# Lafferty2.net
KiCad netlist of a schematic drawn in EAGLE
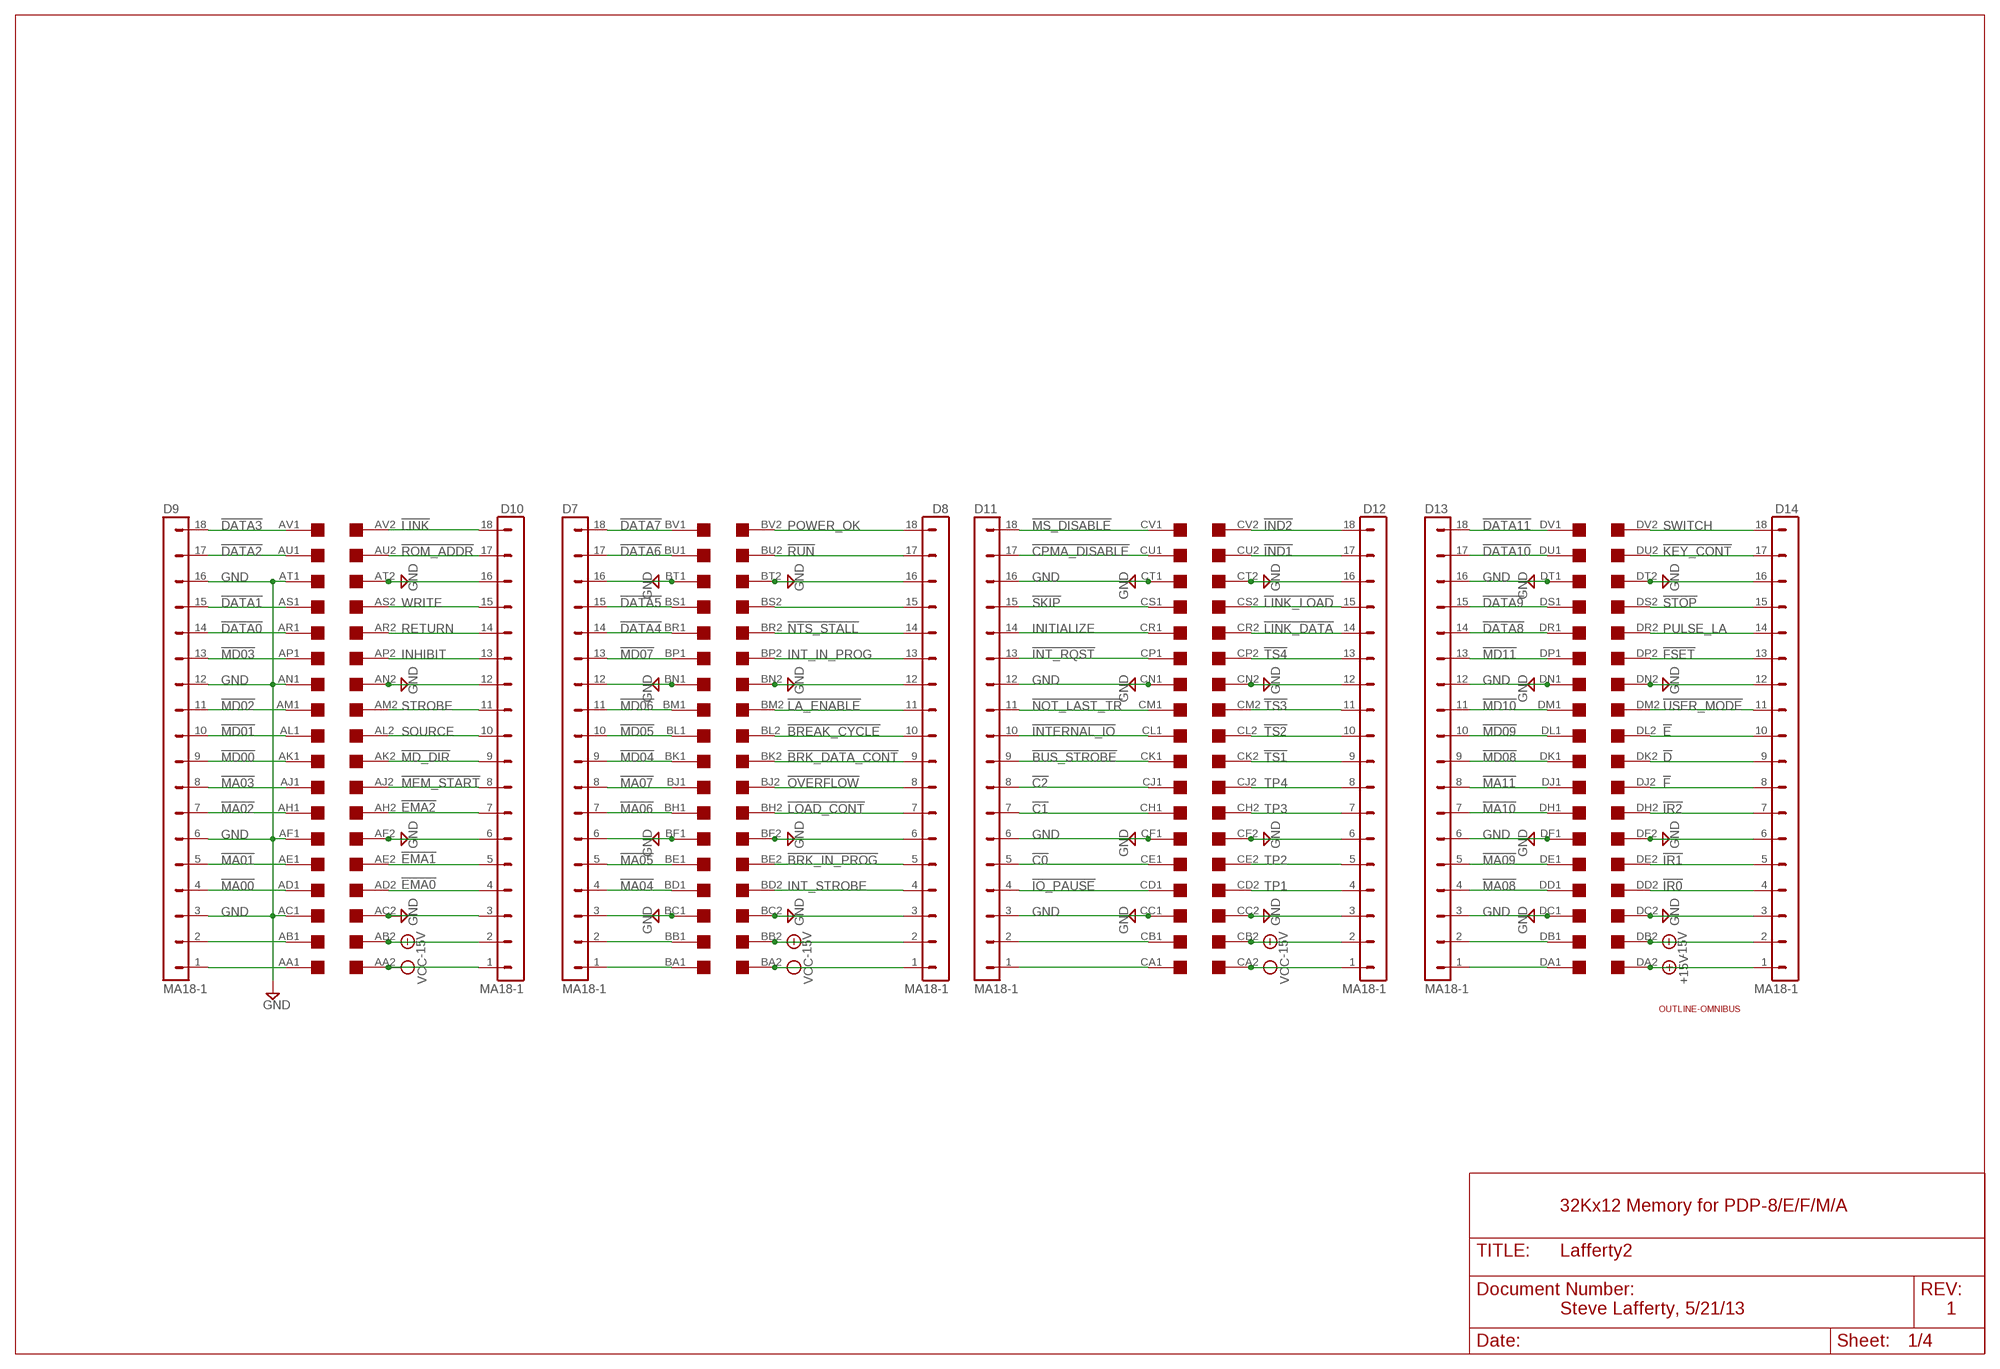
[diagram p0: schematic, sheet 1]
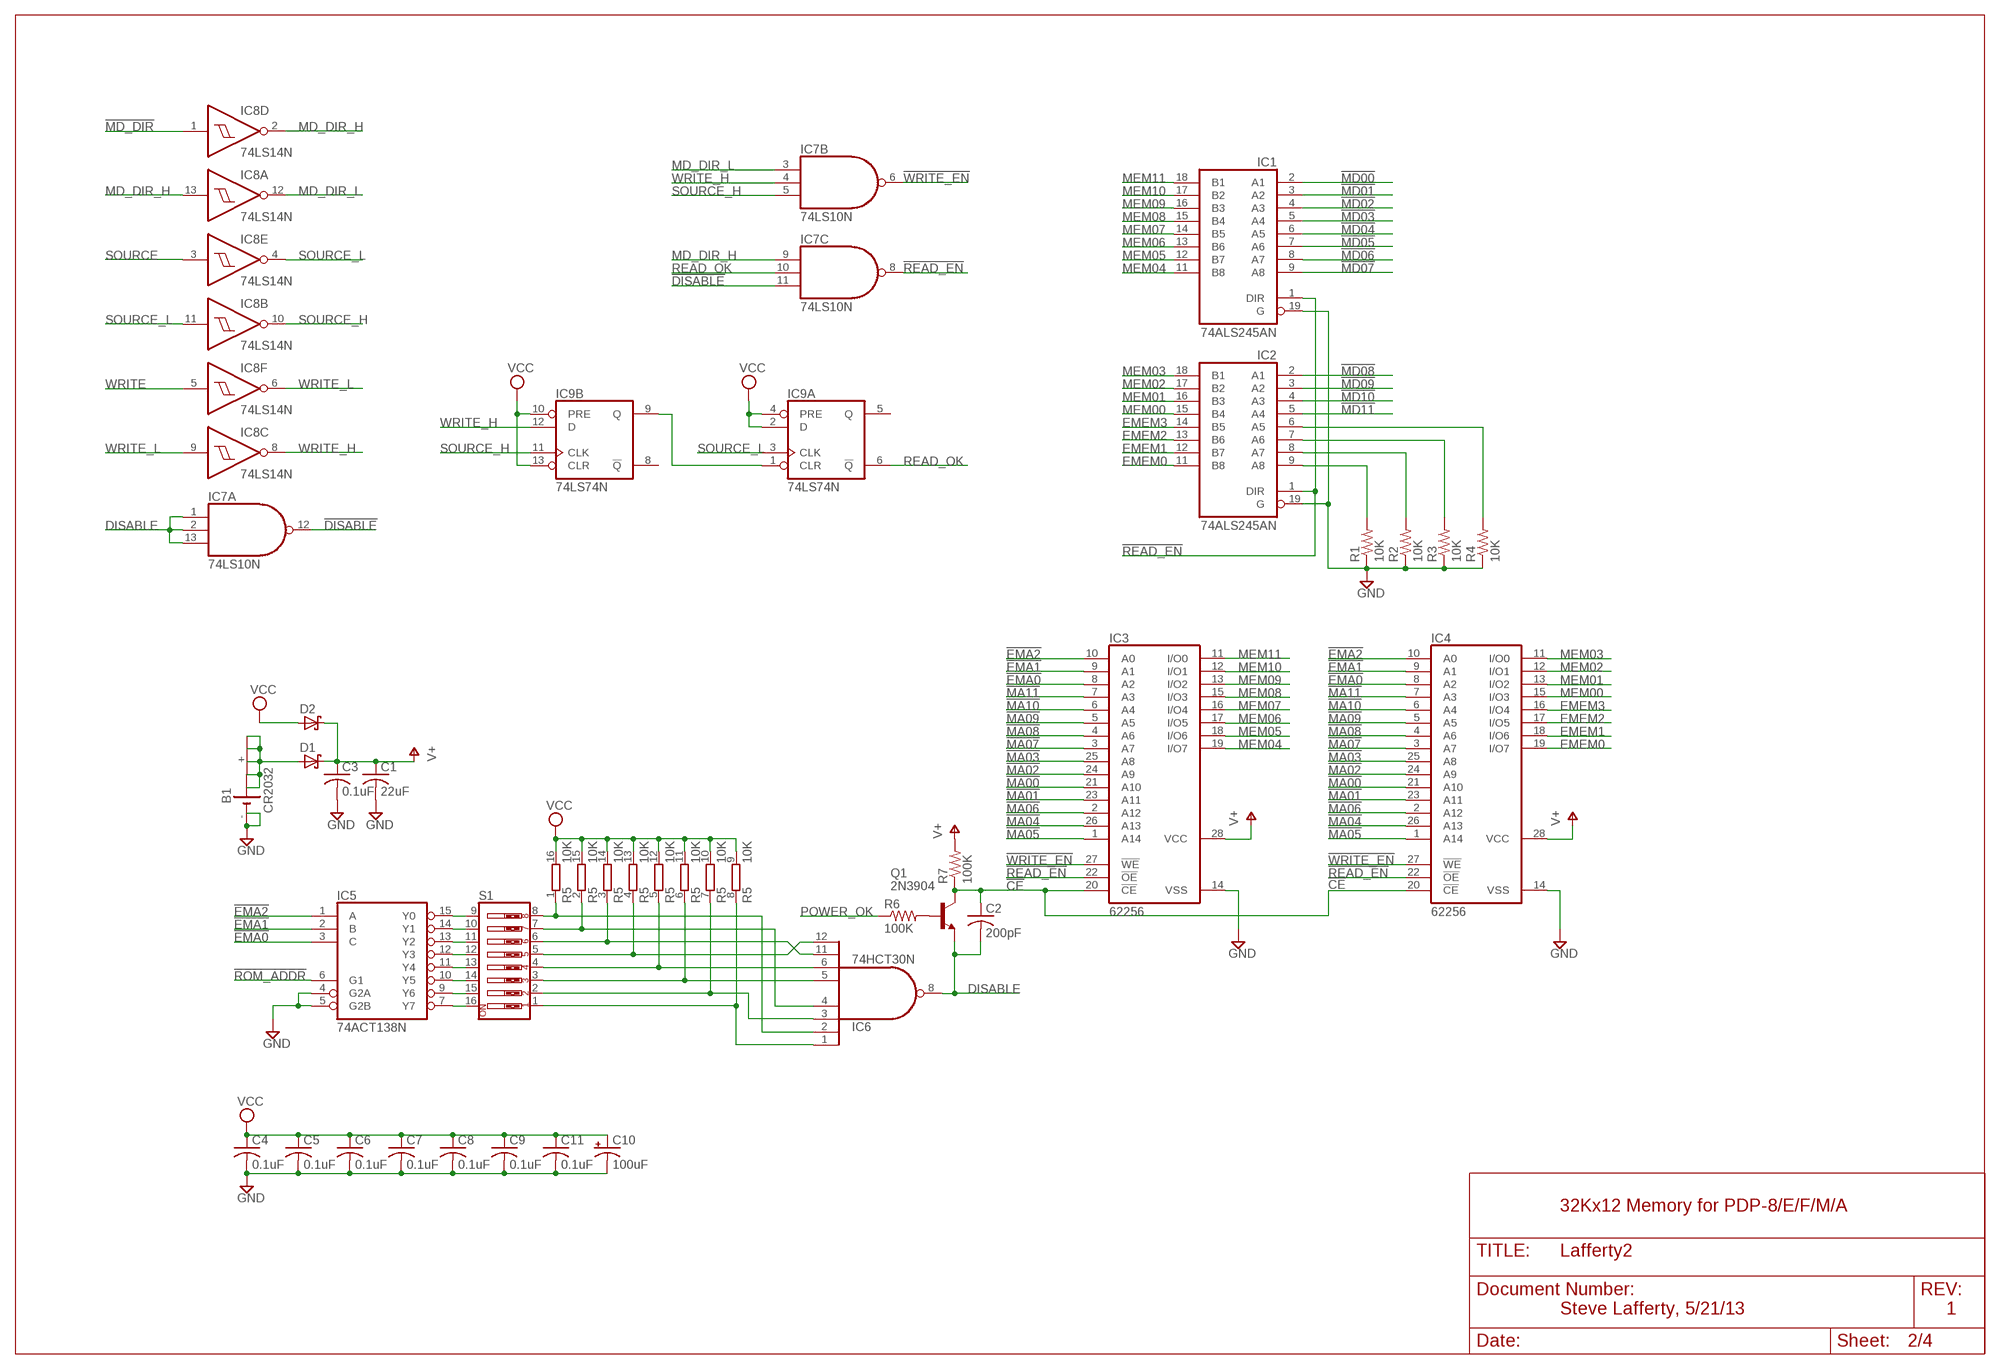
[diagram p1: schematic, sheet 2]
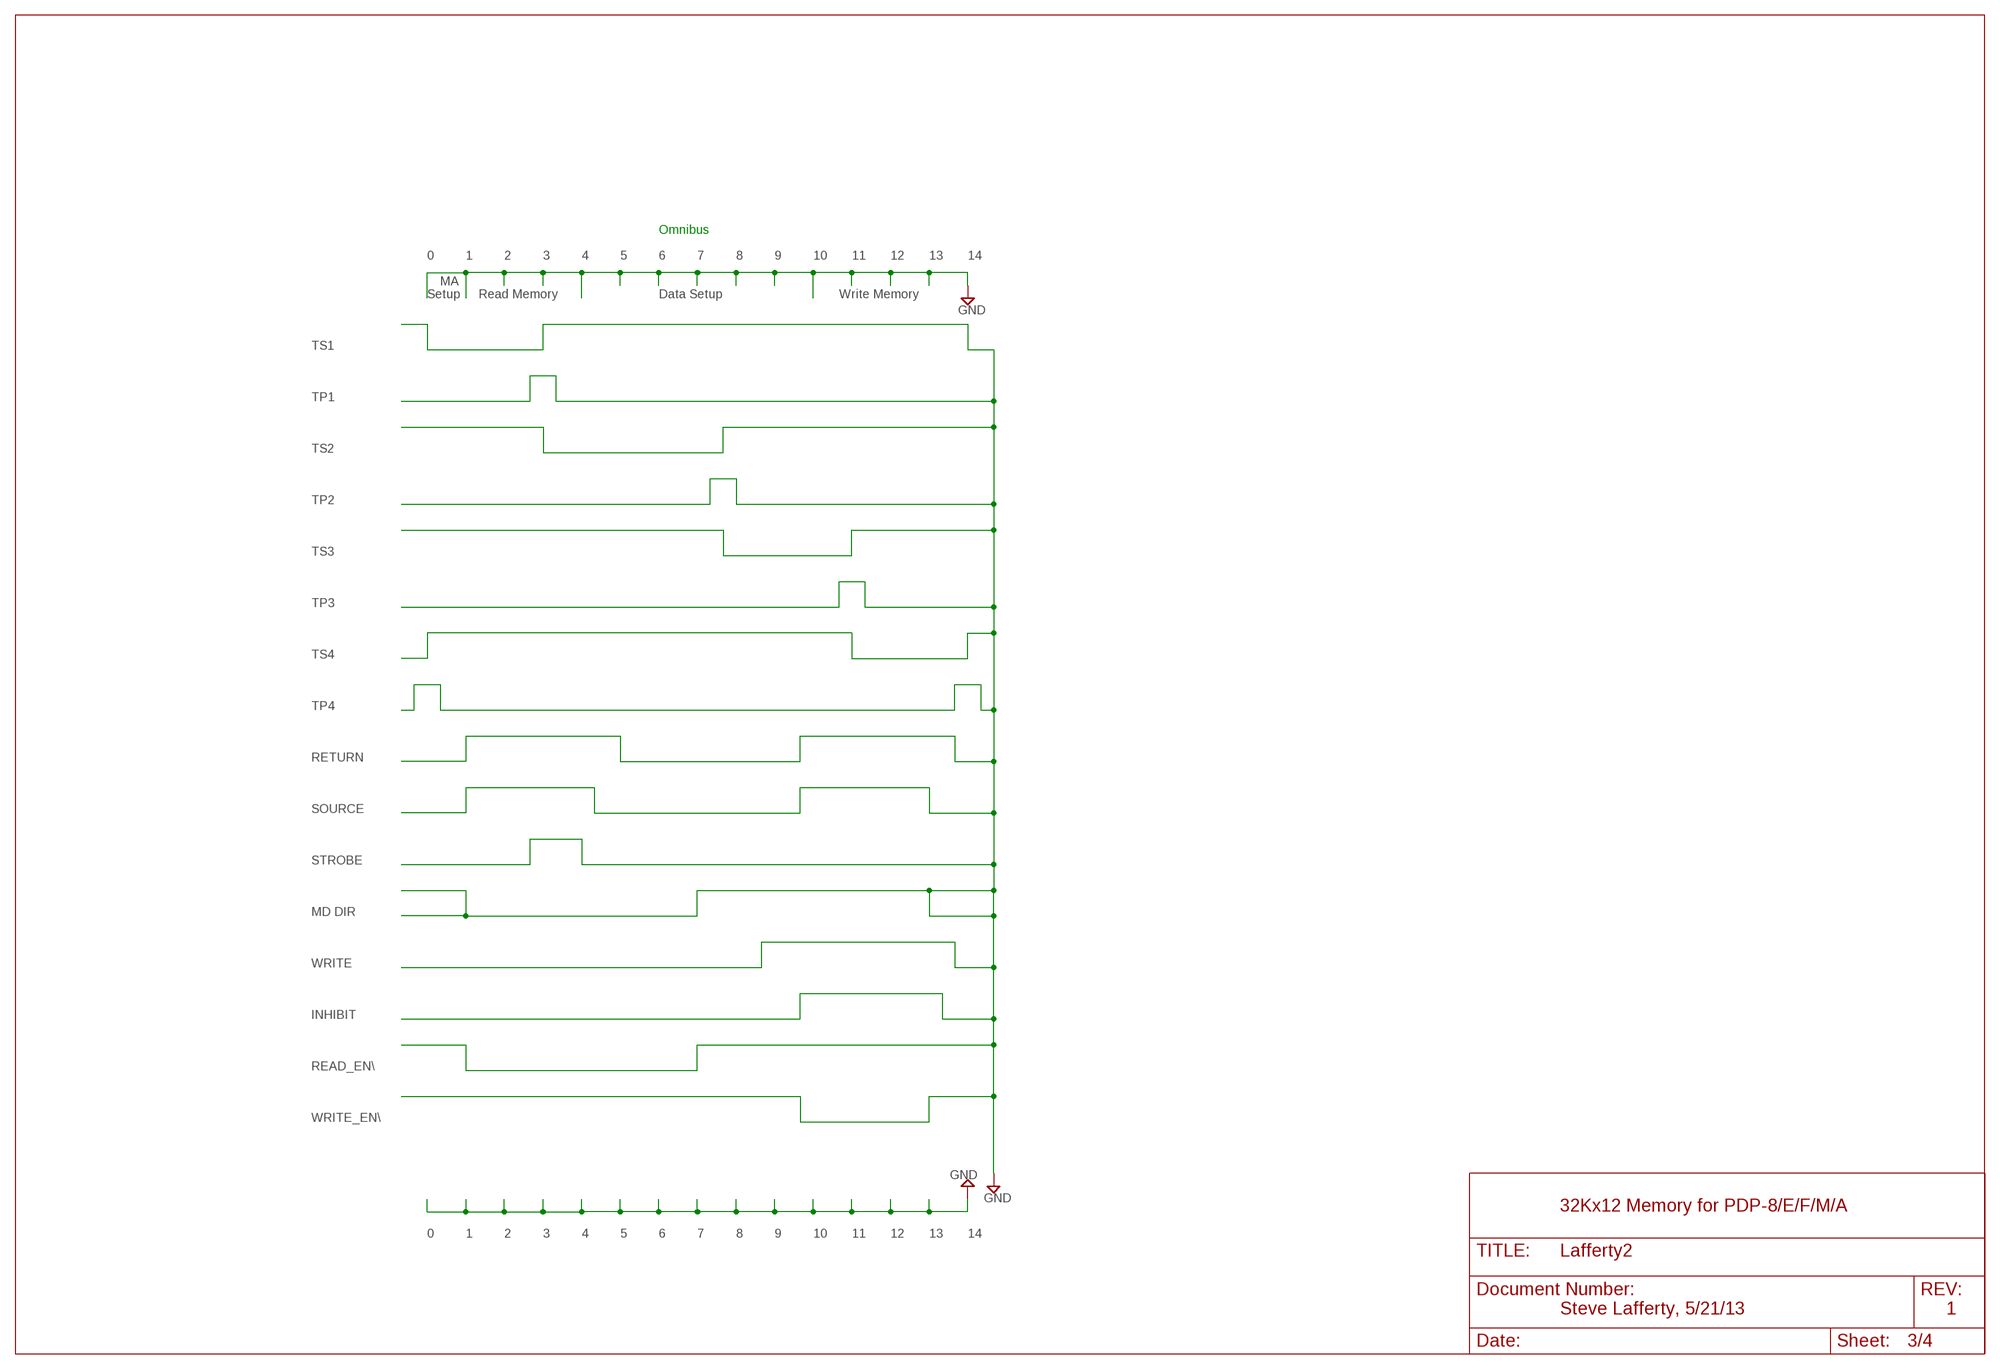
[diagram p2: schematic, sheet 3]
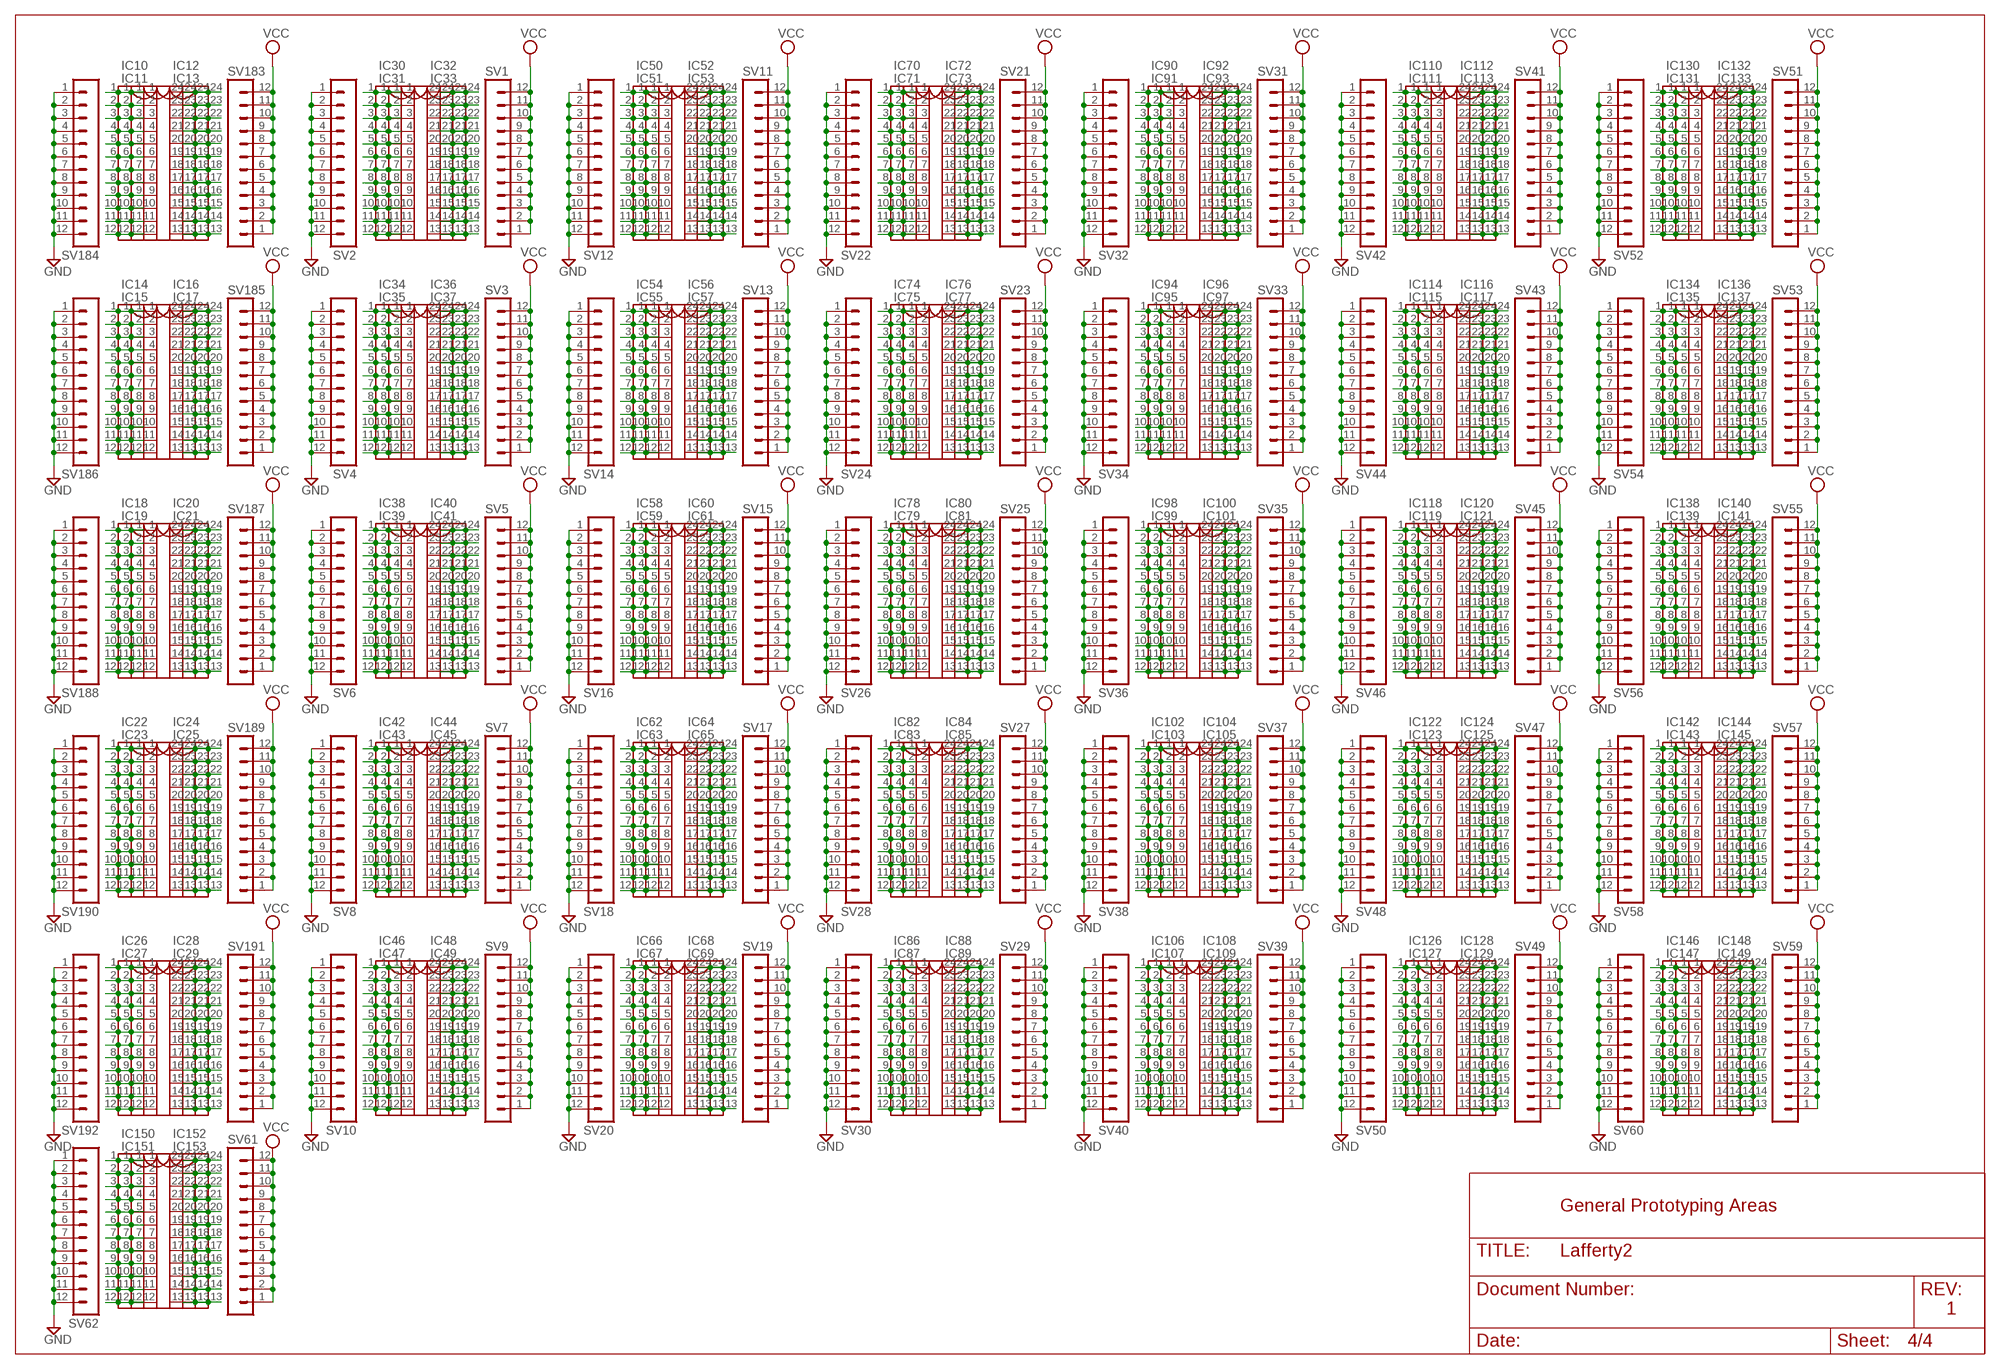
[diagram p3: schematic, sheet 4]

(export (version "E")
  (design (tool "Eeschema 10.0.6"))
  (components
    (comp (ref "D7")
      (value "MA18-1")
      (footprint "eagle-import:MA18-1")
      (libsource (lib "eagle-import") (part "MA18-1"))
    )
    (comp (ref "D8")
      (value "MA18-1")
      (footprint "eagle-import:MA18-1")
      (libsource (lib "eagle-import") (part "MA18-1"))
    )
    (comp (ref "D9")
      (value "MA18-1")
      (footprint "eagle-import:MA18-1")
      (libsource (lib "eagle-import") (part "MA18-1"))
    )
    (comp (ref "D10")
      (value "MA18-1")
      (footprint "eagle-import:MA18-1")
      (libsource (lib "eagle-import") (part "MA18-1"))
    )
    (comp (ref "D11")
      (value "MA18-1")
      (footprint "eagle-import:MA18-1")
      (libsource (lib "eagle-import") (part "MA18-1"))
    )
    (comp (ref "D12")
      (value "MA18-1")
      (footprint "eagle-import:MA18-1")
      (libsource (lib "eagle-import") (part "MA18-1"))
    )
    (comp (ref "D13")
      (value "MA18-1")
      (footprint "eagle-import:MA18-1")
      (libsource (lib "eagle-import") (part "MA18-1"))
    )
    (comp (ref "D14")
      (value "MA18-1")
      (footprint "eagle-import:MA18-1")
      (libsource (lib "eagle-import") (part "MA18-1"))
    )
    (comp (ref "U$1")
      (value "OUTLINE-OMNIBUS")
      (footprint "eagle-import:OMNIBUS")
      (libsource (lib "eagle-import") (part "OUTLINE-OMNIBUS"))
    )
    (comp (ref "U$2")
      (value "QUAD")
      (footprint "eagle-import:EDGE-CON8")
      (libsource (lib "eagle-import") (part "QUAD"))
    )
    (comp (ref "B1")
      (value "CR2032")
      (footprint "eagle-import:B2430UNI")
      (libsource (lib "eagle-import") (part "B2430UNI"))
    )
    (comp (ref "C1")
      (value "22uF")
      (footprint "eagle-import:C050-025X075")
      (libsource (lib "eagle-import") (part "C-US050-025X075"))
    )
    (comp (ref "C2")
      (value "200pF")
      (footprint "eagle-import:C050-025X075")
      (libsource (lib "eagle-import") (part "C-US050-025X075"))
    )
    (comp (ref "C3")
      (value "0.1uF")
      (footprint "eagle-import:C050-025X075")
      (libsource (lib "eagle-import") (part "C-US050-025X075"))
    )
    (comp (ref "C4")
      (value "0.1uF")
      (footprint "eagle-import:C050-025X075")
      (libsource (lib "eagle-import") (part "C-US050-025X075"))
    )
    (comp (ref "C5")
      (value "0.1uF")
      (footprint "eagle-import:C050-025X075")
      (libsource (lib "eagle-import") (part "C-US050-025X075"))
    )
    (comp (ref "C6")
      (value "0.1uF")
      (footprint "eagle-import:C050-025X075")
      (libsource (lib "eagle-import") (part "C-US050-025X075"))
    )
    (comp (ref "C7")
      (value "0.1uF")
      (footprint "eagle-import:C050-025X075")
      (libsource (lib "eagle-import") (part "C-US050-025X075"))
    )
    (comp (ref "C8")
      (value "0.1uF")
      (footprint "eagle-import:C050-025X075")
      (libsource (lib "eagle-import") (part "C-US050-025X075"))
    )
    (comp (ref "C9")
      (value "0.1uF")
      (footprint "eagle-import:C050-025X075")
      (libsource (lib "eagle-import") (part "C-US050-025X075"))
    )
    (comp (ref "C10")
      (value "100uF")
      (footprint "eagle-import:E12-8")
      (libsource (lib "eagle-import") (part "CPOL-USE20-8AXIAL"))
    )
    (comp (ref "C11")
      (value "0.1uF")
      (footprint "eagle-import:C050-025X075")
      (libsource (lib "eagle-import") (part "C-US050-025X075"))
    )
    (comp (ref "D1")
      (value "BAT19")
      (footprint "eagle-import:DO35-10")
      (libsource (lib "eagle-import") (part "BAT19"))
    )
    (comp (ref "D2")
      (value "BAT19")
      (footprint "eagle-import:DO35-10")
      (libsource (lib "eagle-import") (part "BAT19"))
    )
    (comp (ref "IC1")
      (value "74ALS245AN")
      (footprint "eagle-import:DIL20")
      (libsource (lib "eagle-import") (part "74245NLS"))
    )
    (comp (ref "IC2")
      (value "74ALS245AN")
      (footprint "eagle-import:DIL20")
      (libsource (lib "eagle-import") (part "74245NLS"))
    )
    (comp (ref "IC3")
      (value "62256")
      (footprint "eagle-import:DIL28-6")
      (fields (field (name "MPN") "HN58C256AP85E"))
      (libsource (lib "eagle-import") (part "58C256P"))
    )
    (comp (ref "IC4")
      (value "62256")
      (footprint "eagle-import:DIL28-6")
      (fields (field (name "MPN") "HN58C256AP85E"))
      (libsource (lib "eagle-import") (part "58C256P"))
    )
    (comp (ref "IC5")
      (value "74ACT138N")
      (footprint "eagle-import:DIL16")
      (libsource (lib "eagle-import") (part "74138NLS"))
    )
    (comp (ref "IC6")
      (value "74HCT30N")
      (footprint "eagle-import:DIL14")
      (libsource (lib "eagle-import") (part "7430NLS"))
    )
    (comp (ref "IC7")
      (value "74LS10N")
      (footprint "eagle-import:DIL14")
      (libsource (lib "eagle-import") (part "7410NLS"))
    )
    (comp (ref "IC8")
      (value "74LS14N")
      (footprint "eagle-import:DIL14")
      (libsource (lib "eagle-import") (part "7414NLS"))
    )
    (comp (ref "IC9")
      (value "74LS74N")
      (footprint "eagle-import:DIL14")
      (libsource (lib "eagle-import") (part "7474NLS"))
    )
    (comp (ref "Q1")
      (value "2N3904")
      (footprint "eagle-import:TO92")
      (libsource (lib "eagle-import") (part "2N3904"))
    )
    (comp (ref "R1")
      (value "10K")
      (footprint "eagle-import:0207_10")
      (libsource (lib "eagle-import") (part "R-US_0207/10"))
    )
    (comp (ref "R2")
      (value "10K")
      (footprint "eagle-import:0207_10")
      (libsource (lib "eagle-import") (part "R-US_0207/10"))
    )
    (comp (ref "R3")
      (value "10K")
      (footprint "eagle-import:0207_10")
      (libsource (lib "eagle-import") (part "R-US_0207/10"))
    )
    (comp (ref "R4")
      (value "10K")
      (footprint "eagle-import:0207_10")
      (libsource (lib "eagle-import") (part "R-US_0207/10"))
    )
    (comp (ref "R5")
      (value "10K")
      (footprint "eagle-import:DIL16")
      (libsource (lib "eagle-import") (part "8R-P"))
    )
    (comp (ref "R6")
      (value "100K")
      (footprint "eagle-import:0207_10")
      (libsource (lib "eagle-import") (part "R-US_0207/10"))
    )
    (comp (ref "R7")
      (value "100K")
      (footprint "eagle-import:0207_10")
      (libsource (lib "eagle-import") (part "R-US_0207/10"))
    )
    (comp (ref "S1")
      (value "SW_DIP-8")
      (footprint "eagle-import:EDG-08")
      (libsource (lib "eagle-import") (part "SW_DIP-8"))
    )
    (comp (ref "IC10")
      (value "DIL24-3")
      (footprint "eagle-import:DIL24-3")
      (libsource (lib "eagle-import") (part "DIL24-3"))
    )
    (comp (ref "IC11")
      (value "DIL24-6")
      (footprint "eagle-import:DIL24-6")
      (libsource (lib "eagle-import") (part "DIL24-6"))
    )
    (comp (ref "IC12")
      (value "DIL24-9")
      (footprint "eagle-import:DIL24-9")
      (libsource (lib "eagle-import") (part "DIL24-9"))
    )
    (comp (ref "IC13")
      (value "DIL24-6")
      (footprint "eagle-import:DIL24-6")
      (libsource (lib "eagle-import") (part "DIL24-6"))
    )
    (comp (ref "IC14")
      (value "DIL24-3")
      (footprint "eagle-import:DIL24-3")
      (libsource (lib "eagle-import") (part "DIL24-3"))
    )
    (comp (ref "IC15")
      (value "DIL24-6")
      (footprint "eagle-import:DIL24-6")
      (libsource (lib "eagle-import") (part "DIL24-6"))
    )
    (comp (ref "IC16")
      (value "DIL24-9")
      (footprint "eagle-import:DIL24-9")
      (libsource (lib "eagle-import") (part "DIL24-9"))
    )
    (comp (ref "IC17")
      (value "DIL24-6")
      (footprint "eagle-import:DIL24-6")
      (libsource (lib "eagle-import") (part "DIL24-6"))
    )
    (comp (ref "IC18")
      (value "DIL24-3")
      (footprint "eagle-import:DIL24-3")
      (libsource (lib "eagle-import") (part "DIL24-3"))
    )
    (comp (ref "IC19")
      (value "DIL24-6")
      (footprint "eagle-import:DIL24-6")
      (libsource (lib "eagle-import") (part "DIL24-6"))
    )
    (comp (ref "IC20")
      (value "DIL24-9")
      (footprint "eagle-import:DIL24-9")
      (libsource (lib "eagle-import") (part "DIL24-9"))
    )
    (comp (ref "IC21")
      (value "DIL24-6")
      (footprint "eagle-import:DIL24-6")
      (libsource (lib "eagle-import") (part "DIL24-6"))
    )
    (comp (ref "IC22")
      (value "DIL24-3")
      (footprint "eagle-import:DIL24-3")
      (libsource (lib "eagle-import") (part "DIL24-3"))
    )
    (comp (ref "IC23")
      (value "DIL24-6")
      (footprint "eagle-import:DIL24-6")
      (libsource (lib "eagle-import") (part "DIL24-6"))
    )
    (comp (ref "IC24")
      (value "DIL24-9")
      (footprint "eagle-import:DIL24-9")
      (libsource (lib "eagle-import") (part "DIL24-9"))
    )
    (comp (ref "IC25")
      (value "DIL24-6")
      (footprint "eagle-import:DIL24-6")
      (libsource (lib "eagle-import") (part "DIL24-6"))
    )
    (comp (ref "IC26")
      (value "DIL24-3")
      (footprint "eagle-import:DIL24-3")
      (libsource (lib "eagle-import") (part "DIL24-3"))
    )
    (comp (ref "IC27")
      (value "DIL24-6")
      (footprint "eagle-import:DIL24-6")
      (libsource (lib "eagle-import") (part "DIL24-6"))
    )
    (comp (ref "IC28")
      (value "DIL24-9")
      (footprint "eagle-import:DIL24-9")
      (libsource (lib "eagle-import") (part "DIL24-9"))
    )
    (comp (ref "IC29")
      (value "DIL24-6")
      (footprint "eagle-import:DIL24-6")
      (libsource (lib "eagle-import") (part "DIL24-6"))
    )
    (comp (ref "IC30")
      (value "DIL24-3")
      (footprint "eagle-import:DIL24-3")
      (libsource (lib "eagle-import") (part "DIL24-3"))
    )
    (comp (ref "IC31")
      (value "DIL24-6")
      (footprint "eagle-import:DIL24-6")
      (libsource (lib "eagle-import") (part "DIL24-6"))
    )
    (comp (ref "IC32")
      (value "DIL24-9")
      (footprint "eagle-import:DIL24-9")
      (libsource (lib "eagle-import") (part "DIL24-9"))
    )
    (comp (ref "IC33")
      (value "DIL24-6")
      (footprint "eagle-import:DIL24-6")
      (libsource (lib "eagle-import") (part "DIL24-6"))
    )
    (comp (ref "IC34")
      (value "DIL24-3")
      (footprint "eagle-import:DIL24-3")
      (libsource (lib "eagle-import") (part "DIL24-3"))
    )
    (comp (ref "IC35")
      (value "DIL24-6")
      (footprint "eagle-import:DIL24-6")
      (libsource (lib "eagle-import") (part "DIL24-6"))
    )
    (comp (ref "IC36")
      (value "DIL24-9")
      (footprint "eagle-import:DIL24-9")
      (libsource (lib "eagle-import") (part "DIL24-9"))
    )
    (comp (ref "IC37")
      (value "DIL24-6")
      (footprint "eagle-import:DIL24-6")
      (libsource (lib "eagle-import") (part "DIL24-6"))
    )
    (comp (ref "IC38")
      (value "DIL24-3")
      (footprint "eagle-import:DIL24-3")
      (libsource (lib "eagle-import") (part "DIL24-3"))
    )
    (comp (ref "IC39")
      (value "DIL24-6")
      (footprint "eagle-import:DIL24-6")
      (libsource (lib "eagle-import") (part "DIL24-6"))
    )
    (comp (ref "IC40")
      (value "DIL24-9")
      (footprint "eagle-import:DIL24-9")
      (libsource (lib "eagle-import") (part "DIL24-9"))
    )
    (comp (ref "IC41")
      (value "DIL24-6")
      (footprint "eagle-import:DIL24-6")
      (libsource (lib "eagle-import") (part "DIL24-6"))
    )
    (comp (ref "IC42")
      (value "DIL24-3")
      (footprint "eagle-import:DIL24-3")
      (libsource (lib "eagle-import") (part "DIL24-3"))
    )
    (comp (ref "IC43")
      (value "DIL24-6")
      (footprint "eagle-import:DIL24-6")
      (libsource (lib "eagle-import") (part "DIL24-6"))
    )
    (comp (ref "IC44")
      (value "DIL24-9")
      (footprint "eagle-import:DIL24-9")
      (libsource (lib "eagle-import") (part "DIL24-9"))
    )
    (comp (ref "IC45")
      (value "DIL24-6")
      (footprint "eagle-import:DIL24-6")
      (libsource (lib "eagle-import") (part "DIL24-6"))
    )
    (comp (ref "IC46")
      (value "DIL24-3")
      (footprint "eagle-import:DIL24-3")
      (libsource (lib "eagle-import") (part "DIL24-3"))
    )
    (comp (ref "IC47")
      (value "DIL24-6")
      (footprint "eagle-import:DIL24-6")
      (libsource (lib "eagle-import") (part "DIL24-6"))
    )
    (comp (ref "IC48")
      (value "DIL24-9")
      (footprint "eagle-import:DIL24-9")
      (libsource (lib "eagle-import") (part "DIL24-9"))
    )
    (comp (ref "IC49")
      (value "DIL24-6")
      (footprint "eagle-import:DIL24-6")
      (libsource (lib "eagle-import") (part "DIL24-6"))
    )
    (comp (ref "IC50")
      (value "DIL24-3")
      (footprint "eagle-import:DIL24-3")
      (libsource (lib "eagle-import") (part "DIL24-3"))
    )
    (comp (ref "IC51")
      (value "DIL24-6")
      (footprint "eagle-import:DIL24-6")
      (libsource (lib "eagle-import") (part "DIL24-6"))
    )
    (comp (ref "IC52")
      (value "DIL24-9")
      (footprint "eagle-import:DIL24-9")
      (libsource (lib "eagle-import") (part "DIL24-9"))
    )
    (comp (ref "IC53")
      (value "DIL24-6")
      (footprint "eagle-import:DIL24-6")
      (libsource (lib "eagle-import") (part "DIL24-6"))
    )
    (comp (ref "IC54")
      (value "DIL24-3")
      (footprint "eagle-import:DIL24-3")
      (libsource (lib "eagle-import") (part "DIL24-3"))
    )
    (comp (ref "IC55")
      (value "DIL24-6")
      (footprint "eagle-import:DIL24-6")
      (libsource (lib "eagle-import") (part "DIL24-6"))
    )
    (comp (ref "IC56")
      (value "DIL24-9")
      (footprint "eagle-import:DIL24-9")
      (libsource (lib "eagle-import") (part "DIL24-9"))
    )
    (comp (ref "IC57")
      (value "DIL24-6")
      (footprint "eagle-import:DIL24-6")
      (libsource (lib "eagle-import") (part "DIL24-6"))
    )
    (comp (ref "IC58")
      (value "DIL24-3")
      (footprint "eagle-import:DIL24-3")
      (libsource (lib "eagle-import") (part "DIL24-3"))
    )
    (comp (ref "IC59")
      (value "DIL24-6")
      (footprint "eagle-import:DIL24-6")
      (libsource (lib "eagle-import") (part "DIL24-6"))
    )
    (comp (ref "IC60")
      (value "DIL24-9")
      (footprint "eagle-import:DIL24-9")
      (libsource (lib "eagle-import") (part "DIL24-9"))
    )
    (comp (ref "IC61")
      (value "DIL24-6")
      (footprint "eagle-import:DIL24-6")
      (libsource (lib "eagle-import") (part "DIL24-6"))
    )
    (comp (ref "IC62")
      (value "DIL24-3")
      (footprint "eagle-import:DIL24-3")
      (libsource (lib "eagle-import") (part "DIL24-3"))
    )
    (comp (ref "IC63")
      (value "DIL24-6")
      (footprint "eagle-import:DIL24-6")
      (libsource (lib "eagle-import") (part "DIL24-6"))
    )
    (comp (ref "IC64")
      (value "DIL24-9")
      (footprint "eagle-import:DIL24-9")
      (libsource (lib "eagle-import") (part "DIL24-9"))
    )
    (comp (ref "IC65")
      (value "DIL24-6")
      (footprint "eagle-import:DIL24-6")
      (libsource (lib "eagle-import") (part "DIL24-6"))
    )
    (comp (ref "IC66")
      (value "DIL24-3")
      (footprint "eagle-import:DIL24-3")
      (libsource (lib "eagle-import") (part "DIL24-3"))
    )
    (comp (ref "IC67")
      (value "DIL24-6")
      (footprint "eagle-import:DIL24-6")
      (libsource (lib "eagle-import") (part "DIL24-6"))
    )
    (comp (ref "IC68")
      (value "DIL24-9")
      (footprint "eagle-import:DIL24-9")
      (libsource (lib "eagle-import") (part "DIL24-9"))
    )
    (comp (ref "IC69")
      (value "DIL24-6")
      (footprint "eagle-import:DIL24-6")
      (libsource (lib "eagle-import") (part "DIL24-6"))
    )
    (comp (ref "IC70")
      (value "DIL24-3")
      (footprint "eagle-import:DIL24-3")
      (libsource (lib "eagle-import") (part "DIL24-3"))
    )
    (comp (ref "IC71")
      (value "DIL24-6")
      (footprint "eagle-import:DIL24-6")
      (libsource (lib "eagle-import") (part "DIL24-6"))
    )
    (comp (ref "IC72")
      (value "DIL24-9")
      (footprint "eagle-import:DIL24-9")
      (libsource (lib "eagle-import") (part "DIL24-9"))
    )
    (comp (ref "IC73")
      (value "DIL24-6")
      (footprint "eagle-import:DIL24-6")
      (libsource (lib "eagle-import") (part "DIL24-6"))
    )
    (comp (ref "IC74")
      (value "DIL24-3")
      (footprint "eagle-import:DIL24-3")
      (libsource (lib "eagle-import") (part "DIL24-3"))
    )
    (comp (ref "IC75")
      (value "DIL24-6")
      (footprint "eagle-import:DIL24-6")
      (libsource (lib "eagle-import") (part "DIL24-6"))
    )
    (comp (ref "IC76")
      (value "DIL24-9")
      (footprint "eagle-import:DIL24-9")
      (libsource (lib "eagle-import") (part "DIL24-9"))
    )
    (comp (ref "IC77")
      (value "DIL24-6")
      (footprint "eagle-import:DIL24-6")
      (libsource (lib "eagle-import") (part "DIL24-6"))
    )
    (comp (ref "IC78")
      (value "DIL24-3")
      (footprint "eagle-import:DIL24-3")
      (libsource (lib "eagle-import") (part "DIL24-3"))
    )
    (comp (ref "IC79")
      (value "DIL24-6")
      (footprint "eagle-import:DIL24-6")
      (libsource (lib "eagle-import") (part "DIL24-6"))
    )
    (comp (ref "IC80")
      (value "DIL24-9")
      (footprint "eagle-import:DIL24-9")
      (libsource (lib "eagle-import") (part "DIL24-9"))
    )
    (comp (ref "IC81")
      (value "DIL24-6")
      (footprint "eagle-import:DIL24-6")
      (libsource (lib "eagle-import") (part "DIL24-6"))
    )
    (comp (ref "IC82")
      (value "DIL24-3")
      (footprint "eagle-import:DIL24-3")
      (libsource (lib "eagle-import") (part "DIL24-3"))
    )
    (comp (ref "IC83")
      (value "DIL24-6")
      (footprint "eagle-import:DIL24-6")
      (libsource (lib "eagle-import") (part "DIL24-6"))
    )
    (comp (ref "IC84")
      (value "DIL24-9")
      (footprint "eagle-import:DIL24-9")
      (libsource (lib "eagle-import") (part "DIL24-9"))
    )
    (comp (ref "IC85")
      (value "DIL24-6")
      (footprint "eagle-import:DIL24-6")
      (libsource (lib "eagle-import") (part "DIL24-6"))
    )
    (comp (ref "IC86")
      (value "DIL24-3")
      (footprint "eagle-import:DIL24-3")
      (libsource (lib "eagle-import") (part "DIL24-3"))
    )
    (comp (ref "IC87")
      (value "DIL24-6")
      (footprint "eagle-import:DIL24-6")
      (libsource (lib "eagle-import") (part "DIL24-6"))
    )
    (comp (ref "IC88")
      (value "DIL24-9")
      (footprint "eagle-import:DIL24-9")
      (libsource (lib "eagle-import") (part "DIL24-9"))
    )
    (comp (ref "IC89")
      (value "DIL24-6")
      (footprint "eagle-import:DIL24-6")
      (libsource (lib "eagle-import") (part "DIL24-6"))
    )
    (comp (ref "IC90")
      (value "DIL24-3")
      (footprint "eagle-import:DIL24-3")
      (libsource (lib "eagle-import") (part "DIL24-3"))
    )
    (comp (ref "IC91")
      (value "DIL24-6")
      (footprint "eagle-import:DIL24-6")
      (libsource (lib "eagle-import") (part "DIL24-6"))
    )
    (comp (ref "IC92")
      (value "DIL24-9")
      (footprint "eagle-import:DIL24-9")
      (libsource (lib "eagle-import") (part "DIL24-9"))
    )
    (comp (ref "IC93")
      (value "DIL24-6")
      (footprint "eagle-import:DIL24-6")
      (libsource (lib "eagle-import") (part "DIL24-6"))
    )
    (comp (ref "IC94")
      (value "DIL24-3")
      (footprint "eagle-import:DIL24-3")
      (libsource (lib "eagle-import") (part "DIL24-3"))
    )
    (comp (ref "IC95")
      (value "DIL24-6")
      (footprint "eagle-import:DIL24-6")
      (libsource (lib "eagle-import") (part "DIL24-6"))
    )
    (comp (ref "IC96")
      (value "DIL24-9")
      (footprint "eagle-import:DIL24-9")
      (libsource (lib "eagle-import") (part "DIL24-9"))
    )
    (comp (ref "IC97")
      (value "DIL24-6")
      (footprint "eagle-import:DIL24-6")
      (libsource (lib "eagle-import") (part "DIL24-6"))
    )
    (comp (ref "IC98")
      (value "DIL24-3")
      (footprint "eagle-import:DIL24-3")
      (libsource (lib "eagle-import") (part "DIL24-3"))
    )
    (comp (ref "IC99")
      (value "DIL24-6")
      (footprint "eagle-import:DIL24-6")
      (libsource (lib "eagle-import") (part "DIL24-6"))
    )
    (comp (ref "IC100")
      (value "DIL24-9")
      (footprint "eagle-import:DIL24-9")
      (libsource (lib "eagle-import") (part "DIL24-9"))
    )
    (comp (ref "IC101")
      (value "DIL24-6")
      (footprint "eagle-import:DIL24-6")
      (libsource (lib "eagle-import") (part "DIL24-6"))
    )
    (comp (ref "IC102")
      (value "DIL24-3")
      (footprint "eagle-import:DIL24-3")
      (libsource (lib "eagle-import") (part "DIL24-3"))
    )
    (comp (ref "IC103")
      (value "DIL24-6")
      (footprint "eagle-import:DIL24-6")
      (libsource (lib "eagle-import") (part "DIL24-6"))
    )
    (comp (ref "IC104")
      (value "DIL24-9")
      (footprint "eagle-import:DIL24-9")
      (libsource (lib "eagle-import") (part "DIL24-9"))
    )
    (comp (ref "IC105")
      (value "DIL24-6")
      (footprint "eagle-import:DIL24-6")
      (libsource (lib "eagle-import") (part "DIL24-6"))
    )
    (comp (ref "IC106")
      (value "DIL24-3")
      (footprint "eagle-import:DIL24-3")
      (libsource (lib "eagle-import") (part "DIL24-3"))
    )
    (comp (ref "IC107")
      (value "DIL24-6")
      (footprint "eagle-import:DIL24-6")
      (libsource (lib "eagle-import") (part "DIL24-6"))
    )
    (comp (ref "IC108")
      (value "DIL24-9")
      (footprint "eagle-import:DIL24-9")
      (libsource (lib "eagle-import") (part "DIL24-9"))
    )
    (comp (ref "IC109")
      (value "DIL24-6")
      (footprint "eagle-import:DIL24-6")
      (libsource (lib "eagle-import") (part "DIL24-6"))
    )
    (comp (ref "IC110")
      (value "DIL24-3")
      (footprint "eagle-import:DIL24-3")
      (libsource (lib "eagle-import") (part "DIL24-3"))
    )
    (comp (ref "IC111")
      (value "DIL24-6")
      (footprint "eagle-import:DIL24-6")
      (libsource (lib "eagle-import") (part "DIL24-6"))
    )
    (comp (ref "IC112")
      (value "DIL24-9")
      (footprint "eagle-import:DIL24-9")
      (libsource (lib "eagle-import") (part "DIL24-9"))
    )
    (comp (ref "IC113")
      (value "DIL24-6")
      (footprint "eagle-import:DIL24-6")
      (libsource (lib "eagle-import") (part "DIL24-6"))
    )
    (comp (ref "IC114")
      (value "DIL24-3")
      (footprint "eagle-import:DIL24-3")
      (libsource (lib "eagle-import") (part "DIL24-3"))
    )
    (comp (ref "IC115")
      (value "DIL24-6")
      (footprint "eagle-import:DIL24-6")
      (libsource (lib "eagle-import") (part "DIL24-6"))
    )
    (comp (ref "IC116")
      (value "DIL24-9")
      (footprint "eagle-import:DIL24-9")
      (libsource (lib "eagle-import") (part "DIL24-9"))
    )
    (comp (ref "IC117")
      (value "DIL24-6")
      (footprint "eagle-import:DIL24-6")
      (libsource (lib "eagle-import") (part "DIL24-6"))
    )
    (comp (ref "IC118")
      (value "DIL24-3")
      (footprint "eagle-import:DIL24-3")
      (libsource (lib "eagle-import") (part "DIL24-3"))
    )
    (comp (ref "IC119")
      (value "DIL24-6")
      (footprint "eagle-import:DIL24-6")
      (libsource (lib "eagle-import") (part "DIL24-6"))
    )
    (comp (ref "IC120")
      (value "DIL24-9")
      (footprint "eagle-import:DIL24-9")
      (libsource (lib "eagle-import") (part "DIL24-9"))
    )
    (comp (ref "IC121")
      (value "DIL24-6")
      (footprint "eagle-import:DIL24-6")
      (libsource (lib "eagle-import") (part "DIL24-6"))
    )
    (comp (ref "IC122")
      (value "DIL24-3")
      (footprint "eagle-import:DIL24-3")
      (libsource (lib "eagle-import") (part "DIL24-3"))
    )
    (comp (ref "IC123")
      (value "DIL24-6")
      (footprint "eagle-import:DIL24-6")
      (libsource (lib "eagle-import") (part "DIL24-6"))
    )
    (comp (ref "IC124")
      (value "DIL24-9")
      (footprint "eagle-import:DIL24-9")
      (libsource (lib "eagle-import") (part "DIL24-9"))
    )
    (comp (ref "IC125")
      (value "DIL24-6")
      (footprint "eagle-import:DIL24-6")
      (libsource (lib "eagle-import") (part "DIL24-6"))
    )
    (comp (ref "IC126")
      (value "DIL24-3")
      (footprint "eagle-import:DIL24-3")
      (libsource (lib "eagle-import") (part "DIL24-3"))
    )
    (comp (ref "IC127")
      (value "DIL24-6")
      (footprint "eagle-import:DIL24-6")
      (libsource (lib "eagle-import") (part "DIL24-6"))
    )
    (comp (ref "IC128")
      (value "DIL24-9")
      (footprint "eagle-import:DIL24-9")
      (libsource (lib "eagle-import") (part "DIL24-9"))
    )
    (comp (ref "IC129")
      (value "DIL24-6")
      (footprint "eagle-import:DIL24-6")
      (libsource (lib "eagle-import") (part "DIL24-6"))
    )
    (comp (ref "IC130")
      (value "DIL24-3")
      (footprint "eagle-import:DIL24-3")
      (libsource (lib "eagle-import") (part "DIL24-3"))
    )
    (comp (ref "IC131")
      (value "DIL24-6")
      (footprint "eagle-import:DIL24-6")
      (libsource (lib "eagle-import") (part "DIL24-6"))
    )
    (comp (ref "IC132")
      (value "DIL24-9")
      (footprint "eagle-import:DIL24-9")
      (libsource (lib "eagle-import") (part "DIL24-9"))
    )
    (comp (ref "IC133")
      (value "DIL24-6")
      (footprint "eagle-import:DIL24-6")
      (libsource (lib "eagle-import") (part "DIL24-6"))
    )
    (comp (ref "IC134")
      (value "DIL24-3")
      (footprint "eagle-import:DIL24-3")
      (libsource (lib "eagle-import") (part "DIL24-3"))
    )
    (comp (ref "IC135")
      (value "DIL24-6")
      (footprint "eagle-import:DIL24-6")
      (libsource (lib "eagle-import") (part "DIL24-6"))
    )
    (comp (ref "IC136")
      (value "DIL24-9")
      (footprint "eagle-import:DIL24-9")
      (libsource (lib "eagle-import") (part "DIL24-9"))
    )
    (comp (ref "IC137")
      (value "DIL24-6")
      (footprint "eagle-import:DIL24-6")
      (libsource (lib "eagle-import") (part "DIL24-6"))
    )
    (comp (ref "IC138")
      (value "DIL24-3")
      (footprint "eagle-import:DIL24-3")
      (libsource (lib "eagle-import") (part "DIL24-3"))
    )
    (comp (ref "IC139")
      (value "DIL24-6")
      (footprint "eagle-import:DIL24-6")
      (libsource (lib "eagle-import") (part "DIL24-6"))
    )
    (comp (ref "IC140")
      (value "DIL24-9")
      (footprint "eagle-import:DIL24-9")
      (libsource (lib "eagle-import") (part "DIL24-9"))
    )
    (comp (ref "IC141")
      (value "DIL24-6")
      (footprint "eagle-import:DIL24-6")
      (libsource (lib "eagle-import") (part "DIL24-6"))
    )
    (comp (ref "IC142")
      (value "DIL24-3")
      (footprint "eagle-import:DIL24-3")
      (libsource (lib "eagle-import") (part "DIL24-3"))
    )
    (comp (ref "IC143")
      (value "DIL24-6")
      (footprint "eagle-import:DIL24-6")
      (libsource (lib "eagle-import") (part "DIL24-6"))
    )
    (comp (ref "IC144")
      (value "DIL24-9")
      (footprint "eagle-import:DIL24-9")
      (libsource (lib "eagle-import") (part "DIL24-9"))
    )
    (comp (ref "IC145")
      (value "DIL24-6")
      (footprint "eagle-import:DIL24-6")
      (libsource (lib "eagle-import") (part "DIL24-6"))
    )
    (comp (ref "IC146")
      (value "DIL24-3")
      (footprint "eagle-import:DIL24-3")
      (libsource (lib "eagle-import") (part "DIL24-3"))
    )
    (comp (ref "IC147")
      (value "DIL24-6")
      (footprint "eagle-import:DIL24-6")
      (libsource (lib "eagle-import") (part "DIL24-6"))
    )
    (comp (ref "IC148")
      (value "DIL24-9")
      (footprint "eagle-import:DIL24-9")
      (libsource (lib "eagle-import") (part "DIL24-9"))
    )
    (comp (ref "IC149")
      (value "DIL24-6")
      (footprint "eagle-import:DIL24-6")
      (libsource (lib "eagle-import") (part "DIL24-6"))
    )
    (comp (ref "IC150")
      (value "DIL24-3")
      (footprint "eagle-import:DIL24-3")
      (libsource (lib "eagle-import") (part "DIL24-3"))
    )
    (comp (ref "IC151")
      (value "DIL24-6")
      (footprint "eagle-import:DIL24-6")
      (libsource (lib "eagle-import") (part "DIL24-6"))
    )
    (comp (ref "IC152")
      (value "DIL24-9")
      (footprint "eagle-import:DIL24-9")
      (libsource (lib "eagle-import") (part "DIL24-9"))
    )
    (comp (ref "IC153")
      (value "DIL24-6")
      (footprint "eagle-import:DIL24-6")
      (libsource (lib "eagle-import") (part "DIL24-6"))
    )
    (comp (ref "SV1")
      (value "MA12-1")
      (footprint "eagle-import:MA12-1")
      (libsource (lib "eagle-import") (part "MA12-1"))
    )
    (comp (ref "SV2")
      (value "MA12-1")
      (footprint "eagle-import:MA12-1")
      (libsource (lib "eagle-import") (part "MA12-1"))
    )
    (comp (ref "SV3")
      (value "MA12-1")
      (footprint "eagle-import:MA12-1")
      (libsource (lib "eagle-import") (part "MA12-1"))
    )
    (comp (ref "SV4")
      (value "MA12-1")
      (footprint "eagle-import:MA12-1")
      (libsource (lib "eagle-import") (part "MA12-1"))
    )
    (comp (ref "SV5")
      (value "MA12-1")
      (footprint "eagle-import:MA12-1")
      (libsource (lib "eagle-import") (part "MA12-1"))
    )
    (comp (ref "SV6")
      (value "MA12-1")
      (footprint "eagle-import:MA12-1")
      (libsource (lib "eagle-import") (part "MA12-1"))
    )
    (comp (ref "SV7")
      (value "MA12-1")
      (footprint "eagle-import:MA12-1")
      (libsource (lib "eagle-import") (part "MA12-1"))
    )
    (comp (ref "SV8")
      (value "MA12-1")
      (footprint "eagle-import:MA12-1")
      (libsource (lib "eagle-import") (part "MA12-1"))
    )
    (comp (ref "SV9")
      (value "MA12-1")
      (footprint "eagle-import:MA12-1")
      (libsource (lib "eagle-import") (part "MA12-1"))
    )
    (comp (ref "SV10")
      (value "MA12-1")
      (footprint "eagle-import:MA12-1")
      (libsource (lib "eagle-import") (part "MA12-1"))
    )
    (comp (ref "SV11")
      (value "MA12-1")
      (footprint "eagle-import:MA12-1")
      (libsource (lib "eagle-import") (part "MA12-1"))
    )
    (comp (ref "SV12")
      (value "MA12-1")
      (footprint "eagle-import:MA12-1")
      (libsource (lib "eagle-import") (part "MA12-1"))
    )
    (comp (ref "SV13")
      (value "MA12-1")
      (footprint "eagle-import:MA12-1")
      (libsource (lib "eagle-import") (part "MA12-1"))
    )
    (comp (ref "SV14")
      (value "MA12-1")
      (footprint "eagle-import:MA12-1")
      (libsource (lib "eagle-import") (part "MA12-1"))
    )
    (comp (ref "SV15")
      (value "MA12-1")
      (footprint "eagle-import:MA12-1")
      (libsource (lib "eagle-import") (part "MA12-1"))
    )
    (comp (ref "SV16")
      (value "MA12-1")
      (footprint "eagle-import:MA12-1")
      (libsource (lib "eagle-import") (part "MA12-1"))
    )
    (comp (ref "SV17")
      (value "MA12-1")
      (footprint "eagle-import:MA12-1")
      (libsource (lib "eagle-import") (part "MA12-1"))
    )
    (comp (ref "SV18")
      (value "MA12-1")
      (footprint "eagle-import:MA12-1")
      (libsource (lib "eagle-import") (part "MA12-1"))
    )
    (comp (ref "SV19")
      (value "MA12-1")
      (footprint "eagle-import:MA12-1")
      (libsource (lib "eagle-import") (part "MA12-1"))
    )
    (comp (ref "SV20")
      (value "MA12-1")
      (footprint "eagle-import:MA12-1")
      (libsource (lib "eagle-import") (part "MA12-1"))
    )
    (comp (ref "SV21")
      (value "MA12-1")
      (footprint "eagle-import:MA12-1")
      (libsource (lib "eagle-import") (part "MA12-1"))
    )
    (comp (ref "SV22")
      (value "MA12-1")
      (footprint "eagle-import:MA12-1")
      (libsource (lib "eagle-import") (part "MA12-1"))
    )
    (comp (ref "SV23")
      (value "MA12-1")
      (footprint "eagle-import:MA12-1")
      (libsource (lib "eagle-import") (part "MA12-1"))
    )
    (comp (ref "SV24")
      (value "MA12-1")
      (footprint "eagle-import:MA12-1")
      (libsource (lib "eagle-import") (part "MA12-1"))
    )
    (comp (ref "SV25")
      (value "MA12-1")
      (footprint "eagle-import:MA12-1")
      (libsource (lib "eagle-import") (part "MA12-1"))
    )
    (comp (ref "SV26")
      (value "MA12-1")
      (footprint "eagle-import:MA12-1")
      (libsource (lib "eagle-import") (part "MA12-1"))
    )
    (comp (ref "SV27")
      (value "MA12-1")
      (footprint "eagle-import:MA12-1")
      (libsource (lib "eagle-import") (part "MA12-1"))
    )
    (comp (ref "SV28")
      (value "MA12-1")
      (footprint "eagle-import:MA12-1")
      (libsource (lib "eagle-import") (part "MA12-1"))
    )
    (comp (ref "SV29")
      (value "MA12-1")
      (footprint "eagle-import:MA12-1")
      (libsource (lib "eagle-import") (part "MA12-1"))
    )
    (comp (ref "SV30")
      (value "MA12-1")
      (footprint "eagle-import:MA12-1")
      (libsource (lib "eagle-import") (part "MA12-1"))
    )
    (comp (ref "SV31")
      (value "MA12-1")
      (footprint "eagle-import:MA12-1")
      (libsource (lib "eagle-import") (part "MA12-1"))
    )
    (comp (ref "SV32")
      (value "MA12-1")
      (footprint "eagle-import:MA12-1")
      (libsource (lib "eagle-import") (part "MA12-1"))
    )
    (comp (ref "SV33")
      (value "MA12-1")
      (footprint "eagle-import:MA12-1")
      (libsource (lib "eagle-import") (part "MA12-1"))
    )
    (comp (ref "SV34")
      (value "MA12-1")
      (footprint "eagle-import:MA12-1")
      (libsource (lib "eagle-import") (part "MA12-1"))
    )
    (comp (ref "SV35")
      (value "MA12-1")
      (footprint "eagle-import:MA12-1")
      (libsource (lib "eagle-import") (part "MA12-1"))
    )
    (comp (ref "SV36")
      (value "MA12-1")
      (footprint "eagle-import:MA12-1")
      (libsource (lib "eagle-import") (part "MA12-1"))
    )
    (comp (ref "SV37")
      (value "MA12-1")
      (footprint "eagle-import:MA12-1")
      (libsource (lib "eagle-import") (part "MA12-1"))
    )
    (comp (ref "SV38")
      (value "MA12-1")
      (footprint "eagle-import:MA12-1")
      (libsource (lib "eagle-import") (part "MA12-1"))
    )
    (comp (ref "SV39")
      (value "MA12-1")
      (footprint "eagle-import:MA12-1")
      (libsource (lib "eagle-import") (part "MA12-1"))
    )
    (comp (ref "SV40")
      (value "MA12-1")
      (footprint "eagle-import:MA12-1")
      (libsource (lib "eagle-import") (part "MA12-1"))
    )
    (comp (ref "SV41")
      (value "MA12-1")
      (footprint "eagle-import:MA12-1")
      (libsource (lib "eagle-import") (part "MA12-1"))
    )
    (comp (ref "SV42")
      (value "MA12-1")
      (footprint "eagle-import:MA12-1")
      (libsource (lib "eagle-import") (part "MA12-1"))
    )
    (comp (ref "SV43")
      (value "MA12-1")
      (footprint "eagle-import:MA12-1")
      (libsource (lib "eagle-import") (part "MA12-1"))
    )
    (comp (ref "SV44")
      (value "MA12-1")
      (footprint "eagle-import:MA12-1")
      (libsource (lib "eagle-import") (part "MA12-1"))
    )
    (comp (ref "SV45")
      (value "MA12-1")
      (footprint "eagle-import:MA12-1")
      (libsource (lib "eagle-import") (part "MA12-1"))
    )
    (comp (ref "SV46")
      (value "MA12-1")
      (footprint "eagle-import:MA12-1")
      (libsource (lib "eagle-import") (part "MA12-1"))
    )
    (comp (ref "SV47")
      (value "MA12-1")
      (footprint "eagle-import:MA12-1")
      (libsource (lib "eagle-import") (part "MA12-1"))
    )
    (comp (ref "SV48")
      (value "MA12-1")
      (footprint "eagle-import:MA12-1")
      (libsource (lib "eagle-import") (part "MA12-1"))
    )
    (comp (ref "SV49")
      (value "MA12-1")
      (footprint "eagle-import:MA12-1")
      (libsource (lib "eagle-import") (part "MA12-1"))
    )
    (comp (ref "SV50")
      (value "MA12-1")
      (footprint "eagle-import:MA12-1")
      (libsource (lib "eagle-import") (part "MA12-1"))
    )
    (comp (ref "SV51")
      (value "MA12-1")
      (footprint "eagle-import:MA12-1")
      (libsource (lib "eagle-import") (part "MA12-1"))
    )
    (comp (ref "SV52")
      (value "MA12-1")
      (footprint "eagle-import:MA12-1")
      (libsource (lib "eagle-import") (part "MA12-1"))
    )
    (comp (ref "SV53")
      (value "MA12-1")
      (footprint "eagle-import:MA12-1")
      (libsource (lib "eagle-import") (part "MA12-1"))
    )
    (comp (ref "SV54")
      (value "MA12-1")
      (footprint "eagle-import:MA12-1")
      (libsource (lib "eagle-import") (part "MA12-1"))
    )
    (comp (ref "SV55")
      (value "MA12-1")
      (footprint "eagle-import:MA12-1")
      (libsource (lib "eagle-import") (part "MA12-1"))
    )
    (comp (ref "SV56")
      (value "MA12-1")
      (footprint "eagle-import:MA12-1")
      (libsource (lib "eagle-import") (part "MA12-1"))
    )
    (comp (ref "SV57")
      (value "MA12-1")
      (footprint "eagle-import:MA12-1")
      (libsource (lib "eagle-import") (part "MA12-1"))
    )
    (comp (ref "SV58")
      (value "MA12-1")
      (footprint "eagle-import:MA12-1")
      (libsource (lib "eagle-import") (part "MA12-1"))
    )
    (comp (ref "SV59")
      (value "MA12-1")
      (footprint "eagle-import:MA12-1")
      (libsource (lib "eagle-import") (part "MA12-1"))
    )
    (comp (ref "SV60")
      (value "MA12-1")
      (footprint "eagle-import:MA12-1")
      (libsource (lib "eagle-import") (part "MA12-1"))
    )
    (comp (ref "SV61")
      (value "MA12-1")
      (footprint "eagle-import:MA12-1")
      (libsource (lib "eagle-import") (part "MA12-1"))
    )
    (comp (ref "SV62")
      (value "MA12-1")
      (footprint "eagle-import:MA12-1")
      (libsource (lib "eagle-import") (part "MA12-1"))
    )
    (comp (ref "SV183")
      (value "MA12-1")
      (footprint "eagle-import:MA12-1")
      (libsource (lib "eagle-import") (part "MA12-1"))
    )
    (comp (ref "SV184")
      (value "MA12-1")
      (footprint "eagle-import:MA12-1")
      (libsource (lib "eagle-import") (part "MA12-1"))
    )
    (comp (ref "SV185")
      (value "MA12-1")
      (footprint "eagle-import:MA12-1")
      (libsource (lib "eagle-import") (part "MA12-1"))
    )
    (comp (ref "SV186")
      (value "MA12-1")
      (footprint "eagle-import:MA12-1")
      (libsource (lib "eagle-import") (part "MA12-1"))
    )
    (comp (ref "SV187")
      (value "MA12-1")
      (footprint "eagle-import:MA12-1")
      (libsource (lib "eagle-import") (part "MA12-1"))
    )
    (comp (ref "SV188")
      (value "MA12-1")
      (footprint "eagle-import:MA12-1")
      (libsource (lib "eagle-import") (part "MA12-1"))
    )
    (comp (ref "SV189")
      (value "MA12-1")
      (footprint "eagle-import:MA12-1")
      (libsource (lib "eagle-import") (part "MA12-1"))
    )
    (comp (ref "SV190")
      (value "MA12-1")
      (footprint "eagle-import:MA12-1")
      (libsource (lib "eagle-import") (part "MA12-1"))
    )
    (comp (ref "SV191")
      (value "MA12-1")
      (footprint "eagle-import:MA12-1")
      (libsource (lib "eagle-import") (part "MA12-1"))
    )
    (comp (ref "SV192")
      (value "MA12-1")
      (footprint "eagle-import:MA12-1")
      (libsource (lib "eagle-import") (part "MA12-1"))
    )
  )
  (nets
    (net (code "1") (name "+15V") (class "Default")
      (node (ref "D14") (pin "1") (pinfunction "1_1") (pintype "passive"))
      (node (ref "U$2") (pin "DA2") (pinfunction "1_DA2") (pintype "bidirectional"))
    )
    (net (code "2") (name "-15V") (class "Default")
      (node (ref "D10") (pin "2") (pinfunction "2_2") (pintype "passive"))
      (node (ref "D12") (pin "2") (pinfunction "2_2") (pintype "passive"))
      (node (ref "D14") (pin "2") (pinfunction "2_2") (pintype "passive"))
      (node (ref "D8") (pin "2") (pinfunction "2_2") (pintype "passive"))
      (node (ref "U$2") (pin "AB2") (pinfunction "1_AB2") (pintype "bidirectional"))
      (node (ref "U$2") (pin "BB2") (pinfunction "1_BB2") (pintype "bidirectional"))
      (node (ref "U$2") (pin "CB2") (pinfunction "1_CB2") (pintype "bidirectional"))
      (node (ref "U$2") (pin "DB2") (pinfunction "1_DB2") (pintype "bidirectional"))
    )
    (net (code "3") (name "DISABLE") (class "Default")
      (node (ref "C2") (pin "2") (pinfunction "2_2") (pintype "passive"))
      (node (ref "IC6") (pin "8") (pinfunction "O_8") (pintype "output"))
      (node (ref "IC7") (pin "1") (pinfunction "I0_1") (pintype "input"))
      (node (ref "IC7") (pin "13") (pinfunction "I2_13") (pintype "input"))
      (node (ref "IC7") (pin "2") (pinfunction "I1_2") (pintype "input"))
      (node (ref "Q1") (pin "3") (pinfunction "E_3") (pintype "passive"))
    )
    (net (code "4") (name "EMEM0") (class "Default")
      (node (ref "IC2") (pin "11") (pinfunction "B8_11") (pintype "bidirectional"))
      (node (ref "IC4") (pin "19") (pinfunction "I/O7_19") (pintype "tri_state"))
    )
    (net (code "5") (name "EMEM1") (class "Default")
      (node (ref "IC2") (pin "12") (pinfunction "B7_12") (pintype "bidirectional"))
      (node (ref "IC4") (pin "18") (pinfunction "I/O6_18") (pintype "tri_state"))
    )
    (net (code "6") (name "EMEM2") (class "Default")
      (node (ref "IC2") (pin "13") (pinfunction "B6_13") (pintype "bidirectional"))
      (node (ref "IC4") (pin "17") (pinfunction "I/O5_17") (pintype "tri_state"))
    )
    (net (code "7") (name "EMEM3") (class "Default")
      (node (ref "IC2") (pin "14") (pinfunction "B5_14") (pintype "bidirectional"))
      (node (ref "IC4") (pin "16") (pinfunction "I/O4_16") (pintype "tri_state"))
    )
    (net (code "8") (name "GND") (class "Default")
      (node (ref "B1") (pin "-") (pinfunction "-_-") (pintype "passive"))
      (node (ref "B1") (pin "-@1") (pinfunction "-_-@1") (pintype "passive"))
      (node (ref "C1") (pin "2") (pinfunction "2_2") (pintype "passive"))
      (node (ref "C10") (pin "-") (pinfunction "-_-") (pintype "passive"))
      (node (ref "C11") (pin "2") (pinfunction "2_2") (pintype "passive"))
      (node (ref "C3") (pin "2") (pinfunction "2_2") (pintype "passive"))
      (node (ref "C4") (pin "2") (pinfunction "2_2") (pintype "passive"))
      (node (ref "C5") (pin "2") (pinfunction "2_2") (pintype "passive"))
      (node (ref "C6") (pin "2") (pinfunction "2_2") (pintype "passive"))
      (node (ref "C7") (pin "2") (pinfunction "2_2") (pintype "passive"))
      (node (ref "C8") (pin "2") (pinfunction "2_2") (pintype "passive"))
      (node (ref "C9") (pin "2") (pinfunction "2_2") (pintype "passive"))
      (node (ref "D10") (pin "12") (pinfunction "12_12") (pintype "passive"))
      (node (ref "D10") (pin "16") (pinfunction "16_16") (pintype "passive"))
      (node (ref "D10") (pin "3") (pinfunction "3_3") (pintype "passive"))
      (node (ref "D10") (pin "6") (pinfunction "6_6") (pintype "passive"))
      (node (ref "D11") (pin "12") (pinfunction "12_12") (pintype "passive"))
      (node (ref "D11") (pin "16") (pinfunction "16_16") (pintype "passive"))
      (node (ref "D11") (pin "3") (pinfunction "3_3") (pintype "passive"))
      (node (ref "D11") (pin "6") (pinfunction "6_6") (pintype "passive"))
      (node (ref "D12") (pin "12") (pinfunction "12_12") (pintype "passive"))
      (node (ref "D12") (pin "16") (pinfunction "16_16") (pintype "passive"))
      (node (ref "D12") (pin "3") (pinfunction "3_3") (pintype "passive"))
      (node (ref "D12") (pin "6") (pinfunction "6_6") (pintype "passive"))
      (node (ref "D13") (pin "12") (pinfunction "12_12") (pintype "passive"))
      (node (ref "D13") (pin "16") (pinfunction "16_16") (pintype "passive"))
      (node (ref "D13") (pin "3") (pinfunction "3_3") (pintype "passive"))
      (node (ref "D13") (pin "6") (pinfunction "6_6") (pintype "passive"))
      (node (ref "D14") (pin "12") (pinfunction "12_12") (pintype "passive"))
      (node (ref "D14") (pin "16") (pinfunction "16_16") (pintype "passive"))
      (node (ref "D14") (pin "3") (pinfunction "3_3") (pintype "passive"))
      (node (ref "D14") (pin "6") (pinfunction "6_6") (pintype "passive"))
      (node (ref "D7") (pin "12") (pinfunction "12_12") (pintype "passive"))
      (node (ref "D7") (pin "16") (pinfunction "16_16") (pintype "passive"))
      (node (ref "D7") (pin "3") (pinfunction "3_3") (pintype "passive"))
      (node (ref "D7") (pin "6") (pinfunction "6_6") (pintype "passive"))
      (node (ref "D8") (pin "12") (pinfunction "12_12") (pintype "passive"))
      (node (ref "D8") (pin "16") (pinfunction "16_16") (pintype "passive"))
      (node (ref "D8") (pin "3") (pinfunction "3_3") (pintype "passive"))
      (node (ref "D8") (pin "6") (pinfunction "6_6") (pintype "passive"))
      (node (ref "D9") (pin "12") (pinfunction "12_12") (pintype "passive"))
      (node (ref "D9") (pin "16") (pinfunction "16_16") (pintype "passive"))
      (node (ref "D9") (pin "3") (pinfunction "3_3") (pintype "passive"))
      (node (ref "D9") (pin "6") (pinfunction "6_6") (pintype "passive"))
      (node (ref "IC1") (pin "19") (pinfunction "G_19") (pintype "input"))
      (node (ref "IC2") (pin "19") (pinfunction "G_19") (pintype "input"))
      (node (ref "IC3") (pin "14") (pinfunction "VSS_14") (pintype "power_in"))
      (node (ref "IC4") (pin "14") (pinfunction "VSS_14") (pintype "power_in"))
      (node (ref "IC5") (pin "4") (pinfunction "G2A_4") (pintype "input"))
      (node (ref "IC5") (pin "5") (pinfunction "G2B_5") (pintype "input"))
      (node (ref "R1") (pin "1") (pinfunction "1_1") (pintype "passive"))
      (node (ref "R2") (pin "1") (pinfunction "1_1") (pintype "passive"))
      (node (ref "R3") (pin "1") (pinfunction "1_1") (pintype "passive"))
      (node (ref "R4") (pin "1") (pinfunction "1_1") (pintype "passive"))
      (node (ref "SV10") (pin "1") (pinfunction "1_1") (pintype "passive"))
      (node (ref "SV10") (pin "10") (pinfunction "10_10") (pintype "passive"))
      (node (ref "SV10") (pin "11") (pinfunction "11_11") (pintype "passive"))
      (node (ref "SV10") (pin "12") (pinfunction "12_12") (pintype "passive"))
      (node (ref "SV10") (pin "2") (pinfunction "2_2") (pintype "passive"))
      (node (ref "SV10") (pin "3") (pinfunction "3_3") (pintype "passive"))
      (node (ref "SV10") (pin "4") (pinfunction "4_4") (pintype "passive"))
      (node (ref "SV10") (pin "5") (pinfunction "5_5") (pintype "passive"))
      (node (ref "SV10") (pin "6") (pinfunction "6_6") (pintype "passive"))
      (node (ref "SV10") (pin "7") (pinfunction "7_7") (pintype "passive"))
      (node (ref "SV10") (pin "8") (pinfunction "8_8") (pintype "passive"))
      (node (ref "SV10") (pin "9") (pinfunction "9_9") (pintype "passive"))
      (node (ref "SV12") (pin "1") (pinfunction "1_1") (pintype "passive"))
      (node (ref "SV12") (pin "10") (pinfunction "10_10") (pintype "passive"))
      (node (ref "SV12") (pin "11") (pinfunction "11_11") (pintype "passive"))
      (node (ref "SV12") (pin "12") (pinfunction "12_12") (pintype "passive"))
      (node (ref "SV12") (pin "2") (pinfunction "2_2") (pintype "passive"))
      (node (ref "SV12") (pin "3") (pinfunction "3_3") (pintype "passive"))
      (node (ref "SV12") (pin "4") (pinfunction "4_4") (pintype "passive"))
      (node (ref "SV12") (pin "5") (pinfunction "5_5") (pintype "passive"))
      (node (ref "SV12") (pin "6") (pinfunction "6_6") (pintype "passive"))
      (node (ref "SV12") (pin "7") (pinfunction "7_7") (pintype "passive"))
      (node (ref "SV12") (pin "8") (pinfunction "8_8") (pintype "passive"))
      (node (ref "SV12") (pin "9") (pinfunction "9_9") (pintype "passive"))
      (node (ref "SV14") (pin "1") (pinfunction "1_1") (pintype "passive"))
      (node (ref "SV14") (pin "10") (pinfunction "10_10") (pintype "passive"))
      (node (ref "SV14") (pin "11") (pinfunction "11_11") (pintype "passive"))
      (node (ref "SV14") (pin "12") (pinfunction "12_12") (pintype "passive"))
      (node (ref "SV14") (pin "2") (pinfunction "2_2") (pintype "passive"))
      (node (ref "SV14") (pin "3") (pinfunction "3_3") (pintype "passive"))
      (node (ref "SV14") (pin "4") (pinfunction "4_4") (pintype "passive"))
      (node (ref "SV14") (pin "5") (pinfunction "5_5") (pintype "passive"))
      (node (ref "SV14") (pin "6") (pinfunction "6_6") (pintype "passive"))
      (node (ref "SV14") (pin "7") (pinfunction "7_7") (pintype "passive"))
      (node (ref "SV14") (pin "8") (pinfunction "8_8") (pintype "passive"))
      (node (ref "SV14") (pin "9") (pinfunction "9_9") (pintype "passive"))
      (node (ref "SV16") (pin "1") (pinfunction "1_1") (pintype "passive"))
      (node (ref "SV16") (pin "10") (pinfunction "10_10") (pintype "passive"))
      (node (ref "SV16") (pin "11") (pinfunction "11_11") (pintype "passive"))
      (node (ref "SV16") (pin "12") (pinfunction "12_12") (pintype "passive"))
      (node (ref "SV16") (pin "2") (pinfunction "2_2") (pintype "passive"))
      (node (ref "SV16") (pin "3") (pinfunction "3_3") (pintype "passive"))
      (node (ref "SV16") (pin "4") (pinfunction "4_4") (pintype "passive"))
      (node (ref "SV16") (pin "5") (pinfunction "5_5") (pintype "passive"))
      (node (ref "SV16") (pin "6") (pinfunction "6_6") (pintype "passive"))
      (node (ref "SV16") (pin "7") (pinfunction "7_7") (pintype "passive"))
      (node (ref "SV16") (pin "8") (pinfunction "8_8") (pintype "passive"))
      (node (ref "SV16") (pin "9") (pinfunction "9_9") (pintype "passive"))
      (node (ref "SV18") (pin "1") (pinfunction "1_1") (pintype "passive"))
      (node (ref "SV18") (pin "10") (pinfunction "10_10") (pintype "passive"))
      (node (ref "SV18") (pin "11") (pinfunction "11_11") (pintype "passive"))
      (node (ref "SV18") (pin "12") (pinfunction "12_12") (pintype "passive"))
      (node (ref "SV18") (pin "2") (pinfunction "2_2") (pintype "passive"))
      (node (ref "SV18") (pin "3") (pinfunction "3_3") (pintype "passive"))
      (node (ref "SV18") (pin "4") (pinfunction "4_4") (pintype "passive"))
      (node (ref "SV18") (pin "5") (pinfunction "5_5") (pintype "passive"))
      (node (ref "SV18") (pin "6") (pinfunction "6_6") (pintype "passive"))
      (node (ref "SV18") (pin "7") (pinfunction "7_7") (pintype "passive"))
      (node (ref "SV18") (pin "8") (pinfunction "8_8") (pintype "passive"))
      (node (ref "SV18") (pin "9") (pinfunction "9_9") (pintype "passive"))
      (node (ref "SV184") (pin "1") (pinfunction "1_1") (pintype "passive"))
      (node (ref "SV184") (pin "10") (pinfunction "10_10") (pintype "passive"))
      (node (ref "SV184") (pin "11") (pinfunction "11_11") (pintype "passive"))
      (node (ref "SV184") (pin "12") (pinfunction "12_12") (pintype "passive"))
      (node (ref "SV184") (pin "2") (pinfunction "2_2") (pintype "passive"))
      (node (ref "SV184") (pin "3") (pinfunction "3_3") (pintype "passive"))
      (node (ref "SV184") (pin "4") (pinfunction "4_4") (pintype "passive"))
      (node (ref "SV184") (pin "5") (pinfunction "5_5") (pintype "passive"))
      (node (ref "SV184") (pin "6") (pinfunction "6_6") (pintype "passive"))
      (node (ref "SV184") (pin "7") (pinfunction "7_7") (pintype "passive"))
      (node (ref "SV184") (pin "8") (pinfunction "8_8") (pintype "passive"))
      (node (ref "SV184") (pin "9") (pinfunction "9_9") (pintype "passive"))
      (node (ref "SV186") (pin "1") (pinfunction "1_1") (pintype "passive"))
      (node (ref "SV186") (pin "10") (pinfunction "10_10") (pintype "passive"))
      (node (ref "SV186") (pin "11") (pinfunction "11_11") (pintype "passive"))
      (node (ref "SV186") (pin "12") (pinfunction "12_12") (pintype "passive"))
      (node (ref "SV186") (pin "2") (pinfunction "2_2") (pintype "passive"))
      (node (ref "SV186") (pin "3") (pinfunction "3_3") (pintype "passive"))
      (node (ref "SV186") (pin "4") (pinfunction "4_4") (pintype "passive"))
      (node (ref "SV186") (pin "5") (pinfunction "5_5") (pintype "passive"))
      (node (ref "SV186") (pin "6") (pinfunction "6_6") (pintype "passive"))
      (node (ref "SV186") (pin "7") (pinfunction "7_7") (pintype "passive"))
      (node (ref "SV186") (pin "8") (pinfunction "8_8") (pintype "passive"))
      (node (ref "SV186") (pin "9") (pinfunction "9_9") (pintype "passive"))
      (node (ref "SV188") (pin "1") (pinfunction "1_1") (pintype "passive"))
      (node (ref "SV188") (pin "10") (pinfunction "10_10") (pintype "passive"))
      (node (ref "SV188") (pin "11") (pinfunction "11_11") (pintype "passive"))
      (node (ref "SV188") (pin "12") (pinfunction "12_12") (pintype "passive"))
      (node (ref "SV188") (pin "2") (pinfunction "2_2") (pintype "passive"))
      (node (ref "SV188") (pin "3") (pinfunction "3_3") (pintype "passive"))
      (node (ref "SV188") (pin "4") (pinfunction "4_4") (pintype "passive"))
      (node (ref "SV188") (pin "5") (pinfunction "5_5") (pintype "passive"))
      (node (ref "SV188") (pin "6") (pinfunction "6_6") (pintype "passive"))
      (node (ref "SV188") (pin "7") (pinfunction "7_7") (pintype "passive"))
      (node (ref "SV188") (pin "8") (pinfunction "8_8") (pintype "passive"))
      (node (ref "SV188") (pin "9") (pinfunction "9_9") (pintype "passive"))
      (node (ref "SV190") (pin "1") (pinfunction "1_1") (pintype "passive"))
      (node (ref "SV190") (pin "10") (pinfunction "10_10") (pintype "passive"))
      (node (ref "SV190") (pin "11") (pinfunction "11_11") (pintype "passive"))
      (node (ref "SV190") (pin "12") (pinfunction "12_12") (pintype "passive"))
      (node (ref "SV190") (pin "2") (pinfunction "2_2") (pintype "passive"))
      (node (ref "SV190") (pin "3") (pinfunction "3_3") (pintype "passive"))
      (node (ref "SV190") (pin "4") (pinfunction "4_4") (pintype "passive"))
      (node (ref "SV190") (pin "5") (pinfunction "5_5") (pintype "passive"))
      (node (ref "SV190") (pin "6") (pinfunction "6_6") (pintype "passive"))
      (node (ref "SV190") (pin "7") (pinfunction "7_7") (pintype "passive"))
      (node (ref "SV190") (pin "8") (pinfunction "8_8") (pintype "passive"))
      (node (ref "SV190") (pin "9") (pinfunction "9_9") (pintype "passive"))
      (node (ref "SV192") (pin "1") (pinfunction "1_1") (pintype "passive"))
      (node (ref "SV192") (pin "10") (pinfunction "10_10") (pintype "passive"))
      (node (ref "SV192") (pin "11") (pinfunction "11_11") (pintype "passive"))
      (node (ref "SV192") (pin "12") (pinfunction "12_12") (pintype "passive"))
      (node (ref "SV192") (pin "2") (pinfunction "2_2") (pintype "passive"))
      (node (ref "SV192") (pin "3") (pinfunction "3_3") (pintype "passive"))
      (node (ref "SV192") (pin "4") (pinfunction "4_4") (pintype "passive"))
      (node (ref "SV192") (pin "5") (pinfunction "5_5") (pintype "passive"))
      (node (ref "SV192") (pin "6") (pinfunction "6_6") (pintype "passive"))
      (node (ref "SV192") (pin "7") (pinfunction "7_7") (pintype "passive"))
      (node (ref "SV192") (pin "8") (pinfunction "8_8") (pintype "passive"))
      (node (ref "SV192") (pin "9") (pinfunction "9_9") (pintype "passive"))
      (node (ref "SV2") (pin "1") (pinfunction "1_1") (pintype "passive"))
      (node (ref "SV2") (pin "10") (pinfunction "10_10") (pintype "passive"))
      (node (ref "SV2") (pin "11") (pinfunction "11_11") (pintype "passive"))
      (node (ref "SV2") (pin "12") (pinfunction "12_12") (pintype "passive"))
      (node (ref "SV2") (pin "2") (pinfunction "2_2") (pintype "passive"))
      (node (ref "SV2") (pin "3") (pinfunction "3_3") (pintype "passive"))
      (node (ref "SV2") (pin "4") (pinfunction "4_4") (pintype "passive"))
      (node (ref "SV2") (pin "5") (pinfunction "5_5") (pintype "passive"))
      (node (ref "SV2") (pin "6") (pinfunction "6_6") (pintype "passive"))
      (node (ref "SV2") (pin "7") (pinfunction "7_7") (pintype "passive"))
      (node (ref "SV2") (pin "8") (pinfunction "8_8") (pintype "passive"))
      (node (ref "SV2") (pin "9") (pinfunction "9_9") (pintype "passive"))
      (node (ref "SV20") (pin "1") (pinfunction "1_1") (pintype "passive"))
      (node (ref "SV20") (pin "10") (pinfunction "10_10") (pintype "passive"))
      (node (ref "SV20") (pin "11") (pinfunction "11_11") (pintype "passive"))
      (node (ref "SV20") (pin "12") (pinfunction "12_12") (pintype "passive"))
      (node (ref "SV20") (pin "2") (pinfunction "2_2") (pintype "passive"))
      (node (ref "SV20") (pin "3") (pinfunction "3_3") (pintype "passive"))
      (node (ref "SV20") (pin "4") (pinfunction "4_4") (pintype "passive"))
      (node (ref "SV20") (pin "5") (pinfunction "5_5") (pintype "passive"))
      (node (ref "SV20") (pin "6") (pinfunction "6_6") (pintype "passive"))
      (node (ref "SV20") (pin "7") (pinfunction "7_7") (pintype "passive"))
      (node (ref "SV20") (pin "8") (pinfunction "8_8") (pintype "passive"))
      (node (ref "SV20") (pin "9") (pinfunction "9_9") (pintype "passive"))
      (node (ref "SV22") (pin "1") (pinfunction "1_1") (pintype "passive"))
      (node (ref "SV22") (pin "10") (pinfunction "10_10") (pintype "passive"))
      (node (ref "SV22") (pin "11") (pinfunction "11_11") (pintype "passive"))
      (node (ref "SV22") (pin "12") (pinfunction "12_12") (pintype "passive"))
      (node (ref "SV22") (pin "2") (pinfunction "2_2") (pintype "passive"))
      (node (ref "SV22") (pin "3") (pinfunction "3_3") (pintype "passive"))
      (node (ref "SV22") (pin "4") (pinfunction "4_4") (pintype "passive"))
      (node (ref "SV22") (pin "5") (pinfunction "5_5") (pintype "passive"))
      (node (ref "SV22") (pin "6") (pinfunction "6_6") (pintype "passive"))
      (node (ref "SV22") (pin "7") (pinfunction "7_7") (pintype "passive"))
      (node (ref "SV22") (pin "8") (pinfunction "8_8") (pintype "passive"))
      (node (ref "SV22") (pin "9") (pinfunction "9_9") (pintype "passive"))
      (node (ref "SV24") (pin "1") (pinfunction "1_1") (pintype "passive"))
      (node (ref "SV24") (pin "10") (pinfunction "10_10") (pintype "passive"))
      (node (ref "SV24") (pin "11") (pinfunction "11_11") (pintype "passive"))
      (node (ref "SV24") (pin "12") (pinfunction "12_12") (pintype "passive"))
      (node (ref "SV24") (pin "2") (pinfunction "2_2") (pintype "passive"))
      (node (ref "SV24") (pin "3") (pinfunction "3_3") (pintype "passive"))
      (node (ref "SV24") (pin "4") (pinfunction "4_4") (pintype "passive"))
      (node (ref "SV24") (pin "5") (pinfunction "5_5") (pintype "passive"))
      (node (ref "SV24") (pin "6") (pinfunction "6_6") (pintype "passive"))
      (node (ref "SV24") (pin "7") (pinfunction "7_7") (pintype "passive"))
      (node (ref "SV24") (pin "8") (pinfunction "8_8") (pintype "passive"))
      (node (ref "SV24") (pin "9") (pinfunction "9_9") (pintype "passive"))
      (node (ref "SV26") (pin "1") (pinfunction "1_1") (pintype "passive"))
      (node (ref "SV26") (pin "10") (pinfunction "10_10") (pintype "passive"))
      (node (ref "SV26") (pin "11") (pinfunction "11_11") (pintype "passive"))
      (node (ref "SV26") (pin "12") (pinfunction "12_12") (pintype "passive"))
      (node (ref "SV26") (pin "2") (pinfunction "2_2") (pintype "passive"))
      (node (ref "SV26") (pin "3") (pinfunction "3_3") (pintype "passive"))
      (node (ref "SV26") (pin "4") (pinfunction "4_4") (pintype "passive"))
      (node (ref "SV26") (pin "5") (pinfunction "5_5") (pintype "passive"))
      (node (ref "SV26") (pin "6") (pinfunction "6_6") (pintype "passive"))
      (node (ref "SV26") (pin "7") (pinfunction "7_7") (pintype "passive"))
      (node (ref "SV26") (pin "8") (pinfunction "8_8") (pintype "passive"))
      (node (ref "SV26") (pin "9") (pinfunction "9_9") (pintype "passive"))
      (node (ref "SV28") (pin "1") (pinfunction "1_1") (pintype "passive"))
      (node (ref "SV28") (pin "10") (pinfunction "10_10") (pintype "passive"))
      (node (ref "SV28") (pin "11") (pinfunction "11_11") (pintype "passive"))
      (node (ref "SV28") (pin "12") (pinfunction "12_12") (pintype "passive"))
      (node (ref "SV28") (pin "2") (pinfunction "2_2") (pintype "passive"))
      (node (ref "SV28") (pin "3") (pinfunction "3_3") (pintype "passive"))
      (node (ref "SV28") (pin "4") (pinfunction "4_4") (pintype "passive"))
      (node (ref "SV28") (pin "5") (pinfunction "5_5") (pintype "passive"))
      (node (ref "SV28") (pin "6") (pinfunction "6_6") (pintype "passive"))
      (node (ref "SV28") (pin "7") (pinfunction "7_7") (pintype "passive"))
      (node (ref "SV28") (pin "8") (pinfunction "8_8") (pintype "passive"))
      (node (ref "SV28") (pin "9") (pinfunction "9_9") (pintype "passive"))
      (node (ref "SV30") (pin "1") (pinfunction "1_1") (pintype "passive"))
      (node (ref "SV30") (pin "10") (pinfunction "10_10") (pintype "passive"))
      (node (ref "SV30") (pin "11") (pinfunction "11_11") (pintype "passive"))
      (node (ref "SV30") (pin "12") (pinfunction "12_12") (pintype "passive"))
      (node (ref "SV30") (pin "2") (pinfunction "2_2") (pintype "passive"))
      (node (ref "SV30") (pin "3") (pinfunction "3_3") (pintype "passive"))
      (node (ref "SV30") (pin "4") (pinfunction "4_4") (pintype "passive"))
      (node (ref "SV30") (pin "5") (pinfunction "5_5") (pintype "passive"))
      (node (ref "SV30") (pin "6") (pinfunction "6_6") (pintype "passive"))
      (node (ref "SV30") (pin "7") (pinfunction "7_7") (pintype "passive"))
      (node (ref "SV30") (pin "8") (pinfunction "8_8") (pintype "passive"))
      (node (ref "SV30") (pin "9") (pinfunction "9_9") (pintype "passive"))
      (node (ref "SV32") (pin "1") (pinfunction "1_1") (pintype "passive"))
      (node (ref "SV32") (pin "10") (pinfunction "10_10") (pintype "passive"))
      (node (ref "SV32") (pin "11") (pinfunction "11_11") (pintype "passive"))
      (node (ref "SV32") (pin "12") (pinfunction "12_12") (pintype "passive"))
      (node (ref "SV32") (pin "2") (pinfunction "2_2") (pintype "passive"))
      (node (ref "SV32") (pin "3") (pinfunction "3_3") (pintype "passive"))
      (node (ref "SV32") (pin "4") (pinfunction "4_4") (pintype "passive"))
      (node (ref "SV32") (pin "5") (pinfunction "5_5") (pintype "passive"))
      (node (ref "SV32") (pin "6") (pinfunction "6_6") (pintype "passive"))
      (node (ref "SV32") (pin "7") (pinfunction "7_7") (pintype "passive"))
      (node (ref "SV32") (pin "8") (pinfunction "8_8") (pintype "passive"))
      (node (ref "SV32") (pin "9") (pinfunction "9_9") (pintype "passive"))
      (node (ref "SV34") (pin "1") (pinfunction "1_1") (pintype "passive"))
      (node (ref "SV34") (pin "10") (pinfunction "10_10") (pintype "passive"))
      (node (ref "SV34") (pin "11") (pinfunction "11_11") (pintype "passive"))
      (node (ref "SV34") (pin "12") (pinfunction "12_12") (pintype "passive"))
      (node (ref "SV34") (pin "2") (pinfunction "2_2") (pintype "passive"))
      (node (ref "SV34") (pin "3") (pinfunction "3_3") (pintype "passive"))
      (node (ref "SV34") (pin "4") (pinfunction "4_4") (pintype "passive"))
      (node (ref "SV34") (pin "5") (pinfunction "5_5") (pintype "passive"))
      (node (ref "SV34") (pin "6") (pinfunction "6_6") (pintype "passive"))
      (node (ref "SV34") (pin "7") (pinfunction "7_7") (pintype "passive"))
      (node (ref "SV34") (pin "8") (pinfunction "8_8") (pintype "passive"))
      (node (ref "SV34") (pin "9") (pinfunction "9_9") (pintype "passive"))
      (node (ref "SV36") (pin "1") (pinfunction "1_1") (pintype "passive"))
      (node (ref "SV36") (pin "10") (pinfunction "10_10") (pintype "passive"))
      (node (ref "SV36") (pin "11") (pinfunction "11_11") (pintype "passive"))
      (node (ref "SV36") (pin "12") (pinfunction "12_12") (pintype "passive"))
      (node (ref "SV36") (pin "2") (pinfunction "2_2") (pintype "passive"))
      (node (ref "SV36") (pin "3") (pinfunction "3_3") (pintype "passive"))
      (node (ref "SV36") (pin "4") (pinfunction "4_4") (pintype "passive"))
      (node (ref "SV36") (pin "5") (pinfunction "5_5") (pintype "passive"))
      (node (ref "SV36") (pin "6") (pinfunction "6_6") (pintype "passive"))
      (node (ref "SV36") (pin "7") (pinfunction "7_7") (pintype "passive"))
      (node (ref "SV36") (pin "8") (pinfunction "8_8") (pintype "passive"))
      (node (ref "SV36") (pin "9") (pinfunction "9_9") (pintype "passive"))
      (node (ref "SV38") (pin "1") (pinfunction "1_1") (pintype "passive"))
      (node (ref "SV38") (pin "10") (pinfunction "10_10") (pintype "passive"))
      (node (ref "SV38") (pin "11") (pinfunction "11_11") (pintype "passive"))
      (node (ref "SV38") (pin "12") (pinfunction "12_12") (pintype "passive"))
      (node (ref "SV38") (pin "2") (pinfunction "2_2") (pintype "passive"))
      (node (ref "SV38") (pin "3") (pinfunction "3_3") (pintype "passive"))
      (node (ref "SV38") (pin "4") (pinfunction "4_4") (pintype "passive"))
      (node (ref "SV38") (pin "5") (pinfunction "5_5") (pintype "passive"))
      (node (ref "SV38") (pin "6") (pinfunction "6_6") (pintype "passive"))
      (node (ref "SV38") (pin "7") (pinfunction "7_7") (pintype "passive"))
      (node (ref "SV38") (pin "8") (pinfunction "8_8") (pintype "passive"))
      (node (ref "SV38") (pin "9") (pinfunction "9_9") (pintype "passive"))
      (node (ref "SV4") (pin "1") (pinfunction "1_1") (pintype "passive"))
      (node (ref "SV4") (pin "10") (pinfunction "10_10") (pintype "passive"))
      (node (ref "SV4") (pin "11") (pinfunction "11_11") (pintype "passive"))
      (node (ref "SV4") (pin "12") (pinfunction "12_12") (pintype "passive"))
      (node (ref "SV4") (pin "2") (pinfunction "2_2") (pintype "passive"))
      (node (ref "SV4") (pin "3") (pinfunction "3_3") (pintype "passive"))
      (node (ref "SV4") (pin "4") (pinfunction "4_4") (pintype "passive"))
      (node (ref "SV4") (pin "5") (pinfunction "5_5") (pintype "passive"))
      (node (ref "SV4") (pin "6") (pinfunction "6_6") (pintype "passive"))
      (node (ref "SV4") (pin "7") (pinfunction "7_7") (pintype "passive"))
      (node (ref "SV4") (pin "8") (pinfunction "8_8") (pintype "passive"))
      (node (ref "SV4") (pin "9") (pinfunction "9_9") (pintype "passive"))
      (node (ref "SV40") (pin "1") (pinfunction "1_1") (pintype "passive"))
      (node (ref "SV40") (pin "10") (pinfunction "10_10") (pintype "passive"))
      (node (ref "SV40") (pin "11") (pinfunction "11_11") (pintype "passive"))
      (node (ref "SV40") (pin "12") (pinfunction "12_12") (pintype "passive"))
      (node (ref "SV40") (pin "2") (pinfunction "2_2") (pintype "passive"))
      (node (ref "SV40") (pin "3") (pinfunction "3_3") (pintype "passive"))
      (node (ref "SV40") (pin "4") (pinfunction "4_4") (pintype "passive"))
      (node (ref "SV40") (pin "5") (pinfunction "5_5") (pintype "passive"))
      (node (ref "SV40") (pin "6") (pinfunction "6_6") (pintype "passive"))
      (node (ref "SV40") (pin "7") (pinfunction "7_7") (pintype "passive"))
      (node (ref "SV40") (pin "8") (pinfunction "8_8") (pintype "passive"))
      (node (ref "SV40") (pin "9") (pinfunction "9_9") (pintype "passive"))
      (node (ref "SV42") (pin "1") (pinfunction "1_1") (pintype "passive"))
      (node (ref "SV42") (pin "10") (pinfunction "10_10") (pintype "passive"))
      (node (ref "SV42") (pin "11") (pinfunction "11_11") (pintype "passive"))
      (node (ref "SV42") (pin "12") (pinfunction "12_12") (pintype "passive"))
      (node (ref "SV42") (pin "2") (pinfunction "2_2") (pintype "passive"))
      (node (ref "SV42") (pin "3") (pinfunction "3_3") (pintype "passive"))
      (node (ref "SV42") (pin "4") (pinfunction "4_4") (pintype "passive"))
      (node (ref "SV42") (pin "5") (pinfunction "5_5") (pintype "passive"))
      (node (ref "SV42") (pin "6") (pinfunction "6_6") (pintype "passive"))
      (node (ref "SV42") (pin "7") (pinfunction "7_7") (pintype "passive"))
      (node (ref "SV42") (pin "8") (pinfunction "8_8") (pintype "passive"))
      (node (ref "SV42") (pin "9") (pinfunction "9_9") (pintype "passive"))
      (node (ref "SV44") (pin "1") (pinfunction "1_1") (pintype "passive"))
      (node (ref "SV44") (pin "10") (pinfunction "10_10") (pintype "passive"))
      (node (ref "SV44") (pin "11") (pinfunction "11_11") (pintype "passive"))
      (node (ref "SV44") (pin "12") (pinfunction "12_12") (pintype "passive"))
      (node (ref "SV44") (pin "2") (pinfunction "2_2") (pintype "passive"))
      (node (ref "SV44") (pin "3") (pinfunction "3_3") (pintype "passive"))
      (node (ref "SV44") (pin "4") (pinfunction "4_4") (pintype "passive"))
      (node (ref "SV44") (pin "5") (pinfunction "5_5") (pintype "passive"))
      (node (ref "SV44") (pin "6") (pinfunction "6_6") (pintype "passive"))
      (node (ref "SV44") (pin "7") (pinfunction "7_7") (pintype "passive"))
      (node (ref "SV44") (pin "8") (pinfunction "8_8") (pintype "passive"))
      (node (ref "SV44") (pin "9") (pinfunction "9_9") (pintype "passive"))
      (node (ref "SV46") (pin "1") (pinfunction "1_1") (pintype "passive"))
      (node (ref "SV46") (pin "10") (pinfunction "10_10") (pintype "passive"))
      (node (ref "SV46") (pin "11") (pinfunction "11_11") (pintype "passive"))
      (node (ref "SV46") (pin "12") (pinfunction "12_12") (pintype "passive"))
      (node (ref "SV46") (pin "2") (pinfunction "2_2") (pintype "passive"))
      (node (ref "SV46") (pin "3") (pinfunction "3_3") (pintype "passive"))
      (node (ref "SV46") (pin "4") (pinfunction "4_4") (pintype "passive"))
      (node (ref "SV46") (pin "5") (pinfunction "5_5") (pintype "passive"))
      (node (ref "SV46") (pin "6") (pinfunction "6_6") (pintype "passive"))
      (node (ref "SV46") (pin "7") (pinfunction "7_7") (pintype "passive"))
      (node (ref "SV46") (pin "8") (pinfunction "8_8") (pintype "passive"))
      (node (ref "SV46") (pin "9") (pinfunction "9_9") (pintype "passive"))
      (node (ref "SV48") (pin "1") (pinfunction "1_1") (pintype "passive"))
      (node (ref "SV48") (pin "10") (pinfunction "10_10") (pintype "passive"))
      (node (ref "SV48") (pin "11") (pinfunction "11_11") (pintype "passive"))
      (node (ref "SV48") (pin "12") (pinfunction "12_12") (pintype "passive"))
      (node (ref "SV48") (pin "2") (pinfunction "2_2") (pintype "passive"))
      (node (ref "SV48") (pin "3") (pinfunction "3_3") (pintype "passive"))
      (node (ref "SV48") (pin "4") (pinfunction "4_4") (pintype "passive"))
      (node (ref "SV48") (pin "5") (pinfunction "5_5") (pintype "passive"))
      (node (ref "SV48") (pin "6") (pinfunction "6_6") (pintype "passive"))
      (node (ref "SV48") (pin "7") (pinfunction "7_7") (pintype "passive"))
      (node (ref "SV48") (pin "8") (pinfunction "8_8") (pintype "passive"))
      (node (ref "SV48") (pin "9") (pinfunction "9_9") (pintype "passive"))
      (node (ref "SV50") (pin "1") (pinfunction "1_1") (pintype "passive"))
      (node (ref "SV50") (pin "10") (pinfunction "10_10") (pintype "passive"))
      (node (ref "SV50") (pin "11") (pinfunction "11_11") (pintype "passive"))
      (node (ref "SV50") (pin "12") (pinfunction "12_12") (pintype "passive"))
      (node (ref "SV50") (pin "2") (pinfunction "2_2") (pintype "passive"))
      (node (ref "SV50") (pin "3") (pinfunction "3_3") (pintype "passive"))
      (node (ref "SV50") (pin "4") (pinfunction "4_4") (pintype "passive"))
      (node (ref "SV50") (pin "5") (pinfunction "5_5") (pintype "passive"))
      (node (ref "SV50") (pin "6") (pinfunction "6_6") (pintype "passive"))
      (node (ref "SV50") (pin "7") (pinfunction "7_7") (pintype "passive"))
      (node (ref "SV50") (pin "8") (pinfunction "8_8") (pintype "passive"))
      (node (ref "SV50") (pin "9") (pinfunction "9_9") (pintype "passive"))
      (node (ref "SV52") (pin "1") (pinfunction "1_1") (pintype "passive"))
      (node (ref "SV52") (pin "10") (pinfunction "10_10") (pintype "passive"))
      (node (ref "SV52") (pin "11") (pinfunction "11_11") (pintype "passive"))
      (node (ref "SV52") (pin "12") (pinfunction "12_12") (pintype "passive"))
      (node (ref "SV52") (pin "2") (pinfunction "2_2") (pintype "passive"))
      (node (ref "SV52") (pin "3") (pinfunction "3_3") (pintype "passive"))
      (node (ref "SV52") (pin "4") (pinfunction "4_4") (pintype "passive"))
      (node (ref "SV52") (pin "5") (pinfunction "5_5") (pintype "passive"))
      (node (ref "SV52") (pin "6") (pinfunction "6_6") (pintype "passive"))
      (node (ref "SV52") (pin "7") (pinfunction "7_7") (pintype "passive"))
      (node (ref "SV52") (pin "8") (pinfunction "8_8") (pintype "passive"))
      (node (ref "SV52") (pin "9") (pinfunction "9_9") (pintype "passive"))
      (node (ref "SV54") (pin "1") (pinfunction "1_1") (pintype "passive"))
      (node (ref "SV54") (pin "10") (pinfunction "10_10") (pintype "passive"))
      (node (ref "SV54") (pin "11") (pinfunction "11_11") (pintype "passive"))
      (node (ref "SV54") (pin "12") (pinfunction "12_12") (pintype "passive"))
      (node (ref "SV54") (pin "2") (pinfunction "2_2") (pintype "passive"))
      (node (ref "SV54") (pin "3") (pinfunction "3_3") (pintype "passive"))
      (node (ref "SV54") (pin "4") (pinfunction "4_4") (pintype "passive"))
      (node (ref "SV54") (pin "5") (pinfunction "5_5") (pintype "passive"))
      (node (ref "SV54") (pin "6") (pinfunction "6_6") (pintype "passive"))
      (node (ref "SV54") (pin "7") (pinfunction "7_7") (pintype "passive"))
      (node (ref "SV54") (pin "8") (pinfunction "8_8") (pintype "passive"))
      (node (ref "SV54") (pin "9") (pinfunction "9_9") (pintype "passive"))
      (node (ref "SV56") (pin "1") (pinfunction "1_1") (pintype "passive"))
      (node (ref "SV56") (pin "10") (pinfunction "10_10") (pintype "passive"))
      (node (ref "SV56") (pin "11") (pinfunction "11_11") (pintype "passive"))
      (node (ref "SV56") (pin "12") (pinfunction "12_12") (pintype "passive"))
      (node (ref "SV56") (pin "2") (pinfunction "2_2") (pintype "passive"))
      (node (ref "SV56") (pin "3") (pinfunction "3_3") (pintype "passive"))
      (node (ref "SV56") (pin "4") (pinfunction "4_4") (pintype "passive"))
      (node (ref "SV56") (pin "5") (pinfunction "5_5") (pintype "passive"))
      (node (ref "SV56") (pin "6") (pinfunction "6_6") (pintype "passive"))
      (node (ref "SV56") (pin "7") (pinfunction "7_7") (pintype "passive"))
      (node (ref "SV56") (pin "8") (pinfunction "8_8") (pintype "passive"))
      (node (ref "SV56") (pin "9") (pinfunction "9_9") (pintype "passive"))
      (node (ref "SV58") (pin "1") (pinfunction "1_1") (pintype "passive"))
      (node (ref "SV58") (pin "10") (pinfunction "10_10") (pintype "passive"))
      (node (ref "SV58") (pin "11") (pinfunction "11_11") (pintype "passive"))
      (node (ref "SV58") (pin "12") (pinfunction "12_12") (pintype "passive"))
      (node (ref "SV58") (pin "2") (pinfunction "2_2") (pintype "passive"))
      (node (ref "SV58") (pin "3") (pinfunction "3_3") (pintype "passive"))
      (node (ref "SV58") (pin "4") (pinfunction "4_4") (pintype "passive"))
      (node (ref "SV58") (pin "5") (pinfunction "5_5") (pintype "passive"))
      (node (ref "SV58") (pin "6") (pinfunction "6_6") (pintype "passive"))
      (node (ref "SV58") (pin "7") (pinfunction "7_7") (pintype "passive"))
      (node (ref "SV58") (pin "8") (pinfunction "8_8") (pintype "passive"))
      (node (ref "SV58") (pin "9") (pinfunction "9_9") (pintype "passive"))
      (node (ref "SV6") (pin "1") (pinfunction "1_1") (pintype "passive"))
      (node (ref "SV6") (pin "10") (pinfunction "10_10") (pintype "passive"))
      (node (ref "SV6") (pin "11") (pinfunction "11_11") (pintype "passive"))
      (node (ref "SV6") (pin "12") (pinfunction "12_12") (pintype "passive"))
      (node (ref "SV6") (pin "2") (pinfunction "2_2") (pintype "passive"))
      (node (ref "SV6") (pin "3") (pinfunction "3_3") (pintype "passive"))
      (node (ref "SV6") (pin "4") (pinfunction "4_4") (pintype "passive"))
      (node (ref "SV6") (pin "5") (pinfunction "5_5") (pintype "passive"))
      (node (ref "SV6") (pin "6") (pinfunction "6_6") (pintype "passive"))
      (node (ref "SV6") (pin "7") (pinfunction "7_7") (pintype "passive"))
      (node (ref "SV6") (pin "8") (pinfunction "8_8") (pintype "passive"))
      (node (ref "SV6") (pin "9") (pinfunction "9_9") (pintype "passive"))
      (node (ref "SV60") (pin "1") (pinfunction "1_1") (pintype "passive"))
      (node (ref "SV60") (pin "10") (pinfunction "10_10") (pintype "passive"))
      (node (ref "SV60") (pin "11") (pinfunction "11_11") (pintype "passive"))
      (node (ref "SV60") (pin "12") (pinfunction "12_12") (pintype "passive"))
      (node (ref "SV60") (pin "2") (pinfunction "2_2") (pintype "passive"))
      (node (ref "SV60") (pin "3") (pinfunction "3_3") (pintype "passive"))
      (node (ref "SV60") (pin "4") (pinfunction "4_4") (pintype "passive"))
      (node (ref "SV60") (pin "5") (pinfunction "5_5") (pintype "passive"))
      (node (ref "SV60") (pin "6") (pinfunction "6_6") (pintype "passive"))
      (node (ref "SV60") (pin "7") (pinfunction "7_7") (pintype "passive"))
      (node (ref "SV60") (pin "8") (pinfunction "8_8") (pintype "passive"))
      (node (ref "SV60") (pin "9") (pinfunction "9_9") (pintype "passive"))
      (node (ref "SV62") (pin "1") (pinfunction "1_1") (pintype "passive"))
      (node (ref "SV62") (pin "10") (pinfunction "10_10") (pintype "passive"))
      (node (ref "SV62") (pin "11") (pinfunction "11_11") (pintype "passive"))
      (node (ref "SV62") (pin "12") (pinfunction "12_12") (pintype "passive"))
      (node (ref "SV62") (pin "2") (pinfunction "2_2") (pintype "passive"))
      (node (ref "SV62") (pin "3") (pinfunction "3_3") (pintype "passive"))
      (node (ref "SV62") (pin "4") (pinfunction "4_4") (pintype "passive"))
      (node (ref "SV62") (pin "5") (pinfunction "5_5") (pintype "passive"))
      (node (ref "SV62") (pin "6") (pinfunction "6_6") (pintype "passive"))
      (node (ref "SV62") (pin "7") (pinfunction "7_7") (pintype "passive"))
      (node (ref "SV62") (pin "8") (pinfunction "8_8") (pintype "passive"))
      (node (ref "SV62") (pin "9") (pinfunction "9_9") (pintype "passive"))
      (node (ref "SV8") (pin "1") (pinfunction "1_1") (pintype "passive"))
      (node (ref "SV8") (pin "10") (pinfunction "10_10") (pintype "passive"))
      (node (ref "SV8") (pin "11") (pinfunction "11_11") (pintype "passive"))
      (node (ref "SV8") (pin "12") (pinfunction "12_12") (pintype "passive"))
      (node (ref "SV8") (pin "2") (pinfunction "2_2") (pintype "passive"))
      (node (ref "SV8") (pin "3") (pinfunction "3_3") (pintype "passive"))
      (node (ref "SV8") (pin "4") (pinfunction "4_4") (pintype "passive"))
      (node (ref "SV8") (pin "5") (pinfunction "5_5") (pintype "passive"))
      (node (ref "SV8") (pin "6") (pinfunction "6_6") (pintype "passive"))
      (node (ref "SV8") (pin "7") (pinfunction "7_7") (pintype "passive"))
      (node (ref "SV8") (pin "8") (pinfunction "8_8") (pintype "passive"))
      (node (ref "SV8") (pin "9") (pinfunction "9_9") (pintype "passive"))
      (node (ref "U$2") (pin "AC1") (pinfunction "1_AC1") (pintype "bidirectional"))
      (node (ref "U$2") (pin "AC2") (pinfunction "1_AC2") (pintype "bidirectional"))
      (node (ref "U$2") (pin "AF1") (pinfunction "1_AF1") (pintype "bidirectional"))
      (node (ref "U$2") (pin "AF2") (pinfunction "1_AF2") (pintype "bidirectional"))
      (node (ref "U$2") (pin "AN1") (pinfunction "1_AN1") (pintype "bidirectional"))
      (node (ref "U$2") (pin "AN2") (pinfunction "1_AN2") (pintype "bidirectional"))
      (node (ref "U$2") (pin "AT1") (pinfunction "1_AT1") (pintype "bidirectional"))
      (node (ref "U$2") (pin "AT2") (pinfunction "1_AT2") (pintype "bidirectional"))
      (node (ref "U$2") (pin "BC1") (pinfunction "1_BC1") (pintype "bidirectional"))
      (node (ref "U$2") (pin "BC2") (pinfunction "1_BC2") (pintype "bidirectional"))
      (node (ref "U$2") (pin "BF1") (pinfunction "1_BF1") (pintype "bidirectional"))
      (node (ref "U$2") (pin "BF2") (pinfunction "1_BF2") (pintype "bidirectional"))
      (node (ref "U$2") (pin "BN1") (pinfunction "1_BN1") (pintype "bidirectional"))
      (node (ref "U$2") (pin "BN2") (pinfunction "1_BN2") (pintype "bidirectional"))
      (node (ref "U$2") (pin "BT1") (pinfunction "1_BT1") (pintype "bidirectional"))
      (node (ref "U$2") (pin "BT2") (pinfunction "1_BT2") (pintype "bidirectional"))
      (node (ref "U$2") (pin "CC1") (pinfunction "1_CC1") (pintype "bidirectional"))
      (node (ref "U$2") (pin "CC2") (pinfunction "1_CC2") (pintype "bidirectional"))
      (node (ref "U$2") (pin "CF1") (pinfunction "1_CF1") (pintype "bidirectional"))
      (node (ref "U$2") (pin "CF2") (pinfunction "1_CF2") (pintype "bidirectional"))
      (node (ref "U$2") (pin "CN1") (pinfunction "1_CN1") (pintype "bidirectional"))
      (node (ref "U$2") (pin "CN2") (pinfunction "1_CN2") (pintype "bidirectional"))
      (node (ref "U$2") (pin "CT1") (pinfunction "1_CT1") (pintype "bidirectional"))
      (node (ref "U$2") (pin "CT2") (pinfunction "1_CT2") (pintype "bidirectional"))
      (node (ref "U$2") (pin "DC1") (pinfunction "1_DC1") (pintype "bidirectional"))
      (node (ref "U$2") (pin "DC2") (pinfunction "1_DC2") (pintype "bidirectional"))
      (node (ref "U$2") (pin "DF1") (pinfunction "1_DF1") (pintype "bidirectional"))
      (node (ref "U$2") (pin "DF2") (pinfunction "1_DF2") (pintype "bidirectional"))
      (node (ref "U$2") (pin "DN1") (pinfunction "1_DN1") (pintype "bidirectional"))
      (node (ref "U$2") (pin "DN2") (pinfunction "1_DN2") (pintype "bidirectional"))
      (node (ref "U$2") (pin "DT1") (pinfunction "1_DT1") (pintype "bidirectional"))
      (node (ref "U$2") (pin "DT2") (pinfunction "1_DT2") (pintype "bidirectional"))
    )
    (net (code "9") (name "INHIBIT") (class "Default")
      (node (ref "D10") (pin "13") (pinfunction "13_13") (pintype "passive"))
      (node (ref "U$2") (pin "AP2") (pinfunction "1_AP2") (pintype "bidirectional"))
    )
    (net (code "10") (name "INITIALIZE") (class "Default")
      (node (ref "D11") (pin "14") (pinfunction "14_14") (pintype "passive"))
      (node (ref "U$2") (pin "CR1") (pinfunction "1_CR1") (pintype "bidirectional"))
    )
    (net (code "11") (name "INT_IN_PROG") (class "Default")
      (node (ref "D8") (pin "13") (pinfunction "13_13") (pintype "passive"))
      (node (ref "U$2") (pin "BP2") (pinfunction "1_BP2") (pintype "bidirectional"))
    )
    (net (code "12") (name "INT_STROBE") (class "Default")
      (node (ref "D8") (pin "4") (pinfunction "4_4") (pintype "passive"))
      (node (ref "U$2") (pin "BD2") (pinfunction "1_BD2") (pintype "bidirectional"))
    )
    (net (code "13") (name "MD_DIR_H") (class "Default")
      (node (ref "IC7") (pin "9") (pinfunction "I0_9") (pintype "input"))
      (node (ref "IC8") (pin "13") (pinfunction "I_13") (pintype "input"))
      (node (ref "IC8") (pin "2") (pinfunction "O_2") (pintype "output"))
    )
    (net (code "14") (name "MD_DIR_L") (class "Default")
      (node (ref "IC7") (pin "3") (pinfunction "I0_3") (pintype "input"))
      (node (ref "IC8") (pin "12") (pinfunction "O_12") (pintype "output"))
    )
    (net (code "15") (name "MEM00") (class "Default")
      (node (ref "IC2") (pin "15") (pinfunction "B4_15") (pintype "bidirectional"))
      (node (ref "IC4") (pin "15") (pinfunction "I/O3_15") (pintype "tri_state"))
    )
    (net (code "16") (name "MEM01") (class "Default")
      (node (ref "IC2") (pin "16") (pinfunction "B3_16") (pintype "bidirectional"))
      (node (ref "IC4") (pin "13") (pinfunction "I/O2_13") (pintype "tri_state"))
    )
    (net (code "17") (name "MEM02") (class "Default")
      (node (ref "IC2") (pin "17") (pinfunction "B2_17") (pintype "bidirectional"))
      (node (ref "IC4") (pin "12") (pinfunction "I/O1_12") (pintype "tri_state"))
    )
    (net (code "18") (name "MEM03") (class "Default")
      (node (ref "IC2") (pin "18") (pinfunction "B1_18") (pintype "bidirectional"))
      (node (ref "IC4") (pin "11") (pinfunction "I/O0_11") (pintype "tri_state"))
    )
    (net (code "19") (name "MEM04") (class "Default")
      (node (ref "IC1") (pin "11") (pinfunction "B8_11") (pintype "bidirectional"))
      (node (ref "IC3") (pin "19") (pinfunction "I/O7_19") (pintype "tri_state"))
    )
    (net (code "20") (name "MEM05") (class "Default")
      (node (ref "IC1") (pin "12") (pinfunction "B7_12") (pintype "bidirectional"))
      (node (ref "IC3") (pin "18") (pinfunction "I/O6_18") (pintype "tri_state"))
    )
    (net (code "21") (name "MEM06") (class "Default")
      (node (ref "IC1") (pin "13") (pinfunction "B6_13") (pintype "bidirectional"))
      (node (ref "IC3") (pin "17") (pinfunction "I/O5_17") (pintype "tri_state"))
    )
    (net (code "22") (name "MEM07") (class "Default")
      (node (ref "IC1") (pin "14") (pinfunction "B5_14") (pintype "bidirectional"))
      (node (ref "IC3") (pin "16") (pinfunction "I/O4_16") (pintype "tri_state"))
    )
    (net (code "23") (name "MEM08") (class "Default")
      (node (ref "IC1") (pin "15") (pinfunction "B4_15") (pintype "bidirectional"))
      (node (ref "IC3") (pin "15") (pinfunction "I/O3_15") (pintype "tri_state"))
    )
    (net (code "24") (name "MEM09") (class "Default")
      (node (ref "IC1") (pin "16") (pinfunction "B3_16") (pintype "bidirectional"))
      (node (ref "IC3") (pin "13") (pinfunction "I/O2_13") (pintype "tri_state"))
    )
    (net (code "25") (name "MEM10") (class "Default")
      (node (ref "IC1") (pin "17") (pinfunction "B2_17") (pintype "bidirectional"))
      (node (ref "IC3") (pin "12") (pinfunction "I/O1_12") (pintype "tri_state"))
    )
    (net (code "26") (name "MEM11") (class "Default")
      (node (ref "IC1") (pin "18") (pinfunction "B1_18") (pintype "bidirectional"))
      (node (ref "IC3") (pin "11") (pinfunction "I/O0_11") (pintype "tri_state"))
    )
    (net (code "27") (name "Net-(B1-+-Pad+@1)") (class "Default")
      (node (ref "B1") (pin "+") (pinfunction "+_+") (pintype "passive"))
      (node (ref "B1") (pin "+@1") (pinfunction "+_+@1") (pintype "passive"))
      (node (ref "B1") (pin "+@2") (pinfunction "+_+@2") (pintype "passive"))
      (node (ref "B1") (pin "+@3") (pinfunction "+_+@3") (pintype "passive"))
      (node (ref "B1") (pin "+@4") (pinfunction "+_+@4") (pintype "passive"))
      (node (ref "D1") (pin "A") (pinfunction "A_A") (pintype "passive"))
    )
    (net (code "28") (name "Net-(IC2A-A5)") (class "Default")
      (node (ref "IC2") (pin "6") (pinfunction "A5_6") (pintype "bidirectional"))
      (node (ref "R4") (pin "2") (pinfunction "2_2") (pintype "passive"))
    )
    (net (code "29") (name "Net-(IC2A-A6)") (class "Default")
      (node (ref "IC2") (pin "7") (pinfunction "A6_7") (pintype "bidirectional"))
      (node (ref "R3") (pin "2") (pinfunction "2_2") (pintype "passive"))
    )
    (net (code "30") (name "Net-(IC2A-A7)") (class "Default")
      (node (ref "IC2") (pin "8") (pinfunction "A7_8") (pintype "bidirectional"))
      (node (ref "R2") (pin "2") (pinfunction "2_2") (pintype "passive"))
    )
    (net (code "31") (name "Net-(IC2A-A8)") (class "Default")
      (node (ref "IC2") (pin "9") (pinfunction "A8_9") (pintype "bidirectional"))
      (node (ref "R1") (pin "2") (pinfunction "2_2") (pintype "passive"))
    )
    (net (code "32") (name "Net-(IC5A-Y0)") (class "Default")
      (node (ref "IC5") (pin "15") (pinfunction "Y0_15") (pintype "output"))
      (node (ref "S1") (pin "9") (pinfunction "9_9") (pintype "passive"))
    )
    (net (code "33") (name "Net-(IC5A-Y1)") (class "Default")
      (node (ref "IC5") (pin "14") (pinfunction "Y1_14") (pintype "output"))
      (node (ref "S1") (pin "10") (pinfunction "10_10") (pintype "passive"))
    )
    (net (code "34") (name "Net-(IC5A-Y2)") (class "Default")
      (node (ref "IC5") (pin "13") (pinfunction "Y2_13") (pintype "output"))
      (node (ref "S1") (pin "11") (pinfunction "11_11") (pintype "passive"))
    )
    (net (code "35") (name "Net-(IC5A-Y3)") (class "Default")
      (node (ref "IC5") (pin "12") (pinfunction "Y3_12") (pintype "output"))
      (node (ref "S1") (pin "12") (pinfunction "12_12") (pintype "passive"))
    )
    (net (code "36") (name "Net-(IC5A-Y4)") (class "Default")
      (node (ref "IC5") (pin "11") (pinfunction "Y4_11") (pintype "output"))
      (node (ref "S1") (pin "13") (pinfunction "13_13") (pintype "passive"))
    )
    (net (code "37") (name "Net-(IC5A-Y5)") (class "Default")
      (node (ref "IC5") (pin "10") (pinfunction "Y5_10") (pintype "output"))
      (node (ref "S1") (pin "14") (pinfunction "14_14") (pintype "passive"))
    )
    (net (code "38") (name "Net-(IC5A-Y6)") (class "Default")
      (node (ref "IC5") (pin "9") (pinfunction "Y6_9") (pintype "output"))
      (node (ref "S1") (pin "15") (pinfunction "15_15") (pintype "passive"))
    )
    (net (code "39") (name "Net-(IC5A-Y7)") (class "Default")
      (node (ref "IC5") (pin "7") (pinfunction "Y7_7") (pintype "output"))
      (node (ref "S1") (pin "16") (pinfunction "16_16") (pintype "passive"))
    )
    (net (code "40") (name "Net-(IC6A-I0)") (class "Default")
      (node (ref "IC6") (pin "1") (pinfunction "I0_1") (pintype "input"))
      (node (ref "R5") (pin "8") (pinfunction "1_8") (pintype "passive"))
      (node (ref "S1") (pin "1") (pinfunction "1_1") (pintype "passive"))
    )
    (net (code "41") (name "Net-(IC6A-I1)") (class "Default")
      (node (ref "IC6") (pin "2") (pinfunction "I1_2") (pintype "input"))
      (node (ref "R5") (pin "1") (pinfunction "1_1") (pintype "passive"))
      (node (ref "S1") (pin "8") (pinfunction "8_8") (pintype "passive"))
    )
    (net (code "42") (name "Net-(IC6A-I2)") (class "Default")
      (node (ref "IC6") (pin "3") (pinfunction "I2_3") (pintype "input"))
      (node (ref "R5") (pin "7") (pinfunction "1_7") (pintype "passive"))
      (node (ref "S1") (pin "2") (pinfunction "2_2") (pintype "passive"))
    )
    (net (code "43") (name "Net-(IC6A-I3)") (class "Default")
      (node (ref "IC6") (pin "4") (pinfunction "I3_4") (pintype "input"))
      (node (ref "R5") (pin "2") (pinfunction "1_2") (pintype "passive"))
      (node (ref "S1") (pin "7") (pinfunction "7_7") (pintype "passive"))
    )
    (net (code "44") (name "Net-(IC6A-I4)") (class "Default")
      (node (ref "IC6") (pin "5") (pinfunction "I4_5") (pintype "input"))
      (node (ref "R5") (pin "6") (pinfunction "1_6") (pintype "passive"))
      (node (ref "S1") (pin "3") (pinfunction "3_3") (pintype "passive"))
    )
    (net (code "45") (name "Net-(IC6A-I5)") (class "Default")
      (node (ref "IC6") (pin "6") (pinfunction "I5_6") (pintype "input"))
      (node (ref "R5") (pin "5") (pinfunction "1_5") (pintype "passive"))
      (node (ref "S1") (pin "4") (pinfunction "4_4") (pintype "passive"))
    )
    (net (code "46") (name "Net-(IC6A-I6)") (class "Default")
      (node (ref "IC6") (pin "11") (pinfunction "I6_11") (pintype "input"))
      (node (ref "R5") (pin "3") (pinfunction "1_3") (pintype "passive"))
      (node (ref "S1") (pin "6") (pinfunction "6_6") (pintype "passive"))
    )
    (net (code "47") (name "Net-(IC6A-I7)") (class "Default")
      (node (ref "IC6") (pin "12") (pinfunction "I7_12") (pintype "input"))
      (node (ref "R5") (pin "4") (pinfunction "1_4") (pintype "passive"))
      (node (ref "S1") (pin "5") (pinfunction "5_5") (pintype "passive"))
    )
    (net (code "48") (name "Net-(IC9A-CLR)") (class "Default")
      (node (ref "IC9") (pin "1") (pinfunction "CLR_1") (pintype "input"))
      (node (ref "IC9") (pin "9") (pinfunction "Q_9") (pintype "output"))
    )
    (net (code "49") (name "Net-(IC10-Pad1)") (class "Default")
      (node (ref "IC10") (pin "1") (pinfunction "1_1") (pintype "passive"))
      (node (ref "IC11") (pin "1") (pinfunction "1_1") (pintype "passive"))
      (node (ref "IC12") (pin "1") (pinfunction "1_1") (pintype "passive"))
      (node (ref "IC13") (pin "1") (pinfunction "1_1") (pintype "passive"))
    )
    (net (code "50") (name "Net-(IC10-Pad2)") (class "Default")
      (node (ref "IC10") (pin "2") (pinfunction "2_2") (pintype "passive"))
      (node (ref "IC11") (pin "2") (pinfunction "2_2") (pintype "passive"))
      (node (ref "IC12") (pin "2") (pinfunction "2_2") (pintype "passive"))
      (node (ref "IC13") (pin "2") (pinfunction "2_2") (pintype "passive"))
    )
    (net (code "51") (name "Net-(IC10-Pad3)") (class "Default")
      (node (ref "IC10") (pin "3") (pinfunction "3_3") (pintype "passive"))
      (node (ref "IC11") (pin "3") (pinfunction "3_3") (pintype "passive"))
      (node (ref "IC12") (pin "3") (pinfunction "3_3") (pintype "passive"))
      (node (ref "IC13") (pin "3") (pinfunction "3_3") (pintype "passive"))
    )
    (net (code "52") (name "Net-(IC10-Pad4)") (class "Default")
      (node (ref "IC10") (pin "4") (pinfunction "4_4") (pintype "passive"))
      (node (ref "IC11") (pin "4") (pinfunction "4_4") (pintype "passive"))
      (node (ref "IC12") (pin "4") (pinfunction "4_4") (pintype "passive"))
      (node (ref "IC13") (pin "4") (pinfunction "4_4") (pintype "passive"))
    )
    (net (code "53") (name "Net-(IC10-Pad5)") (class "Default")
      (node (ref "IC10") (pin "5") (pinfunction "5_5") (pintype "passive"))
      (node (ref "IC11") (pin "5") (pinfunction "5_5") (pintype "passive"))
      (node (ref "IC12") (pin "5") (pinfunction "5_5") (pintype "passive"))
      (node (ref "IC13") (pin "5") (pinfunction "5_5") (pintype "passive"))
    )
    (net (code "54") (name "Net-(IC10-Pad6)") (class "Default")
      (node (ref "IC10") (pin "6") (pinfunction "6_6") (pintype "passive"))
      (node (ref "IC11") (pin "6") (pinfunction "6_6") (pintype "passive"))
      (node (ref "IC12") (pin "6") (pinfunction "6_6") (pintype "passive"))
      (node (ref "IC13") (pin "6") (pinfunction "6_6") (pintype "passive"))
    )
    (net (code "55") (name "Net-(IC10-Pad7)") (class "Default")
      (node (ref "IC10") (pin "7") (pinfunction "7_7") (pintype "passive"))
      (node (ref "IC11") (pin "7") (pinfunction "7_7") (pintype "passive"))
      (node (ref "IC12") (pin "7") (pinfunction "7_7") (pintype "passive"))
      (node (ref "IC13") (pin "7") (pinfunction "7_7") (pintype "passive"))
    )
    (net (code "56") (name "Net-(IC10-Pad8)") (class "Default")
      (node (ref "IC10") (pin "8") (pinfunction "8_8") (pintype "passive"))
      (node (ref "IC11") (pin "8") (pinfunction "8_8") (pintype "passive"))
      (node (ref "IC12") (pin "8") (pinfunction "8_8") (pintype "passive"))
      (node (ref "IC13") (pin "8") (pinfunction "8_8") (pintype "passive"))
    )
    (net (code "57") (name "Net-(IC10-Pad9)") (class "Default")
      (node (ref "IC10") (pin "9") (pinfunction "9_9") (pintype "passive"))
      (node (ref "IC11") (pin "9") (pinfunction "9_9") (pintype "passive"))
      (node (ref "IC12") (pin "9") (pinfunction "9_9") (pintype "passive"))
      (node (ref "IC13") (pin "9") (pinfunction "9_9") (pintype "passive"))
    )
    (net (code "58") (name "Net-(IC10-Pad10)") (class "Default")
      (node (ref "IC10") (pin "10") (pinfunction "10_10") (pintype "passive"))
      (node (ref "IC11") (pin "10") (pinfunction "10_10") (pintype "passive"))
      (node (ref "IC12") (pin "10") (pinfunction "10_10") (pintype "passive"))
      (node (ref "IC13") (pin "10") (pinfunction "10_10") (pintype "passive"))
    )
    (net (code "59") (name "Net-(IC10-Pad11)") (class "Default")
      (node (ref "IC10") (pin "11") (pinfunction "11_11") (pintype "passive"))
      (node (ref "IC11") (pin "11") (pinfunction "11_11") (pintype "passive"))
      (node (ref "IC12") (pin "11") (pinfunction "11_11") (pintype "passive"))
      (node (ref "IC13") (pin "11") (pinfunction "11_11") (pintype "passive"))
    )
    (net (code "60") (name "Net-(IC10-Pad12)") (class "Default")
      (node (ref "IC10") (pin "12") (pinfunction "12_12") (pintype "passive"))
      (node (ref "IC11") (pin "12") (pinfunction "12_12") (pintype "passive"))
      (node (ref "IC12") (pin "12") (pinfunction "12_12") (pintype "passive"))
      (node (ref "IC13") (pin "12") (pinfunction "12_12") (pintype "passive"))
    )
    (net (code "61") (name "Net-(IC10-Pad13)") (class "Default")
      (node (ref "IC10") (pin "13") (pinfunction "13_13") (pintype "passive"))
      (node (ref "IC11") (pin "13") (pinfunction "13_13") (pintype "passive"))
      (node (ref "IC12") (pin "13") (pinfunction "13_13") (pintype "passive"))
      (node (ref "IC13") (pin "13") (pinfunction "13_13") (pintype "passive"))
    )
    (net (code "62") (name "Net-(IC10-Pad14)") (class "Default")
      (node (ref "IC10") (pin "14") (pinfunction "14_14") (pintype "passive"))
      (node (ref "IC11") (pin "14") (pinfunction "14_14") (pintype "passive"))
      (node (ref "IC12") (pin "14") (pinfunction "14_14") (pintype "passive"))
      (node (ref "IC13") (pin "14") (pinfunction "14_14") (pintype "passive"))
    )
    (net (code "63") (name "Net-(IC10-Pad15)") (class "Default")
      (node (ref "IC10") (pin "15") (pinfunction "15_15") (pintype "passive"))
      (node (ref "IC11") (pin "15") (pinfunction "15_15") (pintype "passive"))
      (node (ref "IC12") (pin "15") (pinfunction "15_15") (pintype "passive"))
      (node (ref "IC13") (pin "15") (pinfunction "15_15") (pintype "passive"))
    )
    (net (code "64") (name "Net-(IC10-Pad16)") (class "Default")
      (node (ref "IC10") (pin "16") (pinfunction "16_16") (pintype "passive"))
      (node (ref "IC11") (pin "16") (pinfunction "16_16") (pintype "passive"))
      (node (ref "IC12") (pin "16") (pinfunction "16_16") (pintype "passive"))
      (node (ref "IC13") (pin "16") (pinfunction "16_16") (pintype "passive"))
    )
    (net (code "65") (name "Net-(IC10-Pad17)") (class "Default")
      (node (ref "IC10") (pin "17") (pinfunction "17_17") (pintype "passive"))
      (node (ref "IC11") (pin "17") (pinfunction "17_17") (pintype "passive"))
      (node (ref "IC12") (pin "17") (pinfunction "17_17") (pintype "passive"))
      (node (ref "IC13") (pin "17") (pinfunction "17_17") (pintype "passive"))
    )
    (net (code "66") (name "Net-(IC10-Pad18)") (class "Default")
      (node (ref "IC10") (pin "18") (pinfunction "18_18") (pintype "passive"))
      (node (ref "IC11") (pin "18") (pinfunction "18_18") (pintype "passive"))
      (node (ref "IC12") (pin "18") (pinfunction "18_18") (pintype "passive"))
      (node (ref "IC13") (pin "18") (pinfunction "18_18") (pintype "passive"))
    )
    (net (code "67") (name "Net-(IC10-Pad19)") (class "Default")
      (node (ref "IC10") (pin "19") (pinfunction "19_19") (pintype "passive"))
      (node (ref "IC11") (pin "19") (pinfunction "19_19") (pintype "passive"))
      (node (ref "IC12") (pin "19") (pinfunction "19_19") (pintype "passive"))
      (node (ref "IC13") (pin "19") (pinfunction "19_19") (pintype "passive"))
    )
    (net (code "68") (name "Net-(IC10-Pad20)") (class "Default")
      (node (ref "IC10") (pin "20") (pinfunction "20_20") (pintype "passive"))
      (node (ref "IC11") (pin "20") (pinfunction "20_20") (pintype "passive"))
      (node (ref "IC12") (pin "20") (pinfunction "20_20") (pintype "passive"))
      (node (ref "IC13") (pin "20") (pinfunction "20_20") (pintype "passive"))
    )
    (net (code "69") (name "Net-(IC10-Pad21)") (class "Default")
      (node (ref "IC10") (pin "21") (pinfunction "21_21") (pintype "passive"))
      (node (ref "IC11") (pin "21") (pinfunction "21_21") (pintype "passive"))
      (node (ref "IC12") (pin "21") (pinfunction "21_21") (pintype "passive"))
      (node (ref "IC13") (pin "21") (pinfunction "21_21") (pintype "passive"))
    )
    (net (code "70") (name "Net-(IC10-Pad22)") (class "Default")
      (node (ref "IC10") (pin "22") (pinfunction "22_22") (pintype "passive"))
      (node (ref "IC11") (pin "22") (pinfunction "22_22") (pintype "passive"))
      (node (ref "IC12") (pin "22") (pinfunction "22_22") (pintype "passive"))
      (node (ref "IC13") (pin "22") (pinfunction "22_22") (pintype "passive"))
    )
    (net (code "71") (name "Net-(IC10-Pad23)") (class "Default")
      (node (ref "IC10") (pin "23") (pinfunction "23_23") (pintype "passive"))
      (node (ref "IC11") (pin "23") (pinfunction "23_23") (pintype "passive"))
      (node (ref "IC12") (pin "23") (pinfunction "23_23") (pintype "passive"))
      (node (ref "IC13") (pin "23") (pinfunction "23_23") (pintype "passive"))
    )
    (net (code "72") (name "Net-(IC10-Pad24)") (class "Default")
      (node (ref "IC10") (pin "24") (pinfunction "24_24") (pintype "passive"))
      (node (ref "IC11") (pin "24") (pinfunction "24_24") (pintype "passive"))
      (node (ref "IC12") (pin "24") (pinfunction "24_24") (pintype "passive"))
      (node (ref "IC13") (pin "24") (pinfunction "24_24") (pintype "passive"))
    )
    (net (code "73") (name "Net-(IC14-Pad1)") (class "Default")
      (node (ref "IC14") (pin "1") (pinfunction "1_1") (pintype "passive"))
      (node (ref "IC15") (pin "1") (pinfunction "1_1") (pintype "passive"))
      (node (ref "IC16") (pin "1") (pinfunction "1_1") (pintype "passive"))
      (node (ref "IC17") (pin "1") (pinfunction "1_1") (pintype "passive"))
    )
    (net (code "74") (name "Net-(IC14-Pad2)") (class "Default")
      (node (ref "IC14") (pin "2") (pinfunction "2_2") (pintype "passive"))
      (node (ref "IC15") (pin "2") (pinfunction "2_2") (pintype "passive"))
      (node (ref "IC16") (pin "2") (pinfunction "2_2") (pintype "passive"))
      (node (ref "IC17") (pin "2") (pinfunction "2_2") (pintype "passive"))
    )
    (net (code "75") (name "Net-(IC14-Pad3)") (class "Default")
      (node (ref "IC14") (pin "3") (pinfunction "3_3") (pintype "passive"))
      (node (ref "IC15") (pin "3") (pinfunction "3_3") (pintype "passive"))
      (node (ref "IC16") (pin "3") (pinfunction "3_3") (pintype "passive"))
      (node (ref "IC17") (pin "3") (pinfunction "3_3") (pintype "passive"))
    )
    (net (code "76") (name "Net-(IC14-Pad4)") (class "Default")
      (node (ref "IC14") (pin "4") (pinfunction "4_4") (pintype "passive"))
      (node (ref "IC15") (pin "4") (pinfunction "4_4") (pintype "passive"))
      (node (ref "IC16") (pin "4") (pinfunction "4_4") (pintype "passive"))
      (node (ref "IC17") (pin "4") (pinfunction "4_4") (pintype "passive"))
    )
    (net (code "77") (name "Net-(IC14-Pad5)") (class "Default")
      (node (ref "IC14") (pin "5") (pinfunction "5_5") (pintype "passive"))
      (node (ref "IC15") (pin "5") (pinfunction "5_5") (pintype "passive"))
      (node (ref "IC16") (pin "5") (pinfunction "5_5") (pintype "passive"))
      (node (ref "IC17") (pin "5") (pinfunction "5_5") (pintype "passive"))
    )
    (net (code "78") (name "Net-(IC14-Pad6)") (class "Default")
      (node (ref "IC14") (pin "6") (pinfunction "6_6") (pintype "passive"))
      (node (ref "IC15") (pin "6") (pinfunction "6_6") (pintype "passive"))
      (node (ref "IC16") (pin "6") (pinfunction "6_6") (pintype "passive"))
      (node (ref "IC17") (pin "6") (pinfunction "6_6") (pintype "passive"))
    )
    (net (code "79") (name "Net-(IC14-Pad7)") (class "Default")
      (node (ref "IC14") (pin "7") (pinfunction "7_7") (pintype "passive"))
      (node (ref "IC15") (pin "7") (pinfunction "7_7") (pintype "passive"))
      (node (ref "IC16") (pin "7") (pinfunction "7_7") (pintype "passive"))
      (node (ref "IC17") (pin "7") (pinfunction "7_7") (pintype "passive"))
    )
    (net (code "80") (name "Net-(IC14-Pad8)") (class "Default")
      (node (ref "IC14") (pin "8") (pinfunction "8_8") (pintype "passive"))
      (node (ref "IC15") (pin "8") (pinfunction "8_8") (pintype "passive"))
      (node (ref "IC16") (pin "8") (pinfunction "8_8") (pintype "passive"))
      (node (ref "IC17") (pin "8") (pinfunction "8_8") (pintype "passive"))
    )
    (net (code "81") (name "Net-(IC14-Pad9)") (class "Default")
      (node (ref "IC14") (pin "9") (pinfunction "9_9") (pintype "passive"))
      (node (ref "IC15") (pin "9") (pinfunction "9_9") (pintype "passive"))
      (node (ref "IC16") (pin "9") (pinfunction "9_9") (pintype "passive"))
      (node (ref "IC17") (pin "9") (pinfunction "9_9") (pintype "passive"))
    )
    (net (code "82") (name "Net-(IC14-Pad10)") (class "Default")
      (node (ref "IC14") (pin "10") (pinfunction "10_10") (pintype "passive"))
      (node (ref "IC15") (pin "10") (pinfunction "10_10") (pintype "passive"))
      (node (ref "IC16") (pin "10") (pinfunction "10_10") (pintype "passive"))
      (node (ref "IC17") (pin "10") (pinfunction "10_10") (pintype "passive"))
    )
    (net (code "83") (name "Net-(IC14-Pad11)") (class "Default")
      (node (ref "IC14") (pin "11") (pinfunction "11_11") (pintype "passive"))
      (node (ref "IC15") (pin "11") (pinfunction "11_11") (pintype "passive"))
      (node (ref "IC16") (pin "11") (pinfunction "11_11") (pintype "passive"))
      (node (ref "IC17") (pin "11") (pinfunction "11_11") (pintype "passive"))
    )
    (net (code "84") (name "Net-(IC14-Pad12)") (class "Default")
      (node (ref "IC14") (pin "12") (pinfunction "12_12") (pintype "passive"))
      (node (ref "IC15") (pin "12") (pinfunction "12_12") (pintype "passive"))
      (node (ref "IC16") (pin "12") (pinfunction "12_12") (pintype "passive"))
      (node (ref "IC17") (pin "12") (pinfunction "12_12") (pintype "passive"))
    )
    (net (code "85") (name "Net-(IC14-Pad13)") (class "Default")
      (node (ref "IC14") (pin "13") (pinfunction "13_13") (pintype "passive"))
      (node (ref "IC15") (pin "13") (pinfunction "13_13") (pintype "passive"))
      (node (ref "IC16") (pin "13") (pinfunction "13_13") (pintype "passive"))
      (node (ref "IC17") (pin "13") (pinfunction "13_13") (pintype "passive"))
    )
    (net (code "86") (name "Net-(IC14-Pad14)") (class "Default")
      (node (ref "IC14") (pin "14") (pinfunction "14_14") (pintype "passive"))
      (node (ref "IC15") (pin "14") (pinfunction "14_14") (pintype "passive"))
      (node (ref "IC16") (pin "14") (pinfunction "14_14") (pintype "passive"))
      (node (ref "IC17") (pin "14") (pinfunction "14_14") (pintype "passive"))
    )
    (net (code "87") (name "Net-(IC14-Pad15)") (class "Default")
      (node (ref "IC14") (pin "15") (pinfunction "15_15") (pintype "passive"))
      (node (ref "IC15") (pin "15") (pinfunction "15_15") (pintype "passive"))
      (node (ref "IC16") (pin "15") (pinfunction "15_15") (pintype "passive"))
      (node (ref "IC17") (pin "15") (pinfunction "15_15") (pintype "passive"))
    )
    (net (code "88") (name "Net-(IC14-Pad16)") (class "Default")
      (node (ref "IC14") (pin "16") (pinfunction "16_16") (pintype "passive"))
      (node (ref "IC15") (pin "16") (pinfunction "16_16") (pintype "passive"))
      (node (ref "IC16") (pin "16") (pinfunction "16_16") (pintype "passive"))
      (node (ref "IC17") (pin "16") (pinfunction "16_16") (pintype "passive"))
    )
    (net (code "89") (name "Net-(IC14-Pad17)") (class "Default")
      (node (ref "IC14") (pin "17") (pinfunction "17_17") (pintype "passive"))
      (node (ref "IC15") (pin "17") (pinfunction "17_17") (pintype "passive"))
      (node (ref "IC16") (pin "17") (pinfunction "17_17") (pintype "passive"))
      (node (ref "IC17") (pin "17") (pinfunction "17_17") (pintype "passive"))
    )
    (net (code "90") (name "Net-(IC14-Pad18)") (class "Default")
      (node (ref "IC14") (pin "18") (pinfunction "18_18") (pintype "passive"))
      (node (ref "IC15") (pin "18") (pinfunction "18_18") (pintype "passive"))
      (node (ref "IC16") (pin "18") (pinfunction "18_18") (pintype "passive"))
      (node (ref "IC17") (pin "18") (pinfunction "18_18") (pintype "passive"))
    )
    (net (code "91") (name "Net-(IC14-Pad19)") (class "Default")
      (node (ref "IC14") (pin "19") (pinfunction "19_19") (pintype "passive"))
      (node (ref "IC15") (pin "19") (pinfunction "19_19") (pintype "passive"))
      (node (ref "IC16") (pin "19") (pinfunction "19_19") (pintype "passive"))
      (node (ref "IC17") (pin "19") (pinfunction "19_19") (pintype "passive"))
    )
    (net (code "92") (name "Net-(IC14-Pad20)") (class "Default")
      (node (ref "IC14") (pin "20") (pinfunction "20_20") (pintype "passive"))
      (node (ref "IC15") (pin "20") (pinfunction "20_20") (pintype "passive"))
      (node (ref "IC16") (pin "20") (pinfunction "20_20") (pintype "passive"))
      (node (ref "IC17") (pin "20") (pinfunction "20_20") (pintype "passive"))
    )
    (net (code "93") (name "Net-(IC14-Pad21)") (class "Default")
      (node (ref "IC14") (pin "21") (pinfunction "21_21") (pintype "passive"))
      (node (ref "IC15") (pin "21") (pinfunction "21_21") (pintype "passive"))
      (node (ref "IC16") (pin "21") (pinfunction "21_21") (pintype "passive"))
      (node (ref "IC17") (pin "21") (pinfunction "21_21") (pintype "passive"))
    )
    (net (code "94") (name "Net-(IC14-Pad22)") (class "Default")
      (node (ref "IC14") (pin "22") (pinfunction "22_22") (pintype "passive"))
      (node (ref "IC15") (pin "22") (pinfunction "22_22") (pintype "passive"))
      (node (ref "IC16") (pin "22") (pinfunction "22_22") (pintype "passive"))
      (node (ref "IC17") (pin "22") (pinfunction "22_22") (pintype "passive"))
    )
    (net (code "95") (name "Net-(IC14-Pad23)") (class "Default")
      (node (ref "IC14") (pin "23") (pinfunction "23_23") (pintype "passive"))
      (node (ref "IC15") (pin "23") (pinfunction "23_23") (pintype "passive"))
      (node (ref "IC16") (pin "23") (pinfunction "23_23") (pintype "passive"))
      (node (ref "IC17") (pin "23") (pinfunction "23_23") (pintype "passive"))
    )
    (net (code "96") (name "Net-(IC14-Pad24)") (class "Default")
      (node (ref "IC14") (pin "24") (pinfunction "24_24") (pintype "passive"))
      (node (ref "IC15") (pin "24") (pinfunction "24_24") (pintype "passive"))
      (node (ref "IC16") (pin "24") (pinfunction "24_24") (pintype "passive"))
      (node (ref "IC17") (pin "24") (pinfunction "24_24") (pintype "passive"))
    )
    (net (code "97") (name "Net-(IC18-Pad1)") (class "Default")
      (node (ref "IC18") (pin "1") (pinfunction "1_1") (pintype "passive"))
      (node (ref "IC19") (pin "1") (pinfunction "1_1") (pintype "passive"))
      (node (ref "IC20") (pin "1") (pinfunction "1_1") (pintype "passive"))
      (node (ref "IC21") (pin "1") (pinfunction "1_1") (pintype "passive"))
    )
    (net (code "98") (name "Net-(IC18-Pad2)") (class "Default")
      (node (ref "IC18") (pin "2") (pinfunction "2_2") (pintype "passive"))
      (node (ref "IC19") (pin "2") (pinfunction "2_2") (pintype "passive"))
      (node (ref "IC20") (pin "2") (pinfunction "2_2") (pintype "passive"))
      (node (ref "IC21") (pin "2") (pinfunction "2_2") (pintype "passive"))
    )
    (net (code "99") (name "Net-(IC18-Pad3)") (class "Default")
      (node (ref "IC18") (pin "3") (pinfunction "3_3") (pintype "passive"))
      (node (ref "IC19") (pin "3") (pinfunction "3_3") (pintype "passive"))
      (node (ref "IC20") (pin "3") (pinfunction "3_3") (pintype "passive"))
      (node (ref "IC21") (pin "3") (pinfunction "3_3") (pintype "passive"))
    )
    (net (code "100") (name "Net-(IC18-Pad4)") (class "Default")
      (node (ref "IC18") (pin "4") (pinfunction "4_4") (pintype "passive"))
      (node (ref "IC19") (pin "4") (pinfunction "4_4") (pintype "passive"))
      (node (ref "IC20") (pin "4") (pinfunction "4_4") (pintype "passive"))
      (node (ref "IC21") (pin "4") (pinfunction "4_4") (pintype "passive"))
    )
    (net (code "101") (name "Net-(IC18-Pad5)") (class "Default")
      (node (ref "IC18") (pin "5") (pinfunction "5_5") (pintype "passive"))
      (node (ref "IC19") (pin "5") (pinfunction "5_5") (pintype "passive"))
      (node (ref "IC20") (pin "5") (pinfunction "5_5") (pintype "passive"))
      (node (ref "IC21") (pin "5") (pinfunction "5_5") (pintype "passive"))
    )
    (net (code "102") (name "Net-(IC18-Pad6)") (class "Default")
      (node (ref "IC18") (pin "6") (pinfunction "6_6") (pintype "passive"))
      (node (ref "IC19") (pin "6") (pinfunction "6_6") (pintype "passive"))
      (node (ref "IC20") (pin "6") (pinfunction "6_6") (pintype "passive"))
      (node (ref "IC21") (pin "6") (pinfunction "6_6") (pintype "passive"))
    )
    (net (code "103") (name "Net-(IC18-Pad7)") (class "Default")
      (node (ref "IC18") (pin "7") (pinfunction "7_7") (pintype "passive"))
      (node (ref "IC19") (pin "7") (pinfunction "7_7") (pintype "passive"))
      (node (ref "IC20") (pin "7") (pinfunction "7_7") (pintype "passive"))
      (node (ref "IC21") (pin "7") (pinfunction "7_7") (pintype "passive"))
    )
    (net (code "104") (name "Net-(IC18-Pad8)") (class "Default")
      (node (ref "IC18") (pin "8") (pinfunction "8_8") (pintype "passive"))
      (node (ref "IC19") (pin "8") (pinfunction "8_8") (pintype "passive"))
      (node (ref "IC20") (pin "8") (pinfunction "8_8") (pintype "passive"))
      (node (ref "IC21") (pin "8") (pinfunction "8_8") (pintype "passive"))
    )
    (net (code "105") (name "Net-(IC18-Pad9)") (class "Default")
      (node (ref "IC18") (pin "9") (pinfunction "9_9") (pintype "passive"))
      (node (ref "IC19") (pin "9") (pinfunction "9_9") (pintype "passive"))
      (node (ref "IC20") (pin "9") (pinfunction "9_9") (pintype "passive"))
      (node (ref "IC21") (pin "9") (pinfunction "9_9") (pintype "passive"))
    )
    (net (code "106") (name "Net-(IC18-Pad10)") (class "Default")
      (node (ref "IC18") (pin "10") (pinfunction "10_10") (pintype "passive"))
      (node (ref "IC19") (pin "10") (pinfunction "10_10") (pintype "passive"))
      (node (ref "IC20") (pin "10") (pinfunction "10_10") (pintype "passive"))
      (node (ref "IC21") (pin "10") (pinfunction "10_10") (pintype "passive"))
    )
    (net (code "107") (name "Net-(IC18-Pad11)") (class "Default")
      (node (ref "IC18") (pin "11") (pinfunction "11_11") (pintype "passive"))
      (node (ref "IC19") (pin "11") (pinfunction "11_11") (pintype "passive"))
      (node (ref "IC20") (pin "11") (pinfunction "11_11") (pintype "passive"))
      (node (ref "IC21") (pin "11") (pinfunction "11_11") (pintype "passive"))
    )
    (net (code "108") (name "Net-(IC18-Pad12)") (class "Default")
      (node (ref "IC18") (pin "12") (pinfunction "12_12") (pintype "passive"))
      (node (ref "IC19") (pin "12") (pinfunction "12_12") (pintype "passive"))
      (node (ref "IC20") (pin "12") (pinfunction "12_12") (pintype "passive"))
      (node (ref "IC21") (pin "12") (pinfunction "12_12") (pintype "passive"))
    )
    (net (code "109") (name "Net-(IC18-Pad13)") (class "Default")
      (node (ref "IC18") (pin "13") (pinfunction "13_13") (pintype "passive"))
      (node (ref "IC19") (pin "13") (pinfunction "13_13") (pintype "passive"))
      (node (ref "IC20") (pin "13") (pinfunction "13_13") (pintype "passive"))
      (node (ref "IC21") (pin "13") (pinfunction "13_13") (pintype "passive"))
    )
    (net (code "110") (name "Net-(IC18-Pad14)") (class "Default")
      (node (ref "IC18") (pin "14") (pinfunction "14_14") (pintype "passive"))
      (node (ref "IC19") (pin "14") (pinfunction "14_14") (pintype "passive"))
      (node (ref "IC20") (pin "14") (pinfunction "14_14") (pintype "passive"))
      (node (ref "IC21") (pin "14") (pinfunction "14_14") (pintype "passive"))
    )
    (net (code "111") (name "Net-(IC18-Pad15)") (class "Default")
      (node (ref "IC18") (pin "15") (pinfunction "15_15") (pintype "passive"))
      (node (ref "IC19") (pin "15") (pinfunction "15_15") (pintype "passive"))
      (node (ref "IC20") (pin "15") (pinfunction "15_15") (pintype "passive"))
      (node (ref "IC21") (pin "15") (pinfunction "15_15") (pintype "passive"))
    )
    (net (code "112") (name "Net-(IC18-Pad16)") (class "Default")
      (node (ref "IC18") (pin "16") (pinfunction "16_16") (pintype "passive"))
      (node (ref "IC19") (pin "16") (pinfunction "16_16") (pintype "passive"))
      (node (ref "IC20") (pin "16") (pinfunction "16_16") (pintype "passive"))
      (node (ref "IC21") (pin "16") (pinfunction "16_16") (pintype "passive"))
    )
    (net (code "113") (name "Net-(IC18-Pad17)") (class "Default")
      (node (ref "IC18") (pin "17") (pinfunction "17_17") (pintype "passive"))
      (node (ref "IC19") (pin "17") (pinfunction "17_17") (pintype "passive"))
      (node (ref "IC20") (pin "17") (pinfunction "17_17") (pintype "passive"))
      (node (ref "IC21") (pin "17") (pinfunction "17_17") (pintype "passive"))
    )
    (net (code "114") (name "Net-(IC18-Pad18)") (class "Default")
      (node (ref "IC18") (pin "18") (pinfunction "18_18") (pintype "passive"))
      (node (ref "IC19") (pin "18") (pinfunction "18_18") (pintype "passive"))
      (node (ref "IC20") (pin "18") (pinfunction "18_18") (pintype "passive"))
      (node (ref "IC21") (pin "18") (pinfunction "18_18") (pintype "passive"))
    )
    (net (code "115") (name "Net-(IC18-Pad19)") (class "Default")
      (node (ref "IC18") (pin "19") (pinfunction "19_19") (pintype "passive"))
      (node (ref "IC19") (pin "19") (pinfunction "19_19") (pintype "passive"))
      (node (ref "IC20") (pin "19") (pinfunction "19_19") (pintype "passive"))
      (node (ref "IC21") (pin "19") (pinfunction "19_19") (pintype "passive"))
    )
    (net (code "116") (name "Net-(IC18-Pad20)") (class "Default")
      (node (ref "IC18") (pin "20") (pinfunction "20_20") (pintype "passive"))
      (node (ref "IC19") (pin "20") (pinfunction "20_20") (pintype "passive"))
      (node (ref "IC20") (pin "20") (pinfunction "20_20") (pintype "passive"))
      (node (ref "IC21") (pin "20") (pinfunction "20_20") (pintype "passive"))
    )
    (net (code "117") (name "Net-(IC18-Pad21)") (class "Default")
      (node (ref "IC18") (pin "21") (pinfunction "21_21") (pintype "passive"))
      (node (ref "IC19") (pin "21") (pinfunction "21_21") (pintype "passive"))
      (node (ref "IC20") (pin "21") (pinfunction "21_21") (pintype "passive"))
      (node (ref "IC21") (pin "21") (pinfunction "21_21") (pintype "passive"))
    )
    (net (code "118") (name "Net-(IC18-Pad22)") (class "Default")
      (node (ref "IC18") (pin "22") (pinfunction "22_22") (pintype "passive"))
      (node (ref "IC19") (pin "22") (pinfunction "22_22") (pintype "passive"))
      (node (ref "IC20") (pin "22") (pinfunction "22_22") (pintype "passive"))
      (node (ref "IC21") (pin "22") (pinfunction "22_22") (pintype "passive"))
    )
    (net (code "119") (name "Net-(IC18-Pad23)") (class "Default")
      (node (ref "IC18") (pin "23") (pinfunction "23_23") (pintype "passive"))
      (node (ref "IC19") (pin "23") (pinfunction "23_23") (pintype "passive"))
      (node (ref "IC20") (pin "23") (pinfunction "23_23") (pintype "passive"))
      (node (ref "IC21") (pin "23") (pinfunction "23_23") (pintype "passive"))
    )
    (net (code "120") (name "Net-(IC18-Pad24)") (class "Default")
      (node (ref "IC18") (pin "24") (pinfunction "24_24") (pintype "passive"))
      (node (ref "IC19") (pin "24") (pinfunction "24_24") (pintype "passive"))
      (node (ref "IC20") (pin "24") (pinfunction "24_24") (pintype "passive"))
      (node (ref "IC21") (pin "24") (pinfunction "24_24") (pintype "passive"))
    )
    (net (code "121") (name "Net-(IC22-Pad1)") (class "Default")
      (node (ref "IC22") (pin "1") (pinfunction "1_1") (pintype "passive"))
      (node (ref "IC23") (pin "1") (pinfunction "1_1") (pintype "passive"))
      (node (ref "IC24") (pin "1") (pinfunction "1_1") (pintype "passive"))
      (node (ref "IC25") (pin "1") (pinfunction "1_1") (pintype "passive"))
    )
    (net (code "122") (name "Net-(IC22-Pad2)") (class "Default")
      (node (ref "IC22") (pin "2") (pinfunction "2_2") (pintype "passive"))
      (node (ref "IC23") (pin "2") (pinfunction "2_2") (pintype "passive"))
      (node (ref "IC24") (pin "2") (pinfunction "2_2") (pintype "passive"))
      (node (ref "IC25") (pin "2") (pinfunction "2_2") (pintype "passive"))
    )
    (net (code "123") (name "Net-(IC22-Pad3)") (class "Default")
      (node (ref "IC22") (pin "3") (pinfunction "3_3") (pintype "passive"))
      (node (ref "IC23") (pin "3") (pinfunction "3_3") (pintype "passive"))
      (node (ref "IC24") (pin "3") (pinfunction "3_3") (pintype "passive"))
      (node (ref "IC25") (pin "3") (pinfunction "3_3") (pintype "passive"))
    )
    (net (code "124") (name "Net-(IC22-Pad4)") (class "Default")
      (node (ref "IC22") (pin "4") (pinfunction "4_4") (pintype "passive"))
      (node (ref "IC23") (pin "4") (pinfunction "4_4") (pintype "passive"))
      (node (ref "IC24") (pin "4") (pinfunction "4_4") (pintype "passive"))
      (node (ref "IC25") (pin "4") (pinfunction "4_4") (pintype "passive"))
    )
    (net (code "125") (name "Net-(IC22-Pad5)") (class "Default")
      (node (ref "IC22") (pin "5") (pinfunction "5_5") (pintype "passive"))
      (node (ref "IC23") (pin "5") (pinfunction "5_5") (pintype "passive"))
      (node (ref "IC24") (pin "5") (pinfunction "5_5") (pintype "passive"))
      (node (ref "IC25") (pin "5") (pinfunction "5_5") (pintype "passive"))
    )
    (net (code "126") (name "Net-(IC22-Pad6)") (class "Default")
      (node (ref "IC22") (pin "6") (pinfunction "6_6") (pintype "passive"))
      (node (ref "IC23") (pin "6") (pinfunction "6_6") (pintype "passive"))
      (node (ref "IC24") (pin "6") (pinfunction "6_6") (pintype "passive"))
      (node (ref "IC25") (pin "6") (pinfunction "6_6") (pintype "passive"))
    )
    (net (code "127") (name "Net-(IC22-Pad7)") (class "Default")
      (node (ref "IC22") (pin "7") (pinfunction "7_7") (pintype "passive"))
      (node (ref "IC23") (pin "7") (pinfunction "7_7") (pintype "passive"))
      (node (ref "IC24") (pin "7") (pinfunction "7_7") (pintype "passive"))
      (node (ref "IC25") (pin "7") (pinfunction "7_7") (pintype "passive"))
    )
    (net (code "128") (name "Net-(IC22-Pad8)") (class "Default")
      (node (ref "IC22") (pin "8") (pinfunction "8_8") (pintype "passive"))
      (node (ref "IC23") (pin "8") (pinfunction "8_8") (pintype "passive"))
      (node (ref "IC24") (pin "8") (pinfunction "8_8") (pintype "passive"))
      (node (ref "IC25") (pin "8") (pinfunction "8_8") (pintype "passive"))
    )
    (net (code "129") (name "Net-(IC22-Pad9)") (class "Default")
      (node (ref "IC22") (pin "9") (pinfunction "9_9") (pintype "passive"))
      (node (ref "IC23") (pin "9") (pinfunction "9_9") (pintype "passive"))
      (node (ref "IC24") (pin "9") (pinfunction "9_9") (pintype "passive"))
      (node (ref "IC25") (pin "9") (pinfunction "9_9") (pintype "passive"))
    )
    (net (code "130") (name "Net-(IC22-Pad10)") (class "Default")
      (node (ref "IC22") (pin "10") (pinfunction "10_10") (pintype "passive"))
      (node (ref "IC23") (pin "10") (pinfunction "10_10") (pintype "passive"))
      (node (ref "IC24") (pin "10") (pinfunction "10_10") (pintype "passive"))
      (node (ref "IC25") (pin "10") (pinfunction "10_10") (pintype "passive"))
    )
    (net (code "131") (name "Net-(IC22-Pad11)") (class "Default")
      (node (ref "IC22") (pin "11") (pinfunction "11_11") (pintype "passive"))
      (node (ref "IC23") (pin "11") (pinfunction "11_11") (pintype "passive"))
      (node (ref "IC24") (pin "11") (pinfunction "11_11") (pintype "passive"))
      (node (ref "IC25") (pin "11") (pinfunction "11_11") (pintype "passive"))
    )
    (net (code "132") (name "Net-(IC22-Pad12)") (class "Default")
      (node (ref "IC22") (pin "12") (pinfunction "12_12") (pintype "passive"))
      (node (ref "IC23") (pin "12") (pinfunction "12_12") (pintype "passive"))
      (node (ref "IC24") (pin "12") (pinfunction "12_12") (pintype "passive"))
      (node (ref "IC25") (pin "12") (pinfunction "12_12") (pintype "passive"))
    )
    (net (code "133") (name "Net-(IC22-Pad13)") (class "Default")
      (node (ref "IC22") (pin "13") (pinfunction "13_13") (pintype "passive"))
      (node (ref "IC23") (pin "13") (pinfunction "13_13") (pintype "passive"))
      (node (ref "IC24") (pin "13") (pinfunction "13_13") (pintype "passive"))
      (node (ref "IC25") (pin "13") (pinfunction "13_13") (pintype "passive"))
    )
    (net (code "134") (name "Net-(IC22-Pad14)") (class "Default")
      (node (ref "IC22") (pin "14") (pinfunction "14_14") (pintype "passive"))
      (node (ref "IC23") (pin "14") (pinfunction "14_14") (pintype "passive"))
      (node (ref "IC24") (pin "14") (pinfunction "14_14") (pintype "passive"))
      (node (ref "IC25") (pin "14") (pinfunction "14_14") (pintype "passive"))
    )
    (net (code "135") (name "Net-(IC22-Pad15)") (class "Default")
      (node (ref "IC22") (pin "15") (pinfunction "15_15") (pintype "passive"))
      (node (ref "IC23") (pin "15") (pinfunction "15_15") (pintype "passive"))
      (node (ref "IC24") (pin "15") (pinfunction "15_15") (pintype "passive"))
      (node (ref "IC25") (pin "15") (pinfunction "15_15") (pintype "passive"))
    )
    (net (code "136") (name "Net-(IC22-Pad16)") (class "Default")
      (node (ref "IC22") (pin "16") (pinfunction "16_16") (pintype "passive"))
      (node (ref "IC23") (pin "16") (pinfunction "16_16") (pintype "passive"))
      (node (ref "IC24") (pin "16") (pinfunction "16_16") (pintype "passive"))
      (node (ref "IC25") (pin "16") (pinfunction "16_16") (pintype "passive"))
    )
    (net (code "137") (name "Net-(IC22-Pad17)") (class "Default")
      (node (ref "IC22") (pin "17") (pinfunction "17_17") (pintype "passive"))
      (node (ref "IC23") (pin "17") (pinfunction "17_17") (pintype "passive"))
      (node (ref "IC24") (pin "17") (pinfunction "17_17") (pintype "passive"))
      (node (ref "IC25") (pin "17") (pinfunction "17_17") (pintype "passive"))
    )
    (net (code "138") (name "Net-(IC22-Pad18)") (class "Default")
      (node (ref "IC22") (pin "18") (pinfunction "18_18") (pintype "passive"))
      (node (ref "IC23") (pin "18") (pinfunction "18_18") (pintype "passive"))
      (node (ref "IC24") (pin "18") (pinfunction "18_18") (pintype "passive"))
      (node (ref "IC25") (pin "18") (pinfunction "18_18") (pintype "passive"))
    )
    (net (code "139") (name "Net-(IC22-Pad19)") (class "Default")
      (node (ref "IC22") (pin "19") (pinfunction "19_19") (pintype "passive"))
      (node (ref "IC23") (pin "19") (pinfunction "19_19") (pintype "passive"))
      (node (ref "IC24") (pin "19") (pinfunction "19_19") (pintype "passive"))
      (node (ref "IC25") (pin "19") (pinfunction "19_19") (pintype "passive"))
    )
    (net (code "140") (name "Net-(IC22-Pad20)") (class "Default")
      (node (ref "IC22") (pin "20") (pinfunction "20_20") (pintype "passive"))
      (node (ref "IC23") (pin "20") (pinfunction "20_20") (pintype "passive"))
      (node (ref "IC24") (pin "20") (pinfunction "20_20") (pintype "passive"))
      (node (ref "IC25") (pin "20") (pinfunction "20_20") (pintype "passive"))
    )
    (net (code "141") (name "Net-(IC22-Pad21)") (class "Default")
      (node (ref "IC22") (pin "21") (pinfunction "21_21") (pintype "passive"))
      (node (ref "IC23") (pin "21") (pinfunction "21_21") (pintype "passive"))
      (node (ref "IC24") (pin "21") (pinfunction "21_21") (pintype "passive"))
      (node (ref "IC25") (pin "21") (pinfunction "21_21") (pintype "passive"))
    )
    (net (code "142") (name "Net-(IC22-Pad22)") (class "Default")
      (node (ref "IC22") (pin "22") (pinfunction "22_22") (pintype "passive"))
      (node (ref "IC23") (pin "22") (pinfunction "22_22") (pintype "passive"))
      (node (ref "IC24") (pin "22") (pinfunction "22_22") (pintype "passive"))
      (node (ref "IC25") (pin "22") (pinfunction "22_22") (pintype "passive"))
    )
    (net (code "143") (name "Net-(IC22-Pad23)") (class "Default")
      (node (ref "IC22") (pin "23") (pinfunction "23_23") (pintype "passive"))
      (node (ref "IC23") (pin "23") (pinfunction "23_23") (pintype "passive"))
      (node (ref "IC24") (pin "23") (pinfunction "23_23") (pintype "passive"))
      (node (ref "IC25") (pin "23") (pinfunction "23_23") (pintype "passive"))
    )
    (net (code "144") (name "Net-(IC22-Pad24)") (class "Default")
      (node (ref "IC22") (pin "24") (pinfunction "24_24") (pintype "passive"))
      (node (ref "IC23") (pin "24") (pinfunction "24_24") (pintype "passive"))
      (node (ref "IC24") (pin "24") (pinfunction "24_24") (pintype "passive"))
      (node (ref "IC25") (pin "24") (pinfunction "24_24") (pintype "passive"))
    )
    (net (code "145") (name "Net-(IC26-Pad1)") (class "Default")
      (node (ref "IC26") (pin "1") (pinfunction "1_1") (pintype "passive"))
      (node (ref "IC27") (pin "1") (pinfunction "1_1") (pintype "passive"))
      (node (ref "IC28") (pin "1") (pinfunction "1_1") (pintype "passive"))
      (node (ref "IC29") (pin "1") (pinfunction "1_1") (pintype "passive"))
    )
    (net (code "146") (name "Net-(IC26-Pad2)") (class "Default")
      (node (ref "IC26") (pin "2") (pinfunction "2_2") (pintype "passive"))
      (node (ref "IC27") (pin "2") (pinfunction "2_2") (pintype "passive"))
      (node (ref "IC28") (pin "2") (pinfunction "2_2") (pintype "passive"))
      (node (ref "IC29") (pin "2") (pinfunction "2_2") (pintype "passive"))
    )
    (net (code "147") (name "Net-(IC26-Pad3)") (class "Default")
      (node (ref "IC26") (pin "3") (pinfunction "3_3") (pintype "passive"))
      (node (ref "IC27") (pin "3") (pinfunction "3_3") (pintype "passive"))
      (node (ref "IC28") (pin "3") (pinfunction "3_3") (pintype "passive"))
      (node (ref "IC29") (pin "3") (pinfunction "3_3") (pintype "passive"))
    )
    (net (code "148") (name "Net-(IC26-Pad4)") (class "Default")
      (node (ref "IC26") (pin "4") (pinfunction "4_4") (pintype "passive"))
      (node (ref "IC27") (pin "4") (pinfunction "4_4") (pintype "passive"))
      (node (ref "IC28") (pin "4") (pinfunction "4_4") (pintype "passive"))
      (node (ref "IC29") (pin "4") (pinfunction "4_4") (pintype "passive"))
    )
    (net (code "149") (name "Net-(IC26-Pad5)") (class "Default")
      (node (ref "IC26") (pin "5") (pinfunction "5_5") (pintype "passive"))
      (node (ref "IC27") (pin "5") (pinfunction "5_5") (pintype "passive"))
      (node (ref "IC28") (pin "5") (pinfunction "5_5") (pintype "passive"))
      (node (ref "IC29") (pin "5") (pinfunction "5_5") (pintype "passive"))
    )
    (net (code "150") (name "Net-(IC26-Pad6)") (class "Default")
      (node (ref "IC26") (pin "6") (pinfunction "6_6") (pintype "passive"))
      (node (ref "IC27") (pin "6") (pinfunction "6_6") (pintype "passive"))
      (node (ref "IC28") (pin "6") (pinfunction "6_6") (pintype "passive"))
      (node (ref "IC29") (pin "6") (pinfunction "6_6") (pintype "passive"))
    )
    (net (code "151") (name "Net-(IC26-Pad7)") (class "Default")
      (node (ref "IC26") (pin "7") (pinfunction "7_7") (pintype "passive"))
      (node (ref "IC27") (pin "7") (pinfunction "7_7") (pintype "passive"))
      (node (ref "IC28") (pin "7") (pinfunction "7_7") (pintype "passive"))
      (node (ref "IC29") (pin "7") (pinfunction "7_7") (pintype "passive"))
    )
    (net (code "152") (name "Net-(IC26-Pad8)") (class "Default")
      (node (ref "IC26") (pin "8") (pinfunction "8_8") (pintype "passive"))
      (node (ref "IC27") (pin "8") (pinfunction "8_8") (pintype "passive"))
      (node (ref "IC28") (pin "8") (pinfunction "8_8") (pintype "passive"))
      (node (ref "IC29") (pin "8") (pinfunction "8_8") (pintype "passive"))
    )
    (net (code "153") (name "Net-(IC26-Pad9)") (class "Default")
      (node (ref "IC26") (pin "9") (pinfunction "9_9") (pintype "passive"))
      (node (ref "IC27") (pin "9") (pinfunction "9_9") (pintype "passive"))
      (node (ref "IC28") (pin "9") (pinfunction "9_9") (pintype "passive"))
      (node (ref "IC29") (pin "9") (pinfunction "9_9") (pintype "passive"))
    )
    (net (code "154") (name "Net-(IC26-Pad10)") (class "Default")
      (node (ref "IC26") (pin "10") (pinfunction "10_10") (pintype "passive"))
      (node (ref "IC27") (pin "10") (pinfunction "10_10") (pintype "passive"))
      (node (ref "IC28") (pin "10") (pinfunction "10_10") (pintype "passive"))
      (node (ref "IC29") (pin "10") (pinfunction "10_10") (pintype "passive"))
    )
    (net (code "155") (name "Net-(IC26-Pad11)") (class "Default")
      (node (ref "IC26") (pin "11") (pinfunction "11_11") (pintype "passive"))
      (node (ref "IC27") (pin "11") (pinfunction "11_11") (pintype "passive"))
      (node (ref "IC28") (pin "11") (pinfunction "11_11") (pintype "passive"))
      (node (ref "IC29") (pin "11") (pinfunction "11_11") (pintype "passive"))
    )
    (net (code "156") (name "Net-(IC26-Pad12)") (class "Default")
      (node (ref "IC26") (pin "12") (pinfunction "12_12") (pintype "passive"))
      (node (ref "IC27") (pin "12") (pinfunction "12_12") (pintype "passive"))
      (node (ref "IC28") (pin "12") (pinfunction "12_12") (pintype "passive"))
      (node (ref "IC29") (pin "12") (pinfunction "12_12") (pintype "passive"))
    )
    (net (code "157") (name "Net-(IC26-Pad13)") (class "Default")
      (node (ref "IC26") (pin "13") (pinfunction "13_13") (pintype "passive"))
      (node (ref "IC27") (pin "13") (pinfunction "13_13") (pintype "passive"))
      (node (ref "IC28") (pin "13") (pinfunction "13_13") (pintype "passive"))
      (node (ref "IC29") (pin "13") (pinfunction "13_13") (pintype "passive"))
    )
    (net (code "158") (name "Net-(IC26-Pad14)") (class "Default")
      (node (ref "IC26") (pin "14") (pinfunction "14_14") (pintype "passive"))
      (node (ref "IC27") (pin "14") (pinfunction "14_14") (pintype "passive"))
      (node (ref "IC28") (pin "14") (pinfunction "14_14") (pintype "passive"))
      (node (ref "IC29") (pin "14") (pinfunction "14_14") (pintype "passive"))
    )
    (net (code "159") (name "Net-(IC26-Pad15)") (class "Default")
      (node (ref "IC26") (pin "15") (pinfunction "15_15") (pintype "passive"))
      (node (ref "IC27") (pin "15") (pinfunction "15_15") (pintype "passive"))
      (node (ref "IC28") (pin "15") (pinfunction "15_15") (pintype "passive"))
      (node (ref "IC29") (pin "15") (pinfunction "15_15") (pintype "passive"))
    )
    (net (code "160") (name "Net-(IC26-Pad16)") (class "Default")
      (node (ref "IC26") (pin "16") (pinfunction "16_16") (pintype "passive"))
      (node (ref "IC27") (pin "16") (pinfunction "16_16") (pintype "passive"))
      (node (ref "IC28") (pin "16") (pinfunction "16_16") (pintype "passive"))
      (node (ref "IC29") (pin "16") (pinfunction "16_16") (pintype "passive"))
    )
    (net (code "161") (name "Net-(IC26-Pad17)") (class "Default")
      (node (ref "IC26") (pin "17") (pinfunction "17_17") (pintype "passive"))
      (node (ref "IC27") (pin "17") (pinfunction "17_17") (pintype "passive"))
      (node (ref "IC28") (pin "17") (pinfunction "17_17") (pintype "passive"))
      (node (ref "IC29") (pin "17") (pinfunction "17_17") (pintype "passive"))
    )
    (net (code "162") (name "Net-(IC26-Pad18)") (class "Default")
      (node (ref "IC26") (pin "18") (pinfunction "18_18") (pintype "passive"))
      (node (ref "IC27") (pin "18") (pinfunction "18_18") (pintype "passive"))
      (node (ref "IC28") (pin "18") (pinfunction "18_18") (pintype "passive"))
      (node (ref "IC29") (pin "18") (pinfunction "18_18") (pintype "passive"))
    )
    (net (code "163") (name "Net-(IC26-Pad19)") (class "Default")
      (node (ref "IC26") (pin "19") (pinfunction "19_19") (pintype "passive"))
      (node (ref "IC27") (pin "19") (pinfunction "19_19") (pintype "passive"))
      (node (ref "IC28") (pin "19") (pinfunction "19_19") (pintype "passive"))
      (node (ref "IC29") (pin "19") (pinfunction "19_19") (pintype "passive"))
    )
    (net (code "164") (name "Net-(IC26-Pad20)") (class "Default")
      (node (ref "IC26") (pin "20") (pinfunction "20_20") (pintype "passive"))
      (node (ref "IC27") (pin "20") (pinfunction "20_20") (pintype "passive"))
      (node (ref "IC28") (pin "20") (pinfunction "20_20") (pintype "passive"))
      (node (ref "IC29") (pin "20") (pinfunction "20_20") (pintype "passive"))
    )
    (net (code "165") (name "Net-(IC26-Pad21)") (class "Default")
      (node (ref "IC26") (pin "21") (pinfunction "21_21") (pintype "passive"))
      (node (ref "IC27") (pin "21") (pinfunction "21_21") (pintype "passive"))
      (node (ref "IC28") (pin "21") (pinfunction "21_21") (pintype "passive"))
      (node (ref "IC29") (pin "21") (pinfunction "21_21") (pintype "passive"))
    )
    (net (code "166") (name "Net-(IC26-Pad22)") (class "Default")
      (node (ref "IC26") (pin "22") (pinfunction "22_22") (pintype "passive"))
      (node (ref "IC27") (pin "22") (pinfunction "22_22") (pintype "passive"))
      (node (ref "IC28") (pin "22") (pinfunction "22_22") (pintype "passive"))
      (node (ref "IC29") (pin "22") (pinfunction "22_22") (pintype "passive"))
    )
    (net (code "167") (name "Net-(IC26-Pad23)") (class "Default")
      (node (ref "IC26") (pin "23") (pinfunction "23_23") (pintype "passive"))
      (node (ref "IC27") (pin "23") (pinfunction "23_23") (pintype "passive"))
      (node (ref "IC28") (pin "23") (pinfunction "23_23") (pintype "passive"))
      (node (ref "IC29") (pin "23") (pinfunction "23_23") (pintype "passive"))
    )
    (net (code "168") (name "Net-(IC26-Pad24)") (class "Default")
      (node (ref "IC26") (pin "24") (pinfunction "24_24") (pintype "passive"))
      (node (ref "IC27") (pin "24") (pinfunction "24_24") (pintype "passive"))
      (node (ref "IC28") (pin "24") (pinfunction "24_24") (pintype "passive"))
      (node (ref "IC29") (pin "24") (pinfunction "24_24") (pintype "passive"))
    )
    (net (code "169") (name "Net-(IC30-Pad1)") (class "Default")
      (node (ref "IC30") (pin "1") (pinfunction "1_1") (pintype "passive"))
      (node (ref "IC31") (pin "1") (pinfunction "1_1") (pintype "passive"))
      (node (ref "IC32") (pin "1") (pinfunction "1_1") (pintype "passive"))
      (node (ref "IC33") (pin "1") (pinfunction "1_1") (pintype "passive"))
    )
    (net (code "170") (name "Net-(IC30-Pad2)") (class "Default")
      (node (ref "IC30") (pin "2") (pinfunction "2_2") (pintype "passive"))
      (node (ref "IC31") (pin "2") (pinfunction "2_2") (pintype "passive"))
      (node (ref "IC32") (pin "2") (pinfunction "2_2") (pintype "passive"))
      (node (ref "IC33") (pin "2") (pinfunction "2_2") (pintype "passive"))
    )
    (net (code "171") (name "Net-(IC30-Pad3)") (class "Default")
      (node (ref "IC30") (pin "3") (pinfunction "3_3") (pintype "passive"))
      (node (ref "IC31") (pin "3") (pinfunction "3_3") (pintype "passive"))
      (node (ref "IC32") (pin "3") (pinfunction "3_3") (pintype "passive"))
      (node (ref "IC33") (pin "3") (pinfunction "3_3") (pintype "passive"))
    )
    (net (code "172") (name "Net-(IC30-Pad4)") (class "Default")
      (node (ref "IC30") (pin "4") (pinfunction "4_4") (pintype "passive"))
      (node (ref "IC31") (pin "4") (pinfunction "4_4") (pintype "passive"))
      (node (ref "IC32") (pin "4") (pinfunction "4_4") (pintype "passive"))
      (node (ref "IC33") (pin "4") (pinfunction "4_4") (pintype "passive"))
    )
    (net (code "173") (name "Net-(IC30-Pad5)") (class "Default")
      (node (ref "IC30") (pin "5") (pinfunction "5_5") (pintype "passive"))
      (node (ref "IC31") (pin "5") (pinfunction "5_5") (pintype "passive"))
      (node (ref "IC32") (pin "5") (pinfunction "5_5") (pintype "passive"))
      (node (ref "IC33") (pin "5") (pinfunction "5_5") (pintype "passive"))
    )
    (net (code "174") (name "Net-(IC30-Pad6)") (class "Default")
      (node (ref "IC30") (pin "6") (pinfunction "6_6") (pintype "passive"))
      (node (ref "IC31") (pin "6") (pinfunction "6_6") (pintype "passive"))
      (node (ref "IC32") (pin "6") (pinfunction "6_6") (pintype "passive"))
      (node (ref "IC33") (pin "6") (pinfunction "6_6") (pintype "passive"))
    )
    (net (code "175") (name "Net-(IC30-Pad7)") (class "Default")
      (node (ref "IC30") (pin "7") (pinfunction "7_7") (pintype "passive"))
      (node (ref "IC31") (pin "7") (pinfunction "7_7") (pintype "passive"))
      (node (ref "IC32") (pin "7") (pinfunction "7_7") (pintype "passive"))
      (node (ref "IC33") (pin "7") (pinfunction "7_7") (pintype "passive"))
    )
    (net (code "176") (name "Net-(IC30-Pad8)") (class "Default")
      (node (ref "IC30") (pin "8") (pinfunction "8_8") (pintype "passive"))
      (node (ref "IC31") (pin "8") (pinfunction "8_8") (pintype "passive"))
      (node (ref "IC32") (pin "8") (pinfunction "8_8") (pintype "passive"))
      (node (ref "IC33") (pin "8") (pinfunction "8_8") (pintype "passive"))
    )
    (net (code "177") (name "Net-(IC30-Pad9)") (class "Default")
      (node (ref "IC30") (pin "9") (pinfunction "9_9") (pintype "passive"))
      (node (ref "IC31") (pin "9") (pinfunction "9_9") (pintype "passive"))
      (node (ref "IC32") (pin "9") (pinfunction "9_9") (pintype "passive"))
      (node (ref "IC33") (pin "9") (pinfunction "9_9") (pintype "passive"))
    )
    (net (code "178") (name "Net-(IC30-Pad10)") (class "Default")
      (node (ref "IC30") (pin "10") (pinfunction "10_10") (pintype "passive"))
      (node (ref "IC31") (pin "10") (pinfunction "10_10") (pintype "passive"))
      (node (ref "IC32") (pin "10") (pinfunction "10_10") (pintype "passive"))
      (node (ref "IC33") (pin "10") (pinfunction "10_10") (pintype "passive"))
    )
    (net (code "179") (name "Net-(IC30-Pad11)") (class "Default")
      (node (ref "IC30") (pin "11") (pinfunction "11_11") (pintype "passive"))
      (node (ref "IC31") (pin "11") (pinfunction "11_11") (pintype "passive"))
      (node (ref "IC32") (pin "11") (pinfunction "11_11") (pintype "passive"))
      (node (ref "IC33") (pin "11") (pinfunction "11_11") (pintype "passive"))
    )
    (net (code "180") (name "Net-(IC30-Pad12)") (class "Default")
      (node (ref "IC30") (pin "12") (pinfunction "12_12") (pintype "passive"))
      (node (ref "IC31") (pin "12") (pinfunction "12_12") (pintype "passive"))
      (node (ref "IC32") (pin "12") (pinfunction "12_12") (pintype "passive"))
      (node (ref "IC33") (pin "12") (pinfunction "12_12") (pintype "passive"))
    )
    (net (code "181") (name "Net-(IC30-Pad13)") (class "Default")
      (node (ref "IC30") (pin "13") (pinfunction "13_13") (pintype "passive"))
      (node (ref "IC31") (pin "13") (pinfunction "13_13") (pintype "passive"))
      (node (ref "IC32") (pin "13") (pinfunction "13_13") (pintype "passive"))
      (node (ref "IC33") (pin "13") (pinfunction "13_13") (pintype "passive"))
    )
    (net (code "182") (name "Net-(IC30-Pad14)") (class "Default")
      (node (ref "IC30") (pin "14") (pinfunction "14_14") (pintype "passive"))
      (node (ref "IC31") (pin "14") (pinfunction "14_14") (pintype "passive"))
      (node (ref "IC32") (pin "14") (pinfunction "14_14") (pintype "passive"))
      (node (ref "IC33") (pin "14") (pinfunction "14_14") (pintype "passive"))
    )
    (net (code "183") (name "Net-(IC30-Pad15)") (class "Default")
      (node (ref "IC30") (pin "15") (pinfunction "15_15") (pintype "passive"))
      (node (ref "IC31") (pin "15") (pinfunction "15_15") (pintype "passive"))
      (node (ref "IC32") (pin "15") (pinfunction "15_15") (pintype "passive"))
      (node (ref "IC33") (pin "15") (pinfunction "15_15") (pintype "passive"))
    )
    (net (code "184") (name "Net-(IC30-Pad16)") (class "Default")
      (node (ref "IC30") (pin "16") (pinfunction "16_16") (pintype "passive"))
      (node (ref "IC31") (pin "16") (pinfunction "16_16") (pintype "passive"))
      (node (ref "IC32") (pin "16") (pinfunction "16_16") (pintype "passive"))
      (node (ref "IC33") (pin "16") (pinfunction "16_16") (pintype "passive"))
    )
    (net (code "185") (name "Net-(IC30-Pad17)") (class "Default")
      (node (ref "IC30") (pin "17") (pinfunction "17_17") (pintype "passive"))
      (node (ref "IC31") (pin "17") (pinfunction "17_17") (pintype "passive"))
      (node (ref "IC32") (pin "17") (pinfunction "17_17") (pintype "passive"))
      (node (ref "IC33") (pin "17") (pinfunction "17_17") (pintype "passive"))
    )
    (net (code "186") (name "Net-(IC30-Pad18)") (class "Default")
      (node (ref "IC30") (pin "18") (pinfunction "18_18") (pintype "passive"))
      (node (ref "IC31") (pin "18") (pinfunction "18_18") (pintype "passive"))
      (node (ref "IC32") (pin "18") (pinfunction "18_18") (pintype "passive"))
      (node (ref "IC33") (pin "18") (pinfunction "18_18") (pintype "passive"))
    )
    (net (code "187") (name "Net-(IC30-Pad19)") (class "Default")
      (node (ref "IC30") (pin "19") (pinfunction "19_19") (pintype "passive"))
      (node (ref "IC31") (pin "19") (pinfunction "19_19") (pintype "passive"))
      (node (ref "IC32") (pin "19") (pinfunction "19_19") (pintype "passive"))
      (node (ref "IC33") (pin "19") (pinfunction "19_19") (pintype "passive"))
    )
    (net (code "188") (name "Net-(IC30-Pad20)") (class "Default")
      (node (ref "IC30") (pin "20") (pinfunction "20_20") (pintype "passive"))
      (node (ref "IC31") (pin "20") (pinfunction "20_20") (pintype "passive"))
      (node (ref "IC32") (pin "20") (pinfunction "20_20") (pintype "passive"))
      (node (ref "IC33") (pin "20") (pinfunction "20_20") (pintype "passive"))
    )
    (net (code "189") (name "Net-(IC30-Pad21)") (class "Default")
      (node (ref "IC30") (pin "21") (pinfunction "21_21") (pintype "passive"))
      (node (ref "IC31") (pin "21") (pinfunction "21_21") (pintype "passive"))
      (node (ref "IC32") (pin "21") (pinfunction "21_21") (pintype "passive"))
      (node (ref "IC33") (pin "21") (pinfunction "21_21") (pintype "passive"))
    )
    (net (code "190") (name "Net-(IC30-Pad22)") (class "Default")
      (node (ref "IC30") (pin "22") (pinfunction "22_22") (pintype "passive"))
      (node (ref "IC31") (pin "22") (pinfunction "22_22") (pintype "passive"))
      (node (ref "IC32") (pin "22") (pinfunction "22_22") (pintype "passive"))
      (node (ref "IC33") (pin "22") (pinfunction "22_22") (pintype "passive"))
    )
    (net (code "191") (name "Net-(IC30-Pad23)") (class "Default")
      (node (ref "IC30") (pin "23") (pinfunction "23_23") (pintype "passive"))
      (node (ref "IC31") (pin "23") (pinfunction "23_23") (pintype "passive"))
      (node (ref "IC32") (pin "23") (pinfunction "23_23") (pintype "passive"))
      (node (ref "IC33") (pin "23") (pinfunction "23_23") (pintype "passive"))
    )
    (net (code "192") (name "Net-(IC30-Pad24)") (class "Default")
      (node (ref "IC30") (pin "24") (pinfunction "24_24") (pintype "passive"))
      (node (ref "IC31") (pin "24") (pinfunction "24_24") (pintype "passive"))
      (node (ref "IC32") (pin "24") (pinfunction "24_24") (pintype "passive"))
      (node (ref "IC33") (pin "24") (pinfunction "24_24") (pintype "passive"))
    )
    (net (code "193") (name "Net-(IC34-Pad1)") (class "Default")
      (node (ref "IC34") (pin "1") (pinfunction "1_1") (pintype "passive"))
      (node (ref "IC35") (pin "1") (pinfunction "1_1") (pintype "passive"))
      (node (ref "IC36") (pin "1") (pinfunction "1_1") (pintype "passive"))
      (node (ref "IC37") (pin "1") (pinfunction "1_1") (pintype "passive"))
    )
    (net (code "194") (name "Net-(IC34-Pad2)") (class "Default")
      (node (ref "IC34") (pin "2") (pinfunction "2_2") (pintype "passive"))
      (node (ref "IC35") (pin "2") (pinfunction "2_2") (pintype "passive"))
      (node (ref "IC36") (pin "2") (pinfunction "2_2") (pintype "passive"))
      (node (ref "IC37") (pin "2") (pinfunction "2_2") (pintype "passive"))
    )
    (net (code "195") (name "Net-(IC34-Pad3)") (class "Default")
      (node (ref "IC34") (pin "3") (pinfunction "3_3") (pintype "passive"))
      (node (ref "IC35") (pin "3") (pinfunction "3_3") (pintype "passive"))
      (node (ref "IC36") (pin "3") (pinfunction "3_3") (pintype "passive"))
      (node (ref "IC37") (pin "3") (pinfunction "3_3") (pintype "passive"))
    )
    (net (code "196") (name "Net-(IC34-Pad4)") (class "Default")
      (node (ref "IC34") (pin "4") (pinfunction "4_4") (pintype "passive"))
      (node (ref "IC35") (pin "4") (pinfunction "4_4") (pintype "passive"))
      (node (ref "IC36") (pin "4") (pinfunction "4_4") (pintype "passive"))
      (node (ref "IC37") (pin "4") (pinfunction "4_4") (pintype "passive"))
    )
    (net (code "197") (name "Net-(IC34-Pad5)") (class "Default")
      (node (ref "IC34") (pin "5") (pinfunction "5_5") (pintype "passive"))
      (node (ref "IC35") (pin "5") (pinfunction "5_5") (pintype "passive"))
      (node (ref "IC36") (pin "5") (pinfunction "5_5") (pintype "passive"))
      (node (ref "IC37") (pin "5") (pinfunction "5_5") (pintype "passive"))
    )
    (net (code "198") (name "Net-(IC34-Pad6)") (class "Default")
      (node (ref "IC34") (pin "6") (pinfunction "6_6") (pintype "passive"))
      (node (ref "IC35") (pin "6") (pinfunction "6_6") (pintype "passive"))
      (node (ref "IC36") (pin "6") (pinfunction "6_6") (pintype "passive"))
      (node (ref "IC37") (pin "6") (pinfunction "6_6") (pintype "passive"))
    )
    (net (code "199") (name "Net-(IC34-Pad7)") (class "Default")
      (node (ref "IC34") (pin "7") (pinfunction "7_7") (pintype "passive"))
      (node (ref "IC35") (pin "7") (pinfunction "7_7") (pintype "passive"))
      (node (ref "IC36") (pin "7") (pinfunction "7_7") (pintype "passive"))
      (node (ref "IC37") (pin "7") (pinfunction "7_7") (pintype "passive"))
    )
    (net (code "200") (name "Net-(IC34-Pad8)") (class "Default")
      (node (ref "IC34") (pin "8") (pinfunction "8_8") (pintype "passive"))
      (node (ref "IC35") (pin "8") (pinfunction "8_8") (pintype "passive"))
      (node (ref "IC36") (pin "8") (pinfunction "8_8") (pintype "passive"))
      (node (ref "IC37") (pin "8") (pinfunction "8_8") (pintype "passive"))
    )
    (net (code "201") (name "Net-(IC34-Pad9)") (class "Default")
      (node (ref "IC34") (pin "9") (pinfunction "9_9") (pintype "passive"))
      (node (ref "IC35") (pin "9") (pinfunction "9_9") (pintype "passive"))
      (node (ref "IC36") (pin "9") (pinfunction "9_9") (pintype "passive"))
      (node (ref "IC37") (pin "9") (pinfunction "9_9") (pintype "passive"))
    )
    (net (code "202") (name "Net-(IC34-Pad10)") (class "Default")
      (node (ref "IC34") (pin "10") (pinfunction "10_10") (pintype "passive"))
      (node (ref "IC35") (pin "10") (pinfunction "10_10") (pintype "passive"))
      (node (ref "IC36") (pin "10") (pinfunction "10_10") (pintype "passive"))
      (node (ref "IC37") (pin "10") (pinfunction "10_10") (pintype "passive"))
    )
    (net (code "203") (name "Net-(IC34-Pad11)") (class "Default")
      (node (ref "IC34") (pin "11") (pinfunction "11_11") (pintype "passive"))
      (node (ref "IC35") (pin "11") (pinfunction "11_11") (pintype "passive"))
      (node (ref "IC36") (pin "11") (pinfunction "11_11") (pintype "passive"))
      (node (ref "IC37") (pin "11") (pinfunction "11_11") (pintype "passive"))
    )
    (net (code "204") (name "Net-(IC34-Pad12)") (class "Default")
      (node (ref "IC34") (pin "12") (pinfunction "12_12") (pintype "passive"))
      (node (ref "IC35") (pin "12") (pinfunction "12_12") (pintype "passive"))
      (node (ref "IC36") (pin "12") (pinfunction "12_12") (pintype "passive"))
      (node (ref "IC37") (pin "12") (pinfunction "12_12") (pintype "passive"))
    )
    (net (code "205") (name "Net-(IC34-Pad13)") (class "Default")
      (node (ref "IC34") (pin "13") (pinfunction "13_13") (pintype "passive"))
      (node (ref "IC35") (pin "13") (pinfunction "13_13") (pintype "passive"))
      (node (ref "IC36") (pin "13") (pinfunction "13_13") (pintype "passive"))
      (node (ref "IC37") (pin "13") (pinfunction "13_13") (pintype "passive"))
    )
    (net (code "206") (name "Net-(IC34-Pad14)") (class "Default")
      (node (ref "IC34") (pin "14") (pinfunction "14_14") (pintype "passive"))
      (node (ref "IC35") (pin "14") (pinfunction "14_14") (pintype "passive"))
      (node (ref "IC36") (pin "14") (pinfunction "14_14") (pintype "passive"))
      (node (ref "IC37") (pin "14") (pinfunction "14_14") (pintype "passive"))
    )
    (net (code "207") (name "Net-(IC34-Pad15)") (class "Default")
      (node (ref "IC34") (pin "15") (pinfunction "15_15") (pintype "passive"))
      (node (ref "IC35") (pin "15") (pinfunction "15_15") (pintype "passive"))
      (node (ref "IC36") (pin "15") (pinfunction "15_15") (pintype "passive"))
      (node (ref "IC37") (pin "15") (pinfunction "15_15") (pintype "passive"))
    )
    (net (code "208") (name "Net-(IC34-Pad16)") (class "Default")
      (node (ref "IC34") (pin "16") (pinfunction "16_16") (pintype "passive"))
      (node (ref "IC35") (pin "16") (pinfunction "16_16") (pintype "passive"))
      (node (ref "IC36") (pin "16") (pinfunction "16_16") (pintype "passive"))
      (node (ref "IC37") (pin "16") (pinfunction "16_16") (pintype "passive"))
    )
    (net (code "209") (name "Net-(IC34-Pad17)") (class "Default")
      (node (ref "IC34") (pin "17") (pinfunction "17_17") (pintype "passive"))
      (node (ref "IC35") (pin "17") (pinfunction "17_17") (pintype "passive"))
      (node (ref "IC36") (pin "17") (pinfunction "17_17") (pintype "passive"))
      (node (ref "IC37") (pin "17") (pinfunction "17_17") (pintype "passive"))
    )
    (net (code "210") (name "Net-(IC34-Pad18)") (class "Default")
      (node (ref "IC34") (pin "18") (pinfunction "18_18") (pintype "passive"))
      (node (ref "IC35") (pin "18") (pinfunction "18_18") (pintype "passive"))
      (node (ref "IC36") (pin "18") (pinfunction "18_18") (pintype "passive"))
      (node (ref "IC37") (pin "18") (pinfunction "18_18") (pintype "passive"))
    )
    (net (code "211") (name "Net-(IC34-Pad19)") (class "Default")
      (node (ref "IC34") (pin "19") (pinfunction "19_19") (pintype "passive"))
      (node (ref "IC35") (pin "19") (pinfunction "19_19") (pintype "passive"))
      (node (ref "IC36") (pin "19") (pinfunction "19_19") (pintype "passive"))
      (node (ref "IC37") (pin "19") (pinfunction "19_19") (pintype "passive"))
    )
    (net (code "212") (name "Net-(IC34-Pad20)") (class "Default")
      (node (ref "IC34") (pin "20") (pinfunction "20_20") (pintype "passive"))
      (node (ref "IC35") (pin "20") (pinfunction "20_20") (pintype "passive"))
      (node (ref "IC36") (pin "20") (pinfunction "20_20") (pintype "passive"))
      (node (ref "IC37") (pin "20") (pinfunction "20_20") (pintype "passive"))
    )
    (net (code "213") (name "Net-(IC34-Pad21)") (class "Default")
      (node (ref "IC34") (pin "21") (pinfunction "21_21") (pintype "passive"))
      (node (ref "IC35") (pin "21") (pinfunction "21_21") (pintype "passive"))
      (node (ref "IC36") (pin "21") (pinfunction "21_21") (pintype "passive"))
      (node (ref "IC37") (pin "21") (pinfunction "21_21") (pintype "passive"))
    )
    (net (code "214") (name "Net-(IC34-Pad22)") (class "Default")
      (node (ref "IC34") (pin "22") (pinfunction "22_22") (pintype "passive"))
      (node (ref "IC35") (pin "22") (pinfunction "22_22") (pintype "passive"))
      (node (ref "IC36") (pin "22") (pinfunction "22_22") (pintype "passive"))
      (node (ref "IC37") (pin "22") (pinfunction "22_22") (pintype "passive"))
    )
    (net (code "215") (name "Net-(IC34-Pad23)") (class "Default")
      (node (ref "IC34") (pin "23") (pinfunction "23_23") (pintype "passive"))
      (node (ref "IC35") (pin "23") (pinfunction "23_23") (pintype "passive"))
      (node (ref "IC36") (pin "23") (pinfunction "23_23") (pintype "passive"))
      (node (ref "IC37") (pin "23") (pinfunction "23_23") (pintype "passive"))
    )
    (net (code "216") (name "Net-(IC34-Pad24)") (class "Default")
      (node (ref "IC34") (pin "24") (pinfunction "24_24") (pintype "passive"))
      (node (ref "IC35") (pin "24") (pinfunction "24_24") (pintype "passive"))
      (node (ref "IC36") (pin "24") (pinfunction "24_24") (pintype "passive"))
      (node (ref "IC37") (pin "24") (pinfunction "24_24") (pintype "passive"))
    )
    (net (code "217") (name "Net-(IC38-Pad1)") (class "Default")
      (node (ref "IC38") (pin "1") (pinfunction "1_1") (pintype "passive"))
      (node (ref "IC39") (pin "1") (pinfunction "1_1") (pintype "passive"))
      (node (ref "IC40") (pin "1") (pinfunction "1_1") (pintype "passive"))
      (node (ref "IC41") (pin "1") (pinfunction "1_1") (pintype "passive"))
    )
    (net (code "218") (name "Net-(IC38-Pad2)") (class "Default")
      (node (ref "IC38") (pin "2") (pinfunction "2_2") (pintype "passive"))
      (node (ref "IC39") (pin "2") (pinfunction "2_2") (pintype "passive"))
      (node (ref "IC40") (pin "2") (pinfunction "2_2") (pintype "passive"))
      (node (ref "IC41") (pin "2") (pinfunction "2_2") (pintype "passive"))
    )
    (net (code "219") (name "Net-(IC38-Pad3)") (class "Default")
      (node (ref "IC38") (pin "3") (pinfunction "3_3") (pintype "passive"))
      (node (ref "IC39") (pin "3") (pinfunction "3_3") (pintype "passive"))
      (node (ref "IC40") (pin "3") (pinfunction "3_3") (pintype "passive"))
      (node (ref "IC41") (pin "3") (pinfunction "3_3") (pintype "passive"))
    )
    (net (code "220") (name "Net-(IC38-Pad4)") (class "Default")
      (node (ref "IC38") (pin "4") (pinfunction "4_4") (pintype "passive"))
      (node (ref "IC39") (pin "4") (pinfunction "4_4") (pintype "passive"))
      (node (ref "IC40") (pin "4") (pinfunction "4_4") (pintype "passive"))
      (node (ref "IC41") (pin "4") (pinfunction "4_4") (pintype "passive"))
    )
    (net (code "221") (name "Net-(IC38-Pad5)") (class "Default")
      (node (ref "IC38") (pin "5") (pinfunction "5_5") (pintype "passive"))
      (node (ref "IC39") (pin "5") (pinfunction "5_5") (pintype "passive"))
      (node (ref "IC40") (pin "5") (pinfunction "5_5") (pintype "passive"))
      (node (ref "IC41") (pin "5") (pinfunction "5_5") (pintype "passive"))
    )
    (net (code "222") (name "Net-(IC38-Pad6)") (class "Default")
      (node (ref "IC38") (pin "6") (pinfunction "6_6") (pintype "passive"))
      (node (ref "IC39") (pin "6") (pinfunction "6_6") (pintype "passive"))
      (node (ref "IC40") (pin "6") (pinfunction "6_6") (pintype "passive"))
      (node (ref "IC41") (pin "6") (pinfunction "6_6") (pintype "passive"))
    )
    (net (code "223") (name "Net-(IC38-Pad7)") (class "Default")
      (node (ref "IC38") (pin "7") (pinfunction "7_7") (pintype "passive"))
      (node (ref "IC39") (pin "7") (pinfunction "7_7") (pintype "passive"))
      (node (ref "IC40") (pin "7") (pinfunction "7_7") (pintype "passive"))
      (node (ref "IC41") (pin "7") (pinfunction "7_7") (pintype "passive"))
    )
    (net (code "224") (name "Net-(IC38-Pad8)") (class "Default")
      (node (ref "IC38") (pin "8") (pinfunction "8_8") (pintype "passive"))
      (node (ref "IC39") (pin "8") (pinfunction "8_8") (pintype "passive"))
      (node (ref "IC40") (pin "8") (pinfunction "8_8") (pintype "passive"))
      (node (ref "IC41") (pin "8") (pinfunction "8_8") (pintype "passive"))
    )
    (net (code "225") (name "Net-(IC38-Pad9)") (class "Default")
      (node (ref "IC38") (pin "9") (pinfunction "9_9") (pintype "passive"))
      (node (ref "IC39") (pin "9") (pinfunction "9_9") (pintype "passive"))
      (node (ref "IC40") (pin "9") (pinfunction "9_9") (pintype "passive"))
      (node (ref "IC41") (pin "9") (pinfunction "9_9") (pintype "passive"))
    )
    (net (code "226") (name "Net-(IC38-Pad10)") (class "Default")
      (node (ref "IC38") (pin "10") (pinfunction "10_10") (pintype "passive"))
      (node (ref "IC39") (pin "10") (pinfunction "10_10") (pintype "passive"))
      (node (ref "IC40") (pin "10") (pinfunction "10_10") (pintype "passive"))
      (node (ref "IC41") (pin "10") (pinfunction "10_10") (pintype "passive"))
    )
    (net (code "227") (name "Net-(IC38-Pad11)") (class "Default")
      (node (ref "IC38") (pin "11") (pinfunction "11_11") (pintype "passive"))
      (node (ref "IC39") (pin "11") (pinfunction "11_11") (pintype "passive"))
      (node (ref "IC40") (pin "11") (pinfunction "11_11") (pintype "passive"))
      (node (ref "IC41") (pin "11") (pinfunction "11_11") (pintype "passive"))
    )
    (net (code "228") (name "Net-(IC38-Pad12)") (class "Default")
      (node (ref "IC38") (pin "12") (pinfunction "12_12") (pintype "passive"))
      (node (ref "IC39") (pin "12") (pinfunction "12_12") (pintype "passive"))
      (node (ref "IC40") (pin "12") (pinfunction "12_12") (pintype "passive"))
      (node (ref "IC41") (pin "12") (pinfunction "12_12") (pintype "passive"))
    )
    (net (code "229") (name "Net-(IC38-Pad13)") (class "Default")
      (node (ref "IC38") (pin "13") (pinfunction "13_13") (pintype "passive"))
      (node (ref "IC39") (pin "13") (pinfunction "13_13") (pintype "passive"))
      (node (ref "IC40") (pin "13") (pinfunction "13_13") (pintype "passive"))
      (node (ref "IC41") (pin "13") (pinfunction "13_13") (pintype "passive"))
    )
    (net (code "230") (name "Net-(IC38-Pad14)") (class "Default")
      (node (ref "IC38") (pin "14") (pinfunction "14_14") (pintype "passive"))
      (node (ref "IC39") (pin "14") (pinfunction "14_14") (pintype "passive"))
      (node (ref "IC40") (pin "14") (pinfunction "14_14") (pintype "passive"))
      (node (ref "IC41") (pin "14") (pinfunction "14_14") (pintype "passive"))
    )
    (net (code "231") (name "Net-(IC38-Pad15)") (class "Default")
      (node (ref "IC38") (pin "15") (pinfunction "15_15") (pintype "passive"))
      (node (ref "IC39") (pin "15") (pinfunction "15_15") (pintype "passive"))
      (node (ref "IC40") (pin "15") (pinfunction "15_15") (pintype "passive"))
      (node (ref "IC41") (pin "15") (pinfunction "15_15") (pintype "passive"))
    )
    (net (code "232") (name "Net-(IC38-Pad16)") (class "Default")
      (node (ref "IC38") (pin "16") (pinfunction "16_16") (pintype "passive"))
      (node (ref "IC39") (pin "16") (pinfunction "16_16") (pintype "passive"))
      (node (ref "IC40") (pin "16") (pinfunction "16_16") (pintype "passive"))
      (node (ref "IC41") (pin "16") (pinfunction "16_16") (pintype "passive"))
    )
    (net (code "233") (name "Net-(IC38-Pad17)") (class "Default")
      (node (ref "IC38") (pin "17") (pinfunction "17_17") (pintype "passive"))
      (node (ref "IC39") (pin "17") (pinfunction "17_17") (pintype "passive"))
      (node (ref "IC40") (pin "17") (pinfunction "17_17") (pintype "passive"))
      (node (ref "IC41") (pin "17") (pinfunction "17_17") (pintype "passive"))
    )
    (net (code "234") (name "Net-(IC38-Pad18)") (class "Default")
      (node (ref "IC38") (pin "18") (pinfunction "18_18") (pintype "passive"))
      (node (ref "IC39") (pin "18") (pinfunction "18_18") (pintype "passive"))
      (node (ref "IC40") (pin "18") (pinfunction "18_18") (pintype "passive"))
      (node (ref "IC41") (pin "18") (pinfunction "18_18") (pintype "passive"))
    )
    (net (code "235") (name "Net-(IC38-Pad19)") (class "Default")
      (node (ref "IC38") (pin "19") (pinfunction "19_19") (pintype "passive"))
      (node (ref "IC39") (pin "19") (pinfunction "19_19") (pintype "passive"))
      (node (ref "IC40") (pin "19") (pinfunction "19_19") (pintype "passive"))
      (node (ref "IC41") (pin "19") (pinfunction "19_19") (pintype "passive"))
    )
    (net (code "236") (name "Net-(IC38-Pad20)") (class "Default")
      (node (ref "IC38") (pin "20") (pinfunction "20_20") (pintype "passive"))
      (node (ref "IC39") (pin "20") (pinfunction "20_20") (pintype "passive"))
      (node (ref "IC40") (pin "20") (pinfunction "20_20") (pintype "passive"))
      (node (ref "IC41") (pin "20") (pinfunction "20_20") (pintype "passive"))
    )
    (net (code "237") (name "Net-(IC38-Pad21)") (class "Default")
      (node (ref "IC38") (pin "21") (pinfunction "21_21") (pintype "passive"))
      (node (ref "IC39") (pin "21") (pinfunction "21_21") (pintype "passive"))
      (node (ref "IC40") (pin "21") (pinfunction "21_21") (pintype "passive"))
      (node (ref "IC41") (pin "21") (pinfunction "21_21") (pintype "passive"))
    )
    (net (code "238") (name "Net-(IC38-Pad22)") (class "Default")
      (node (ref "IC38") (pin "22") (pinfunction "22_22") (pintype "passive"))
      (node (ref "IC39") (pin "22") (pinfunction "22_22") (pintype "passive"))
      (node (ref "IC40") (pin "22") (pinfunction "22_22") (pintype "passive"))
      (node (ref "IC41") (pin "22") (pinfunction "22_22") (pintype "passive"))
    )
    (net (code "239") (name "Net-(IC38-Pad23)") (class "Default")
      (node (ref "IC38") (pin "23") (pinfunction "23_23") (pintype "passive"))
      (node (ref "IC39") (pin "23") (pinfunction "23_23") (pintype "passive"))
      (node (ref "IC40") (pin "23") (pinfunction "23_23") (pintype "passive"))
      (node (ref "IC41") (pin "23") (pinfunction "23_23") (pintype "passive"))
    )
    (net (code "240") (name "Net-(IC38-Pad24)") (class "Default")
      (node (ref "IC38") (pin "24") (pinfunction "24_24") (pintype "passive"))
      (node (ref "IC39") (pin "24") (pinfunction "24_24") (pintype "passive"))
      (node (ref "IC40") (pin "24") (pinfunction "24_24") (pintype "passive"))
      (node (ref "IC41") (pin "24") (pinfunction "24_24") (pintype "passive"))
    )
    (net (code "241") (name "Net-(IC42-Pad1)") (class "Default")
      (node (ref "IC42") (pin "1") (pinfunction "1_1") (pintype "passive"))
      (node (ref "IC43") (pin "1") (pinfunction "1_1") (pintype "passive"))
      (node (ref "IC44") (pin "1") (pinfunction "1_1") (pintype "passive"))
      (node (ref "IC45") (pin "1") (pinfunction "1_1") (pintype "passive"))
    )
    (net (code "242") (name "Net-(IC42-Pad2)") (class "Default")
      (node (ref "IC42") (pin "2") (pinfunction "2_2") (pintype "passive"))
      (node (ref "IC43") (pin "2") (pinfunction "2_2") (pintype "passive"))
      (node (ref "IC44") (pin "2") (pinfunction "2_2") (pintype "passive"))
      (node (ref "IC45") (pin "2") (pinfunction "2_2") (pintype "passive"))
    )
    (net (code "243") (name "Net-(IC42-Pad3)") (class "Default")
      (node (ref "IC42") (pin "3") (pinfunction "3_3") (pintype "passive"))
      (node (ref "IC43") (pin "3") (pinfunction "3_3") (pintype "passive"))
      (node (ref "IC44") (pin "3") (pinfunction "3_3") (pintype "passive"))
      (node (ref "IC45") (pin "3") (pinfunction "3_3") (pintype "passive"))
    )
    (net (code "244") (name "Net-(IC42-Pad4)") (class "Default")
      (node (ref "IC42") (pin "4") (pinfunction "4_4") (pintype "passive"))
      (node (ref "IC43") (pin "4") (pinfunction "4_4") (pintype "passive"))
      (node (ref "IC44") (pin "4") (pinfunction "4_4") (pintype "passive"))
      (node (ref "IC45") (pin "4") (pinfunction "4_4") (pintype "passive"))
    )
    (net (code "245") (name "Net-(IC42-Pad5)") (class "Default")
      (node (ref "IC42") (pin "5") (pinfunction "5_5") (pintype "passive"))
      (node (ref "IC43") (pin "5") (pinfunction "5_5") (pintype "passive"))
      (node (ref "IC44") (pin "5") (pinfunction "5_5") (pintype "passive"))
      (node (ref "IC45") (pin "5") (pinfunction "5_5") (pintype "passive"))
    )
    (net (code "246") (name "Net-(IC42-Pad6)") (class "Default")
      (node (ref "IC42") (pin "6") (pinfunction "6_6") (pintype "passive"))
      (node (ref "IC43") (pin "6") (pinfunction "6_6") (pintype "passive"))
      (node (ref "IC44") (pin "6") (pinfunction "6_6") (pintype "passive"))
      (node (ref "IC45") (pin "6") (pinfunction "6_6") (pintype "passive"))
    )
    (net (code "247") (name "Net-(IC42-Pad7)") (class "Default")
      (node (ref "IC42") (pin "7") (pinfunction "7_7") (pintype "passive"))
      (node (ref "IC43") (pin "7") (pinfunction "7_7") (pintype "passive"))
      (node (ref "IC44") (pin "7") (pinfunction "7_7") (pintype "passive"))
      (node (ref "IC45") (pin "7") (pinfunction "7_7") (pintype "passive"))
    )
    (net (code "248") (name "Net-(IC42-Pad8)") (class "Default")
      (node (ref "IC42") (pin "8") (pinfunction "8_8") (pintype "passive"))
      (node (ref "IC43") (pin "8") (pinfunction "8_8") (pintype "passive"))
      (node (ref "IC44") (pin "8") (pinfunction "8_8") (pintype "passive"))
      (node (ref "IC45") (pin "8") (pinfunction "8_8") (pintype "passive"))
    )
    (net (code "249") (name "Net-(IC42-Pad9)") (class "Default")
      (node (ref "IC42") (pin "9") (pinfunction "9_9") (pintype "passive"))
      (node (ref "IC43") (pin "9") (pinfunction "9_9") (pintype "passive"))
      (node (ref "IC44") (pin "9") (pinfunction "9_9") (pintype "passive"))
      (node (ref "IC45") (pin "9") (pinfunction "9_9") (pintype "passive"))
    )
    (net (code "250") (name "Net-(IC42-Pad10)") (class "Default")
      (node (ref "IC42") (pin "10") (pinfunction "10_10") (pintype "passive"))
      (node (ref "IC43") (pin "10") (pinfunction "10_10") (pintype "passive"))
      (node (ref "IC44") (pin "10") (pinfunction "10_10") (pintype "passive"))
      (node (ref "IC45") (pin "10") (pinfunction "10_10") (pintype "passive"))
    )
    (net (code "251") (name "Net-(IC42-Pad11)") (class "Default")
      (node (ref "IC42") (pin "11") (pinfunction "11_11") (pintype "passive"))
      (node (ref "IC43") (pin "11") (pinfunction "11_11") (pintype "passive"))
      (node (ref "IC44") (pin "11") (pinfunction "11_11") (pintype "passive"))
      (node (ref "IC45") (pin "11") (pinfunction "11_11") (pintype "passive"))
    )
    (net (code "252") (name "Net-(IC42-Pad12)") (class "Default")
      (node (ref "IC42") (pin "12") (pinfunction "12_12") (pintype "passive"))
      (node (ref "IC43") (pin "12") (pinfunction "12_12") (pintype "passive"))
      (node (ref "IC44") (pin "12") (pinfunction "12_12") (pintype "passive"))
      (node (ref "IC45") (pin "12") (pinfunction "12_12") (pintype "passive"))
    )
    (net (code "253") (name "Net-(IC42-Pad13)") (class "Default")
      (node (ref "IC42") (pin "13") (pinfunction "13_13") (pintype "passive"))
      (node (ref "IC43") (pin "13") (pinfunction "13_13") (pintype "passive"))
      (node (ref "IC44") (pin "13") (pinfunction "13_13") (pintype "passive"))
      (node (ref "IC45") (pin "13") (pinfunction "13_13") (pintype "passive"))
    )
    (net (code "254") (name "Net-(IC42-Pad14)") (class "Default")
      (node (ref "IC42") (pin "14") (pinfunction "14_14") (pintype "passive"))
      (node (ref "IC43") (pin "14") (pinfunction "14_14") (pintype "passive"))
      (node (ref "IC44") (pin "14") (pinfunction "14_14") (pintype "passive"))
      (node (ref "IC45") (pin "14") (pinfunction "14_14") (pintype "passive"))
    )
    (net (code "255") (name "Net-(IC42-Pad15)") (class "Default")
      (node (ref "IC42") (pin "15") (pinfunction "15_15") (pintype "passive"))
      (node (ref "IC43") (pin "15") (pinfunction "15_15") (pintype "passive"))
      (node (ref "IC44") (pin "15") (pinfunction "15_15") (pintype "passive"))
      (node (ref "IC45") (pin "15") (pinfunction "15_15") (pintype "passive"))
    )
    (net (code "256") (name "Net-(IC42-Pad16)") (class "Default")
      (node (ref "IC42") (pin "16") (pinfunction "16_16") (pintype "passive"))
      (node (ref "IC43") (pin "16") (pinfunction "16_16") (pintype "passive"))
      (node (ref "IC44") (pin "16") (pinfunction "16_16") (pintype "passive"))
      (node (ref "IC45") (pin "16") (pinfunction "16_16") (pintype "passive"))
    )
    (net (code "257") (name "Net-(IC42-Pad17)") (class "Default")
      (node (ref "IC42") (pin "17") (pinfunction "17_17") (pintype "passive"))
      (node (ref "IC43") (pin "17") (pinfunction "17_17") (pintype "passive"))
      (node (ref "IC44") (pin "17") (pinfunction "17_17") (pintype "passive"))
      (node (ref "IC45") (pin "17") (pinfunction "17_17") (pintype "passive"))
    )
    (net (code "258") (name "Net-(IC42-Pad18)") (class "Default")
      (node (ref "IC42") (pin "18") (pinfunction "18_18") (pintype "passive"))
      (node (ref "IC43") (pin "18") (pinfunction "18_18") (pintype "passive"))
      (node (ref "IC44") (pin "18") (pinfunction "18_18") (pintype "passive"))
      (node (ref "IC45") (pin "18") (pinfunction "18_18") (pintype "passive"))
    )
    (net (code "259") (name "Net-(IC42-Pad19)") (class "Default")
      (node (ref "IC42") (pin "19") (pinfunction "19_19") (pintype "passive"))
      (node (ref "IC43") (pin "19") (pinfunction "19_19") (pintype "passive"))
      (node (ref "IC44") (pin "19") (pinfunction "19_19") (pintype "passive"))
      (node (ref "IC45") (pin "19") (pinfunction "19_19") (pintype "passive"))
    )
    (net (code "260") (name "Net-(IC42-Pad20)") (class "Default")
      (node (ref "IC42") (pin "20") (pinfunction "20_20") (pintype "passive"))
      (node (ref "IC43") (pin "20") (pinfunction "20_20") (pintype "passive"))
      (node (ref "IC44") (pin "20") (pinfunction "20_20") (pintype "passive"))
      (node (ref "IC45") (pin "20") (pinfunction "20_20") (pintype "passive"))
    )
    (net (code "261") (name "Net-(IC42-Pad21)") (class "Default")
      (node (ref "IC42") (pin "21") (pinfunction "21_21") (pintype "passive"))
      (node (ref "IC43") (pin "21") (pinfunction "21_21") (pintype "passive"))
      (node (ref "IC44") (pin "21") (pinfunction "21_21") (pintype "passive"))
      (node (ref "IC45") (pin "21") (pinfunction "21_21") (pintype "passive"))
    )
    (net (code "262") (name "Net-(IC42-Pad22)") (class "Default")
      (node (ref "IC42") (pin "22") (pinfunction "22_22") (pintype "passive"))
      (node (ref "IC43") (pin "22") (pinfunction "22_22") (pintype "passive"))
      (node (ref "IC44") (pin "22") (pinfunction "22_22") (pintype "passive"))
      (node (ref "IC45") (pin "22") (pinfunction "22_22") (pintype "passive"))
    )
    (net (code "263") (name "Net-(IC42-Pad23)") (class "Default")
      (node (ref "IC42") (pin "23") (pinfunction "23_23") (pintype "passive"))
      (node (ref "IC43") (pin "23") (pinfunction "23_23") (pintype "passive"))
      (node (ref "IC44") (pin "23") (pinfunction "23_23") (pintype "passive"))
      (node (ref "IC45") (pin "23") (pinfunction "23_23") (pintype "passive"))
    )
    (net (code "264") (name "Net-(IC42-Pad24)") (class "Default")
      (node (ref "IC42") (pin "24") (pinfunction "24_24") (pintype "passive"))
      (node (ref "IC43") (pin "24") (pinfunction "24_24") (pintype "passive"))
      (node (ref "IC44") (pin "24") (pinfunction "24_24") (pintype "passive"))
      (node (ref "IC45") (pin "24") (pinfunction "24_24") (pintype "passive"))
    )
    (net (code "265") (name "Net-(IC46-Pad1)") (class "Default")
      (node (ref "IC46") (pin "1") (pinfunction "1_1") (pintype "passive"))
      (node (ref "IC47") (pin "1") (pinfunction "1_1") (pintype "passive"))
      (node (ref "IC48") (pin "1") (pinfunction "1_1") (pintype "passive"))
      (node (ref "IC49") (pin "1") (pinfunction "1_1") (pintype "passive"))
    )
    (net (code "266") (name "Net-(IC46-Pad2)") (class "Default")
      (node (ref "IC46") (pin "2") (pinfunction "2_2") (pintype "passive"))
      (node (ref "IC47") (pin "2") (pinfunction "2_2") (pintype "passive"))
      (node (ref "IC48") (pin "2") (pinfunction "2_2") (pintype "passive"))
      (node (ref "IC49") (pin "2") (pinfunction "2_2") (pintype "passive"))
    )
    (net (code "267") (name "Net-(IC46-Pad3)") (class "Default")
      (node (ref "IC46") (pin "3") (pinfunction "3_3") (pintype "passive"))
      (node (ref "IC47") (pin "3") (pinfunction "3_3") (pintype "passive"))
      (node (ref "IC48") (pin "3") (pinfunction "3_3") (pintype "passive"))
      (node (ref "IC49") (pin "3") (pinfunction "3_3") (pintype "passive"))
    )
    (net (code "268") (name "Net-(IC46-Pad4)") (class "Default")
      (node (ref "IC46") (pin "4") (pinfunction "4_4") (pintype "passive"))
      (node (ref "IC47") (pin "4") (pinfunction "4_4") (pintype "passive"))
      (node (ref "IC48") (pin "4") (pinfunction "4_4") (pintype "passive"))
      (node (ref "IC49") (pin "4") (pinfunction "4_4") (pintype "passive"))
    )
    (net (code "269") (name "Net-(IC46-Pad5)") (class "Default")
      (node (ref "IC46") (pin "5") (pinfunction "5_5") (pintype "passive"))
      (node (ref "IC47") (pin "5") (pinfunction "5_5") (pintype "passive"))
      (node (ref "IC48") (pin "5") (pinfunction "5_5") (pintype "passive"))
      (node (ref "IC49") (pin "5") (pinfunction "5_5") (pintype "passive"))
    )
    (net (code "270") (name "Net-(IC46-Pad6)") (class "Default")
      (node (ref "IC46") (pin "6") (pinfunction "6_6") (pintype "passive"))
      (node (ref "IC47") (pin "6") (pinfunction "6_6") (pintype "passive"))
      (node (ref "IC48") (pin "6") (pinfunction "6_6") (pintype "passive"))
      (node (ref "IC49") (pin "6") (pinfunction "6_6") (pintype "passive"))
    )
    (net (code "271") (name "Net-(IC46-Pad7)") (class "Default")
      (node (ref "IC46") (pin "7") (pinfunction "7_7") (pintype "passive"))
      (node (ref "IC47") (pin "7") (pinfunction "7_7") (pintype "passive"))
      (node (ref "IC48") (pin "7") (pinfunction "7_7") (pintype "passive"))
      (node (ref "IC49") (pin "7") (pinfunction "7_7") (pintype "passive"))
    )
    (net (code "272") (name "Net-(IC46-Pad8)") (class "Default")
      (node (ref "IC46") (pin "8") (pinfunction "8_8") (pintype "passive"))
      (node (ref "IC47") (pin "8") (pinfunction "8_8") (pintype "passive"))
      (node (ref "IC48") (pin "8") (pinfunction "8_8") (pintype "passive"))
      (node (ref "IC49") (pin "8") (pinfunction "8_8") (pintype "passive"))
    )
    (net (code "273") (name "Net-(IC46-Pad9)") (class "Default")
      (node (ref "IC46") (pin "9") (pinfunction "9_9") (pintype "passive"))
      (node (ref "IC47") (pin "9") (pinfunction "9_9") (pintype "passive"))
      (node (ref "IC48") (pin "9") (pinfunction "9_9") (pintype "passive"))
      (node (ref "IC49") (pin "9") (pinfunction "9_9") (pintype "passive"))
    )
    (net (code "274") (name "Net-(IC46-Pad10)") (class "Default")
      (node (ref "IC46") (pin "10") (pinfunction "10_10") (pintype "passive"))
      (node (ref "IC47") (pin "10") (pinfunction "10_10") (pintype "passive"))
      (node (ref "IC48") (pin "10") (pinfunction "10_10") (pintype "passive"))
      (node (ref "IC49") (pin "10") (pinfunction "10_10") (pintype "passive"))
    )
    (net (code "275") (name "Net-(IC46-Pad11)") (class "Default")
      (node (ref "IC46") (pin "11") (pinfunction "11_11") (pintype "passive"))
      (node (ref "IC47") (pin "11") (pinfunction "11_11") (pintype "passive"))
      (node (ref "IC48") (pin "11") (pinfunction "11_11") (pintype "passive"))
      (node (ref "IC49") (pin "11") (pinfunction "11_11") (pintype "passive"))
    )
    (net (code "276") (name "Net-(IC46-Pad12)") (class "Default")
      (node (ref "IC46") (pin "12") (pinfunction "12_12") (pintype "passive"))
      (node (ref "IC47") (pin "12") (pinfunction "12_12") (pintype "passive"))
      (node (ref "IC48") (pin "12") (pinfunction "12_12") (pintype "passive"))
      (node (ref "IC49") (pin "12") (pinfunction "12_12") (pintype "passive"))
    )
    (net (code "277") (name "Net-(IC46-Pad13)") (class "Default")
      (node (ref "IC46") (pin "13") (pinfunction "13_13") (pintype "passive"))
      (node (ref "IC47") (pin "13") (pinfunction "13_13") (pintype "passive"))
      (node (ref "IC48") (pin "13") (pinfunction "13_13") (pintype "passive"))
      (node (ref "IC49") (pin "13") (pinfunction "13_13") (pintype "passive"))
    )
    (net (code "278") (name "Net-(IC46-Pad14)") (class "Default")
      (node (ref "IC46") (pin "14") (pinfunction "14_14") (pintype "passive"))
      (node (ref "IC47") (pin "14") (pinfunction "14_14") (pintype "passive"))
      (node (ref "IC48") (pin "14") (pinfunction "14_14") (pintype "passive"))
      (node (ref "IC49") (pin "14") (pinfunction "14_14") (pintype "passive"))
    )
    (net (code "279") (name "Net-(IC46-Pad15)") (class "Default")
      (node (ref "IC46") (pin "15") (pinfunction "15_15") (pintype "passive"))
      (node (ref "IC47") (pin "15") (pinfunction "15_15") (pintype "passive"))
      (node (ref "IC48") (pin "15") (pinfunction "15_15") (pintype "passive"))
      (node (ref "IC49") (pin "15") (pinfunction "15_15") (pintype "passive"))
    )
    (net (code "280") (name "Net-(IC46-Pad16)") (class "Default")
      (node (ref "IC46") (pin "16") (pinfunction "16_16") (pintype "passive"))
      (node (ref "IC47") (pin "16") (pinfunction "16_16") (pintype "passive"))
      (node (ref "IC48") (pin "16") (pinfunction "16_16") (pintype "passive"))
      (node (ref "IC49") (pin "16") (pinfunction "16_16") (pintype "passive"))
    )
    (net (code "281") (name "Net-(IC46-Pad17)") (class "Default")
      (node (ref "IC46") (pin "17") (pinfunction "17_17") (pintype "passive"))
      (node (ref "IC47") (pin "17") (pinfunction "17_17") (pintype "passive"))
      (node (ref "IC48") (pin "17") (pinfunction "17_17") (pintype "passive"))
      (node (ref "IC49") (pin "17") (pinfunction "17_17") (pintype "passive"))
    )
    (net (code "282") (name "Net-(IC46-Pad18)") (class "Default")
      (node (ref "IC46") (pin "18") (pinfunction "18_18") (pintype "passive"))
      (node (ref "IC47") (pin "18") (pinfunction "18_18") (pintype "passive"))
      (node (ref "IC48") (pin "18") (pinfunction "18_18") (pintype "passive"))
      (node (ref "IC49") (pin "18") (pinfunction "18_18") (pintype "passive"))
    )
    (net (code "283") (name "Net-(IC46-Pad19)") (class "Default")
      (node (ref "IC46") (pin "19") (pinfunction "19_19") (pintype "passive"))
      (node (ref "IC47") (pin "19") (pinfunction "19_19") (pintype "passive"))
      (node (ref "IC48") (pin "19") (pinfunction "19_19") (pintype "passive"))
      (node (ref "IC49") (pin "19") (pinfunction "19_19") (pintype "passive"))
    )
    (net (code "284") (name "Net-(IC46-Pad20)") (class "Default")
      (node (ref "IC46") (pin "20") (pinfunction "20_20") (pintype "passive"))
      (node (ref "IC47") (pin "20") (pinfunction "20_20") (pintype "passive"))
      (node (ref "IC48") (pin "20") (pinfunction "20_20") (pintype "passive"))
      (node (ref "IC49") (pin "20") (pinfunction "20_20") (pintype "passive"))
    )
    (net (code "285") (name "Net-(IC46-Pad21)") (class "Default")
      (node (ref "IC46") (pin "21") (pinfunction "21_21") (pintype "passive"))
      (node (ref "IC47") (pin "21") (pinfunction "21_21") (pintype "passive"))
      (node (ref "IC48") (pin "21") (pinfunction "21_21") (pintype "passive"))
      (node (ref "IC49") (pin "21") (pinfunction "21_21") (pintype "passive"))
    )
    (net (code "286") (name "Net-(IC46-Pad22)") (class "Default")
      (node (ref "IC46") (pin "22") (pinfunction "22_22") (pintype "passive"))
      (node (ref "IC47") (pin "22") (pinfunction "22_22") (pintype "passive"))
      (node (ref "IC48") (pin "22") (pinfunction "22_22") (pintype "passive"))
      (node (ref "IC49") (pin "22") (pinfunction "22_22") (pintype "passive"))
    )
    (net (code "287") (name "Net-(IC46-Pad23)") (class "Default")
      (node (ref "IC46") (pin "23") (pinfunction "23_23") (pintype "passive"))
      (node (ref "IC47") (pin "23") (pinfunction "23_23") (pintype "passive"))
      (node (ref "IC48") (pin "23") (pinfunction "23_23") (pintype "passive"))
      (node (ref "IC49") (pin "23") (pinfunction "23_23") (pintype "passive"))
    )
    (net (code "288") (name "Net-(IC46-Pad24)") (class "Default")
      (node (ref "IC46") (pin "24") (pinfunction "24_24") (pintype "passive"))
      (node (ref "IC47") (pin "24") (pinfunction "24_24") (pintype "passive"))
      (node (ref "IC48") (pin "24") (pinfunction "24_24") (pintype "passive"))
      (node (ref "IC49") (pin "24") (pinfunction "24_24") (pintype "passive"))
    )
    (net (code "289") (name "Net-(IC50-Pad1)") (class "Default")
      (node (ref "IC50") (pin "1") (pinfunction "1_1") (pintype "passive"))
      (node (ref "IC51") (pin "1") (pinfunction "1_1") (pintype "passive"))
      (node (ref "IC52") (pin "1") (pinfunction "1_1") (pintype "passive"))
      (node (ref "IC53") (pin "1") (pinfunction "1_1") (pintype "passive"))
    )
    (net (code "290") (name "Net-(IC50-Pad2)") (class "Default")
      (node (ref "IC50") (pin "2") (pinfunction "2_2") (pintype "passive"))
      (node (ref "IC51") (pin "2") (pinfunction "2_2") (pintype "passive"))
      (node (ref "IC52") (pin "2") (pinfunction "2_2") (pintype "passive"))
      (node (ref "IC53") (pin "2") (pinfunction "2_2") (pintype "passive"))
    )
    (net (code "291") (name "Net-(IC50-Pad3)") (class "Default")
      (node (ref "IC50") (pin "3") (pinfunction "3_3") (pintype "passive"))
      (node (ref "IC51") (pin "3") (pinfunction "3_3") (pintype "passive"))
      (node (ref "IC52") (pin "3") (pinfunction "3_3") (pintype "passive"))
      (node (ref "IC53") (pin "3") (pinfunction "3_3") (pintype "passive"))
    )
    (net (code "292") (name "Net-(IC50-Pad4)") (class "Default")
      (node (ref "IC50") (pin "4") (pinfunction "4_4") (pintype "passive"))
      (node (ref "IC51") (pin "4") (pinfunction "4_4") (pintype "passive"))
      (node (ref "IC52") (pin "4") (pinfunction "4_4") (pintype "passive"))
      (node (ref "IC53") (pin "4") (pinfunction "4_4") (pintype "passive"))
    )
    (net (code "293") (name "Net-(IC50-Pad5)") (class "Default")
      (node (ref "IC50") (pin "5") (pinfunction "5_5") (pintype "passive"))
      (node (ref "IC51") (pin "5") (pinfunction "5_5") (pintype "passive"))
      (node (ref "IC52") (pin "5") (pinfunction "5_5") (pintype "passive"))
      (node (ref "IC53") (pin "5") (pinfunction "5_5") (pintype "passive"))
    )
    (net (code "294") (name "Net-(IC50-Pad6)") (class "Default")
      (node (ref "IC50") (pin "6") (pinfunction "6_6") (pintype "passive"))
      (node (ref "IC51") (pin "6") (pinfunction "6_6") (pintype "passive"))
      (node (ref "IC52") (pin "6") (pinfunction "6_6") (pintype "passive"))
      (node (ref "IC53") (pin "6") (pinfunction "6_6") (pintype "passive"))
    )
    (net (code "295") (name "Net-(IC50-Pad7)") (class "Default")
      (node (ref "IC50") (pin "7") (pinfunction "7_7") (pintype "passive"))
      (node (ref "IC51") (pin "7") (pinfunction "7_7") (pintype "passive"))
      (node (ref "IC52") (pin "7") (pinfunction "7_7") (pintype "passive"))
      (node (ref "IC53") (pin "7") (pinfunction "7_7") (pintype "passive"))
    )
    (net (code "296") (name "Net-(IC50-Pad8)") (class "Default")
      (node (ref "IC50") (pin "8") (pinfunction "8_8") (pintype "passive"))
      (node (ref "IC51") (pin "8") (pinfunction "8_8") (pintype "passive"))
      (node (ref "IC52") (pin "8") (pinfunction "8_8") (pintype "passive"))
      (node (ref "IC53") (pin "8") (pinfunction "8_8") (pintype "passive"))
    )
    (net (code "297") (name "Net-(IC50-Pad9)") (class "Default")
      (node (ref "IC50") (pin "9") (pinfunction "9_9") (pintype "passive"))
      (node (ref "IC51") (pin "9") (pinfunction "9_9") (pintype "passive"))
      (node (ref "IC52") (pin "9") (pinfunction "9_9") (pintype "passive"))
      (node (ref "IC53") (pin "9") (pinfunction "9_9") (pintype "passive"))
    )
    (net (code "298") (name "Net-(IC50-Pad10)") (class "Default")
      (node (ref "IC50") (pin "10") (pinfunction "10_10") (pintype "passive"))
      (node (ref "IC51") (pin "10") (pinfunction "10_10") (pintype "passive"))
      (node (ref "IC52") (pin "10") (pinfunction "10_10") (pintype "passive"))
      (node (ref "IC53") (pin "10") (pinfunction "10_10") (pintype "passive"))
    )
    (net (code "299") (name "Net-(IC50-Pad11)") (class "Default")
      (node (ref "IC50") (pin "11") (pinfunction "11_11") (pintype "passive"))
      (node (ref "IC51") (pin "11") (pinfunction "11_11") (pintype "passive"))
      (node (ref "IC52") (pin "11") (pinfunction "11_11") (pintype "passive"))
      (node (ref "IC53") (pin "11") (pinfunction "11_11") (pintype "passive"))
    )
    (net (code "300") (name "Net-(IC50-Pad12)") (class "Default")
      (node (ref "IC50") (pin "12") (pinfunction "12_12") (pintype "passive"))
      (node (ref "IC51") (pin "12") (pinfunction "12_12") (pintype "passive"))
      (node (ref "IC52") (pin "12") (pinfunction "12_12") (pintype "passive"))
      (node (ref "IC53") (pin "12") (pinfunction "12_12") (pintype "passive"))
    )
    (net (code "301") (name "Net-(IC50-Pad13)") (class "Default")
      (node (ref "IC50") (pin "13") (pinfunction "13_13") (pintype "passive"))
      (node (ref "IC51") (pin "13") (pinfunction "13_13") (pintype "passive"))
      (node (ref "IC52") (pin "13") (pinfunction "13_13") (pintype "passive"))
      (node (ref "IC53") (pin "13") (pinfunction "13_13") (pintype "passive"))
    )
    (net (code "302") (name "Net-(IC50-Pad14)") (class "Default")
      (node (ref "IC50") (pin "14") (pinfunction "14_14") (pintype "passive"))
      (node (ref "IC51") (pin "14") (pinfunction "14_14") (pintype "passive"))
      (node (ref "IC52") (pin "14") (pinfunction "14_14") (pintype "passive"))
      (node (ref "IC53") (pin "14") (pinfunction "14_14") (pintype "passive"))
    )
    (net (code "303") (name "Net-(IC50-Pad15)") (class "Default")
      (node (ref "IC50") (pin "15") (pinfunction "15_15") (pintype "passive"))
      (node (ref "IC51") (pin "15") (pinfunction "15_15") (pintype "passive"))
      (node (ref "IC52") (pin "15") (pinfunction "15_15") (pintype "passive"))
      (node (ref "IC53") (pin "15") (pinfunction "15_15") (pintype "passive"))
    )
    (net (code "304") (name "Net-(IC50-Pad16)") (class "Default")
      (node (ref "IC50") (pin "16") (pinfunction "16_16") (pintype "passive"))
      (node (ref "IC51") (pin "16") (pinfunction "16_16") (pintype "passive"))
      (node (ref "IC52") (pin "16") (pinfunction "16_16") (pintype "passive"))
      (node (ref "IC53") (pin "16") (pinfunction "16_16") (pintype "passive"))
    )
    (net (code "305") (name "Net-(IC50-Pad17)") (class "Default")
      (node (ref "IC50") (pin "17") (pinfunction "17_17") (pintype "passive"))
      (node (ref "IC51") (pin "17") (pinfunction "17_17") (pintype "passive"))
      (node (ref "IC52") (pin "17") (pinfunction "17_17") (pintype "passive"))
      (node (ref "IC53") (pin "17") (pinfunction "17_17") (pintype "passive"))
    )
    (net (code "306") (name "Net-(IC50-Pad18)") (class "Default")
      (node (ref "IC50") (pin "18") (pinfunction "18_18") (pintype "passive"))
      (node (ref "IC51") (pin "18") (pinfunction "18_18") (pintype "passive"))
      (node (ref "IC52") (pin "18") (pinfunction "18_18") (pintype "passive"))
      (node (ref "IC53") (pin "18") (pinfunction "18_18") (pintype "passive"))
    )
    (net (code "307") (name "Net-(IC50-Pad19)") (class "Default")
      (node (ref "IC50") (pin "19") (pinfunction "19_19") (pintype "passive"))
      (node (ref "IC51") (pin "19") (pinfunction "19_19") (pintype "passive"))
      (node (ref "IC52") (pin "19") (pinfunction "19_19") (pintype "passive"))
      (node (ref "IC53") (pin "19") (pinfunction "19_19") (pintype "passive"))
    )
    (net (code "308") (name "Net-(IC50-Pad20)") (class "Default")
      (node (ref "IC50") (pin "20") (pinfunction "20_20") (pintype "passive"))
      (node (ref "IC51") (pin "20") (pinfunction "20_20") (pintype "passive"))
      (node (ref "IC52") (pin "20") (pinfunction "20_20") (pintype "passive"))
      (node (ref "IC53") (pin "20") (pinfunction "20_20") (pintype "passive"))
    )
    (net (code "309") (name "Net-(IC50-Pad21)") (class "Default")
      (node (ref "IC50") (pin "21") (pinfunction "21_21") (pintype "passive"))
      (node (ref "IC51") (pin "21") (pinfunction "21_21") (pintype "passive"))
      (node (ref "IC52") (pin "21") (pinfunction "21_21") (pintype "passive"))
      (node (ref "IC53") (pin "21") (pinfunction "21_21") (pintype "passive"))
    )
    (net (code "310") (name "Net-(IC50-Pad22)") (class "Default")
      (node (ref "IC50") (pin "22") (pinfunction "22_22") (pintype "passive"))
      (node (ref "IC51") (pin "22") (pinfunction "22_22") (pintype "passive"))
      (node (ref "IC52") (pin "22") (pinfunction "22_22") (pintype "passive"))
      (node (ref "IC53") (pin "22") (pinfunction "22_22") (pintype "passive"))
    )
    (net (code "311") (name "Net-(IC50-Pad23)") (class "Default")
      (node (ref "IC50") (pin "23") (pinfunction "23_23") (pintype "passive"))
      (node (ref "IC51") (pin "23") (pinfunction "23_23") (pintype "passive"))
      (node (ref "IC52") (pin "23") (pinfunction "23_23") (pintype "passive"))
      (node (ref "IC53") (pin "23") (pinfunction "23_23") (pintype "passive"))
    )
    (net (code "312") (name "Net-(IC50-Pad24)") (class "Default")
      (node (ref "IC50") (pin "24") (pinfunction "24_24") (pintype "passive"))
      (node (ref "IC51") (pin "24") (pinfunction "24_24") (pintype "passive"))
      (node (ref "IC52") (pin "24") (pinfunction "24_24") (pintype "passive"))
      (node (ref "IC53") (pin "24") (pinfunction "24_24") (pintype "passive"))
    )
    (net (code "313") (name "Net-(IC54-Pad1)") (class "Default")
      (node (ref "IC54") (pin "1") (pinfunction "1_1") (pintype "passive"))
      (node (ref "IC55") (pin "1") (pinfunction "1_1") (pintype "passive"))
      (node (ref "IC56") (pin "1") (pinfunction "1_1") (pintype "passive"))
      (node (ref "IC57") (pin "1") (pinfunction "1_1") (pintype "passive"))
    )
    (net (code "314") (name "Net-(IC54-Pad2)") (class "Default")
      (node (ref "IC54") (pin "2") (pinfunction "2_2") (pintype "passive"))
      (node (ref "IC55") (pin "2") (pinfunction "2_2") (pintype "passive"))
      (node (ref "IC56") (pin "2") (pinfunction "2_2") (pintype "passive"))
      (node (ref "IC57") (pin "2") (pinfunction "2_2") (pintype "passive"))
    )
    (net (code "315") (name "Net-(IC54-Pad3)") (class "Default")
      (node (ref "IC54") (pin "3") (pinfunction "3_3") (pintype "passive"))
      (node (ref "IC55") (pin "3") (pinfunction "3_3") (pintype "passive"))
      (node (ref "IC56") (pin "3") (pinfunction "3_3") (pintype "passive"))
      (node (ref "IC57") (pin "3") (pinfunction "3_3") (pintype "passive"))
    )
    (net (code "316") (name "Net-(IC54-Pad4)") (class "Default")
      (node (ref "IC54") (pin "4") (pinfunction "4_4") (pintype "passive"))
      (node (ref "IC55") (pin "4") (pinfunction "4_4") (pintype "passive"))
      (node (ref "IC56") (pin "4") (pinfunction "4_4") (pintype "passive"))
      (node (ref "IC57") (pin "4") (pinfunction "4_4") (pintype "passive"))
    )
    (net (code "317") (name "Net-(IC54-Pad5)") (class "Default")
      (node (ref "IC54") (pin "5") (pinfunction "5_5") (pintype "passive"))
      (node (ref "IC55") (pin "5") (pinfunction "5_5") (pintype "passive"))
      (node (ref "IC56") (pin "5") (pinfunction "5_5") (pintype "passive"))
      (node (ref "IC57") (pin "5") (pinfunction "5_5") (pintype "passive"))
    )
    (net (code "318") (name "Net-(IC54-Pad6)") (class "Default")
      (node (ref "IC54") (pin "6") (pinfunction "6_6") (pintype "passive"))
      (node (ref "IC55") (pin "6") (pinfunction "6_6") (pintype "passive"))
      (node (ref "IC56") (pin "6") (pinfunction "6_6") (pintype "passive"))
      (node (ref "IC57") (pin "6") (pinfunction "6_6") (pintype "passive"))
    )
    (net (code "319") (name "Net-(IC54-Pad7)") (class "Default")
      (node (ref "IC54") (pin "7") (pinfunction "7_7") (pintype "passive"))
      (node (ref "IC55") (pin "7") (pinfunction "7_7") (pintype "passive"))
      (node (ref "IC56") (pin "7") (pinfunction "7_7") (pintype "passive"))
      (node (ref "IC57") (pin "7") (pinfunction "7_7") (pintype "passive"))
    )
    (net (code "320") (name "Net-(IC54-Pad8)") (class "Default")
      (node (ref "IC54") (pin "8") (pinfunction "8_8") (pintype "passive"))
      (node (ref "IC55") (pin "8") (pinfunction "8_8") (pintype "passive"))
      (node (ref "IC56") (pin "8") (pinfunction "8_8") (pintype "passive"))
      (node (ref "IC57") (pin "8") (pinfunction "8_8") (pintype "passive"))
    )
    (net (code "321") (name "Net-(IC54-Pad9)") (class "Default")
      (node (ref "IC54") (pin "9") (pinfunction "9_9") (pintype "passive"))
      (node (ref "IC55") (pin "9") (pinfunction "9_9") (pintype "passive"))
      (node (ref "IC56") (pin "9") (pinfunction "9_9") (pintype "passive"))
      (node (ref "IC57") (pin "9") (pinfunction "9_9") (pintype "passive"))
    )
    (net (code "322") (name "Net-(IC54-Pad10)") (class "Default")
      (node (ref "IC54") (pin "10") (pinfunction "10_10") (pintype "passive"))
      (node (ref "IC55") (pin "10") (pinfunction "10_10") (pintype "passive"))
      (node (ref "IC56") (pin "10") (pinfunction "10_10") (pintype "passive"))
      (node (ref "IC57") (pin "10") (pinfunction "10_10") (pintype "passive"))
    )
    (net (code "323") (name "Net-(IC54-Pad11)") (class "Default")
      (node (ref "IC54") (pin "11") (pinfunction "11_11") (pintype "passive"))
      (node (ref "IC55") (pin "11") (pinfunction "11_11") (pintype "passive"))
      (node (ref "IC56") (pin "11") (pinfunction "11_11") (pintype "passive"))
      (node (ref "IC57") (pin "11") (pinfunction "11_11") (pintype "passive"))
    )
    (net (code "324") (name "Net-(IC54-Pad12)") (class "Default")
      (node (ref "IC54") (pin "12") (pinfunction "12_12") (pintype "passive"))
      (node (ref "IC55") (pin "12") (pinfunction "12_12") (pintype "passive"))
      (node (ref "IC56") (pin "12") (pinfunction "12_12") (pintype "passive"))
      (node (ref "IC57") (pin "12") (pinfunction "12_12") (pintype "passive"))
    )
    (net (code "325") (name "Net-(IC54-Pad13)") (class "Default")
      (node (ref "IC54") (pin "13") (pinfunction "13_13") (pintype "passive"))
      (node (ref "IC55") (pin "13") (pinfunction "13_13") (pintype "passive"))
      (node (ref "IC56") (pin "13") (pinfunction "13_13") (pintype "passive"))
      (node (ref "IC57") (pin "13") (pinfunction "13_13") (pintype "passive"))
    )
    (net (code "326") (name "Net-(IC54-Pad14)") (class "Default")
      (node (ref "IC54") (pin "14") (pinfunction "14_14") (pintype "passive"))
      (node (ref "IC55") (pin "14") (pinfunction "14_14") (pintype "passive"))
      (node (ref "IC56") (pin "14") (pinfunction "14_14") (pintype "passive"))
      (node (ref "IC57") (pin "14") (pinfunction "14_14") (pintype "passive"))
    )
    (net (code "327") (name "Net-(IC54-Pad15)") (class "Default")
      (node (ref "IC54") (pin "15") (pinfunction "15_15") (pintype "passive"))
      (node (ref "IC55") (pin "15") (pinfunction "15_15") (pintype "passive"))
      (node (ref "IC56") (pin "15") (pinfunction "15_15") (pintype "passive"))
      (node (ref "IC57") (pin "15") (pinfunction "15_15") (pintype "passive"))
    )
    (net (code "328") (name "Net-(IC54-Pad16)") (class "Default")
      (node (ref "IC54") (pin "16") (pinfunction "16_16") (pintype "passive"))
      (node (ref "IC55") (pin "16") (pinfunction "16_16") (pintype "passive"))
      (node (ref "IC56") (pin "16") (pinfunction "16_16") (pintype "passive"))
      (node (ref "IC57") (pin "16") (pinfunction "16_16") (pintype "passive"))
    )
    (net (code "329") (name "Net-(IC54-Pad17)") (class "Default")
      (node (ref "IC54") (pin "17") (pinfunction "17_17") (pintype "passive"))
      (node (ref "IC55") (pin "17") (pinfunction "17_17") (pintype "passive"))
      (node (ref "IC56") (pin "17") (pinfunction "17_17") (pintype "passive"))
      (node (ref "IC57") (pin "17") (pinfunction "17_17") (pintype "passive"))
    )
    (net (code "330") (name "Net-(IC54-Pad18)") (class "Default")
      (node (ref "IC54") (pin "18") (pinfunction "18_18") (pintype "passive"))
      (node (ref "IC55") (pin "18") (pinfunction "18_18") (pintype "passive"))
      (node (ref "IC56") (pin "18") (pinfunction "18_18") (pintype "passive"))
      (node (ref "IC57") (pin "18") (pinfunction "18_18") (pintype "passive"))
    )
    (net (code "331") (name "Net-(IC54-Pad19)") (class "Default")
      (node (ref "IC54") (pin "19") (pinfunction "19_19") (pintype "passive"))
      (node (ref "IC55") (pin "19") (pinfunction "19_19") (pintype "passive"))
      (node (ref "IC56") (pin "19") (pinfunction "19_19") (pintype "passive"))
      (node (ref "IC57") (pin "19") (pinfunction "19_19") (pintype "passive"))
    )
    (net (code "332") (name "Net-(IC54-Pad20)") (class "Default")
      (node (ref "IC54") (pin "20") (pinfunction "20_20") (pintype "passive"))
      (node (ref "IC55") (pin "20") (pinfunction "20_20") (pintype "passive"))
      (node (ref "IC56") (pin "20") (pinfunction "20_20") (pintype "passive"))
      (node (ref "IC57") (pin "20") (pinfunction "20_20") (pintype "passive"))
    )
    (net (code "333") (name "Net-(IC54-Pad21)") (class "Default")
      (node (ref "IC54") (pin "21") (pinfunction "21_21") (pintype "passive"))
      (node (ref "IC55") (pin "21") (pinfunction "21_21") (pintype "passive"))
      (node (ref "IC56") (pin "21") (pinfunction "21_21") (pintype "passive"))
      (node (ref "IC57") (pin "21") (pinfunction "21_21") (pintype "passive"))
    )
    (net (code "334") (name "Net-(IC54-Pad22)") (class "Default")
      (node (ref "IC54") (pin "22") (pinfunction "22_22") (pintype "passive"))
      (node (ref "IC55") (pin "22") (pinfunction "22_22") (pintype "passive"))
      (node (ref "IC56") (pin "22") (pinfunction "22_22") (pintype "passive"))
      (node (ref "IC57") (pin "22") (pinfunction "22_22") (pintype "passive"))
    )
    (net (code "335") (name "Net-(IC54-Pad23)") (class "Default")
      (node (ref "IC54") (pin "23") (pinfunction "23_23") (pintype "passive"))
      (node (ref "IC55") (pin "23") (pinfunction "23_23") (pintype "passive"))
      (node (ref "IC56") (pin "23") (pinfunction "23_23") (pintype "passive"))
      (node (ref "IC57") (pin "23") (pinfunction "23_23") (pintype "passive"))
    )
    (net (code "336") (name "Net-(IC54-Pad24)") (class "Default")
      (node (ref "IC54") (pin "24") (pinfunction "24_24") (pintype "passive"))
      (node (ref "IC55") (pin "24") (pinfunction "24_24") (pintype "passive"))
      (node (ref "IC56") (pin "24") (pinfunction "24_24") (pintype "passive"))
      (node (ref "IC57") (pin "24") (pinfunction "24_24") (pintype "passive"))
    )
    (net (code "337") (name "Net-(IC58-Pad1)") (class "Default")
      (node (ref "IC58") (pin "1") (pinfunction "1_1") (pintype "passive"))
      (node (ref "IC59") (pin "1") (pinfunction "1_1") (pintype "passive"))
      (node (ref "IC60") (pin "1") (pinfunction "1_1") (pintype "passive"))
      (node (ref "IC61") (pin "1") (pinfunction "1_1") (pintype "passive"))
    )
    (net (code "338") (name "Net-(IC58-Pad2)") (class "Default")
      (node (ref "IC58") (pin "2") (pinfunction "2_2") (pintype "passive"))
      (node (ref "IC59") (pin "2") (pinfunction "2_2") (pintype "passive"))
      (node (ref "IC60") (pin "2") (pinfunction "2_2") (pintype "passive"))
      (node (ref "IC61") (pin "2") (pinfunction "2_2") (pintype "passive"))
    )
    (net (code "339") (name "Net-(IC58-Pad3)") (class "Default")
      (node (ref "IC58") (pin "3") (pinfunction "3_3") (pintype "passive"))
      (node (ref "IC59") (pin "3") (pinfunction "3_3") (pintype "passive"))
      (node (ref "IC60") (pin "3") (pinfunction "3_3") (pintype "passive"))
      (node (ref "IC61") (pin "3") (pinfunction "3_3") (pintype "passive"))
    )
    (net (code "340") (name "Net-(IC58-Pad4)") (class "Default")
      (node (ref "IC58") (pin "4") (pinfunction "4_4") (pintype "passive"))
      (node (ref "IC59") (pin "4") (pinfunction "4_4") (pintype "passive"))
      (node (ref "IC60") (pin "4") (pinfunction "4_4") (pintype "passive"))
      (node (ref "IC61") (pin "4") (pinfunction "4_4") (pintype "passive"))
    )
    (net (code "341") (name "Net-(IC58-Pad5)") (class "Default")
      (node (ref "IC58") (pin "5") (pinfunction "5_5") (pintype "passive"))
      (node (ref "IC59") (pin "5") (pinfunction "5_5") (pintype "passive"))
      (node (ref "IC60") (pin "5") (pinfunction "5_5") (pintype "passive"))
      (node (ref "IC61") (pin "5") (pinfunction "5_5") (pintype "passive"))
    )
    (net (code "342") (name "Net-(IC58-Pad6)") (class "Default")
      (node (ref "IC58") (pin "6") (pinfunction "6_6") (pintype "passive"))
      (node (ref "IC59") (pin "6") (pinfunction "6_6") (pintype "passive"))
      (node (ref "IC60") (pin "6") (pinfunction "6_6") (pintype "passive"))
      (node (ref "IC61") (pin "6") (pinfunction "6_6") (pintype "passive"))
    )
    (net (code "343") (name "Net-(IC58-Pad7)") (class "Default")
      (node (ref "IC58") (pin "7") (pinfunction "7_7") (pintype "passive"))
      (node (ref "IC59") (pin "7") (pinfunction "7_7") (pintype "passive"))
      (node (ref "IC60") (pin "7") (pinfunction "7_7") (pintype "passive"))
      (node (ref "IC61") (pin "7") (pinfunction "7_7") (pintype "passive"))
    )
    (net (code "344") (name "Net-(IC58-Pad8)") (class "Default")
      (node (ref "IC58") (pin "8") (pinfunction "8_8") (pintype "passive"))
      (node (ref "IC59") (pin "8") (pinfunction "8_8") (pintype "passive"))
      (node (ref "IC60") (pin "8") (pinfunction "8_8") (pintype "passive"))
      (node (ref "IC61") (pin "8") (pinfunction "8_8") (pintype "passive"))
    )
    (net (code "345") (name "Net-(IC58-Pad9)") (class "Default")
      (node (ref "IC58") (pin "9") (pinfunction "9_9") (pintype "passive"))
      (node (ref "IC59") (pin "9") (pinfunction "9_9") (pintype "passive"))
      (node (ref "IC60") (pin "9") (pinfunction "9_9") (pintype "passive"))
      (node (ref "IC61") (pin "9") (pinfunction "9_9") (pintype "passive"))
    )
    (net (code "346") (name "Net-(IC58-Pad10)") (class "Default")
      (node (ref "IC58") (pin "10") (pinfunction "10_10") (pintype "passive"))
      (node (ref "IC59") (pin "10") (pinfunction "10_10") (pintype "passive"))
      (node (ref "IC60") (pin "10") (pinfunction "10_10") (pintype "passive"))
      (node (ref "IC61") (pin "10") (pinfunction "10_10") (pintype "passive"))
    )
    (net (code "347") (name "Net-(IC58-Pad11)") (class "Default")
      (node (ref "IC58") (pin "11") (pinfunction "11_11") (pintype "passive"))
      (node (ref "IC59") (pin "11") (pinfunction "11_11") (pintype "passive"))
      (node (ref "IC60") (pin "11") (pinfunction "11_11") (pintype "passive"))
      (node (ref "IC61") (pin "11") (pinfunction "11_11") (pintype "passive"))
    )
    (net (code "348") (name "Net-(IC58-Pad12)") (class "Default")
      (node (ref "IC58") (pin "12") (pinfunction "12_12") (pintype "passive"))
      (node (ref "IC59") (pin "12") (pinfunction "12_12") (pintype "passive"))
      (node (ref "IC60") (pin "12") (pinfunction "12_12") (pintype "passive"))
      (node (ref "IC61") (pin "12") (pinfunction "12_12") (pintype "passive"))
    )
    (net (code "349") (name "Net-(IC58-Pad13)") (class "Default")
      (node (ref "IC58") (pin "13") (pinfunction "13_13") (pintype "passive"))
      (node (ref "IC59") (pin "13") (pinfunction "13_13") (pintype "passive"))
      (node (ref "IC60") (pin "13") (pinfunction "13_13") (pintype "passive"))
      (node (ref "IC61") (pin "13") (pinfunction "13_13") (pintype "passive"))
    )
    (net (code "350") (name "Net-(IC58-Pad14)") (class "Default")
      (node (ref "IC58") (pin "14") (pinfunction "14_14") (pintype "passive"))
      (node (ref "IC59") (pin "14") (pinfunction "14_14") (pintype "passive"))
      (node (ref "IC60") (pin "14") (pinfunction "14_14") (pintype "passive"))
      (node (ref "IC61") (pin "14") (pinfunction "14_14") (pintype "passive"))
    )
    (net (code "351") (name "Net-(IC58-Pad15)") (class "Default")
      (node (ref "IC58") (pin "15") (pinfunction "15_15") (pintype "passive"))
      (node (ref "IC59") (pin "15") (pinfunction "15_15") (pintype "passive"))
      (node (ref "IC60") (pin "15") (pinfunction "15_15") (pintype "passive"))
      (node (ref "IC61") (pin "15") (pinfunction "15_15") (pintype "passive"))
    )
    (net (code "352") (name "Net-(IC58-Pad16)") (class "Default")
      (node (ref "IC58") (pin "16") (pinfunction "16_16") (pintype "passive"))
      (node (ref "IC59") (pin "16") (pinfunction "16_16") (pintype "passive"))
      (node (ref "IC60") (pin "16") (pinfunction "16_16") (pintype "passive"))
      (node (ref "IC61") (pin "16") (pinfunction "16_16") (pintype "passive"))
    )
    (net (code "353") (name "Net-(IC58-Pad17)") (class "Default")
      (node (ref "IC58") (pin "17") (pinfunction "17_17") (pintype "passive"))
      (node (ref "IC59") (pin "17") (pinfunction "17_17") (pintype "passive"))
      (node (ref "IC60") (pin "17") (pinfunction "17_17") (pintype "passive"))
      (node (ref "IC61") (pin "17") (pinfunction "17_17") (pintype "passive"))
    )
    (net (code "354") (name "Net-(IC58-Pad18)") (class "Default")
      (node (ref "IC58") (pin "18") (pinfunction "18_18") (pintype "passive"))
      (node (ref "IC59") (pin "18") (pinfunction "18_18") (pintype "passive"))
      (node (ref "IC60") (pin "18") (pinfunction "18_18") (pintype "passive"))
      (node (ref "IC61") (pin "18") (pinfunction "18_18") (pintype "passive"))
    )
    (net (code "355") (name "Net-(IC58-Pad19)") (class "Default")
      (node (ref "IC58") (pin "19") (pinfunction "19_19") (pintype "passive"))
      (node (ref "IC59") (pin "19") (pinfunction "19_19") (pintype "passive"))
      (node (ref "IC60") (pin "19") (pinfunction "19_19") (pintype "passive"))
      (node (ref "IC61") (pin "19") (pinfunction "19_19") (pintype "passive"))
    )
    (net (code "356") (name "Net-(IC58-Pad20)") (class "Default")
      (node (ref "IC58") (pin "20") (pinfunction "20_20") (pintype "passive"))
      (node (ref "IC59") (pin "20") (pinfunction "20_20") (pintype "passive"))
      (node (ref "IC60") (pin "20") (pinfunction "20_20") (pintype "passive"))
      (node (ref "IC61") (pin "20") (pinfunction "20_20") (pintype "passive"))
    )
    (net (code "357") (name "Net-(IC58-Pad21)") (class "Default")
      (node (ref "IC58") (pin "21") (pinfunction "21_21") (pintype "passive"))
      (node (ref "IC59") (pin "21") (pinfunction "21_21") (pintype "passive"))
      (node (ref "IC60") (pin "21") (pinfunction "21_21") (pintype "passive"))
      (node (ref "IC61") (pin "21") (pinfunction "21_21") (pintype "passive"))
    )
    (net (code "358") (name "Net-(IC58-Pad22)") (class "Default")
      (node (ref "IC58") (pin "22") (pinfunction "22_22") (pintype "passive"))
      (node (ref "IC59") (pin "22") (pinfunction "22_22") (pintype "passive"))
      (node (ref "IC60") (pin "22") (pinfunction "22_22") (pintype "passive"))
      (node (ref "IC61") (pin "22") (pinfunction "22_22") (pintype "passive"))
    )
    (net (code "359") (name "Net-(IC58-Pad23)") (class "Default")
      (node (ref "IC58") (pin "23") (pinfunction "23_23") (pintype "passive"))
      (node (ref "IC59") (pin "23") (pinfunction "23_23") (pintype "passive"))
      (node (ref "IC60") (pin "23") (pinfunction "23_23") (pintype "passive"))
      (node (ref "IC61") (pin "23") (pinfunction "23_23") (pintype "passive"))
    )
    (net (code "360") (name "Net-(IC58-Pad24)") (class "Default")
      (node (ref "IC58") (pin "24") (pinfunction "24_24") (pintype "passive"))
      (node (ref "IC59") (pin "24") (pinfunction "24_24") (pintype "passive"))
      (node (ref "IC60") (pin "24") (pinfunction "24_24") (pintype "passive"))
      (node (ref "IC61") (pin "24") (pinfunction "24_24") (pintype "passive"))
    )
    (net (code "361") (name "Net-(IC62-Pad1)") (class "Default")
      (node (ref "IC62") (pin "1") (pinfunction "1_1") (pintype "passive"))
      (node (ref "IC63") (pin "1") (pinfunction "1_1") (pintype "passive"))
      (node (ref "IC64") (pin "1") (pinfunction "1_1") (pintype "passive"))
      (node (ref "IC65") (pin "1") (pinfunction "1_1") (pintype "passive"))
    )
    (net (code "362") (name "Net-(IC62-Pad2)") (class "Default")
      (node (ref "IC62") (pin "2") (pinfunction "2_2") (pintype "passive"))
      (node (ref "IC63") (pin "2") (pinfunction "2_2") (pintype "passive"))
      (node (ref "IC64") (pin "2") (pinfunction "2_2") (pintype "passive"))
      (node (ref "IC65") (pin "2") (pinfunction "2_2") (pintype "passive"))
    )
    (net (code "363") (name "Net-(IC62-Pad3)") (class "Default")
      (node (ref "IC62") (pin "3") (pinfunction "3_3") (pintype "passive"))
      (node (ref "IC63") (pin "3") (pinfunction "3_3") (pintype "passive"))
      (node (ref "IC64") (pin "3") (pinfunction "3_3") (pintype "passive"))
      (node (ref "IC65") (pin "3") (pinfunction "3_3") (pintype "passive"))
    )
    (net (code "364") (name "Net-(IC62-Pad4)") (class "Default")
      (node (ref "IC62") (pin "4") (pinfunction "4_4") (pintype "passive"))
      (node (ref "IC63") (pin "4") (pinfunction "4_4") (pintype "passive"))
      (node (ref "IC64") (pin "4") (pinfunction "4_4") (pintype "passive"))
      (node (ref "IC65") (pin "4") (pinfunction "4_4") (pintype "passive"))
    )
    (net (code "365") (name "Net-(IC62-Pad5)") (class "Default")
      (node (ref "IC62") (pin "5") (pinfunction "5_5") (pintype "passive"))
      (node (ref "IC63") (pin "5") (pinfunction "5_5") (pintype "passive"))
      (node (ref "IC64") (pin "5") (pinfunction "5_5") (pintype "passive"))
      (node (ref "IC65") (pin "5") (pinfunction "5_5") (pintype "passive"))
    )
    (net (code "366") (name "Net-(IC62-Pad6)") (class "Default")
      (node (ref "IC62") (pin "6") (pinfunction "6_6") (pintype "passive"))
      (node (ref "IC63") (pin "6") (pinfunction "6_6") (pintype "passive"))
      (node (ref "IC64") (pin "6") (pinfunction "6_6") (pintype "passive"))
      (node (ref "IC65") (pin "6") (pinfunction "6_6") (pintype "passive"))
    )
    (net (code "367") (name "Net-(IC62-Pad7)") (class "Default")
      (node (ref "IC62") (pin "7") (pinfunction "7_7") (pintype "passive"))
      (node (ref "IC63") (pin "7") (pinfunction "7_7") (pintype "passive"))
      (node (ref "IC64") (pin "7") (pinfunction "7_7") (pintype "passive"))
      (node (ref "IC65") (pin "7") (pinfunction "7_7") (pintype "passive"))
    )
    (net (code "368") (name "Net-(IC62-Pad8)") (class "Default")
      (node (ref "IC62") (pin "8") (pinfunction "8_8") (pintype "passive"))
      (node (ref "IC63") (pin "8") (pinfunction "8_8") (pintype "passive"))
      (node (ref "IC64") (pin "8") (pinfunction "8_8") (pintype "passive"))
      (node (ref "IC65") (pin "8") (pinfunction "8_8") (pintype "passive"))
    )
    (net (code "369") (name "Net-(IC62-Pad9)") (class "Default")
      (node (ref "IC62") (pin "9") (pinfunction "9_9") (pintype "passive"))
      (node (ref "IC63") (pin "9") (pinfunction "9_9") (pintype "passive"))
      (node (ref "IC64") (pin "9") (pinfunction "9_9") (pintype "passive"))
      (node (ref "IC65") (pin "9") (pinfunction "9_9") (pintype "passive"))
    )
    (net (code "370") (name "Net-(IC62-Pad10)") (class "Default")
      (node (ref "IC62") (pin "10") (pinfunction "10_10") (pintype "passive"))
      (node (ref "IC63") (pin "10") (pinfunction "10_10") (pintype "passive"))
      (node (ref "IC64") (pin "10") (pinfunction "10_10") (pintype "passive"))
      (node (ref "IC65") (pin "10") (pinfunction "10_10") (pintype "passive"))
    )
    (net (code "371") (name "Net-(IC62-Pad11)") (class "Default")
      (node (ref "IC62") (pin "11") (pinfunction "11_11") (pintype "passive"))
      (node (ref "IC63") (pin "11") (pinfunction "11_11") (pintype "passive"))
      (node (ref "IC64") (pin "11") (pinfunction "11_11") (pintype "passive"))
      (node (ref "IC65") (pin "11") (pinfunction "11_11") (pintype "passive"))
    )
    (net (code "372") (name "Net-(IC62-Pad12)") (class "Default")
      (node (ref "IC62") (pin "12") (pinfunction "12_12") (pintype "passive"))
      (node (ref "IC63") (pin "12") (pinfunction "12_12") (pintype "passive"))
      (node (ref "IC64") (pin "12") (pinfunction "12_12") (pintype "passive"))
      (node (ref "IC65") (pin "12") (pinfunction "12_12") (pintype "passive"))
    )
    (net (code "373") (name "Net-(IC62-Pad13)") (class "Default")
      (node (ref "IC62") (pin "13") (pinfunction "13_13") (pintype "passive"))
      (node (ref "IC63") (pin "13") (pinfunction "13_13") (pintype "passive"))
      (node (ref "IC64") (pin "13") (pinfunction "13_13") (pintype "passive"))
      (node (ref "IC65") (pin "13") (pinfunction "13_13") (pintype "passive"))
    )
    (net (code "374") (name "Net-(IC62-Pad14)") (class "Default")
      (node (ref "IC62") (pin "14") (pinfunction "14_14") (pintype "passive"))
      (node (ref "IC63") (pin "14") (pinfunction "14_14") (pintype "passive"))
      (node (ref "IC64") (pin "14") (pinfunction "14_14") (pintype "passive"))
      (node (ref "IC65") (pin "14") (pinfunction "14_14") (pintype "passive"))
    )
    (net (code "375") (name "Net-(IC62-Pad15)") (class "Default")
      (node (ref "IC62") (pin "15") (pinfunction "15_15") (pintype "passive"))
      (node (ref "IC63") (pin "15") (pinfunction "15_15") (pintype "passive"))
      (node (ref "IC64") (pin "15") (pinfunction "15_15") (pintype "passive"))
      (node (ref "IC65") (pin "15") (pinfunction "15_15") (pintype "passive"))
    )
    (net (code "376") (name "Net-(IC62-Pad16)") (class "Default")
      (node (ref "IC62") (pin "16") (pinfunction "16_16") (pintype "passive"))
      (node (ref "IC63") (pin "16") (pinfunction "16_16") (pintype "passive"))
      (node (ref "IC64") (pin "16") (pinfunction "16_16") (pintype "passive"))
      (node (ref "IC65") (pin "16") (pinfunction "16_16") (pintype "passive"))
    )
    (net (code "377") (name "Net-(IC62-Pad17)") (class "Default")
      (node (ref "IC62") (pin "17") (pinfunction "17_17") (pintype "passive"))
      (node (ref "IC63") (pin "17") (pinfunction "17_17") (pintype "passive"))
      (node (ref "IC64") (pin "17") (pinfunction "17_17") (pintype "passive"))
      (node (ref "IC65") (pin "17") (pinfunction "17_17") (pintype "passive"))
    )
    (net (code "378") (name "Net-(IC62-Pad18)") (class "Default")
      (node (ref "IC62") (pin "18") (pinfunction "18_18") (pintype "passive"))
      (node (ref "IC63") (pin "18") (pinfunction "18_18") (pintype "passive"))
      (node (ref "IC64") (pin "18") (pinfunction "18_18") (pintype "passive"))
      (node (ref "IC65") (pin "18") (pinfunction "18_18") (pintype "passive"))
    )
    (net (code "379") (name "Net-(IC62-Pad19)") (class "Default")
      (node (ref "IC62") (pin "19") (pinfunction "19_19") (pintype "passive"))
      (node (ref "IC63") (pin "19") (pinfunction "19_19") (pintype "passive"))
      (node (ref "IC64") (pin "19") (pinfunction "19_19") (pintype "passive"))
      (node (ref "IC65") (pin "19") (pinfunction "19_19") (pintype "passive"))
    )
    (net (code "380") (name "Net-(IC62-Pad20)") (class "Default")
      (node (ref "IC62") (pin "20") (pinfunction "20_20") (pintype "passive"))
      (node (ref "IC63") (pin "20") (pinfunction "20_20") (pintype "passive"))
      (node (ref "IC64") (pin "20") (pinfunction "20_20") (pintype "passive"))
      (node (ref "IC65") (pin "20") (pinfunction "20_20") (pintype "passive"))
    )
    (net (code "381") (name "Net-(IC62-Pad21)") (class "Default")
      (node (ref "IC62") (pin "21") (pinfunction "21_21") (pintype "passive"))
      (node (ref "IC63") (pin "21") (pinfunction "21_21") (pintype "passive"))
      (node (ref "IC64") (pin "21") (pinfunction "21_21") (pintype "passive"))
      (node (ref "IC65") (pin "21") (pinfunction "21_21") (pintype "passive"))
    )
    (net (code "382") (name "Net-(IC62-Pad22)") (class "Default")
      (node (ref "IC62") (pin "22") (pinfunction "22_22") (pintype "passive"))
      (node (ref "IC63") (pin "22") (pinfunction "22_22") (pintype "passive"))
      (node (ref "IC64") (pin "22") (pinfunction "22_22") (pintype "passive"))
      (node (ref "IC65") (pin "22") (pinfunction "22_22") (pintype "passive"))
    )
    (net (code "383") (name "Net-(IC62-Pad23)") (class "Default")
      (node (ref "IC62") (pin "23") (pinfunction "23_23") (pintype "passive"))
      (node (ref "IC63") (pin "23") (pinfunction "23_23") (pintype "passive"))
      (node (ref "IC64") (pin "23") (pinfunction "23_23") (pintype "passive"))
      (node (ref "IC65") (pin "23") (pinfunction "23_23") (pintype "passive"))
    )
    (net (code "384") (name "Net-(IC62-Pad24)") (class "Default")
      (node (ref "IC62") (pin "24") (pinfunction "24_24") (pintype "passive"))
      (node (ref "IC63") (pin "24") (pinfunction "24_24") (pintype "passive"))
      (node (ref "IC64") (pin "24") (pinfunction "24_24") (pintype "passive"))
      (node (ref "IC65") (pin "24") (pinfunction "24_24") (pintype "passive"))
    )
    (net (code "385") (name "Net-(IC66-Pad1)") (class "Default")
      (node (ref "IC66") (pin "1") (pinfunction "1_1") (pintype "passive"))
      (node (ref "IC67") (pin "1") (pinfunction "1_1") (pintype "passive"))
      (node (ref "IC68") (pin "1") (pinfunction "1_1") (pintype "passive"))
      (node (ref "IC69") (pin "1") (pinfunction "1_1") (pintype "passive"))
    )
    (net (code "386") (name "Net-(IC66-Pad2)") (class "Default")
      (node (ref "IC66") (pin "2") (pinfunction "2_2") (pintype "passive"))
      (node (ref "IC67") (pin "2") (pinfunction "2_2") (pintype "passive"))
      (node (ref "IC68") (pin "2") (pinfunction "2_2") (pintype "passive"))
      (node (ref "IC69") (pin "2") (pinfunction "2_2") (pintype "passive"))
    )
    (net (code "387") (name "Net-(IC66-Pad3)") (class "Default")
      (node (ref "IC66") (pin "3") (pinfunction "3_3") (pintype "passive"))
      (node (ref "IC67") (pin "3") (pinfunction "3_3") (pintype "passive"))
      (node (ref "IC68") (pin "3") (pinfunction "3_3") (pintype "passive"))
      (node (ref "IC69") (pin "3") (pinfunction "3_3") (pintype "passive"))
    )
    (net (code "388") (name "Net-(IC66-Pad4)") (class "Default")
      (node (ref "IC66") (pin "4") (pinfunction "4_4") (pintype "passive"))
      (node (ref "IC67") (pin "4") (pinfunction "4_4") (pintype "passive"))
      (node (ref "IC68") (pin "4") (pinfunction "4_4") (pintype "passive"))
      (node (ref "IC69") (pin "4") (pinfunction "4_4") (pintype "passive"))
    )
    (net (code "389") (name "Net-(IC66-Pad5)") (class "Default")
      (node (ref "IC66") (pin "5") (pinfunction "5_5") (pintype "passive"))
      (node (ref "IC67") (pin "5") (pinfunction "5_5") (pintype "passive"))
      (node (ref "IC68") (pin "5") (pinfunction "5_5") (pintype "passive"))
      (node (ref "IC69") (pin "5") (pinfunction "5_5") (pintype "passive"))
    )
    (net (code "390") (name "Net-(IC66-Pad6)") (class "Default")
      (node (ref "IC66") (pin "6") (pinfunction "6_6") (pintype "passive"))
      (node (ref "IC67") (pin "6") (pinfunction "6_6") (pintype "passive"))
      (node (ref "IC68") (pin "6") (pinfunction "6_6") (pintype "passive"))
      (node (ref "IC69") (pin "6") (pinfunction "6_6") (pintype "passive"))
    )
    (net (code "391") (name "Net-(IC66-Pad7)") (class "Default")
      (node (ref "IC66") (pin "7") (pinfunction "7_7") (pintype "passive"))
      (node (ref "IC67") (pin "7") (pinfunction "7_7") (pintype "passive"))
      (node (ref "IC68") (pin "7") (pinfunction "7_7") (pintype "passive"))
      (node (ref "IC69") (pin "7") (pinfunction "7_7") (pintype "passive"))
    )
    (net (code "392") (name "Net-(IC66-Pad8)") (class "Default")
      (node (ref "IC66") (pin "8") (pinfunction "8_8") (pintype "passive"))
      (node (ref "IC67") (pin "8") (pinfunction "8_8") (pintype "passive"))
      (node (ref "IC68") (pin "8") (pinfunction "8_8") (pintype "passive"))
      (node (ref "IC69") (pin "8") (pinfunction "8_8") (pintype "passive"))
    )
    (net (code "393") (name "Net-(IC66-Pad9)") (class "Default")
      (node (ref "IC66") (pin "9") (pinfunction "9_9") (pintype "passive"))
      (node (ref "IC67") (pin "9") (pinfunction "9_9") (pintype "passive"))
      (node (ref "IC68") (pin "9") (pinfunction "9_9") (pintype "passive"))
      (node (ref "IC69") (pin "9") (pinfunction "9_9") (pintype "passive"))
    )
    (net (code "394") (name "Net-(IC66-Pad10)") (class "Default")
      (node (ref "IC66") (pin "10") (pinfunction "10_10") (pintype "passive"))
      (node (ref "IC67") (pin "10") (pinfunction "10_10") (pintype "passive"))
      (node (ref "IC68") (pin "10") (pinfunction "10_10") (pintype "passive"))
      (node (ref "IC69") (pin "10") (pinfunction "10_10") (pintype "passive"))
    )
    (net (code "395") (name "Net-(IC66-Pad11)") (class "Default")
      (node (ref "IC66") (pin "11") (pinfunction "11_11") (pintype "passive"))
      (node (ref "IC67") (pin "11") (pinfunction "11_11") (pintype "passive"))
      (node (ref "IC68") (pin "11") (pinfunction "11_11") (pintype "passive"))
      (node (ref "IC69") (pin "11") (pinfunction "11_11") (pintype "passive"))
    )
    (net (code "396") (name "Net-(IC66-Pad12)") (class "Default")
      (node (ref "IC66") (pin "12") (pinfunction "12_12") (pintype "passive"))
      (node (ref "IC67") (pin "12") (pinfunction "12_12") (pintype "passive"))
      (node (ref "IC68") (pin "12") (pinfunction "12_12") (pintype "passive"))
      (node (ref "IC69") (pin "12") (pinfunction "12_12") (pintype "passive"))
    )
    (net (code "397") (name "Net-(IC66-Pad13)") (class "Default")
      (node (ref "IC66") (pin "13") (pinfunction "13_13") (pintype "passive"))
      (node (ref "IC67") (pin "13") (pinfunction "13_13") (pintype "passive"))
      (node (ref "IC68") (pin "13") (pinfunction "13_13") (pintype "passive"))
      (node (ref "IC69") (pin "13") (pinfunction "13_13") (pintype "passive"))
    )
    (net (code "398") (name "Net-(IC66-Pad14)") (class "Default")
      (node (ref "IC66") (pin "14") (pinfunction "14_14") (pintype "passive"))
      (node (ref "IC67") (pin "14") (pinfunction "14_14") (pintype "passive"))
      (node (ref "IC68") (pin "14") (pinfunction "14_14") (pintype "passive"))
      (node (ref "IC69") (pin "14") (pinfunction "14_14") (pintype "passive"))
    )
    (net (code "399") (name "Net-(IC66-Pad15)") (class "Default")
      (node (ref "IC66") (pin "15") (pinfunction "15_15") (pintype "passive"))
      (node (ref "IC67") (pin "15") (pinfunction "15_15") (pintype "passive"))
      (node (ref "IC68") (pin "15") (pinfunction "15_15") (pintype "passive"))
      (node (ref "IC69") (pin "15") (pinfunction "15_15") (pintype "passive"))
    )
    (net (code "400") (name "Net-(IC66-Pad16)") (class "Default")
      (node (ref "IC66") (pin "16") (pinfunction "16_16") (pintype "passive"))
      (node (ref "IC67") (pin "16") (pinfunction "16_16") (pintype "passive"))
      (node (ref "IC68") (pin "16") (pinfunction "16_16") (pintype "passive"))
      (node (ref "IC69") (pin "16") (pinfunction "16_16") (pintype "passive"))
    )
    (net (code "401") (name "Net-(IC66-Pad17)") (class "Default")
      (node (ref "IC66") (pin "17") (pinfunction "17_17") (pintype "passive"))
      (node (ref "IC67") (pin "17") (pinfunction "17_17") (pintype "passive"))
      (node (ref "IC68") (pin "17") (pinfunction "17_17") (pintype "passive"))
      (node (ref "IC69") (pin "17") (pinfunction "17_17") (pintype "passive"))
    )
    (net (code "402") (name "Net-(IC66-Pad18)") (class "Default")
      (node (ref "IC66") (pin "18") (pinfunction "18_18") (pintype "passive"))
      (node (ref "IC67") (pin "18") (pinfunction "18_18") (pintype "passive"))
      (node (ref "IC68") (pin "18") (pinfunction "18_18") (pintype "passive"))
      (node (ref "IC69") (pin "18") (pinfunction "18_18") (pintype "passive"))
    )
    (net (code "403") (name "Net-(IC66-Pad19)") (class "Default")
      (node (ref "IC66") (pin "19") (pinfunction "19_19") (pintype "passive"))
      (node (ref "IC67") (pin "19") (pinfunction "19_19") (pintype "passive"))
      (node (ref "IC68") (pin "19") (pinfunction "19_19") (pintype "passive"))
      (node (ref "IC69") (pin "19") (pinfunction "19_19") (pintype "passive"))
    )
    (net (code "404") (name "Net-(IC66-Pad20)") (class "Default")
      (node (ref "IC66") (pin "20") (pinfunction "20_20") (pintype "passive"))
      (node (ref "IC67") (pin "20") (pinfunction "20_20") (pintype "passive"))
      (node (ref "IC68") (pin "20") (pinfunction "20_20") (pintype "passive"))
      (node (ref "IC69") (pin "20") (pinfunction "20_20") (pintype "passive"))
    )
    (net (code "405") (name "Net-(IC66-Pad21)") (class "Default")
      (node (ref "IC66") (pin "21") (pinfunction "21_21") (pintype "passive"))
      (node (ref "IC67") (pin "21") (pinfunction "21_21") (pintype "passive"))
      (node (ref "IC68") (pin "21") (pinfunction "21_21") (pintype "passive"))
      (node (ref "IC69") (pin "21") (pinfunction "21_21") (pintype "passive"))
    )
    (net (code "406") (name "Net-(IC66-Pad22)") (class "Default")
      (node (ref "IC66") (pin "22") (pinfunction "22_22") (pintype "passive"))
      (node (ref "IC67") (pin "22") (pinfunction "22_22") (pintype "passive"))
      (node (ref "IC68") (pin "22") (pinfunction "22_22") (pintype "passive"))
      (node (ref "IC69") (pin "22") (pinfunction "22_22") (pintype "passive"))
    )
    (net (code "407") (name "Net-(IC66-Pad23)") (class "Default")
      (node (ref "IC66") (pin "23") (pinfunction "23_23") (pintype "passive"))
      (node (ref "IC67") (pin "23") (pinfunction "23_23") (pintype "passive"))
      (node (ref "IC68") (pin "23") (pinfunction "23_23") (pintype "passive"))
      (node (ref "IC69") (pin "23") (pinfunction "23_23") (pintype "passive"))
    )
    (net (code "408") (name "Net-(IC66-Pad24)") (class "Default")
      (node (ref "IC66") (pin "24") (pinfunction "24_24") (pintype "passive"))
      (node (ref "IC67") (pin "24") (pinfunction "24_24") (pintype "passive"))
      (node (ref "IC68") (pin "24") (pinfunction "24_24") (pintype "passive"))
      (node (ref "IC69") (pin "24") (pinfunction "24_24") (pintype "passive"))
    )
    (net (code "409") (name "Net-(IC70-Pad1)") (class "Default")
      (node (ref "IC70") (pin "1") (pinfunction "1_1") (pintype "passive"))
      (node (ref "IC71") (pin "1") (pinfunction "1_1") (pintype "passive"))
      (node (ref "IC72") (pin "1") (pinfunction "1_1") (pintype "passive"))
      (node (ref "IC73") (pin "1") (pinfunction "1_1") (pintype "passive"))
    )
    (net (code "410") (name "Net-(IC70-Pad2)") (class "Default")
      (node (ref "IC70") (pin "2") (pinfunction "2_2") (pintype "passive"))
      (node (ref "IC71") (pin "2") (pinfunction "2_2") (pintype "passive"))
      (node (ref "IC72") (pin "2") (pinfunction "2_2") (pintype "passive"))
      (node (ref "IC73") (pin "2") (pinfunction "2_2") (pintype "passive"))
    )
    (net (code "411") (name "Net-(IC70-Pad3)") (class "Default")
      (node (ref "IC70") (pin "3") (pinfunction "3_3") (pintype "passive"))
      (node (ref "IC71") (pin "3") (pinfunction "3_3") (pintype "passive"))
      (node (ref "IC72") (pin "3") (pinfunction "3_3") (pintype "passive"))
      (node (ref "IC73") (pin "3") (pinfunction "3_3") (pintype "passive"))
    )
    (net (code "412") (name "Net-(IC70-Pad4)") (class "Default")
      (node (ref "IC70") (pin "4") (pinfunction "4_4") (pintype "passive"))
      (node (ref "IC71") (pin "4") (pinfunction "4_4") (pintype "passive"))
      (node (ref "IC72") (pin "4") (pinfunction "4_4") (pintype "passive"))
      (node (ref "IC73") (pin "4") (pinfunction "4_4") (pintype "passive"))
    )
    (net (code "413") (name "Net-(IC70-Pad5)") (class "Default")
      (node (ref "IC70") (pin "5") (pinfunction "5_5") (pintype "passive"))
      (node (ref "IC71") (pin "5") (pinfunction "5_5") (pintype "passive"))
      (node (ref "IC72") (pin "5") (pinfunction "5_5") (pintype "passive"))
      (node (ref "IC73") (pin "5") (pinfunction "5_5") (pintype "passive"))
    )
    (net (code "414") (name "Net-(IC70-Pad6)") (class "Default")
      (node (ref "IC70") (pin "6") (pinfunction "6_6") (pintype "passive"))
      (node (ref "IC71") (pin "6") (pinfunction "6_6") (pintype "passive"))
      (node (ref "IC72") (pin "6") (pinfunction "6_6") (pintype "passive"))
      (node (ref "IC73") (pin "6") (pinfunction "6_6") (pintype "passive"))
    )
    (net (code "415") (name "Net-(IC70-Pad7)") (class "Default")
      (node (ref "IC70") (pin "7") (pinfunction "7_7") (pintype "passive"))
      (node (ref "IC71") (pin "7") (pinfunction "7_7") (pintype "passive"))
      (node (ref "IC72") (pin "7") (pinfunction "7_7") (pintype "passive"))
      (node (ref "IC73") (pin "7") (pinfunction "7_7") (pintype "passive"))
    )
    (net (code "416") (name "Net-(IC70-Pad8)") (class "Default")
      (node (ref "IC70") (pin "8") (pinfunction "8_8") (pintype "passive"))
      (node (ref "IC71") (pin "8") (pinfunction "8_8") (pintype "passive"))
      (node (ref "IC72") (pin "8") (pinfunction "8_8") (pintype "passive"))
      (node (ref "IC73") (pin "8") (pinfunction "8_8") (pintype "passive"))
    )
    (net (code "417") (name "Net-(IC70-Pad9)") (class "Default")
      (node (ref "IC70") (pin "9") (pinfunction "9_9") (pintype "passive"))
      (node (ref "IC71") (pin "9") (pinfunction "9_9") (pintype "passive"))
      (node (ref "IC72") (pin "9") (pinfunction "9_9") (pintype "passive"))
      (node (ref "IC73") (pin "9") (pinfunction "9_9") (pintype "passive"))
    )
    (net (code "418") (name "Net-(IC70-Pad10)") (class "Default")
      (node (ref "IC70") (pin "10") (pinfunction "10_10") (pintype "passive"))
      (node (ref "IC71") (pin "10") (pinfunction "10_10") (pintype "passive"))
      (node (ref "IC72") (pin "10") (pinfunction "10_10") (pintype "passive"))
      (node (ref "IC73") (pin "10") (pinfunction "10_10") (pintype "passive"))
    )
    (net (code "419") (name "Net-(IC70-Pad11)") (class "Default")
      (node (ref "IC70") (pin "11") (pinfunction "11_11") (pintype "passive"))
      (node (ref "IC71") (pin "11") (pinfunction "11_11") (pintype "passive"))
      (node (ref "IC72") (pin "11") (pinfunction "11_11") (pintype "passive"))
      (node (ref "IC73") (pin "11") (pinfunction "11_11") (pintype "passive"))
    )
    (net (code "420") (name "Net-(IC70-Pad12)") (class "Default")
      (node (ref "IC70") (pin "12") (pinfunction "12_12") (pintype "passive"))
      (node (ref "IC71") (pin "12") (pinfunction "12_12") (pintype "passive"))
      (node (ref "IC72") (pin "12") (pinfunction "12_12") (pintype "passive"))
      (node (ref "IC73") (pin "12") (pinfunction "12_12") (pintype "passive"))
    )
    (net (code "421") (name "Net-(IC70-Pad13)") (class "Default")
      (node (ref "IC70") (pin "13") (pinfunction "13_13") (pintype "passive"))
      (node (ref "IC71") (pin "13") (pinfunction "13_13") (pintype "passive"))
      (node (ref "IC72") (pin "13") (pinfunction "13_13") (pintype "passive"))
      (node (ref "IC73") (pin "13") (pinfunction "13_13") (pintype "passive"))
    )
    (net (code "422") (name "Net-(IC70-Pad14)") (class "Default")
      (node (ref "IC70") (pin "14") (pinfunction "14_14") (pintype "passive"))
      (node (ref "IC71") (pin "14") (pinfunction "14_14") (pintype "passive"))
      (node (ref "IC72") (pin "14") (pinfunction "14_14") (pintype "passive"))
      (node (ref "IC73") (pin "14") (pinfunction "14_14") (pintype "passive"))
    )
    (net (code "423") (name "Net-(IC70-Pad15)") (class "Default")
      (node (ref "IC70") (pin "15") (pinfunction "15_15") (pintype "passive"))
      (node (ref "IC71") (pin "15") (pinfunction "15_15") (pintype "passive"))
      (node (ref "IC72") (pin "15") (pinfunction "15_15") (pintype "passive"))
      (node (ref "IC73") (pin "15") (pinfunction "15_15") (pintype "passive"))
    )
    (net (code "424") (name "Net-(IC70-Pad16)") (class "Default")
      (node (ref "IC70") (pin "16") (pinfunction "16_16") (pintype "passive"))
      (node (ref "IC71") (pin "16") (pinfunction "16_16") (pintype "passive"))
      (node (ref "IC72") (pin "16") (pinfunction "16_16") (pintype "passive"))
      (node (ref "IC73") (pin "16") (pinfunction "16_16") (pintype "passive"))
    )
    (net (code "425") (name "Net-(IC70-Pad17)") (class "Default")
      (node (ref "IC70") (pin "17") (pinfunction "17_17") (pintype "passive"))
      (node (ref "IC71") (pin "17") (pinfunction "17_17") (pintype "passive"))
      (node (ref "IC72") (pin "17") (pinfunction "17_17") (pintype "passive"))
      (node (ref "IC73") (pin "17") (pinfunction "17_17") (pintype "passive"))
    )
    (net (code "426") (name "Net-(IC70-Pad18)") (class "Default")
      (node (ref "IC70") (pin "18") (pinfunction "18_18") (pintype "passive"))
      (node (ref "IC71") (pin "18") (pinfunction "18_18") (pintype "passive"))
      (node (ref "IC72") (pin "18") (pinfunction "18_18") (pintype "passive"))
      (node (ref "IC73") (pin "18") (pinfunction "18_18") (pintype "passive"))
    )
    (net (code "427") (name "Net-(IC70-Pad19)") (class "Default")
      (node (ref "IC70") (pin "19") (pinfunction "19_19") (pintype "passive"))
      (node (ref "IC71") (pin "19") (pinfunction "19_19") (pintype "passive"))
      (node (ref "IC72") (pin "19") (pinfunction "19_19") (pintype "passive"))
      (node (ref "IC73") (pin "19") (pinfunction "19_19") (pintype "passive"))
    )
    (net (code "428") (name "Net-(IC70-Pad20)") (class "Default")
      (node (ref "IC70") (pin "20") (pinfunction "20_20") (pintype "passive"))
      (node (ref "IC71") (pin "20") (pinfunction "20_20") (pintype "passive"))
      (node (ref "IC72") (pin "20") (pinfunction "20_20") (pintype "passive"))
      (node (ref "IC73") (pin "20") (pinfunction "20_20") (pintype "passive"))
    )
    (net (code "429") (name "Net-(IC70-Pad21)") (class "Default")
      (node (ref "IC70") (pin "21") (pinfunction "21_21") (pintype "passive"))
      (node (ref "IC71") (pin "21") (pinfunction "21_21") (pintype "passive"))
      (node (ref "IC72") (pin "21") (pinfunction "21_21") (pintype "passive"))
      (node (ref "IC73") (pin "21") (pinfunction "21_21") (pintype "passive"))
    )
    (net (code "430") (name "Net-(IC70-Pad22)") (class "Default")
      (node (ref "IC70") (pin "22") (pinfunction "22_22") (pintype "passive"))
      (node (ref "IC71") (pin "22") (pinfunction "22_22") (pintype "passive"))
      (node (ref "IC72") (pin "22") (pinfunction "22_22") (pintype "passive"))
      (node (ref "IC73") (pin "22") (pinfunction "22_22") (pintype "passive"))
    )
    (net (code "431") (name "Net-(IC70-Pad23)") (class "Default")
      (node (ref "IC70") (pin "23") (pinfunction "23_23") (pintype "passive"))
      (node (ref "IC71") (pin "23") (pinfunction "23_23") (pintype "passive"))
      (node (ref "IC72") (pin "23") (pinfunction "23_23") (pintype "passive"))
      (node (ref "IC73") (pin "23") (pinfunction "23_23") (pintype "passive"))
    )
    (net (code "432") (name "Net-(IC70-Pad24)") (class "Default")
      (node (ref "IC70") (pin "24") (pinfunction "24_24") (pintype "passive"))
      (node (ref "IC71") (pin "24") (pinfunction "24_24") (pintype "passive"))
      (node (ref "IC72") (pin "24") (pinfunction "24_24") (pintype "passive"))
      (node (ref "IC73") (pin "24") (pinfunction "24_24") (pintype "passive"))
    )
    (net (code "433") (name "Net-(IC74-Pad1)") (class "Default")
      (node (ref "IC74") (pin "1") (pinfunction "1_1") (pintype "passive"))
      (node (ref "IC75") (pin "1") (pinfunction "1_1") (pintype "passive"))
      (node (ref "IC76") (pin "1") (pinfunction "1_1") (pintype "passive"))
      (node (ref "IC77") (pin "1") (pinfunction "1_1") (pintype "passive"))
    )
    (net (code "434") (name "Net-(IC74-Pad2)") (class "Default")
      (node (ref "IC74") (pin "2") (pinfunction "2_2") (pintype "passive"))
      (node (ref "IC75") (pin "2") (pinfunction "2_2") (pintype "passive"))
      (node (ref "IC76") (pin "2") (pinfunction "2_2") (pintype "passive"))
      (node (ref "IC77") (pin "2") (pinfunction "2_2") (pintype "passive"))
    )
    (net (code "435") (name "Net-(IC74-Pad3)") (class "Default")
      (node (ref "IC74") (pin "3") (pinfunction "3_3") (pintype "passive"))
      (node (ref "IC75") (pin "3") (pinfunction "3_3") (pintype "passive"))
      (node (ref "IC76") (pin "3") (pinfunction "3_3") (pintype "passive"))
      (node (ref "IC77") (pin "3") (pinfunction "3_3") (pintype "passive"))
    )
    (net (code "436") (name "Net-(IC74-Pad4)") (class "Default")
      (node (ref "IC74") (pin "4") (pinfunction "4_4") (pintype "passive"))
      (node (ref "IC75") (pin "4") (pinfunction "4_4") (pintype "passive"))
      (node (ref "IC76") (pin "4") (pinfunction "4_4") (pintype "passive"))
      (node (ref "IC77") (pin "4") (pinfunction "4_4") (pintype "passive"))
    )
    (net (code "437") (name "Net-(IC74-Pad5)") (class "Default")
      (node (ref "IC74") (pin "5") (pinfunction "5_5") (pintype "passive"))
      (node (ref "IC75") (pin "5") (pinfunction "5_5") (pintype "passive"))
      (node (ref "IC76") (pin "5") (pinfunction "5_5") (pintype "passive"))
      (node (ref "IC77") (pin "5") (pinfunction "5_5") (pintype "passive"))
    )
    (net (code "438") (name "Net-(IC74-Pad6)") (class "Default")
      (node (ref "IC74") (pin "6") (pinfunction "6_6") (pintype "passive"))
      (node (ref "IC75") (pin "6") (pinfunction "6_6") (pintype "passive"))
      (node (ref "IC76") (pin "6") (pinfunction "6_6") (pintype "passive"))
      (node (ref "IC77") (pin "6") (pinfunction "6_6") (pintype "passive"))
    )
    (net (code "439") (name "Net-(IC74-Pad7)") (class "Default")
      (node (ref "IC74") (pin "7") (pinfunction "7_7") (pintype "passive"))
      (node (ref "IC75") (pin "7") (pinfunction "7_7") (pintype "passive"))
      (node (ref "IC76") (pin "7") (pinfunction "7_7") (pintype "passive"))
      (node (ref "IC77") (pin "7") (pinfunction "7_7") (pintype "passive"))
    )
    (net (code "440") (name "Net-(IC74-Pad8)") (class "Default")
      (node (ref "IC74") (pin "8") (pinfunction "8_8") (pintype "passive"))
      (node (ref "IC75") (pin "8") (pinfunction "8_8") (pintype "passive"))
      (node (ref "IC76") (pin "8") (pinfunction "8_8") (pintype "passive"))
      (node (ref "IC77") (pin "8") (pinfunction "8_8") (pintype "passive"))
    )
    (net (code "441") (name "Net-(IC74-Pad9)") (class "Default")
      (node (ref "IC74") (pin "9") (pinfunction "9_9") (pintype "passive"))
      (node (ref "IC75") (pin "9") (pinfunction "9_9") (pintype "passive"))
      (node (ref "IC76") (pin "9") (pinfunction "9_9") (pintype "passive"))
      (node (ref "IC77") (pin "9") (pinfunction "9_9") (pintype "passive"))
    )
    (net (code "442") (name "Net-(IC74-Pad10)") (class "Default")
      (node (ref "IC74") (pin "10") (pinfunction "10_10") (pintype "passive"))
      (node (ref "IC75") (pin "10") (pinfunction "10_10") (pintype "passive"))
      (node (ref "IC76") (pin "10") (pinfunction "10_10") (pintype "passive"))
      (node (ref "IC77") (pin "10") (pinfunction "10_10") (pintype "passive"))
    )
    (net (code "443") (name "Net-(IC74-Pad11)") (class "Default")
      (node (ref "IC74") (pin "11") (pinfunction "11_11") (pintype "passive"))
      (node (ref "IC75") (pin "11") (pinfunction "11_11") (pintype "passive"))
      (node (ref "IC76") (pin "11") (pinfunction "11_11") (pintype "passive"))
      (node (ref "IC77") (pin "11") (pinfunction "11_11") (pintype "passive"))
    )
    (net (code "444") (name "Net-(IC74-Pad12)") (class "Default")
      (node (ref "IC74") (pin "12") (pinfunction "12_12") (pintype "passive"))
      (node (ref "IC75") (pin "12") (pinfunction "12_12") (pintype "passive"))
      (node (ref "IC76") (pin "12") (pinfunction "12_12") (pintype "passive"))
      (node (ref "IC77") (pin "12") (pinfunction "12_12") (pintype "passive"))
    )
    (net (code "445") (name "Net-(IC74-Pad13)") (class "Default")
      (node (ref "IC74") (pin "13") (pinfunction "13_13") (pintype "passive"))
      (node (ref "IC75") (pin "13") (pinfunction "13_13") (pintype "passive"))
      (node (ref "IC76") (pin "13") (pinfunction "13_13") (pintype "passive"))
      (node (ref "IC77") (pin "13") (pinfunction "13_13") (pintype "passive"))
    )
    (net (code "446") (name "Net-(IC74-Pad14)") (class "Default")
      (node (ref "IC74") (pin "14") (pinfunction "14_14") (pintype "passive"))
      (node (ref "IC75") (pin "14") (pinfunction "14_14") (pintype "passive"))
      (node (ref "IC76") (pin "14") (pinfunction "14_14") (pintype "passive"))
      (node (ref "IC77") (pin "14") (pinfunction "14_14") (pintype "passive"))
    )
    (net (code "447") (name "Net-(IC74-Pad15)") (class "Default")
      (node (ref "IC74") (pin "15") (pinfunction "15_15") (pintype "passive"))
      (node (ref "IC75") (pin "15") (pinfunction "15_15") (pintype "passive"))
      (node (ref "IC76") (pin "15") (pinfunction "15_15") (pintype "passive"))
      (node (ref "IC77") (pin "15") (pinfunction "15_15") (pintype "passive"))
    )
    (net (code "448") (name "Net-(IC74-Pad16)") (class "Default")
      (node (ref "IC74") (pin "16") (pinfunction "16_16") (pintype "passive"))
      (node (ref "IC75") (pin "16") (pinfunction "16_16") (pintype "passive"))
      (node (ref "IC76") (pin "16") (pinfunction "16_16") (pintype "passive"))
      (node (ref "IC77") (pin "16") (pinfunction "16_16") (pintype "passive"))
    )
    (net (code "449") (name "Net-(IC74-Pad17)") (class "Default")
      (node (ref "IC74") (pin "17") (pinfunction "17_17") (pintype "passive"))
      (node (ref "IC75") (pin "17") (pinfunction "17_17") (pintype "passive"))
      (node (ref "IC76") (pin "17") (pinfunction "17_17") (pintype "passive"))
      (node (ref "IC77") (pin "17") (pinfunction "17_17") (pintype "passive"))
    )
    (net (code "450") (name "Net-(IC74-Pad18)") (class "Default")
      (node (ref "IC74") (pin "18") (pinfunction "18_18") (pintype "passive"))
      (node (ref "IC75") (pin "18") (pinfunction "18_18") (pintype "passive"))
      (node (ref "IC76") (pin "18") (pinfunction "18_18") (pintype "passive"))
      (node (ref "IC77") (pin "18") (pinfunction "18_18") (pintype "passive"))
    )
    (net (code "451") (name "Net-(IC74-Pad19)") (class "Default")
      (node (ref "IC74") (pin "19") (pinfunction "19_19") (pintype "passive"))
      (node (ref "IC75") (pin "19") (pinfunction "19_19") (pintype "passive"))
      (node (ref "IC76") (pin "19") (pinfunction "19_19") (pintype "passive"))
      (node (ref "IC77") (pin "19") (pinfunction "19_19") (pintype "passive"))
    )
    (net (code "452") (name "Net-(IC74-Pad20)") (class "Default")
      (node (ref "IC74") (pin "20") (pinfunction "20_20") (pintype "passive"))
      (node (ref "IC75") (pin "20") (pinfunction "20_20") (pintype "passive"))
      (node (ref "IC76") (pin "20") (pinfunction "20_20") (pintype "passive"))
      (node (ref "IC77") (pin "20") (pinfunction "20_20") (pintype "passive"))
    )
    (net (code "453") (name "Net-(IC74-Pad21)") (class "Default")
      (node (ref "IC74") (pin "21") (pinfunction "21_21") (pintype "passive"))
      (node (ref "IC75") (pin "21") (pinfunction "21_21") (pintype "passive"))
      (node (ref "IC76") (pin "21") (pinfunction "21_21") (pintype "passive"))
      (node (ref "IC77") (pin "21") (pinfunction "21_21") (pintype "passive"))
    )
    (net (code "454") (name "Net-(IC74-Pad22)") (class "Default")
      (node (ref "IC74") (pin "22") (pinfunction "22_22") (pintype "passive"))
      (node (ref "IC75") (pin "22") (pinfunction "22_22") (pintype "passive"))
      (node (ref "IC76") (pin "22") (pinfunction "22_22") (pintype "passive"))
      (node (ref "IC77") (pin "22") (pinfunction "22_22") (pintype "passive"))
    )
    (net (code "455") (name "Net-(IC74-Pad23)") (class "Default")
      (node (ref "IC74") (pin "23") (pinfunction "23_23") (pintype "passive"))
      (node (ref "IC75") (pin "23") (pinfunction "23_23") (pintype "passive"))
      (node (ref "IC76") (pin "23") (pinfunction "23_23") (pintype "passive"))
      (node (ref "IC77") (pin "23") (pinfunction "23_23") (pintype "passive"))
    )
    (net (code "456") (name "Net-(IC74-Pad24)") (class "Default")
      (node (ref "IC74") (pin "24") (pinfunction "24_24") (pintype "passive"))
      (node (ref "IC75") (pin "24") (pinfunction "24_24") (pintype "passive"))
      (node (ref "IC76") (pin "24") (pinfunction "24_24") (pintype "passive"))
      (node (ref "IC77") (pin "24") (pinfunction "24_24") (pintype "passive"))
    )
    (net (code "457") (name "Net-(IC78-Pad1)") (class "Default")
      (node (ref "IC78") (pin "1") (pinfunction "1_1") (pintype "passive"))
      (node (ref "IC79") (pin "1") (pinfunction "1_1") (pintype "passive"))
      (node (ref "IC80") (pin "1") (pinfunction "1_1") (pintype "passive"))
      (node (ref "IC81") (pin "1") (pinfunction "1_1") (pintype "passive"))
    )
    (net (code "458") (name "Net-(IC78-Pad2)") (class "Default")
      (node (ref "IC78") (pin "2") (pinfunction "2_2") (pintype "passive"))
      (node (ref "IC79") (pin "2") (pinfunction "2_2") (pintype "passive"))
      (node (ref "IC80") (pin "2") (pinfunction "2_2") (pintype "passive"))
      (node (ref "IC81") (pin "2") (pinfunction "2_2") (pintype "passive"))
    )
    (net (code "459") (name "Net-(IC78-Pad3)") (class "Default")
      (node (ref "IC78") (pin "3") (pinfunction "3_3") (pintype "passive"))
      (node (ref "IC79") (pin "3") (pinfunction "3_3") (pintype "passive"))
      (node (ref "IC80") (pin "3") (pinfunction "3_3") (pintype "passive"))
      (node (ref "IC81") (pin "3") (pinfunction "3_3") (pintype "passive"))
    )
    (net (code "460") (name "Net-(IC78-Pad4)") (class "Default")
      (node (ref "IC78") (pin "4") (pinfunction "4_4") (pintype "passive"))
      (node (ref "IC79") (pin "4") (pinfunction "4_4") (pintype "passive"))
      (node (ref "IC80") (pin "4") (pinfunction "4_4") (pintype "passive"))
      (node (ref "IC81") (pin "4") (pinfunction "4_4") (pintype "passive"))
    )
    (net (code "461") (name "Net-(IC78-Pad5)") (class "Default")
      (node (ref "IC78") (pin "5") (pinfunction "5_5") (pintype "passive"))
      (node (ref "IC79") (pin "5") (pinfunction "5_5") (pintype "passive"))
      (node (ref "IC80") (pin "5") (pinfunction "5_5") (pintype "passive"))
      (node (ref "IC81") (pin "5") (pinfunction "5_5") (pintype "passive"))
    )
    (net (code "462") (name "Net-(IC78-Pad6)") (class "Default")
      (node (ref "IC78") (pin "6") (pinfunction "6_6") (pintype "passive"))
      (node (ref "IC79") (pin "6") (pinfunction "6_6") (pintype "passive"))
      (node (ref "IC80") (pin "6") (pinfunction "6_6") (pintype "passive"))
      (node (ref "IC81") (pin "6") (pinfunction "6_6") (pintype "passive"))
    )
    (net (code "463") (name "Net-(IC78-Pad7)") (class "Default")
      (node (ref "IC78") (pin "7") (pinfunction "7_7") (pintype "passive"))
      (node (ref "IC79") (pin "7") (pinfunction "7_7") (pintype "passive"))
      (node (ref "IC80") (pin "7") (pinfunction "7_7") (pintype "passive"))
      (node (ref "IC81") (pin "7") (pinfunction "7_7") (pintype "passive"))
    )
    (net (code "464") (name "Net-(IC78-Pad8)") (class "Default")
      (node (ref "IC78") (pin "8") (pinfunction "8_8") (pintype "passive"))
      (node (ref "IC79") (pin "8") (pinfunction "8_8") (pintype "passive"))
      (node (ref "IC80") (pin "8") (pinfunction "8_8") (pintype "passive"))
      (node (ref "IC81") (pin "8") (pinfunction "8_8") (pintype "passive"))
    )
    (net (code "465") (name "Net-(IC78-Pad9)") (class "Default")
      (node (ref "IC78") (pin "9") (pinfunction "9_9") (pintype "passive"))
      (node (ref "IC79") (pin "9") (pinfunction "9_9") (pintype "passive"))
      (node (ref "IC80") (pin "9") (pinfunction "9_9") (pintype "passive"))
      (node (ref "IC81") (pin "9") (pinfunction "9_9") (pintype "passive"))
    )
    (net (code "466") (name "Net-(IC78-Pad10)") (class "Default")
      (node (ref "IC78") (pin "10") (pinfunction "10_10") (pintype "passive"))
      (node (ref "IC79") (pin "10") (pinfunction "10_10") (pintype "passive"))
      (node (ref "IC80") (pin "10") (pinfunction "10_10") (pintype "passive"))
      (node (ref "IC81") (pin "10") (pinfunction "10_10") (pintype "passive"))
    )
    (net (code "467") (name "Net-(IC78-Pad11)") (class "Default")
      (node (ref "IC78") (pin "11") (pinfunction "11_11") (pintype "passive"))
      (node (ref "IC79") (pin "11") (pinfunction "11_11") (pintype "passive"))
      (node (ref "IC80") (pin "11") (pinfunction "11_11") (pintype "passive"))
      (node (ref "IC81") (pin "11") (pinfunction "11_11") (pintype "passive"))
    )
    (net (code "468") (name "Net-(IC78-Pad12)") (class "Default")
      (node (ref "IC78") (pin "12") (pinfunction "12_12") (pintype "passive"))
      (node (ref "IC79") (pin "12") (pinfunction "12_12") (pintype "passive"))
      (node (ref "IC80") (pin "12") (pinfunction "12_12") (pintype "passive"))
      (node (ref "IC81") (pin "12") (pinfunction "12_12") (pintype "passive"))
    )
    (net (code "469") (name "Net-(IC78-Pad13)") (class "Default")
      (node (ref "IC78") (pin "13") (pinfunction "13_13") (pintype "passive"))
      (node (ref "IC79") (pin "13") (pinfunction "13_13") (pintype "passive"))
      (node (ref "IC80") (pin "13") (pinfunction "13_13") (pintype "passive"))
      (node (ref "IC81") (pin "13") (pinfunction "13_13") (pintype "passive"))
    )
    (net (code "470") (name "Net-(IC78-Pad14)") (class "Default")
      (node (ref "IC78") (pin "14") (pinfunction "14_14") (pintype "passive"))
      (node (ref "IC79") (pin "14") (pinfunction "14_14") (pintype "passive"))
      (node (ref "IC80") (pin "14") (pinfunction "14_14") (pintype "passive"))
      (node (ref "IC81") (pin "14") (pinfunction "14_14") (pintype "passive"))
    )
    (net (code "471") (name "Net-(IC78-Pad15)") (class "Default")
      (node (ref "IC78") (pin "15") (pinfunction "15_15") (pintype "passive"))
      (node (ref "IC79") (pin "15") (pinfunction "15_15") (pintype "passive"))
      (node (ref "IC80") (pin "15") (pinfunction "15_15") (pintype "passive"))
      (node (ref "IC81") (pin "15") (pinfunction "15_15") (pintype "passive"))
    )
    (net (code "472") (name "Net-(IC78-Pad16)") (class "Default")
      (node (ref "IC78") (pin "16") (pinfunction "16_16") (pintype "passive"))
      (node (ref "IC79") (pin "16") (pinfunction "16_16") (pintype "passive"))
      (node (ref "IC80") (pin "16") (pinfunction "16_16") (pintype "passive"))
      (node (ref "IC81") (pin "16") (pinfunction "16_16") (pintype "passive"))
    )
    (net (code "473") (name "Net-(IC78-Pad17)") (class "Default")
      (node (ref "IC78") (pin "17") (pinfunction "17_17") (pintype "passive"))
      (node (ref "IC79") (pin "17") (pinfunction "17_17") (pintype "passive"))
      (node (ref "IC80") (pin "17") (pinfunction "17_17") (pintype "passive"))
      (node (ref "IC81") (pin "17") (pinfunction "17_17") (pintype "passive"))
    )
    (net (code "474") (name "Net-(IC78-Pad18)") (class "Default")
      (node (ref "IC78") (pin "18") (pinfunction "18_18") (pintype "passive"))
      (node (ref "IC79") (pin "18") (pinfunction "18_18") (pintype "passive"))
      (node (ref "IC80") (pin "18") (pinfunction "18_18") (pintype "passive"))
      (node (ref "IC81") (pin "18") (pinfunction "18_18") (pintype "passive"))
    )
    (net (code "475") (name "Net-(IC78-Pad19)") (class "Default")
      (node (ref "IC78") (pin "19") (pinfunction "19_19") (pintype "passive"))
      (node (ref "IC79") (pin "19") (pinfunction "19_19") (pintype "passive"))
      (node (ref "IC80") (pin "19") (pinfunction "19_19") (pintype "passive"))
      (node (ref "IC81") (pin "19") (pinfunction "19_19") (pintype "passive"))
    )
    (net (code "476") (name "Net-(IC78-Pad20)") (class "Default")
      (node (ref "IC78") (pin "20") (pinfunction "20_20") (pintype "passive"))
      (node (ref "IC79") (pin "20") (pinfunction "20_20") (pintype "passive"))
      (node (ref "IC80") (pin "20") (pinfunction "20_20") (pintype "passive"))
      (node (ref "IC81") (pin "20") (pinfunction "20_20") (pintype "passive"))
    )
    (net (code "477") (name "Net-(IC78-Pad21)") (class "Default")
      (node (ref "IC78") (pin "21") (pinfunction "21_21") (pintype "passive"))
      (node (ref "IC79") (pin "21") (pinfunction "21_21") (pintype "passive"))
      (node (ref "IC80") (pin "21") (pinfunction "21_21") (pintype "passive"))
      (node (ref "IC81") (pin "21") (pinfunction "21_21") (pintype "passive"))
    )
    (net (code "478") (name "Net-(IC78-Pad22)") (class "Default")
      (node (ref "IC78") (pin "22") (pinfunction "22_22") (pintype "passive"))
      (node (ref "IC79") (pin "22") (pinfunction "22_22") (pintype "passive"))
      (node (ref "IC80") (pin "22") (pinfunction "22_22") (pintype "passive"))
      (node (ref "IC81") (pin "22") (pinfunction "22_22") (pintype "passive"))
    )
    (net (code "479") (name "Net-(IC78-Pad23)") (class "Default")
      (node (ref "IC78") (pin "23") (pinfunction "23_23") (pintype "passive"))
      (node (ref "IC79") (pin "23") (pinfunction "23_23") (pintype "passive"))
      (node (ref "IC80") (pin "23") (pinfunction "23_23") (pintype "passive"))
      (node (ref "IC81") (pin "23") (pinfunction "23_23") (pintype "passive"))
    )
    (net (code "480") (name "Net-(IC78-Pad24)") (class "Default")
      (node (ref "IC78") (pin "24") (pinfunction "24_24") (pintype "passive"))
      (node (ref "IC79") (pin "24") (pinfunction "24_24") (pintype "passive"))
      (node (ref "IC80") (pin "24") (pinfunction "24_24") (pintype "passive"))
      (node (ref "IC81") (pin "24") (pinfunction "24_24") (pintype "passive"))
    )
    (net (code "481") (name "Net-(IC82-Pad1)") (class "Default")
      (node (ref "IC82") (pin "1") (pinfunction "1_1") (pintype "passive"))
      (node (ref "IC83") (pin "1") (pinfunction "1_1") (pintype "passive"))
      (node (ref "IC84") (pin "1") (pinfunction "1_1") (pintype "passive"))
      (node (ref "IC85") (pin "1") (pinfunction "1_1") (pintype "passive"))
    )
    (net (code "482") (name "Net-(IC82-Pad2)") (class "Default")
      (node (ref "IC82") (pin "2") (pinfunction "2_2") (pintype "passive"))
      (node (ref "IC83") (pin "2") (pinfunction "2_2") (pintype "passive"))
      (node (ref "IC84") (pin "2") (pinfunction "2_2") (pintype "passive"))
      (node (ref "IC85") (pin "2") (pinfunction "2_2") (pintype "passive"))
    )
    (net (code "483") (name "Net-(IC82-Pad3)") (class "Default")
      (node (ref "IC82") (pin "3") (pinfunction "3_3") (pintype "passive"))
      (node (ref "IC83") (pin "3") (pinfunction "3_3") (pintype "passive"))
      (node (ref "IC84") (pin "3") (pinfunction "3_3") (pintype "passive"))
      (node (ref "IC85") (pin "3") (pinfunction "3_3") (pintype "passive"))
    )
    (net (code "484") (name "Net-(IC82-Pad4)") (class "Default")
      (node (ref "IC82") (pin "4") (pinfunction "4_4") (pintype "passive"))
      (node (ref "IC83") (pin "4") (pinfunction "4_4") (pintype "passive"))
      (node (ref "IC84") (pin "4") (pinfunction "4_4") (pintype "passive"))
      (node (ref "IC85") (pin "4") (pinfunction "4_4") (pintype "passive"))
    )
    (net (code "485") (name "Net-(IC82-Pad5)") (class "Default")
      (node (ref "IC82") (pin "5") (pinfunction "5_5") (pintype "passive"))
      (node (ref "IC83") (pin "5") (pinfunction "5_5") (pintype "passive"))
      (node (ref "IC84") (pin "5") (pinfunction "5_5") (pintype "passive"))
      (node (ref "IC85") (pin "5") (pinfunction "5_5") (pintype "passive"))
    )
    (net (code "486") (name "Net-(IC82-Pad6)") (class "Default")
      (node (ref "IC82") (pin "6") (pinfunction "6_6") (pintype "passive"))
      (node (ref "IC83") (pin "6") (pinfunction "6_6") (pintype "passive"))
      (node (ref "IC84") (pin "6") (pinfunction "6_6") (pintype "passive"))
      (node (ref "IC85") (pin "6") (pinfunction "6_6") (pintype "passive"))
    )
    (net (code "487") (name "Net-(IC82-Pad7)") (class "Default")
      (node (ref "IC82") (pin "7") (pinfunction "7_7") (pintype "passive"))
      (node (ref "IC83") (pin "7") (pinfunction "7_7") (pintype "passive"))
      (node (ref "IC84") (pin "7") (pinfunction "7_7") (pintype "passive"))
      (node (ref "IC85") (pin "7") (pinfunction "7_7") (pintype "passive"))
    )
    (net (code "488") (name "Net-(IC82-Pad8)") (class "Default")
      (node (ref "IC82") (pin "8") (pinfunction "8_8") (pintype "passive"))
      (node (ref "IC83") (pin "8") (pinfunction "8_8") (pintype "passive"))
      (node (ref "IC84") (pin "8") (pinfunction "8_8") (pintype "passive"))
      (node (ref "IC85") (pin "8") (pinfunction "8_8") (pintype "passive"))
    )
    (net (code "489") (name "Net-(IC82-Pad9)") (class "Default")
      (node (ref "IC82") (pin "9") (pinfunction "9_9") (pintype "passive"))
      (node (ref "IC83") (pin "9") (pinfunction "9_9") (pintype "passive"))
      (node (ref "IC84") (pin "9") (pinfunction "9_9") (pintype "passive"))
      (node (ref "IC85") (pin "9") (pinfunction "9_9") (pintype "passive"))
    )
    (net (code "490") (name "Net-(IC82-Pad10)") (class "Default")
      (node (ref "IC82") (pin "10") (pinfunction "10_10") (pintype "passive"))
      (node (ref "IC83") (pin "10") (pinfunction "10_10") (pintype "passive"))
      (node (ref "IC84") (pin "10") (pinfunction "10_10") (pintype "passive"))
      (node (ref "IC85") (pin "10") (pinfunction "10_10") (pintype "passive"))
    )
    (net (code "491") (name "Net-(IC82-Pad11)") (class "Default")
      (node (ref "IC82") (pin "11") (pinfunction "11_11") (pintype "passive"))
      (node (ref "IC83") (pin "11") (pinfunction "11_11") (pintype "passive"))
      (node (ref "IC84") (pin "11") (pinfunction "11_11") (pintype "passive"))
      (node (ref "IC85") (pin "11") (pinfunction "11_11") (pintype "passive"))
    )
    (net (code "492") (name "Net-(IC82-Pad12)") (class "Default")
      (node (ref "IC82") (pin "12") (pinfunction "12_12") (pintype "passive"))
      (node (ref "IC83") (pin "12") (pinfunction "12_12") (pintype "passive"))
      (node (ref "IC84") (pin "12") (pinfunction "12_12") (pintype "passive"))
      (node (ref "IC85") (pin "12") (pinfunction "12_12") (pintype "passive"))
    )
    (net (code "493") (name "Net-(IC82-Pad13)") (class "Default")
      (node (ref "IC82") (pin "13") (pinfunction "13_13") (pintype "passive"))
      (node (ref "IC83") (pin "13") (pinfunction "13_13") (pintype "passive"))
      (node (ref "IC84") (pin "13") (pinfunction "13_13") (pintype "passive"))
      (node (ref "IC85") (pin "13") (pinfunction "13_13") (pintype "passive"))
    )
    (net (code "494") (name "Net-(IC82-Pad14)") (class "Default")
      (node (ref "IC82") (pin "14") (pinfunction "14_14") (pintype "passive"))
      (node (ref "IC83") (pin "14") (pinfunction "14_14") (pintype "passive"))
      (node (ref "IC84") (pin "14") (pinfunction "14_14") (pintype "passive"))
      (node (ref "IC85") (pin "14") (pinfunction "14_14") (pintype "passive"))
    )
    (net (code "495") (name "Net-(IC82-Pad15)") (class "Default")
      (node (ref "IC82") (pin "15") (pinfunction "15_15") (pintype "passive"))
      (node (ref "IC83") (pin "15") (pinfunction "15_15") (pintype "passive"))
      (node (ref "IC84") (pin "15") (pinfunction "15_15") (pintype "passive"))
      (node (ref "IC85") (pin "15") (pinfunction "15_15") (pintype "passive"))
    )
    (net (code "496") (name "Net-(IC82-Pad16)") (class "Default")
      (node (ref "IC82") (pin "16") (pinfunction "16_16") (pintype "passive"))
      (node (ref "IC83") (pin "16") (pinfunction "16_16") (pintype "passive"))
      (node (ref "IC84") (pin "16") (pinfunction "16_16") (pintype "passive"))
      (node (ref "IC85") (pin "16") (pinfunction "16_16") (pintype "passive"))
    )
    (net (code "497") (name "Net-(IC82-Pad17)") (class "Default")
      (node (ref "IC82") (pin "17") (pinfunction "17_17") (pintype "passive"))
      (node (ref "IC83") (pin "17") (pinfunction "17_17") (pintype "passive"))
      (node (ref "IC84") (pin "17") (pinfunction "17_17") (pintype "passive"))
      (node (ref "IC85") (pin "17") (pinfunction "17_17") (pintype "passive"))
    )
    (net (code "498") (name "Net-(IC82-Pad18)") (class "Default")
      (node (ref "IC82") (pin "18") (pinfunction "18_18") (pintype "passive"))
      (node (ref "IC83") (pin "18") (pinfunction "18_18") (pintype "passive"))
      (node (ref "IC84") (pin "18") (pinfunction "18_18") (pintype "passive"))
      (node (ref "IC85") (pin "18") (pinfunction "18_18") (pintype "passive"))
    )
    (net (code "499") (name "Net-(IC82-Pad19)") (class "Default")
      (node (ref "IC82") (pin "19") (pinfunction "19_19") (pintype "passive"))
      (node (ref "IC83") (pin "19") (pinfunction "19_19") (pintype "passive"))
      (node (ref "IC84") (pin "19") (pinfunction "19_19") (pintype "passive"))
      (node (ref "IC85") (pin "19") (pinfunction "19_19") (pintype "passive"))
    )
    (net (code "500") (name "Net-(IC82-Pad20)") (class "Default")
      (node (ref "IC82") (pin "20") (pinfunction "20_20") (pintype "passive"))
      (node (ref "IC83") (pin "20") (pinfunction "20_20") (pintype "passive"))
      (node (ref "IC84") (pin "20") (pinfunction "20_20") (pintype "passive"))
      (node (ref "IC85") (pin "20") (pinfunction "20_20") (pintype "passive"))
    )
    (net (code "501") (name "Net-(IC82-Pad21)") (class "Default")
      (node (ref "IC82") (pin "21") (pinfunction "21_21") (pintype "passive"))
      (node (ref "IC83") (pin "21") (pinfunction "21_21") (pintype "passive"))
      (node (ref "IC84") (pin "21") (pinfunction "21_21") (pintype "passive"))
      (node (ref "IC85") (pin "21") (pinfunction "21_21") (pintype "passive"))
    )
    (net (code "502") (name "Net-(IC82-Pad22)") (class "Default")
      (node (ref "IC82") (pin "22") (pinfunction "22_22") (pintype "passive"))
      (node (ref "IC83") (pin "22") (pinfunction "22_22") (pintype "passive"))
      (node (ref "IC84") (pin "22") (pinfunction "22_22") (pintype "passive"))
      (node (ref "IC85") (pin "22") (pinfunction "22_22") (pintype "passive"))
    )
    (net (code "503") (name "Net-(IC82-Pad23)") (class "Default")
      (node (ref "IC82") (pin "23") (pinfunction "23_23") (pintype "passive"))
      (node (ref "IC83") (pin "23") (pinfunction "23_23") (pintype "passive"))
      (node (ref "IC84") (pin "23") (pinfunction "23_23") (pintype "passive"))
      (node (ref "IC85") (pin "23") (pinfunction "23_23") (pintype "passive"))
    )
    (net (code "504") (name "Net-(IC82-Pad24)") (class "Default")
      (node (ref "IC82") (pin "24") (pinfunction "24_24") (pintype "passive"))
      (node (ref "IC83") (pin "24") (pinfunction "24_24") (pintype "passive"))
      (node (ref "IC84") (pin "24") (pinfunction "24_24") (pintype "passive"))
      (node (ref "IC85") (pin "24") (pinfunction "24_24") (pintype "passive"))
    )
    (net (code "505") (name "Net-(IC86-Pad1)") (class "Default")
      (node (ref "IC86") (pin "1") (pinfunction "1_1") (pintype "passive"))
      (node (ref "IC87") (pin "1") (pinfunction "1_1") (pintype "passive"))
      (node (ref "IC88") (pin "1") (pinfunction "1_1") (pintype "passive"))
      (node (ref "IC89") (pin "1") (pinfunction "1_1") (pintype "passive"))
    )
    (net (code "506") (name "Net-(IC86-Pad2)") (class "Default")
      (node (ref "IC86") (pin "2") (pinfunction "2_2") (pintype "passive"))
      (node (ref "IC87") (pin "2") (pinfunction "2_2") (pintype "passive"))
      (node (ref "IC88") (pin "2") (pinfunction "2_2") (pintype "passive"))
      (node (ref "IC89") (pin "2") (pinfunction "2_2") (pintype "passive"))
    )
    (net (code "507") (name "Net-(IC86-Pad3)") (class "Default")
      (node (ref "IC86") (pin "3") (pinfunction "3_3") (pintype "passive"))
      (node (ref "IC87") (pin "3") (pinfunction "3_3") (pintype "passive"))
      (node (ref "IC88") (pin "3") (pinfunction "3_3") (pintype "passive"))
      (node (ref "IC89") (pin "3") (pinfunction "3_3") (pintype "passive"))
    )
    (net (code "508") (name "Net-(IC86-Pad4)") (class "Default")
      (node (ref "IC86") (pin "4") (pinfunction "4_4") (pintype "passive"))
      (node (ref "IC87") (pin "4") (pinfunction "4_4") (pintype "passive"))
      (node (ref "IC88") (pin "4") (pinfunction "4_4") (pintype "passive"))
      (node (ref "IC89") (pin "4") (pinfunction "4_4") (pintype "passive"))
    )
    (net (code "509") (name "Net-(IC86-Pad5)") (class "Default")
      (node (ref "IC86") (pin "5") (pinfunction "5_5") (pintype "passive"))
      (node (ref "IC87") (pin "5") (pinfunction "5_5") (pintype "passive"))
      (node (ref "IC88") (pin "5") (pinfunction "5_5") (pintype "passive"))
      (node (ref "IC89") (pin "5") (pinfunction "5_5") (pintype "passive"))
    )
    (net (code "510") (name "Net-(IC86-Pad6)") (class "Default")
      (node (ref "IC86") (pin "6") (pinfunction "6_6") (pintype "passive"))
      (node (ref "IC87") (pin "6") (pinfunction "6_6") (pintype "passive"))
      (node (ref "IC88") (pin "6") (pinfunction "6_6") (pintype "passive"))
      (node (ref "IC89") (pin "6") (pinfunction "6_6") (pintype "passive"))
    )
    (net (code "511") (name "Net-(IC86-Pad7)") (class "Default")
      (node (ref "IC86") (pin "7") (pinfunction "7_7") (pintype "passive"))
      (node (ref "IC87") (pin "7") (pinfunction "7_7") (pintype "passive"))
      (node (ref "IC88") (pin "7") (pinfunction "7_7") (pintype "passive"))
      (node (ref "IC89") (pin "7") (pinfunction "7_7") (pintype "passive"))
    )
    (net (code "512") (name "Net-(IC86-Pad8)") (class "Default")
      (node (ref "IC86") (pin "8") (pinfunction "8_8") (pintype "passive"))
      (node (ref "IC87") (pin "8") (pinfunction "8_8") (pintype "passive"))
      (node (ref "IC88") (pin "8") (pinfunction "8_8") (pintype "passive"))
      (node (ref "IC89") (pin "8") (pinfunction "8_8") (pintype "passive"))
    )
    (net (code "513") (name "Net-(IC86-Pad9)") (class "Default")
      (node (ref "IC86") (pin "9") (pinfunction "9_9") (pintype "passive"))
      (node (ref "IC87") (pin "9") (pinfunction "9_9") (pintype "passive"))
      (node (ref "IC88") (pin "9") (pinfunction "9_9") (pintype "passive"))
      (node (ref "IC89") (pin "9") (pinfunction "9_9") (pintype "passive"))
    )
    (net (code "514") (name "Net-(IC86-Pad10)") (class "Default")
      (node (ref "IC86") (pin "10") (pinfunction "10_10") (pintype "passive"))
      (node (ref "IC87") (pin "10") (pinfunction "10_10") (pintype "passive"))
      (node (ref "IC88") (pin "10") (pinfunction "10_10") (pintype "passive"))
      (node (ref "IC89") (pin "10") (pinfunction "10_10") (pintype "passive"))
    )
    (net (code "515") (name "Net-(IC86-Pad11)") (class "Default")
      (node (ref "IC86") (pin "11") (pinfunction "11_11") (pintype "passive"))
      (node (ref "IC87") (pin "11") (pinfunction "11_11") (pintype "passive"))
      (node (ref "IC88") (pin "11") (pinfunction "11_11") (pintype "passive"))
      (node (ref "IC89") (pin "11") (pinfunction "11_11") (pintype "passive"))
    )
    (net (code "516") (name "Net-(IC86-Pad12)") (class "Default")
      (node (ref "IC86") (pin "12") (pinfunction "12_12") (pintype "passive"))
      (node (ref "IC87") (pin "12") (pinfunction "12_12") (pintype "passive"))
      (node (ref "IC88") (pin "12") (pinfunction "12_12") (pintype "passive"))
      (node (ref "IC89") (pin "12") (pinfunction "12_12") (pintype "passive"))
    )
    (net (code "517") (name "Net-(IC86-Pad13)") (class "Default")
      (node (ref "IC86") (pin "13") (pinfunction "13_13") (pintype "passive"))
      (node (ref "IC87") (pin "13") (pinfunction "13_13") (pintype "passive"))
      (node (ref "IC88") (pin "13") (pinfunction "13_13") (pintype "passive"))
      (node (ref "IC89") (pin "13") (pinfunction "13_13") (pintype "passive"))
    )
    (net (code "518") (name "Net-(IC86-Pad14)") (class "Default")
      (node (ref "IC86") (pin "14") (pinfunction "14_14") (pintype "passive"))
      (node (ref "IC87") (pin "14") (pinfunction "14_14") (pintype "passive"))
      (node (ref "IC88") (pin "14") (pinfunction "14_14") (pintype "passive"))
      (node (ref "IC89") (pin "14") (pinfunction "14_14") (pintype "passive"))
    )
    (net (code "519") (name "Net-(IC86-Pad15)") (class "Default")
      (node (ref "IC86") (pin "15") (pinfunction "15_15") (pintype "passive"))
      (node (ref "IC87") (pin "15") (pinfunction "15_15") (pintype "passive"))
      (node (ref "IC88") (pin "15") (pinfunction "15_15") (pintype "passive"))
      (node (ref "IC89") (pin "15") (pinfunction "15_15") (pintype "passive"))
    )
    (net (code "520") (name "Net-(IC86-Pad16)") (class "Default")
      (node (ref "IC86") (pin "16") (pinfunction "16_16") (pintype "passive"))
      (node (ref "IC87") (pin "16") (pinfunction "16_16") (pintype "passive"))
      (node (ref "IC88") (pin "16") (pinfunction "16_16") (pintype "passive"))
      (node (ref "IC89") (pin "16") (pinfunction "16_16") (pintype "passive"))
    )
    (net (code "521") (name "Net-(IC86-Pad17)") (class "Default")
      (node (ref "IC86") (pin "17") (pinfunction "17_17") (pintype "passive"))
      (node (ref "IC87") (pin "17") (pinfunction "17_17") (pintype "passive"))
      (node (ref "IC88") (pin "17") (pinfunction "17_17") (pintype "passive"))
      (node (ref "IC89") (pin "17") (pinfunction "17_17") (pintype "passive"))
    )
    (net (code "522") (name "Net-(IC86-Pad18)") (class "Default")
      (node (ref "IC86") (pin "18") (pinfunction "18_18") (pintype "passive"))
      (node (ref "IC87") (pin "18") (pinfunction "18_18") (pintype "passive"))
      (node (ref "IC88") (pin "18") (pinfunction "18_18") (pintype "passive"))
      (node (ref "IC89") (pin "18") (pinfunction "18_18") (pintype "passive"))
    )
    (net (code "523") (name "Net-(IC86-Pad19)") (class "Default")
      (node (ref "IC86") (pin "19") (pinfunction "19_19") (pintype "passive"))
      (node (ref "IC87") (pin "19") (pinfunction "19_19") (pintype "passive"))
      (node (ref "IC88") (pin "19") (pinfunction "19_19") (pintype "passive"))
      (node (ref "IC89") (pin "19") (pinfunction "19_19") (pintype "passive"))
    )
    (net (code "524") (name "Net-(IC86-Pad20)") (class "Default")
      (node (ref "IC86") (pin "20") (pinfunction "20_20") (pintype "passive"))
      (node (ref "IC87") (pin "20") (pinfunction "20_20") (pintype "passive"))
      (node (ref "IC88") (pin "20") (pinfunction "20_20") (pintype "passive"))
      (node (ref "IC89") (pin "20") (pinfunction "20_20") (pintype "passive"))
    )
    (net (code "525") (name "Net-(IC86-Pad21)") (class "Default")
      (node (ref "IC86") (pin "21") (pinfunction "21_21") (pintype "passive"))
      (node (ref "IC87") (pin "21") (pinfunction "21_21") (pintype "passive"))
      (node (ref "IC88") (pin "21") (pinfunction "21_21") (pintype "passive"))
      (node (ref "IC89") (pin "21") (pinfunction "21_21") (pintype "passive"))
    )
    (net (code "526") (name "Net-(IC86-Pad22)") (class "Default")
      (node (ref "IC86") (pin "22") (pinfunction "22_22") (pintype "passive"))
      (node (ref "IC87") (pin "22") (pinfunction "22_22") (pintype "passive"))
      (node (ref "IC88") (pin "22") (pinfunction "22_22") (pintype "passive"))
      (node (ref "IC89") (pin "22") (pinfunction "22_22") (pintype "passive"))
    )
    (net (code "527") (name "Net-(IC86-Pad23)") (class "Default")
      (node (ref "IC86") (pin "23") (pinfunction "23_23") (pintype "passive"))
      (node (ref "IC87") (pin "23") (pinfunction "23_23") (pintype "passive"))
      (node (ref "IC88") (pin "23") (pinfunction "23_23") (pintype "passive"))
      (node (ref "IC89") (pin "23") (pinfunction "23_23") (pintype "passive"))
    )
    (net (code "528") (name "Net-(IC86-Pad24)") (class "Default")
      (node (ref "IC86") (pin "24") (pinfunction "24_24") (pintype "passive"))
      (node (ref "IC87") (pin "24") (pinfunction "24_24") (pintype "passive"))
      (node (ref "IC88") (pin "24") (pinfunction "24_24") (pintype "passive"))
      (node (ref "IC89") (pin "24") (pinfunction "24_24") (pintype "passive"))
    )
    (net (code "529") (name "Net-(IC90-Pad1)") (class "Default")
      (node (ref "IC90") (pin "1") (pinfunction "1_1") (pintype "passive"))
      (node (ref "IC91") (pin "1") (pinfunction "1_1") (pintype "passive"))
      (node (ref "IC92") (pin "1") (pinfunction "1_1") (pintype "passive"))
      (node (ref "IC93") (pin "1") (pinfunction "1_1") (pintype "passive"))
    )
    (net (code "530") (name "Net-(IC90-Pad2)") (class "Default")
      (node (ref "IC90") (pin "2") (pinfunction "2_2") (pintype "passive"))
      (node (ref "IC91") (pin "2") (pinfunction "2_2") (pintype "passive"))
      (node (ref "IC92") (pin "2") (pinfunction "2_2") (pintype "passive"))
      (node (ref "IC93") (pin "2") (pinfunction "2_2") (pintype "passive"))
    )
    (net (code "531") (name "Net-(IC90-Pad3)") (class "Default")
      (node (ref "IC90") (pin "3") (pinfunction "3_3") (pintype "passive"))
      (node (ref "IC91") (pin "3") (pinfunction "3_3") (pintype "passive"))
      (node (ref "IC92") (pin "3") (pinfunction "3_3") (pintype "passive"))
      (node (ref "IC93") (pin "3") (pinfunction "3_3") (pintype "passive"))
    )
    (net (code "532") (name "Net-(IC90-Pad4)") (class "Default")
      (node (ref "IC90") (pin "4") (pinfunction "4_4") (pintype "passive"))
      (node (ref "IC91") (pin "4") (pinfunction "4_4") (pintype "passive"))
      (node (ref "IC92") (pin "4") (pinfunction "4_4") (pintype "passive"))
      (node (ref "IC93") (pin "4") (pinfunction "4_4") (pintype "passive"))
    )
    (net (code "533") (name "Net-(IC90-Pad5)") (class "Default")
      (node (ref "IC90") (pin "5") (pinfunction "5_5") (pintype "passive"))
      (node (ref "IC91") (pin "5") (pinfunction "5_5") (pintype "passive"))
      (node (ref "IC92") (pin "5") (pinfunction "5_5") (pintype "passive"))
      (node (ref "IC93") (pin "5") (pinfunction "5_5") (pintype "passive"))
    )
    (net (code "534") (name "Net-(IC90-Pad6)") (class "Default")
      (node (ref "IC90") (pin "6") (pinfunction "6_6") (pintype "passive"))
      (node (ref "IC91") (pin "6") (pinfunction "6_6") (pintype "passive"))
      (node (ref "IC92") (pin "6") (pinfunction "6_6") (pintype "passive"))
      (node (ref "IC93") (pin "6") (pinfunction "6_6") (pintype "passive"))
    )
    (net (code "535") (name "Net-(IC90-Pad7)") (class "Default")
      (node (ref "IC90") (pin "7") (pinfunction "7_7") (pintype "passive"))
      (node (ref "IC91") (pin "7") (pinfunction "7_7") (pintype "passive"))
      (node (ref "IC92") (pin "7") (pinfunction "7_7") (pintype "passive"))
      (node (ref "IC93") (pin "7") (pinfunction "7_7") (pintype "passive"))
    )
    (net (code "536") (name "Net-(IC90-Pad8)") (class "Default")
      (node (ref "IC90") (pin "8") (pinfunction "8_8") (pintype "passive"))
      (node (ref "IC91") (pin "8") (pinfunction "8_8") (pintype "passive"))
      (node (ref "IC92") (pin "8") (pinfunction "8_8") (pintype "passive"))
      (node (ref "IC93") (pin "8") (pinfunction "8_8") (pintype "passive"))
    )
    (net (code "537") (name "Net-(IC90-Pad9)") (class "Default")
      (node (ref "IC90") (pin "9") (pinfunction "9_9") (pintype "passive"))
      (node (ref "IC91") (pin "9") (pinfunction "9_9") (pintype "passive"))
      (node (ref "IC92") (pin "9") (pinfunction "9_9") (pintype "passive"))
      (node (ref "IC93") (pin "9") (pinfunction "9_9") (pintype "passive"))
    )
    (net (code "538") (name "Net-(IC90-Pad10)") (class "Default")
      (node (ref "IC90") (pin "10") (pinfunction "10_10") (pintype "passive"))
      (node (ref "IC91") (pin "10") (pinfunction "10_10") (pintype "passive"))
      (node (ref "IC92") (pin "10") (pinfunction "10_10") (pintype "passive"))
      (node (ref "IC93") (pin "10") (pinfunction "10_10") (pintype "passive"))
    )
    (net (code "539") (name "Net-(IC90-Pad11)") (class "Default")
      (node (ref "IC90") (pin "11") (pinfunction "11_11") (pintype "passive"))
      (node (ref "IC91") (pin "11") (pinfunction "11_11") (pintype "passive"))
      (node (ref "IC92") (pin "11") (pinfunction "11_11") (pintype "passive"))
      (node (ref "IC93") (pin "11") (pinfunction "11_11") (pintype "passive"))
    )
    (net (code "540") (name "Net-(IC90-Pad12)") (class "Default")
      (node (ref "IC90") (pin "12") (pinfunction "12_12") (pintype "passive"))
      (node (ref "IC91") (pin "12") (pinfunction "12_12") (pintype "passive"))
      (node (ref "IC92") (pin "12") (pinfunction "12_12") (pintype "passive"))
      (node (ref "IC93") (pin "12") (pinfunction "12_12") (pintype "passive"))
    )
    (net (code "541") (name "Net-(IC90-Pad13)") (class "Default")
      (node (ref "IC90") (pin "13") (pinfunction "13_13") (pintype "passive"))
      (node (ref "IC91") (pin "13") (pinfunction "13_13") (pintype "passive"))
      (node (ref "IC92") (pin "13") (pinfunction "13_13") (pintype "passive"))
      (node (ref "IC93") (pin "13") (pinfunction "13_13") (pintype "passive"))
    )
    (net (code "542") (name "Net-(IC90-Pad14)") (class "Default")
      (node (ref "IC90") (pin "14") (pinfunction "14_14") (pintype "passive"))
      (node (ref "IC91") (pin "14") (pinfunction "14_14") (pintype "passive"))
      (node (ref "IC92") (pin "14") (pinfunction "14_14") (pintype "passive"))
      (node (ref "IC93") (pin "14") (pinfunction "14_14") (pintype "passive"))
    )
    (net (code "543") (name "Net-(IC90-Pad15)") (class "Default")
      (node (ref "IC90") (pin "15") (pinfunction "15_15") (pintype "passive"))
      (node (ref "IC91") (pin "15") (pinfunction "15_15") (pintype "passive"))
      (node (ref "IC92") (pin "15") (pinfunction "15_15") (pintype "passive"))
      (node (ref "IC93") (pin "15") (pinfunction "15_15") (pintype "passive"))
    )
    (net (code "544") (name "Net-(IC90-Pad16)") (class "Default")
      (node (ref "IC90") (pin "16") (pinfunction "16_16") (pintype "passive"))
      (node (ref "IC91") (pin "16") (pinfunction "16_16") (pintype "passive"))
      (node (ref "IC92") (pin "16") (pinfunction "16_16") (pintype "passive"))
      (node (ref "IC93") (pin "16") (pinfunction "16_16") (pintype "passive"))
    )
    (net (code "545") (name "Net-(IC90-Pad17)") (class "Default")
      (node (ref "IC90") (pin "17") (pinfunction "17_17") (pintype "passive"))
      (node (ref "IC91") (pin "17") (pinfunction "17_17") (pintype "passive"))
      (node (ref "IC92") (pin "17") (pinfunction "17_17") (pintype "passive"))
      (node (ref "IC93") (pin "17") (pinfunction "17_17") (pintype "passive"))
    )
    (net (code "546") (name "Net-(IC90-Pad18)") (class "Default")
      (node (ref "IC90") (pin "18") (pinfunction "18_18") (pintype "passive"))
      (node (ref "IC91") (pin "18") (pinfunction "18_18") (pintype "passive"))
      (node (ref "IC92") (pin "18") (pinfunction "18_18") (pintype "passive"))
      (node (ref "IC93") (pin "18") (pinfunction "18_18") (pintype "passive"))
    )
    (net (code "547") (name "Net-(IC90-Pad19)") (class "Default")
      (node (ref "IC90") (pin "19") (pinfunction "19_19") (pintype "passive"))
      (node (ref "IC91") (pin "19") (pinfunction "19_19") (pintype "passive"))
      (node (ref "IC92") (pin "19") (pinfunction "19_19") (pintype "passive"))
      (node (ref "IC93") (pin "19") (pinfunction "19_19") (pintype "passive"))
    )
    (net (code "548") (name "Net-(IC90-Pad20)") (class "Default")
      (node (ref "IC90") (pin "20") (pinfunction "20_20") (pintype "passive"))
      (node (ref "IC91") (pin "20") (pinfunction "20_20") (pintype "passive"))
      (node (ref "IC92") (pin "20") (pinfunction "20_20") (pintype "passive"))
      (node (ref "IC93") (pin "20") (pinfunction "20_20") (pintype "passive"))
    )
    (net (code "549") (name "Net-(IC90-Pad21)") (class "Default")
      (node (ref "IC90") (pin "21") (pinfunction "21_21") (pintype "passive"))
      (node (ref "IC91") (pin "21") (pinfunction "21_21") (pintype "passive"))
      (node (ref "IC92") (pin "21") (pinfunction "21_21") (pintype "passive"))
      (node (ref "IC93") (pin "21") (pinfunction "21_21") (pintype "passive"))
    )
    (net (code "550") (name "Net-(IC90-Pad22)") (class "Default")
      (node (ref "IC90") (pin "22") (pinfunction "22_22") (pintype "passive"))
      (node (ref "IC91") (pin "22") (pinfunction "22_22") (pintype "passive"))
      (node (ref "IC92") (pin "22") (pinfunction "22_22") (pintype "passive"))
      (node (ref "IC93") (pin "22") (pinfunction "22_22") (pintype "passive"))
    )
    (net (code "551") (name "Net-(IC90-Pad23)") (class "Default")
      (node (ref "IC90") (pin "23") (pinfunction "23_23") (pintype "passive"))
      (node (ref "IC91") (pin "23") (pinfunction "23_23") (pintype "passive"))
      (node (ref "IC92") (pin "23") (pinfunction "23_23") (pintype "passive"))
      (node (ref "IC93") (pin "23") (pinfunction "23_23") (pintype "passive"))
    )
    (net (code "552") (name "Net-(IC90-Pad24)") (class "Default")
      (node (ref "IC90") (pin "24") (pinfunction "24_24") (pintype "passive"))
      (node (ref "IC91") (pin "24") (pinfunction "24_24") (pintype "passive"))
      (node (ref "IC92") (pin "24") (pinfunction "24_24") (pintype "passive"))
      (node (ref "IC93") (pin "24") (pinfunction "24_24") (pintype "passive"))
    )
    (net (code "553") (name "Net-(IC94-Pad1)") (class "Default")
      (node (ref "IC94") (pin "1") (pinfunction "1_1") (pintype "passive"))
      (node (ref "IC95") (pin "1") (pinfunction "1_1") (pintype "passive"))
      (node (ref "IC96") (pin "1") (pinfunction "1_1") (pintype "passive"))
      (node (ref "IC97") (pin "1") (pinfunction "1_1") (pintype "passive"))
    )
    (net (code "554") (name "Net-(IC94-Pad2)") (class "Default")
      (node (ref "IC94") (pin "2") (pinfunction "2_2") (pintype "passive"))
      (node (ref "IC95") (pin "2") (pinfunction "2_2") (pintype "passive"))
      (node (ref "IC96") (pin "2") (pinfunction "2_2") (pintype "passive"))
      (node (ref "IC97") (pin "2") (pinfunction "2_2") (pintype "passive"))
    )
    (net (code "555") (name "Net-(IC94-Pad3)") (class "Default")
      (node (ref "IC94") (pin "3") (pinfunction "3_3") (pintype "passive"))
      (node (ref "IC95") (pin "3") (pinfunction "3_3") (pintype "passive"))
      (node (ref "IC96") (pin "3") (pinfunction "3_3") (pintype "passive"))
      (node (ref "IC97") (pin "3") (pinfunction "3_3") (pintype "passive"))
    )
    (net (code "556") (name "Net-(IC94-Pad4)") (class "Default")
      (node (ref "IC94") (pin "4") (pinfunction "4_4") (pintype "passive"))
      (node (ref "IC95") (pin "4") (pinfunction "4_4") (pintype "passive"))
      (node (ref "IC96") (pin "4") (pinfunction "4_4") (pintype "passive"))
      (node (ref "IC97") (pin "4") (pinfunction "4_4") (pintype "passive"))
    )
    (net (code "557") (name "Net-(IC94-Pad5)") (class "Default")
      (node (ref "IC94") (pin "5") (pinfunction "5_5") (pintype "passive"))
      (node (ref "IC95") (pin "5") (pinfunction "5_5") (pintype "passive"))
      (node (ref "IC96") (pin "5") (pinfunction "5_5") (pintype "passive"))
      (node (ref "IC97") (pin "5") (pinfunction "5_5") (pintype "passive"))
    )
    (net (code "558") (name "Net-(IC94-Pad6)") (class "Default")
      (node (ref "IC94") (pin "6") (pinfunction "6_6") (pintype "passive"))
      (node (ref "IC95") (pin "6") (pinfunction "6_6") (pintype "passive"))
      (node (ref "IC96") (pin "6") (pinfunction "6_6") (pintype "passive"))
      (node (ref "IC97") (pin "6") (pinfunction "6_6") (pintype "passive"))
    )
    (net (code "559") (name "Net-(IC94-Pad7)") (class "Default")
      (node (ref "IC94") (pin "7") (pinfunction "7_7") (pintype "passive"))
      (node (ref "IC95") (pin "7") (pinfunction "7_7") (pintype "passive"))
      (node (ref "IC96") (pin "7") (pinfunction "7_7") (pintype "passive"))
      (node (ref "IC97") (pin "7") (pinfunction "7_7") (pintype "passive"))
    )
    (net (code "560") (name "Net-(IC94-Pad8)") (class "Default")
      (node (ref "IC94") (pin "8") (pinfunction "8_8") (pintype "passive"))
      (node (ref "IC95") (pin "8") (pinfunction "8_8") (pintype "passive"))
      (node (ref "IC96") (pin "8") (pinfunction "8_8") (pintype "passive"))
      (node (ref "IC97") (pin "8") (pinfunction "8_8") (pintype "passive"))
    )
    (net (code "561") (name "Net-(IC94-Pad9)") (class "Default")
      (node (ref "IC94") (pin "9") (pinfunction "9_9") (pintype "passive"))
      (node (ref "IC95") (pin "9") (pinfunction "9_9") (pintype "passive"))
      (node (ref "IC96") (pin "9") (pinfunction "9_9") (pintype "passive"))
      (node (ref "IC97") (pin "9") (pinfunction "9_9") (pintype "passive"))
    )
    (net (code "562") (name "Net-(IC94-Pad10)") (class "Default")
      (node (ref "IC94") (pin "10") (pinfunction "10_10") (pintype "passive"))
      (node (ref "IC95") (pin "10") (pinfunction "10_10") (pintype "passive"))
      (node (ref "IC96") (pin "10") (pinfunction "10_10") (pintype "passive"))
      (node (ref "IC97") (pin "10") (pinfunction "10_10") (pintype "passive"))
    )
    (net (code "563") (name "Net-(IC94-Pad11)") (class "Default")
      (node (ref "IC94") (pin "11") (pinfunction "11_11") (pintype "passive"))
      (node (ref "IC95") (pin "11") (pinfunction "11_11") (pintype "passive"))
      (node (ref "IC96") (pin "11") (pinfunction "11_11") (pintype "passive"))
      (node (ref "IC97") (pin "11") (pinfunction "11_11") (pintype "passive"))
    )
    (net (code "564") (name "Net-(IC94-Pad12)") (class "Default")
      (node (ref "IC94") (pin "12") (pinfunction "12_12") (pintype "passive"))
      (node (ref "IC95") (pin "12") (pinfunction "12_12") (pintype "passive"))
      (node (ref "IC96") (pin "12") (pinfunction "12_12") (pintype "passive"))
      (node (ref "IC97") (pin "12") (pinfunction "12_12") (pintype "passive"))
    )
    (net (code "565") (name "Net-(IC94-Pad13)") (class "Default")
      (node (ref "IC94") (pin "13") (pinfunction "13_13") (pintype "passive"))
      (node (ref "IC95") (pin "13") (pinfunction "13_13") (pintype "passive"))
      (node (ref "IC96") (pin "13") (pinfunction "13_13") (pintype "passive"))
      (node (ref "IC97") (pin "13") (pinfunction "13_13") (pintype "passive"))
    )
    (net (code "566") (name "Net-(IC94-Pad14)") (class "Default")
      (node (ref "IC94") (pin "14") (pinfunction "14_14") (pintype "passive"))
      (node (ref "IC95") (pin "14") (pinfunction "14_14") (pintype "passive"))
      (node (ref "IC96") (pin "14") (pinfunction "14_14") (pintype "passive"))
      (node (ref "IC97") (pin "14") (pinfunction "14_14") (pintype "passive"))
    )
    (net (code "567") (name "Net-(IC94-Pad15)") (class "Default")
      (node (ref "IC94") (pin "15") (pinfunction "15_15") (pintype "passive"))
      (node (ref "IC95") (pin "15") (pinfunction "15_15") (pintype "passive"))
      (node (ref "IC96") (pin "15") (pinfunction "15_15") (pintype "passive"))
      (node (ref "IC97") (pin "15") (pinfunction "15_15") (pintype "passive"))
    )
    (net (code "568") (name "Net-(IC94-Pad16)") (class "Default")
      (node (ref "IC94") (pin "16") (pinfunction "16_16") (pintype "passive"))
      (node (ref "IC95") (pin "16") (pinfunction "16_16") (pintype "passive"))
      (node (ref "IC96") (pin "16") (pinfunction "16_16") (pintype "passive"))
      (node (ref "IC97") (pin "16") (pinfunction "16_16") (pintype "passive"))
    )
    (net (code "569") (name "Net-(IC94-Pad17)") (class "Default")
      (node (ref "IC94") (pin "17") (pinfunction "17_17") (pintype "passive"))
      (node (ref "IC95") (pin "17") (pinfunction "17_17") (pintype "passive"))
      (node (ref "IC96") (pin "17") (pinfunction "17_17") (pintype "passive"))
      (node (ref "IC97") (pin "17") (pinfunction "17_17") (pintype "passive"))
    )
    (net (code "570") (name "Net-(IC94-Pad18)") (class "Default")
      (node (ref "IC94") (pin "18") (pinfunction "18_18") (pintype "passive"))
      (node (ref "IC95") (pin "18") (pinfunction "18_18") (pintype "passive"))
      (node (ref "IC96") (pin "18") (pinfunction "18_18") (pintype "passive"))
      (node (ref "IC97") (pin "18") (pinfunction "18_18") (pintype "passive"))
    )
    (net (code "571") (name "Net-(IC94-Pad19)") (class "Default")
      (node (ref "IC94") (pin "19") (pinfunction "19_19") (pintype "passive"))
      (node (ref "IC95") (pin "19") (pinfunction "19_19") (pintype "passive"))
      (node (ref "IC96") (pin "19") (pinfunction "19_19") (pintype "passive"))
      (node (ref "IC97") (pin "19") (pinfunction "19_19") (pintype "passive"))
    )
    (net (code "572") (name "Net-(IC94-Pad20)") (class "Default")
      (node (ref "IC94") (pin "20") (pinfunction "20_20") (pintype "passive"))
      (node (ref "IC95") (pin "20") (pinfunction "20_20") (pintype "passive"))
      (node (ref "IC96") (pin "20") (pinfunction "20_20") (pintype "passive"))
      (node (ref "IC97") (pin "20") (pinfunction "20_20") (pintype "passive"))
    )
    (net (code "573") (name "Net-(IC94-Pad21)") (class "Default")
      (node (ref "IC94") (pin "21") (pinfunction "21_21") (pintype "passive"))
      (node (ref "IC95") (pin "21") (pinfunction "21_21") (pintype "passive"))
      (node (ref "IC96") (pin "21") (pinfunction "21_21") (pintype "passive"))
      (node (ref "IC97") (pin "21") (pinfunction "21_21") (pintype "passive"))
    )
    (net (code "574") (name "Net-(IC94-Pad22)") (class "Default")
      (node (ref "IC94") (pin "22") (pinfunction "22_22") (pintype "passive"))
      (node (ref "IC95") (pin "22") (pinfunction "22_22") (pintype "passive"))
      (node (ref "IC96") (pin "22") (pinfunction "22_22") (pintype "passive"))
      (node (ref "IC97") (pin "22") (pinfunction "22_22") (pintype "passive"))
    )
    (net (code "575") (name "Net-(IC94-Pad23)") (class "Default")
      (node (ref "IC94") (pin "23") (pinfunction "23_23") (pintype "passive"))
      (node (ref "IC95") (pin "23") (pinfunction "23_23") (pintype "passive"))
      (node (ref "IC96") (pin "23") (pinfunction "23_23") (pintype "passive"))
      (node (ref "IC97") (pin "23") (pinfunction "23_23") (pintype "passive"))
    )
    (net (code "576") (name "Net-(IC94-Pad24)") (class "Default")
      (node (ref "IC94") (pin "24") (pinfunction "24_24") (pintype "passive"))
      (node (ref "IC95") (pin "24") (pinfunction "24_24") (pintype "passive"))
      (node (ref "IC96") (pin "24") (pinfunction "24_24") (pintype "passive"))
      (node (ref "IC97") (pin "24") (pinfunction "24_24") (pintype "passive"))
    )
    (net (code "577") (name "Net-(IC100-Pad1)") (class "Default")
      (node (ref "IC100") (pin "1") (pinfunction "1_1") (pintype "passive"))
      (node (ref "IC101") (pin "1") (pinfunction "1_1") (pintype "passive"))
      (node (ref "IC98") (pin "1") (pinfunction "1_1") (pintype "passive"))
      (node (ref "IC99") (pin "1") (pinfunction "1_1") (pintype "passive"))
    )
    (net (code "578") (name "Net-(IC100-Pad2)") (class "Default")
      (node (ref "IC100") (pin "2") (pinfunction "2_2") (pintype "passive"))
      (node (ref "IC101") (pin "2") (pinfunction "2_2") (pintype "passive"))
      (node (ref "IC98") (pin "2") (pinfunction "2_2") (pintype "passive"))
      (node (ref "IC99") (pin "2") (pinfunction "2_2") (pintype "passive"))
    )
    (net (code "579") (name "Net-(IC100-Pad3)") (class "Default")
      (node (ref "IC100") (pin "3") (pinfunction "3_3") (pintype "passive"))
      (node (ref "IC101") (pin "3") (pinfunction "3_3") (pintype "passive"))
      (node (ref "IC98") (pin "3") (pinfunction "3_3") (pintype "passive"))
      (node (ref "IC99") (pin "3") (pinfunction "3_3") (pintype "passive"))
    )
    (net (code "580") (name "Net-(IC100-Pad4)") (class "Default")
      (node (ref "IC100") (pin "4") (pinfunction "4_4") (pintype "passive"))
      (node (ref "IC101") (pin "4") (pinfunction "4_4") (pintype "passive"))
      (node (ref "IC98") (pin "4") (pinfunction "4_4") (pintype "passive"))
      (node (ref "IC99") (pin "4") (pinfunction "4_4") (pintype "passive"))
    )
    (net (code "581") (name "Net-(IC100-Pad5)") (class "Default")
      (node (ref "IC100") (pin "5") (pinfunction "5_5") (pintype "passive"))
      (node (ref "IC101") (pin "5") (pinfunction "5_5") (pintype "passive"))
      (node (ref "IC98") (pin "5") (pinfunction "5_5") (pintype "passive"))
      (node (ref "IC99") (pin "5") (pinfunction "5_5") (pintype "passive"))
    )
    (net (code "582") (name "Net-(IC100-Pad6)") (class "Default")
      (node (ref "IC100") (pin "6") (pinfunction "6_6") (pintype "passive"))
      (node (ref "IC101") (pin "6") (pinfunction "6_6") (pintype "passive"))
      (node (ref "IC98") (pin "6") (pinfunction "6_6") (pintype "passive"))
      (node (ref "IC99") (pin "6") (pinfunction "6_6") (pintype "passive"))
    )
    (net (code "583") (name "Net-(IC100-Pad7)") (class "Default")
      (node (ref "IC100") (pin "7") (pinfunction "7_7") (pintype "passive"))
      (node (ref "IC101") (pin "7") (pinfunction "7_7") (pintype "passive"))
      (node (ref "IC98") (pin "7") (pinfunction "7_7") (pintype "passive"))
      (node (ref "IC99") (pin "7") (pinfunction "7_7") (pintype "passive"))
    )
    (net (code "584") (name "Net-(IC100-Pad8)") (class "Default")
      (node (ref "IC100") (pin "8") (pinfunction "8_8") (pintype "passive"))
      (node (ref "IC101") (pin "8") (pinfunction "8_8") (pintype "passive"))
      (node (ref "IC98") (pin "8") (pinfunction "8_8") (pintype "passive"))
      (node (ref "IC99") (pin "8") (pinfunction "8_8") (pintype "passive"))
    )
    (net (code "585") (name "Net-(IC100-Pad9)") (class "Default")
      (node (ref "IC100") (pin "9") (pinfunction "9_9") (pintype "passive"))
      (node (ref "IC101") (pin "9") (pinfunction "9_9") (pintype "passive"))
      (node (ref "IC98") (pin "9") (pinfunction "9_9") (pintype "passive"))
      (node (ref "IC99") (pin "9") (pinfunction "9_9") (pintype "passive"))
    )
    (net (code "586") (name "Net-(IC100-Pad10)") (class "Default")
      (node (ref "IC100") (pin "10") (pinfunction "10_10") (pintype "passive"))
      (node (ref "IC101") (pin "10") (pinfunction "10_10") (pintype "passive"))
      (node (ref "IC98") (pin "10") (pinfunction "10_10") (pintype "passive"))
      (node (ref "IC99") (pin "10") (pinfunction "10_10") (pintype "passive"))
    )
    (net (code "587") (name "Net-(IC100-Pad11)") (class "Default")
      (node (ref "IC100") (pin "11") (pinfunction "11_11") (pintype "passive"))
      (node (ref "IC101") (pin "11") (pinfunction "11_11") (pintype "passive"))
      (node (ref "IC98") (pin "11") (pinfunction "11_11") (pintype "passive"))
      (node (ref "IC99") (pin "11") (pinfunction "11_11") (pintype "passive"))
    )
    (net (code "588") (name "Net-(IC100-Pad12)") (class "Default")
      (node (ref "IC100") (pin "12") (pinfunction "12_12") (pintype "passive"))
      (node (ref "IC101") (pin "12") (pinfunction "12_12") (pintype "passive"))
      (node (ref "IC98") (pin "12") (pinfunction "12_12") (pintype "passive"))
      (node (ref "IC99") (pin "12") (pinfunction "12_12") (pintype "passive"))
    )
    (net (code "589") (name "Net-(IC100-Pad13)") (class "Default")
      (node (ref "IC100") (pin "13") (pinfunction "13_13") (pintype "passive"))
      (node (ref "IC101") (pin "13") (pinfunction "13_13") (pintype "passive"))
      (node (ref "IC98") (pin "13") (pinfunction "13_13") (pintype "passive"))
      (node (ref "IC99") (pin "13") (pinfunction "13_13") (pintype "passive"))
    )
    (net (code "590") (name "Net-(IC100-Pad14)") (class "Default")
      (node (ref "IC100") (pin "14") (pinfunction "14_14") (pintype "passive"))
      (node (ref "IC101") (pin "14") (pinfunction "14_14") (pintype "passive"))
      (node (ref "IC98") (pin "14") (pinfunction "14_14") (pintype "passive"))
      (node (ref "IC99") (pin "14") (pinfunction "14_14") (pintype "passive"))
    )
    (net (code "591") (name "Net-(IC100-Pad15)") (class "Default")
      (node (ref "IC100") (pin "15") (pinfunction "15_15") (pintype "passive"))
      (node (ref "IC101") (pin "15") (pinfunction "15_15") (pintype "passive"))
      (node (ref "IC98") (pin "15") (pinfunction "15_15") (pintype "passive"))
      (node (ref "IC99") (pin "15") (pinfunction "15_15") (pintype "passive"))
    )
    (net (code "592") (name "Net-(IC100-Pad16)") (class "Default")
      (node (ref "IC100") (pin "16") (pinfunction "16_16") (pintype "passive"))
      (node (ref "IC101") (pin "16") (pinfunction "16_16") (pintype "passive"))
      (node (ref "IC98") (pin "16") (pinfunction "16_16") (pintype "passive"))
      (node (ref "IC99") (pin "16") (pinfunction "16_16") (pintype "passive"))
    )
    (net (code "593") (name "Net-(IC100-Pad17)") (class "Default")
      (node (ref "IC100") (pin "17") (pinfunction "17_17") (pintype "passive"))
      (node (ref "IC101") (pin "17") (pinfunction "17_17") (pintype "passive"))
      (node (ref "IC98") (pin "17") (pinfunction "17_17") (pintype "passive"))
      (node (ref "IC99") (pin "17") (pinfunction "17_17") (pintype "passive"))
    )
    (net (code "594") (name "Net-(IC100-Pad18)") (class "Default")
      (node (ref "IC100") (pin "18") (pinfunction "18_18") (pintype "passive"))
      (node (ref "IC101") (pin "18") (pinfunction "18_18") (pintype "passive"))
      (node (ref "IC98") (pin "18") (pinfunction "18_18") (pintype "passive"))
      (node (ref "IC99") (pin "18") (pinfunction "18_18") (pintype "passive"))
    )
    (net (code "595") (name "Net-(IC100-Pad19)") (class "Default")
      (node (ref "IC100") (pin "19") (pinfunction "19_19") (pintype "passive"))
      (node (ref "IC101") (pin "19") (pinfunction "19_19") (pintype "passive"))
      (node (ref "IC98") (pin "19") (pinfunction "19_19") (pintype "passive"))
      (node (ref "IC99") (pin "19") (pinfunction "19_19") (pintype "passive"))
    )
    (net (code "596") (name "Net-(IC100-Pad20)") (class "Default")
      (node (ref "IC100") (pin "20") (pinfunction "20_20") (pintype "passive"))
      (node (ref "IC101") (pin "20") (pinfunction "20_20") (pintype "passive"))
      (node (ref "IC98") (pin "20") (pinfunction "20_20") (pintype "passive"))
      (node (ref "IC99") (pin "20") (pinfunction "20_20") (pintype "passive"))
    )
    (net (code "597") (name "Net-(IC100-Pad21)") (class "Default")
      (node (ref "IC100") (pin "21") (pinfunction "21_21") (pintype "passive"))
      (node (ref "IC101") (pin "21") (pinfunction "21_21") (pintype "passive"))
      (node (ref "IC98") (pin "21") (pinfunction "21_21") (pintype "passive"))
      (node (ref "IC99") (pin "21") (pinfunction "21_21") (pintype "passive"))
    )
    (net (code "598") (name "Net-(IC100-Pad22)") (class "Default")
      (node (ref "IC100") (pin "22") (pinfunction "22_22") (pintype "passive"))
      (node (ref "IC101") (pin "22") (pinfunction "22_22") (pintype "passive"))
      (node (ref "IC98") (pin "22") (pinfunction "22_22") (pintype "passive"))
      (node (ref "IC99") (pin "22") (pinfunction "22_22") (pintype "passive"))
    )
    (net (code "599") (name "Net-(IC100-Pad23)") (class "Default")
      (node (ref "IC100") (pin "23") (pinfunction "23_23") (pintype "passive"))
      (node (ref "IC101") (pin "23") (pinfunction "23_23") (pintype "passive"))
      (node (ref "IC98") (pin "23") (pinfunction "23_23") (pintype "passive"))
      (node (ref "IC99") (pin "23") (pinfunction "23_23") (pintype "passive"))
    )
    (net (code "600") (name "Net-(IC100-Pad24)") (class "Default")
      (node (ref "IC100") (pin "24") (pinfunction "24_24") (pintype "passive"))
      (node (ref "IC101") (pin "24") (pinfunction "24_24") (pintype "passive"))
      (node (ref "IC98") (pin "24") (pinfunction "24_24") (pintype "passive"))
      (node (ref "IC99") (pin "24") (pinfunction "24_24") (pintype "passive"))
    )
    (net (code "601") (name "Net-(IC102-Pad1)") (class "Default")
      (node (ref "IC102") (pin "1") (pinfunction "1_1") (pintype "passive"))
      (node (ref "IC103") (pin "1") (pinfunction "1_1") (pintype "passive"))
      (node (ref "IC104") (pin "1") (pinfunction "1_1") (pintype "passive"))
      (node (ref "IC105") (pin "1") (pinfunction "1_1") (pintype "passive"))
    )
    (net (code "602") (name "Net-(IC102-Pad2)") (class "Default")
      (node (ref "IC102") (pin "2") (pinfunction "2_2") (pintype "passive"))
      (node (ref "IC103") (pin "2") (pinfunction "2_2") (pintype "passive"))
      (node (ref "IC104") (pin "2") (pinfunction "2_2") (pintype "passive"))
      (node (ref "IC105") (pin "2") (pinfunction "2_2") (pintype "passive"))
    )
    (net (code "603") (name "Net-(IC102-Pad3)") (class "Default")
      (node (ref "IC102") (pin "3") (pinfunction "3_3") (pintype "passive"))
      (node (ref "IC103") (pin "3") (pinfunction "3_3") (pintype "passive"))
      (node (ref "IC104") (pin "3") (pinfunction "3_3") (pintype "passive"))
      (node (ref "IC105") (pin "3") (pinfunction "3_3") (pintype "passive"))
    )
    (net (code "604") (name "Net-(IC102-Pad4)") (class "Default")
      (node (ref "IC102") (pin "4") (pinfunction "4_4") (pintype "passive"))
      (node (ref "IC103") (pin "4") (pinfunction "4_4") (pintype "passive"))
      (node (ref "IC104") (pin "4") (pinfunction "4_4") (pintype "passive"))
      (node (ref "IC105") (pin "4") (pinfunction "4_4") (pintype "passive"))
    )
    (net (code "605") (name "Net-(IC102-Pad5)") (class "Default")
      (node (ref "IC102") (pin "5") (pinfunction "5_5") (pintype "passive"))
      (node (ref "IC103") (pin "5") (pinfunction "5_5") (pintype "passive"))
      (node (ref "IC104") (pin "5") (pinfunction "5_5") (pintype "passive"))
      (node (ref "IC105") (pin "5") (pinfunction "5_5") (pintype "passive"))
    )
    (net (code "606") (name "Net-(IC102-Pad6)") (class "Default")
      (node (ref "IC102") (pin "6") (pinfunction "6_6") (pintype "passive"))
      (node (ref "IC103") (pin "6") (pinfunction "6_6") (pintype "passive"))
      (node (ref "IC104") (pin "6") (pinfunction "6_6") (pintype "passive"))
      (node (ref "IC105") (pin "6") (pinfunction "6_6") (pintype "passive"))
    )
    (net (code "607") (name "Net-(IC102-Pad7)") (class "Default")
      (node (ref "IC102") (pin "7") (pinfunction "7_7") (pintype "passive"))
      (node (ref "IC103") (pin "7") (pinfunction "7_7") (pintype "passive"))
      (node (ref "IC104") (pin "7") (pinfunction "7_7") (pintype "passive"))
      (node (ref "IC105") (pin "7") (pinfunction "7_7") (pintype "passive"))
    )
    (net (code "608") (name "Net-(IC102-Pad8)") (class "Default")
      (node (ref "IC102") (pin "8") (pinfunction "8_8") (pintype "passive"))
      (node (ref "IC103") (pin "8") (pinfunction "8_8") (pintype "passive"))
      (node (ref "IC104") (pin "8") (pinfunction "8_8") (pintype "passive"))
      (node (ref "IC105") (pin "8") (pinfunction "8_8") (pintype "passive"))
    )
    (net (code "609") (name "Net-(IC102-Pad9)") (class "Default")
      (node (ref "IC102") (pin "9") (pinfunction "9_9") (pintype "passive"))
      (node (ref "IC103") (pin "9") (pinfunction "9_9") (pintype "passive"))
      (node (ref "IC104") (pin "9") (pinfunction "9_9") (pintype "passive"))
      (node (ref "IC105") (pin "9") (pinfunction "9_9") (pintype "passive"))
    )
    (net (code "610") (name "Net-(IC102-Pad10)") (class "Default")
      (node (ref "IC102") (pin "10") (pinfunction "10_10") (pintype "passive"))
      (node (ref "IC103") (pin "10") (pinfunction "10_10") (pintype "passive"))
      (node (ref "IC104") (pin "10") (pinfunction "10_10") (pintype "passive"))
      (node (ref "IC105") (pin "10") (pinfunction "10_10") (pintype "passive"))
    )
    (net (code "611") (name "Net-(IC102-Pad11)") (class "Default")
      (node (ref "IC102") (pin "11") (pinfunction "11_11") (pintype "passive"))
      (node (ref "IC103") (pin "11") (pinfunction "11_11") (pintype "passive"))
      (node (ref "IC104") (pin "11") (pinfunction "11_11") (pintype "passive"))
      (node (ref "IC105") (pin "11") (pinfunction "11_11") (pintype "passive"))
    )
    (net (code "612") (name "Net-(IC102-Pad12)") (class "Default")
      (node (ref "IC102") (pin "12") (pinfunction "12_12") (pintype "passive"))
      (node (ref "IC103") (pin "12") (pinfunction "12_12") (pintype "passive"))
      (node (ref "IC104") (pin "12") (pinfunction "12_12") (pintype "passive"))
      (node (ref "IC105") (pin "12") (pinfunction "12_12") (pintype "passive"))
    )
    (net (code "613") (name "Net-(IC102-Pad13)") (class "Default")
      (node (ref "IC102") (pin "13") (pinfunction "13_13") (pintype "passive"))
      (node (ref "IC103") (pin "13") (pinfunction "13_13") (pintype "passive"))
      (node (ref "IC104") (pin "13") (pinfunction "13_13") (pintype "passive"))
      (node (ref "IC105") (pin "13") (pinfunction "13_13") (pintype "passive"))
    )
    (net (code "614") (name "Net-(IC102-Pad14)") (class "Default")
      (node (ref "IC102") (pin "14") (pinfunction "14_14") (pintype "passive"))
      (node (ref "IC103") (pin "14") (pinfunction "14_14") (pintype "passive"))
      (node (ref "IC104") (pin "14") (pinfunction "14_14") (pintype "passive"))
      (node (ref "IC105") (pin "14") (pinfunction "14_14") (pintype "passive"))
    )
    (net (code "615") (name "Net-(IC102-Pad15)") (class "Default")
      (node (ref "IC102") (pin "15") (pinfunction "15_15") (pintype "passive"))
      (node (ref "IC103") (pin "15") (pinfunction "15_15") (pintype "passive"))
      (node (ref "IC104") (pin "15") (pinfunction "15_15") (pintype "passive"))
      (node (ref "IC105") (pin "15") (pinfunction "15_15") (pintype "passive"))
    )
    (net (code "616") (name "Net-(IC102-Pad16)") (class "Default")
      (node (ref "IC102") (pin "16") (pinfunction "16_16") (pintype "passive"))
      (node (ref "IC103") (pin "16") (pinfunction "16_16") (pintype "passive"))
      (node (ref "IC104") (pin "16") (pinfunction "16_16") (pintype "passive"))
      (node (ref "IC105") (pin "16") (pinfunction "16_16") (pintype "passive"))
    )
    (net (code "617") (name "Net-(IC102-Pad17)") (class "Default")
      (node (ref "IC102") (pin "17") (pinfunction "17_17") (pintype "passive"))
      (node (ref "IC103") (pin "17") (pinfunction "17_17") (pintype "passive"))
      (node (ref "IC104") (pin "17") (pinfunction "17_17") (pintype "passive"))
      (node (ref "IC105") (pin "17") (pinfunction "17_17") (pintype "passive"))
    )
    (net (code "618") (name "Net-(IC102-Pad18)") (class "Default")
      (node (ref "IC102") (pin "18") (pinfunction "18_18") (pintype "passive"))
      (node (ref "IC103") (pin "18") (pinfunction "18_18") (pintype "passive"))
      (node (ref "IC104") (pin "18") (pinfunction "18_18") (pintype "passive"))
      (node (ref "IC105") (pin "18") (pinfunction "18_18") (pintype "passive"))
    )
    (net (code "619") (name "Net-(IC102-Pad19)") (class "Default")
      (node (ref "IC102") (pin "19") (pinfunction "19_19") (pintype "passive"))
      (node (ref "IC103") (pin "19") (pinfunction "19_19") (pintype "passive"))
      (node (ref "IC104") (pin "19") (pinfunction "19_19") (pintype "passive"))
      (node (ref "IC105") (pin "19") (pinfunction "19_19") (pintype "passive"))
    )
    (net (code "620") (name "Net-(IC102-Pad20)") (class "Default")
      (node (ref "IC102") (pin "20") (pinfunction "20_20") (pintype "passive"))
      (node (ref "IC103") (pin "20") (pinfunction "20_20") (pintype "passive"))
      (node (ref "IC104") (pin "20") (pinfunction "20_20") (pintype "passive"))
      (node (ref "IC105") (pin "20") (pinfunction "20_20") (pintype "passive"))
    )
    (net (code "621") (name "Net-(IC102-Pad21)") (class "Default")
      (node (ref "IC102") (pin "21") (pinfunction "21_21") (pintype "passive"))
      (node (ref "IC103") (pin "21") (pinfunction "21_21") (pintype "passive"))
      (node (ref "IC104") (pin "21") (pinfunction "21_21") (pintype "passive"))
      (node (ref "IC105") (pin "21") (pinfunction "21_21") (pintype "passive"))
    )
    (net (code "622") (name "Net-(IC102-Pad22)") (class "Default")
      (node (ref "IC102") (pin "22") (pinfunction "22_22") (pintype "passive"))
      (node (ref "IC103") (pin "22") (pinfunction "22_22") (pintype "passive"))
      (node (ref "IC104") (pin "22") (pinfunction "22_22") (pintype "passive"))
      (node (ref "IC105") (pin "22") (pinfunction "22_22") (pintype "passive"))
    )
    (net (code "623") (name "Net-(IC102-Pad23)") (class "Default")
      (node (ref "IC102") (pin "23") (pinfunction "23_23") (pintype "passive"))
      (node (ref "IC103") (pin "23") (pinfunction "23_23") (pintype "passive"))
      (node (ref "IC104") (pin "23") (pinfunction "23_23") (pintype "passive"))
      (node (ref "IC105") (pin "23") (pinfunction "23_23") (pintype "passive"))
    )
    (net (code "624") (name "Net-(IC102-Pad24)") (class "Default")
      (node (ref "IC102") (pin "24") (pinfunction "24_24") (pintype "passive"))
      (node (ref "IC103") (pin "24") (pinfunction "24_24") (pintype "passive"))
      (node (ref "IC104") (pin "24") (pinfunction "24_24") (pintype "passive"))
      (node (ref "IC105") (pin "24") (pinfunction "24_24") (pintype "passive"))
    )
    (net (code "625") (name "Net-(IC106-Pad1)") (class "Default")
      (node (ref "IC106") (pin "1") (pinfunction "1_1") (pintype "passive"))
      (node (ref "IC107") (pin "1") (pinfunction "1_1") (pintype "passive"))
      (node (ref "IC108") (pin "1") (pinfunction "1_1") (pintype "passive"))
      (node (ref "IC109") (pin "1") (pinfunction "1_1") (pintype "passive"))
    )
    (net (code "626") (name "Net-(IC106-Pad2)") (class "Default")
      (node (ref "IC106") (pin "2") (pinfunction "2_2") (pintype "passive"))
      (node (ref "IC107") (pin "2") (pinfunction "2_2") (pintype "passive"))
      (node (ref "IC108") (pin "2") (pinfunction "2_2") (pintype "passive"))
      (node (ref "IC109") (pin "2") (pinfunction "2_2") (pintype "passive"))
    )
    (net (code "627") (name "Net-(IC106-Pad3)") (class "Default")
      (node (ref "IC106") (pin "3") (pinfunction "3_3") (pintype "passive"))
      (node (ref "IC107") (pin "3") (pinfunction "3_3") (pintype "passive"))
      (node (ref "IC108") (pin "3") (pinfunction "3_3") (pintype "passive"))
      (node (ref "IC109") (pin "3") (pinfunction "3_3") (pintype "passive"))
    )
    (net (code "628") (name "Net-(IC106-Pad4)") (class "Default")
      (node (ref "IC106") (pin "4") (pinfunction "4_4") (pintype "passive"))
      (node (ref "IC107") (pin "4") (pinfunction "4_4") (pintype "passive"))
      (node (ref "IC108") (pin "4") (pinfunction "4_4") (pintype "passive"))
      (node (ref "IC109") (pin "4") (pinfunction "4_4") (pintype "passive"))
    )
    (net (code "629") (name "Net-(IC106-Pad5)") (class "Default")
      (node (ref "IC106") (pin "5") (pinfunction "5_5") (pintype "passive"))
      (node (ref "IC107") (pin "5") (pinfunction "5_5") (pintype "passive"))
      (node (ref "IC108") (pin "5") (pinfunction "5_5") (pintype "passive"))
      (node (ref "IC109") (pin "5") (pinfunction "5_5") (pintype "passive"))
    )
    (net (code "630") (name "Net-(IC106-Pad6)") (class "Default")
      (node (ref "IC106") (pin "6") (pinfunction "6_6") (pintype "passive"))
      (node (ref "IC107") (pin "6") (pinfunction "6_6") (pintype "passive"))
      (node (ref "IC108") (pin "6") (pinfunction "6_6") (pintype "passive"))
      (node (ref "IC109") (pin "6") (pinfunction "6_6") (pintype "passive"))
    )
    (net (code "631") (name "Net-(IC106-Pad7)") (class "Default")
      (node (ref "IC106") (pin "7") (pinfunction "7_7") (pintype "passive"))
      (node (ref "IC107") (pin "7") (pinfunction "7_7") (pintype "passive"))
      (node (ref "IC108") (pin "7") (pinfunction "7_7") (pintype "passive"))
      (node (ref "IC109") (pin "7") (pinfunction "7_7") (pintype "passive"))
    )
    (net (code "632") (name "Net-(IC106-Pad8)") (class "Default")
      (node (ref "IC106") (pin "8") (pinfunction "8_8") (pintype "passive"))
      (node (ref "IC107") (pin "8") (pinfunction "8_8") (pintype "passive"))
      (node (ref "IC108") (pin "8") (pinfunction "8_8") (pintype "passive"))
      (node (ref "IC109") (pin "8") (pinfunction "8_8") (pintype "passive"))
    )
    (net (code "633") (name "Net-(IC106-Pad9)") (class "Default")
      (node (ref "IC106") (pin "9") (pinfunction "9_9") (pintype "passive"))
      (node (ref "IC107") (pin "9") (pinfunction "9_9") (pintype "passive"))
      (node (ref "IC108") (pin "9") (pinfunction "9_9") (pintype "passive"))
      (node (ref "IC109") (pin "9") (pinfunction "9_9") (pintype "passive"))
    )
    (net (code "634") (name "Net-(IC106-Pad10)") (class "Default")
      (node (ref "IC106") (pin "10") (pinfunction "10_10") (pintype "passive"))
      (node (ref "IC107") (pin "10") (pinfunction "10_10") (pintype "passive"))
      (node (ref "IC108") (pin "10") (pinfunction "10_10") (pintype "passive"))
      (node (ref "IC109") (pin "10") (pinfunction "10_10") (pintype "passive"))
    )
    (net (code "635") (name "Net-(IC106-Pad11)") (class "Default")
      (node (ref "IC106") (pin "11") (pinfunction "11_11") (pintype "passive"))
      (node (ref "IC107") (pin "11") (pinfunction "11_11") (pintype "passive"))
      (node (ref "IC108") (pin "11") (pinfunction "11_11") (pintype "passive"))
      (node (ref "IC109") (pin "11") (pinfunction "11_11") (pintype "passive"))
    )
    (net (code "636") (name "Net-(IC106-Pad12)") (class "Default")
      (node (ref "IC106") (pin "12") (pinfunction "12_12") (pintype "passive"))
      (node (ref "IC107") (pin "12") (pinfunction "12_12") (pintype "passive"))
      (node (ref "IC108") (pin "12") (pinfunction "12_12") (pintype "passive"))
      (node (ref "IC109") (pin "12") (pinfunction "12_12") (pintype "passive"))
    )
    (net (code "637") (name "Net-(IC106-Pad13)") (class "Default")
      (node (ref "IC106") (pin "13") (pinfunction "13_13") (pintype "passive"))
      (node (ref "IC107") (pin "13") (pinfunction "13_13") (pintype "passive"))
      (node (ref "IC108") (pin "13") (pinfunction "13_13") (pintype "passive"))
      (node (ref "IC109") (pin "13") (pinfunction "13_13") (pintype "passive"))
    )
    (net (code "638") (name "Net-(IC106-Pad14)") (class "Default")
      (node (ref "IC106") (pin "14") (pinfunction "14_14") (pintype "passive"))
      (node (ref "IC107") (pin "14") (pinfunction "14_14") (pintype "passive"))
      (node (ref "IC108") (pin "14") (pinfunction "14_14") (pintype "passive"))
      (node (ref "IC109") (pin "14") (pinfunction "14_14") (pintype "passive"))
    )
    (net (code "639") (name "Net-(IC106-Pad15)") (class "Default")
      (node (ref "IC106") (pin "15") (pinfunction "15_15") (pintype "passive"))
      (node (ref "IC107") (pin "15") (pinfunction "15_15") (pintype "passive"))
      (node (ref "IC108") (pin "15") (pinfunction "15_15") (pintype "passive"))
      (node (ref "IC109") (pin "15") (pinfunction "15_15") (pintype "passive"))
    )
    (net (code "640") (name "Net-(IC106-Pad16)") (class "Default")
      (node (ref "IC106") (pin "16") (pinfunction "16_16") (pintype "passive"))
      (node (ref "IC107") (pin "16") (pinfunction "16_16") (pintype "passive"))
      (node (ref "IC108") (pin "16") (pinfunction "16_16") (pintype "passive"))
      (node (ref "IC109") (pin "16") (pinfunction "16_16") (pintype "passive"))
    )
    (net (code "641") (name "Net-(IC106-Pad17)") (class "Default")
      (node (ref "IC106") (pin "17") (pinfunction "17_17") (pintype "passive"))
      (node (ref "IC107") (pin "17") (pinfunction "17_17") (pintype "passive"))
      (node (ref "IC108") (pin "17") (pinfunction "17_17") (pintype "passive"))
      (node (ref "IC109") (pin "17") (pinfunction "17_17") (pintype "passive"))
    )
    (net (code "642") (name "Net-(IC106-Pad18)") (class "Default")
      (node (ref "IC106") (pin "18") (pinfunction "18_18") (pintype "passive"))
      (node (ref "IC107") (pin "18") (pinfunction "18_18") (pintype "passive"))
      (node (ref "IC108") (pin "18") (pinfunction "18_18") (pintype "passive"))
      (node (ref "IC109") (pin "18") (pinfunction "18_18") (pintype "passive"))
    )
    (net (code "643") (name "Net-(IC106-Pad19)") (class "Default")
      (node (ref "IC106") (pin "19") (pinfunction "19_19") (pintype "passive"))
      (node (ref "IC107") (pin "19") (pinfunction "19_19") (pintype "passive"))
      (node (ref "IC108") (pin "19") (pinfunction "19_19") (pintype "passive"))
      (node (ref "IC109") (pin "19") (pinfunction "19_19") (pintype "passive"))
    )
    (net (code "644") (name "Net-(IC106-Pad20)") (class "Default")
      (node (ref "IC106") (pin "20") (pinfunction "20_20") (pintype "passive"))
      (node (ref "IC107") (pin "20") (pinfunction "20_20") (pintype "passive"))
      (node (ref "IC108") (pin "20") (pinfunction "20_20") (pintype "passive"))
      (node (ref "IC109") (pin "20") (pinfunction "20_20") (pintype "passive"))
    )
    (net (code "645") (name "Net-(IC106-Pad21)") (class "Default")
      (node (ref "IC106") (pin "21") (pinfunction "21_21") (pintype "passive"))
      (node (ref "IC107") (pin "21") (pinfunction "21_21") (pintype "passive"))
      (node (ref "IC108") (pin "21") (pinfunction "21_21") (pintype "passive"))
      (node (ref "IC109") (pin "21") (pinfunction "21_21") (pintype "passive"))
    )
    (net (code "646") (name "Net-(IC106-Pad22)") (class "Default")
      (node (ref "IC106") (pin "22") (pinfunction "22_22") (pintype "passive"))
      (node (ref "IC107") (pin "22") (pinfunction "22_22") (pintype "passive"))
      (node (ref "IC108") (pin "22") (pinfunction "22_22") (pintype "passive"))
      (node (ref "IC109") (pin "22") (pinfunction "22_22") (pintype "passive"))
    )
    (net (code "647") (name "Net-(IC106-Pad23)") (class "Default")
      (node (ref "IC106") (pin "23") (pinfunction "23_23") (pintype "passive"))
      (node (ref "IC107") (pin "23") (pinfunction "23_23") (pintype "passive"))
      (node (ref "IC108") (pin "23") (pinfunction "23_23") (pintype "passive"))
      (node (ref "IC109") (pin "23") (pinfunction "23_23") (pintype "passive"))
    )
    (net (code "648") (name "Net-(IC106-Pad24)") (class "Default")
      (node (ref "IC106") (pin "24") (pinfunction "24_24") (pintype "passive"))
      (node (ref "IC107") (pin "24") (pinfunction "24_24") (pintype "passive"))
      (node (ref "IC108") (pin "24") (pinfunction "24_24") (pintype "passive"))
      (node (ref "IC109") (pin "24") (pinfunction "24_24") (pintype "passive"))
    )
    (net (code "649") (name "Net-(IC110-Pad1)") (class "Default")
      (node (ref "IC110") (pin "1") (pinfunction "1_1") (pintype "passive"))
      (node (ref "IC111") (pin "1") (pinfunction "1_1") (pintype "passive"))
      (node (ref "IC112") (pin "1") (pinfunction "1_1") (pintype "passive"))
      (node (ref "IC113") (pin "1") (pinfunction "1_1") (pintype "passive"))
    )
    (net (code "650") (name "Net-(IC110-Pad2)") (class "Default")
      (node (ref "IC110") (pin "2") (pinfunction "2_2") (pintype "passive"))
      (node (ref "IC111") (pin "2") (pinfunction "2_2") (pintype "passive"))
      (node (ref "IC112") (pin "2") (pinfunction "2_2") (pintype "passive"))
      (node (ref "IC113") (pin "2") (pinfunction "2_2") (pintype "passive"))
    )
    (net (code "651") (name "Net-(IC110-Pad3)") (class "Default")
      (node (ref "IC110") (pin "3") (pinfunction "3_3") (pintype "passive"))
      (node (ref "IC111") (pin "3") (pinfunction "3_3") (pintype "passive"))
      (node (ref "IC112") (pin "3") (pinfunction "3_3") (pintype "passive"))
      (node (ref "IC113") (pin "3") (pinfunction "3_3") (pintype "passive"))
    )
    (net (code "652") (name "Net-(IC110-Pad4)") (class "Default")
      (node (ref "IC110") (pin "4") (pinfunction "4_4") (pintype "passive"))
      (node (ref "IC111") (pin "4") (pinfunction "4_4") (pintype "passive"))
      (node (ref "IC112") (pin "4") (pinfunction "4_4") (pintype "passive"))
      (node (ref "IC113") (pin "4") (pinfunction "4_4") (pintype "passive"))
    )
    (net (code "653") (name "Net-(IC110-Pad5)") (class "Default")
      (node (ref "IC110") (pin "5") (pinfunction "5_5") (pintype "passive"))
      (node (ref "IC111") (pin "5") (pinfunction "5_5") (pintype "passive"))
      (node (ref "IC112") (pin "5") (pinfunction "5_5") (pintype "passive"))
      (node (ref "IC113") (pin "5") (pinfunction "5_5") (pintype "passive"))
    )
    (net (code "654") (name "Net-(IC110-Pad6)") (class "Default")
      (node (ref "IC110") (pin "6") (pinfunction "6_6") (pintype "passive"))
      (node (ref "IC111") (pin "6") (pinfunction "6_6") (pintype "passive"))
      (node (ref "IC112") (pin "6") (pinfunction "6_6") (pintype "passive"))
      (node (ref "IC113") (pin "6") (pinfunction "6_6") (pintype "passive"))
    )
    (net (code "655") (name "Net-(IC110-Pad7)") (class "Default")
      (node (ref "IC110") (pin "7") (pinfunction "7_7") (pintype "passive"))
      (node (ref "IC111") (pin "7") (pinfunction "7_7") (pintype "passive"))
      (node (ref "IC112") (pin "7") (pinfunction "7_7") (pintype "passive"))
      (node (ref "IC113") (pin "7") (pinfunction "7_7") (pintype "passive"))
    )
    (net (code "656") (name "Net-(IC110-Pad8)") (class "Default")
      (node (ref "IC110") (pin "8") (pinfunction "8_8") (pintype "passive"))
      (node (ref "IC111") (pin "8") (pinfunction "8_8") (pintype "passive"))
      (node (ref "IC112") (pin "8") (pinfunction "8_8") (pintype "passive"))
      (node (ref "IC113") (pin "8") (pinfunction "8_8") (pintype "passive"))
    )
    (net (code "657") (name "Net-(IC110-Pad9)") (class "Default")
      (node (ref "IC110") (pin "9") (pinfunction "9_9") (pintype "passive"))
      (node (ref "IC111") (pin "9") (pinfunction "9_9") (pintype "passive"))
      (node (ref "IC112") (pin "9") (pinfunction "9_9") (pintype "passive"))
      (node (ref "IC113") (pin "9") (pinfunction "9_9") (pintype "passive"))
    )
    (net (code "658") (name "Net-(IC110-Pad10)") (class "Default")
      (node (ref "IC110") (pin "10") (pinfunction "10_10") (pintype "passive"))
      (node (ref "IC111") (pin "10") (pinfunction "10_10") (pintype "passive"))
      (node (ref "IC112") (pin "10") (pinfunction "10_10") (pintype "passive"))
      (node (ref "IC113") (pin "10") (pinfunction "10_10") (pintype "passive"))
    )
    (net (code "659") (name "Net-(IC110-Pad11)") (class "Default")
      (node (ref "IC110") (pin "11") (pinfunction "11_11") (pintype "passive"))
      (node (ref "IC111") (pin "11") (pinfunction "11_11") (pintype "passive"))
      (node (ref "IC112") (pin "11") (pinfunction "11_11") (pintype "passive"))
      (node (ref "IC113") (pin "11") (pinfunction "11_11") (pintype "passive"))
    )
    (net (code "660") (name "Net-(IC110-Pad12)") (class "Default")
      (node (ref "IC110") (pin "12") (pinfunction "12_12") (pintype "passive"))
      (node (ref "IC111") (pin "12") (pinfunction "12_12") (pintype "passive"))
      (node (ref "IC112") (pin "12") (pinfunction "12_12") (pintype "passive"))
      (node (ref "IC113") (pin "12") (pinfunction "12_12") (pintype "passive"))
    )
    (net (code "661") (name "Net-(IC110-Pad13)") (class "Default")
      (node (ref "IC110") (pin "13") (pinfunction "13_13") (pintype "passive"))
      (node (ref "IC111") (pin "13") (pinfunction "13_13") (pintype "passive"))
      (node (ref "IC112") (pin "13") (pinfunction "13_13") (pintype "passive"))
      (node (ref "IC113") (pin "13") (pinfunction "13_13") (pintype "passive"))
    )
    (net (code "662") (name "Net-(IC110-Pad14)") (class "Default")
      (node (ref "IC110") (pin "14") (pinfunction "14_14") (pintype "passive"))
      (node (ref "IC111") (pin "14") (pinfunction "14_14") (pintype "passive"))
      (node (ref "IC112") (pin "14") (pinfunction "14_14") (pintype "passive"))
      (node (ref "IC113") (pin "14") (pinfunction "14_14") (pintype "passive"))
    )
    (net (code "663") (name "Net-(IC110-Pad15)") (class "Default")
      (node (ref "IC110") (pin "15") (pinfunction "15_15") (pintype "passive"))
      (node (ref "IC111") (pin "15") (pinfunction "15_15") (pintype "passive"))
      (node (ref "IC112") (pin "15") (pinfunction "15_15") (pintype "passive"))
      (node (ref "IC113") (pin "15") (pinfunction "15_15") (pintype "passive"))
    )
    (net (code "664") (name "Net-(IC110-Pad16)") (class "Default")
      (node (ref "IC110") (pin "16") (pinfunction "16_16") (pintype "passive"))
      (node (ref "IC111") (pin "16") (pinfunction "16_16") (pintype "passive"))
      (node (ref "IC112") (pin "16") (pinfunction "16_16") (pintype "passive"))
      (node (ref "IC113") (pin "16") (pinfunction "16_16") (pintype "passive"))
    )
    (net (code "665") (name "Net-(IC110-Pad17)") (class "Default")
      (node (ref "IC110") (pin "17") (pinfunction "17_17") (pintype "passive"))
      (node (ref "IC111") (pin "17") (pinfunction "17_17") (pintype "passive"))
      (node (ref "IC112") (pin "17") (pinfunction "17_17") (pintype "passive"))
      (node (ref "IC113") (pin "17") (pinfunction "17_17") (pintype "passive"))
    )
    (net (code "666") (name "Net-(IC110-Pad18)") (class "Default")
      (node (ref "IC110") (pin "18") (pinfunction "18_18") (pintype "passive"))
      (node (ref "IC111") (pin "18") (pinfunction "18_18") (pintype "passive"))
      (node (ref "IC112") (pin "18") (pinfunction "18_18") (pintype "passive"))
      (node (ref "IC113") (pin "18") (pinfunction "18_18") (pintype "passive"))
    )
    (net (code "667") (name "Net-(IC110-Pad19)") (class "Default")
      (node (ref "IC110") (pin "19") (pinfunction "19_19") (pintype "passive"))
      (node (ref "IC111") (pin "19") (pinfunction "19_19") (pintype "passive"))
      (node (ref "IC112") (pin "19") (pinfunction "19_19") (pintype "passive"))
      (node (ref "IC113") (pin "19") (pinfunction "19_19") (pintype "passive"))
    )
    (net (code "668") (name "Net-(IC110-Pad20)") (class "Default")
      (node (ref "IC110") (pin "20") (pinfunction "20_20") (pintype "passive"))
      (node (ref "IC111") (pin "20") (pinfunction "20_20") (pintype "passive"))
      (node (ref "IC112") (pin "20") (pinfunction "20_20") (pintype "passive"))
      (node (ref "IC113") (pin "20") (pinfunction "20_20") (pintype "passive"))
    )
    (net (code "669") (name "Net-(IC110-Pad21)") (class "Default")
      (node (ref "IC110") (pin "21") (pinfunction "21_21") (pintype "passive"))
      (node (ref "IC111") (pin "21") (pinfunction "21_21") (pintype "passive"))
      (node (ref "IC112") (pin "21") (pinfunction "21_21") (pintype "passive"))
      (node (ref "IC113") (pin "21") (pinfunction "21_21") (pintype "passive"))
    )
    (net (code "670") (name "Net-(IC110-Pad22)") (class "Default")
      (node (ref "IC110") (pin "22") (pinfunction "22_22") (pintype "passive"))
      (node (ref "IC111") (pin "22") (pinfunction "22_22") (pintype "passive"))
      (node (ref "IC112") (pin "22") (pinfunction "22_22") (pintype "passive"))
      (node (ref "IC113") (pin "22") (pinfunction "22_22") (pintype "passive"))
    )
    (net (code "671") (name "Net-(IC110-Pad23)") (class "Default")
      (node (ref "IC110") (pin "23") (pinfunction "23_23") (pintype "passive"))
      (node (ref "IC111") (pin "23") (pinfunction "23_23") (pintype "passive"))
      (node (ref "IC112") (pin "23") (pinfunction "23_23") (pintype "passive"))
      (node (ref "IC113") (pin "23") (pinfunction "23_23") (pintype "passive"))
    )
    (net (code "672") (name "Net-(IC110-Pad24)") (class "Default")
      (node (ref "IC110") (pin "24") (pinfunction "24_24") (pintype "passive"))
      (node (ref "IC111") (pin "24") (pinfunction "24_24") (pintype "passive"))
      (node (ref "IC112") (pin "24") (pinfunction "24_24") (pintype "passive"))
      (node (ref "IC113") (pin "24") (pinfunction "24_24") (pintype "passive"))
    )
    (net (code "673") (name "Net-(IC114-Pad1)") (class "Default")
      (node (ref "IC114") (pin "1") (pinfunction "1_1") (pintype "passive"))
      (node (ref "IC115") (pin "1") (pinfunction "1_1") (pintype "passive"))
      (node (ref "IC116") (pin "1") (pinfunction "1_1") (pintype "passive"))
      (node (ref "IC117") (pin "1") (pinfunction "1_1") (pintype "passive"))
    )
    (net (code "674") (name "Net-(IC114-Pad2)") (class "Default")
      (node (ref "IC114") (pin "2") (pinfunction "2_2") (pintype "passive"))
      (node (ref "IC115") (pin "2") (pinfunction "2_2") (pintype "passive"))
      (node (ref "IC116") (pin "2") (pinfunction "2_2") (pintype "passive"))
      (node (ref "IC117") (pin "2") (pinfunction "2_2") (pintype "passive"))
    )
    (net (code "675") (name "Net-(IC114-Pad3)") (class "Default")
      (node (ref "IC114") (pin "3") (pinfunction "3_3") (pintype "passive"))
      (node (ref "IC115") (pin "3") (pinfunction "3_3") (pintype "passive"))
      (node (ref "IC116") (pin "3") (pinfunction "3_3") (pintype "passive"))
      (node (ref "IC117") (pin "3") (pinfunction "3_3") (pintype "passive"))
    )
    (net (code "676") (name "Net-(IC114-Pad4)") (class "Default")
      (node (ref "IC114") (pin "4") (pinfunction "4_4") (pintype "passive"))
      (node (ref "IC115") (pin "4") (pinfunction "4_4") (pintype "passive"))
      (node (ref "IC116") (pin "4") (pinfunction "4_4") (pintype "passive"))
      (node (ref "IC117") (pin "4") (pinfunction "4_4") (pintype "passive"))
    )
    (net (code "677") (name "Net-(IC114-Pad5)") (class "Default")
      (node (ref "IC114") (pin "5") (pinfunction "5_5") (pintype "passive"))
      (node (ref "IC115") (pin "5") (pinfunction "5_5") (pintype "passive"))
      (node (ref "IC116") (pin "5") (pinfunction "5_5") (pintype "passive"))
      (node (ref "IC117") (pin "5") (pinfunction "5_5") (pintype "passive"))
    )
    (net (code "678") (name "Net-(IC114-Pad6)") (class "Default")
      (node (ref "IC114") (pin "6") (pinfunction "6_6") (pintype "passive"))
      (node (ref "IC115") (pin "6") (pinfunction "6_6") (pintype "passive"))
      (node (ref "IC116") (pin "6") (pinfunction "6_6") (pintype "passive"))
      (node (ref "IC117") (pin "6") (pinfunction "6_6") (pintype "passive"))
    )
    (net (code "679") (name "Net-(IC114-Pad7)") (class "Default")
      (node (ref "IC114") (pin "7") (pinfunction "7_7") (pintype "passive"))
      (node (ref "IC115") (pin "7") (pinfunction "7_7") (pintype "passive"))
      (node (ref "IC116") (pin "7") (pinfunction "7_7") (pintype "passive"))
      (node (ref "IC117") (pin "7") (pinfunction "7_7") (pintype "passive"))
    )
    (net (code "680") (name "Net-(IC114-Pad8)") (class "Default")
      (node (ref "IC114") (pin "8") (pinfunction "8_8") (pintype "passive"))
      (node (ref "IC115") (pin "8") (pinfunction "8_8") (pintype "passive"))
      (node (ref "IC116") (pin "8") (pinfunction "8_8") (pintype "passive"))
      (node (ref "IC117") (pin "8") (pinfunction "8_8") (pintype "passive"))
    )
    (net (code "681") (name "Net-(IC114-Pad9)") (class "Default")
      (node (ref "IC114") (pin "9") (pinfunction "9_9") (pintype "passive"))
      (node (ref "IC115") (pin "9") (pinfunction "9_9") (pintype "passive"))
      (node (ref "IC116") (pin "9") (pinfunction "9_9") (pintype "passive"))
      (node (ref "IC117") (pin "9") (pinfunction "9_9") (pintype "passive"))
    )
    (net (code "682") (name "Net-(IC114-Pad10)") (class "Default")
      (node (ref "IC114") (pin "10") (pinfunction "10_10") (pintype "passive"))
      (node (ref "IC115") (pin "10") (pinfunction "10_10") (pintype "passive"))
      (node (ref "IC116") (pin "10") (pinfunction "10_10") (pintype "passive"))
      (node (ref "IC117") (pin "10") (pinfunction "10_10") (pintype "passive"))
    )
    (net (code "683") (name "Net-(IC114-Pad11)") (class "Default")
      (node (ref "IC114") (pin "11") (pinfunction "11_11") (pintype "passive"))
      (node (ref "IC115") (pin "11") (pinfunction "11_11") (pintype "passive"))
      (node (ref "IC116") (pin "11") (pinfunction "11_11") (pintype "passive"))
      (node (ref "IC117") (pin "11") (pinfunction "11_11") (pintype "passive"))
    )
    (net (code "684") (name "Net-(IC114-Pad12)") (class "Default")
      (node (ref "IC114") (pin "12") (pinfunction "12_12") (pintype "passive"))
      (node (ref "IC115") (pin "12") (pinfunction "12_12") (pintype "passive"))
      (node (ref "IC116") (pin "12") (pinfunction "12_12") (pintype "passive"))
      (node (ref "IC117") (pin "12") (pinfunction "12_12") (pintype "passive"))
    )
    (net (code "685") (name "Net-(IC114-Pad13)") (class "Default")
      (node (ref "IC114") (pin "13") (pinfunction "13_13") (pintype "passive"))
      (node (ref "IC115") (pin "13") (pinfunction "13_13") (pintype "passive"))
      (node (ref "IC116") (pin "13") (pinfunction "13_13") (pintype "passive"))
      (node (ref "IC117") (pin "13") (pinfunction "13_13") (pintype "passive"))
    )
    (net (code "686") (name "Net-(IC114-Pad14)") (class "Default")
      (node (ref "IC114") (pin "14") (pinfunction "14_14") (pintype "passive"))
      (node (ref "IC115") (pin "14") (pinfunction "14_14") (pintype "passive"))
      (node (ref "IC116") (pin "14") (pinfunction "14_14") (pintype "passive"))
      (node (ref "IC117") (pin "14") (pinfunction "14_14") (pintype "passive"))
    )
    (net (code "687") (name "Net-(IC114-Pad15)") (class "Default")
      (node (ref "IC114") (pin "15") (pinfunction "15_15") (pintype "passive"))
      (node (ref "IC115") (pin "15") (pinfunction "15_15") (pintype "passive"))
      (node (ref "IC116") (pin "15") (pinfunction "15_15") (pintype "passive"))
      (node (ref "IC117") (pin "15") (pinfunction "15_15") (pintype "passive"))
    )
    (net (code "688") (name "Net-(IC114-Pad16)") (class "Default")
      (node (ref "IC114") (pin "16") (pinfunction "16_16") (pintype "passive"))
      (node (ref "IC115") (pin "16") (pinfunction "16_16") (pintype "passive"))
      (node (ref "IC116") (pin "16") (pinfunction "16_16") (pintype "passive"))
      (node (ref "IC117") (pin "16") (pinfunction "16_16") (pintype "passive"))
    )
    (net (code "689") (name "Net-(IC114-Pad17)") (class "Default")
      (node (ref "IC114") (pin "17") (pinfunction "17_17") (pintype "passive"))
      (node (ref "IC115") (pin "17") (pinfunction "17_17") (pintype "passive"))
      (node (ref "IC116") (pin "17") (pinfunction "17_17") (pintype "passive"))
      (node (ref "IC117") (pin "17") (pinfunction "17_17") (pintype "passive"))
    )
    (net (code "690") (name "Net-(IC114-Pad18)") (class "Default")
      (node (ref "IC114") (pin "18") (pinfunction "18_18") (pintype "passive"))
      (node (ref "IC115") (pin "18") (pinfunction "18_18") (pintype "passive"))
      (node (ref "IC116") (pin "18") (pinfunction "18_18") (pintype "passive"))
      (node (ref "IC117") (pin "18") (pinfunction "18_18") (pintype "passive"))
    )
    (net (code "691") (name "Net-(IC114-Pad19)") (class "Default")
      (node (ref "IC114") (pin "19") (pinfunction "19_19") (pintype "passive"))
      (node (ref "IC115") (pin "19") (pinfunction "19_19") (pintype "passive"))
      (node (ref "IC116") (pin "19") (pinfunction "19_19") (pintype "passive"))
      (node (ref "IC117") (pin "19") (pinfunction "19_19") (pintype "passive"))
    )
    (net (code "692") (name "Net-(IC114-Pad20)") (class "Default")
      (node (ref "IC114") (pin "20") (pinfunction "20_20") (pintype "passive"))
      (node (ref "IC115") (pin "20") (pinfunction "20_20") (pintype "passive"))
      (node (ref "IC116") (pin "20") (pinfunction "20_20") (pintype "passive"))
      (node (ref "IC117") (pin "20") (pinfunction "20_20") (pintype "passive"))
    )
    (net (code "693") (name "Net-(IC114-Pad21)") (class "Default")
      (node (ref "IC114") (pin "21") (pinfunction "21_21") (pintype "passive"))
      (node (ref "IC115") (pin "21") (pinfunction "21_21") (pintype "passive"))
      (node (ref "IC116") (pin "21") (pinfunction "21_21") (pintype "passive"))
      (node (ref "IC117") (pin "21") (pinfunction "21_21") (pintype "passive"))
    )
    (net (code "694") (name "Net-(IC114-Pad22)") (class "Default")
      (node (ref "IC114") (pin "22") (pinfunction "22_22") (pintype "passive"))
      (node (ref "IC115") (pin "22") (pinfunction "22_22") (pintype "passive"))
      (node (ref "IC116") (pin "22") (pinfunction "22_22") (pintype "passive"))
      (node (ref "IC117") (pin "22") (pinfunction "22_22") (pintype "passive"))
    )
    (net (code "695") (name "Net-(IC114-Pad23)") (class "Default")
      (node (ref "IC114") (pin "23") (pinfunction "23_23") (pintype "passive"))
      (node (ref "IC115") (pin "23") (pinfunction "23_23") (pintype "passive"))
      (node (ref "IC116") (pin "23") (pinfunction "23_23") (pintype "passive"))
      (node (ref "IC117") (pin "23") (pinfunction "23_23") (pintype "passive"))
    )
    (net (code "696") (name "Net-(IC114-Pad24)") (class "Default")
      (node (ref "IC114") (pin "24") (pinfunction "24_24") (pintype "passive"))
      (node (ref "IC115") (pin "24") (pinfunction "24_24") (pintype "passive"))
      (node (ref "IC116") (pin "24") (pinfunction "24_24") (pintype "passive"))
      (node (ref "IC117") (pin "24") (pinfunction "24_24") (pintype "passive"))
    )
    (net (code "697") (name "Net-(IC118-Pad1)") (class "Default")
      (node (ref "IC118") (pin "1") (pinfunction "1_1") (pintype "passive"))
      (node (ref "IC119") (pin "1") (pinfunction "1_1") (pintype "passive"))
      (node (ref "IC120") (pin "1") (pinfunction "1_1") (pintype "passive"))
      (node (ref "IC121") (pin "1") (pinfunction "1_1") (pintype "passive"))
    )
    (net (code "698") (name "Net-(IC118-Pad2)") (class "Default")
      (node (ref "IC118") (pin "2") (pinfunction "2_2") (pintype "passive"))
      (node (ref "IC119") (pin "2") (pinfunction "2_2") (pintype "passive"))
      (node (ref "IC120") (pin "2") (pinfunction "2_2") (pintype "passive"))
      (node (ref "IC121") (pin "2") (pinfunction "2_2") (pintype "passive"))
    )
    (net (code "699") (name "Net-(IC118-Pad3)") (class "Default")
      (node (ref "IC118") (pin "3") (pinfunction "3_3") (pintype "passive"))
      (node (ref "IC119") (pin "3") (pinfunction "3_3") (pintype "passive"))
      (node (ref "IC120") (pin "3") (pinfunction "3_3") (pintype "passive"))
      (node (ref "IC121") (pin "3") (pinfunction "3_3") (pintype "passive"))
    )
    (net (code "700") (name "Net-(IC118-Pad4)") (class "Default")
      (node (ref "IC118") (pin "4") (pinfunction "4_4") (pintype "passive"))
      (node (ref "IC119") (pin "4") (pinfunction "4_4") (pintype "passive"))
      (node (ref "IC120") (pin "4") (pinfunction "4_4") (pintype "passive"))
      (node (ref "IC121") (pin "4") (pinfunction "4_4") (pintype "passive"))
    )
    (net (code "701") (name "Net-(IC118-Pad5)") (class "Default")
      (node (ref "IC118") (pin "5") (pinfunction "5_5") (pintype "passive"))
      (node (ref "IC119") (pin "5") (pinfunction "5_5") (pintype "passive"))
      (node (ref "IC120") (pin "5") (pinfunction "5_5") (pintype "passive"))
      (node (ref "IC121") (pin "5") (pinfunction "5_5") (pintype "passive"))
    )
    (net (code "702") (name "Net-(IC118-Pad6)") (class "Default")
      (node (ref "IC118") (pin "6") (pinfunction "6_6") (pintype "passive"))
      (node (ref "IC119") (pin "6") (pinfunction "6_6") (pintype "passive"))
      (node (ref "IC120") (pin "6") (pinfunction "6_6") (pintype "passive"))
      (node (ref "IC121") (pin "6") (pinfunction "6_6") (pintype "passive"))
    )
    (net (code "703") (name "Net-(IC118-Pad7)") (class "Default")
      (node (ref "IC118") (pin "7") (pinfunction "7_7") (pintype "passive"))
      (node (ref "IC119") (pin "7") (pinfunction "7_7") (pintype "passive"))
      (node (ref "IC120") (pin "7") (pinfunction "7_7") (pintype "passive"))
      (node (ref "IC121") (pin "7") (pinfunction "7_7") (pintype "passive"))
    )
    (net (code "704") (name "Net-(IC118-Pad8)") (class "Default")
      (node (ref "IC118") (pin "8") (pinfunction "8_8") (pintype "passive"))
      (node (ref "IC119") (pin "8") (pinfunction "8_8") (pintype "passive"))
      (node (ref "IC120") (pin "8") (pinfunction "8_8") (pintype "passive"))
      (node (ref "IC121") (pin "8") (pinfunction "8_8") (pintype "passive"))
    )
    (net (code "705") (name "Net-(IC118-Pad9)") (class "Default")
      (node (ref "IC118") (pin "9") (pinfunction "9_9") (pintype "passive"))
      (node (ref "IC119") (pin "9") (pinfunction "9_9") (pintype "passive"))
      (node (ref "IC120") (pin "9") (pinfunction "9_9") (pintype "passive"))
      (node (ref "IC121") (pin "9") (pinfunction "9_9") (pintype "passive"))
    )
    (net (code "706") (name "Net-(IC118-Pad10)") (class "Default")
      (node (ref "IC118") (pin "10") (pinfunction "10_10") (pintype "passive"))
      (node (ref "IC119") (pin "10") (pinfunction "10_10") (pintype "passive"))
      (node (ref "IC120") (pin "10") (pinfunction "10_10") (pintype "passive"))
      (node (ref "IC121") (pin "10") (pinfunction "10_10") (pintype "passive"))
    )
    (net (code "707") (name "Net-(IC118-Pad11)") (class "Default")
      (node (ref "IC118") (pin "11") (pinfunction "11_11") (pintype "passive"))
      (node (ref "IC119") (pin "11") (pinfunction "11_11") (pintype "passive"))
      (node (ref "IC120") (pin "11") (pinfunction "11_11") (pintype "passive"))
      (node (ref "IC121") (pin "11") (pinfunction "11_11") (pintype "passive"))
    )
    (net (code "708") (name "Net-(IC118-Pad12)") (class "Default")
      (node (ref "IC118") (pin "12") (pinfunction "12_12") (pintype "passive"))
      (node (ref "IC119") (pin "12") (pinfunction "12_12") (pintype "passive"))
      (node (ref "IC120") (pin "12") (pinfunction "12_12") (pintype "passive"))
      (node (ref "IC121") (pin "12") (pinfunction "12_12") (pintype "passive"))
    )
    (net (code "709") (name "Net-(IC118-Pad13)") (class "Default")
      (node (ref "IC118") (pin "13") (pinfunction "13_13") (pintype "passive"))
      (node (ref "IC119") (pin "13") (pinfunction "13_13") (pintype "passive"))
      (node (ref "IC120") (pin "13") (pinfunction "13_13") (pintype "passive"))
      (node (ref "IC121") (pin "13") (pinfunction "13_13") (pintype "passive"))
    )
    (net (code "710") (name "Net-(IC118-Pad14)") (class "Default")
      (node (ref "IC118") (pin "14") (pinfunction "14_14") (pintype "passive"))
      (node (ref "IC119") (pin "14") (pinfunction "14_14") (pintype "passive"))
      (node (ref "IC120") (pin "14") (pinfunction "14_14") (pintype "passive"))
      (node (ref "IC121") (pin "14") (pinfunction "14_14") (pintype "passive"))
    )
    (net (code "711") (name "Net-(IC118-Pad15)") (class "Default")
      (node (ref "IC118") (pin "15") (pinfunction "15_15") (pintype "passive"))
      (node (ref "IC119") (pin "15") (pinfunction "15_15") (pintype "passive"))
      (node (ref "IC120") (pin "15") (pinfunction "15_15") (pintype "passive"))
      (node (ref "IC121") (pin "15") (pinfunction "15_15") (pintype "passive"))
    )
    (net (code "712") (name "Net-(IC118-Pad16)") (class "Default")
      (node (ref "IC118") (pin "16") (pinfunction "16_16") (pintype "passive"))
      (node (ref "IC119") (pin "16") (pinfunction "16_16") (pintype "passive"))
      (node (ref "IC120") (pin "16") (pinfunction "16_16") (pintype "passive"))
      (node (ref "IC121") (pin "16") (pinfunction "16_16") (pintype "passive"))
    )
    (net (code "713") (name "Net-(IC118-Pad17)") (class "Default")
      (node (ref "IC118") (pin "17") (pinfunction "17_17") (pintype "passive"))
      (node (ref "IC119") (pin "17") (pinfunction "17_17") (pintype "passive"))
      (node (ref "IC120") (pin "17") (pinfunction "17_17") (pintype "passive"))
      (node (ref "IC121") (pin "17") (pinfunction "17_17") (pintype "passive"))
    )
    (net (code "714") (name "Net-(IC118-Pad18)") (class "Default")
      (node (ref "IC118") (pin "18") (pinfunction "18_18") (pintype "passive"))
      (node (ref "IC119") (pin "18") (pinfunction "18_18") (pintype "passive"))
      (node (ref "IC120") (pin "18") (pinfunction "18_18") (pintype "passive"))
      (node (ref "IC121") (pin "18") (pinfunction "18_18") (pintype "passive"))
    )
    (net (code "715") (name "Net-(IC118-Pad19)") (class "Default")
      (node (ref "IC118") (pin "19") (pinfunction "19_19") (pintype "passive"))
      (node (ref "IC119") (pin "19") (pinfunction "19_19") (pintype "passive"))
      (node (ref "IC120") (pin "19") (pinfunction "19_19") (pintype "passive"))
      (node (ref "IC121") (pin "19") (pinfunction "19_19") (pintype "passive"))
    )
    (net (code "716") (name "Net-(IC118-Pad20)") (class "Default")
      (node (ref "IC118") (pin "20") (pinfunction "20_20") (pintype "passive"))
      (node (ref "IC119") (pin "20") (pinfunction "20_20") (pintype "passive"))
      (node (ref "IC120") (pin "20") (pinfunction "20_20") (pintype "passive"))
      (node (ref "IC121") (pin "20") (pinfunction "20_20") (pintype "passive"))
    )
    (net (code "717") (name "Net-(IC118-Pad21)") (class "Default")
      (node (ref "IC118") (pin "21") (pinfunction "21_21") (pintype "passive"))
      (node (ref "IC119") (pin "21") (pinfunction "21_21") (pintype "passive"))
      (node (ref "IC120") (pin "21") (pinfunction "21_21") (pintype "passive"))
      (node (ref "IC121") (pin "21") (pinfunction "21_21") (pintype "passive"))
    )
    (net (code "718") (name "Net-(IC118-Pad22)") (class "Default")
      (node (ref "IC118") (pin "22") (pinfunction "22_22") (pintype "passive"))
      (node (ref "IC119") (pin "22") (pinfunction "22_22") (pintype "passive"))
      (node (ref "IC120") (pin "22") (pinfunction "22_22") (pintype "passive"))
      (node (ref "IC121") (pin "22") (pinfunction "22_22") (pintype "passive"))
    )
    (net (code "719") (name "Net-(IC118-Pad23)") (class "Default")
      (node (ref "IC118") (pin "23") (pinfunction "23_23") (pintype "passive"))
      (node (ref "IC119") (pin "23") (pinfunction "23_23") (pintype "passive"))
      (node (ref "IC120") (pin "23") (pinfunction "23_23") (pintype "passive"))
      (node (ref "IC121") (pin "23") (pinfunction "23_23") (pintype "passive"))
    )
    (net (code "720") (name "Net-(IC118-Pad24)") (class "Default")
      (node (ref "IC118") (pin "24") (pinfunction "24_24") (pintype "passive"))
      (node (ref "IC119") (pin "24") (pinfunction "24_24") (pintype "passive"))
      (node (ref "IC120") (pin "24") (pinfunction "24_24") (pintype "passive"))
      (node (ref "IC121") (pin "24") (pinfunction "24_24") (pintype "passive"))
    )
    (net (code "721") (name "Net-(IC122-Pad1)") (class "Default")
      (node (ref "IC122") (pin "1") (pinfunction "1_1") (pintype "passive"))
      (node (ref "IC123") (pin "1") (pinfunction "1_1") (pintype "passive"))
      (node (ref "IC124") (pin "1") (pinfunction "1_1") (pintype "passive"))
      (node (ref "IC125") (pin "1") (pinfunction "1_1") (pintype "passive"))
    )
    (net (code "722") (name "Net-(IC122-Pad2)") (class "Default")
      (node (ref "IC122") (pin "2") (pinfunction "2_2") (pintype "passive"))
      (node (ref "IC123") (pin "2") (pinfunction "2_2") (pintype "passive"))
      (node (ref "IC124") (pin "2") (pinfunction "2_2") (pintype "passive"))
      (node (ref "IC125") (pin "2") (pinfunction "2_2") (pintype "passive"))
    )
    (net (code "723") (name "Net-(IC122-Pad3)") (class "Default")
      (node (ref "IC122") (pin "3") (pinfunction "3_3") (pintype "passive"))
      (node (ref "IC123") (pin "3") (pinfunction "3_3") (pintype "passive"))
      (node (ref "IC124") (pin "3") (pinfunction "3_3") (pintype "passive"))
      (node (ref "IC125") (pin "3") (pinfunction "3_3") (pintype "passive"))
    )
    (net (code "724") (name "Net-(IC122-Pad4)") (class "Default")
      (node (ref "IC122") (pin "4") (pinfunction "4_4") (pintype "passive"))
      (node (ref "IC123") (pin "4") (pinfunction "4_4") (pintype "passive"))
      (node (ref "IC124") (pin "4") (pinfunction "4_4") (pintype "passive"))
      (node (ref "IC125") (pin "4") (pinfunction "4_4") (pintype "passive"))
    )
    (net (code "725") (name "Net-(IC122-Pad5)") (class "Default")
      (node (ref "IC122") (pin "5") (pinfunction "5_5") (pintype "passive"))
      (node (ref "IC123") (pin "5") (pinfunction "5_5") (pintype "passive"))
      (node (ref "IC124") (pin "5") (pinfunction "5_5") (pintype "passive"))
      (node (ref "IC125") (pin "5") (pinfunction "5_5") (pintype "passive"))
    )
    (net (code "726") (name "Net-(IC122-Pad6)") (class "Default")
      (node (ref "IC122") (pin "6") (pinfunction "6_6") (pintype "passive"))
      (node (ref "IC123") (pin "6") (pinfunction "6_6") (pintype "passive"))
      (node (ref "IC124") (pin "6") (pinfunction "6_6") (pintype "passive"))
      (node (ref "IC125") (pin "6") (pinfunction "6_6") (pintype "passive"))
    )
    (net (code "727") (name "Net-(IC122-Pad7)") (class "Default")
      (node (ref "IC122") (pin "7") (pinfunction "7_7") (pintype "passive"))
      (node (ref "IC123") (pin "7") (pinfunction "7_7") (pintype "passive"))
      (node (ref "IC124") (pin "7") (pinfunction "7_7") (pintype "passive"))
      (node (ref "IC125") (pin "7") (pinfunction "7_7") (pintype "passive"))
    )
    (net (code "728") (name "Net-(IC122-Pad8)") (class "Default")
      (node (ref "IC122") (pin "8") (pinfunction "8_8") (pintype "passive"))
      (node (ref "IC123") (pin "8") (pinfunction "8_8") (pintype "passive"))
      (node (ref "IC124") (pin "8") (pinfunction "8_8") (pintype "passive"))
      (node (ref "IC125") (pin "8") (pinfunction "8_8") (pintype "passive"))
    )
    (net (code "729") (name "Net-(IC122-Pad9)") (class "Default")
      (node (ref "IC122") (pin "9") (pinfunction "9_9") (pintype "passive"))
      (node (ref "IC123") (pin "9") (pinfunction "9_9") (pintype "passive"))
      (node (ref "IC124") (pin "9") (pinfunction "9_9") (pintype "passive"))
      (node (ref "IC125") (pin "9") (pinfunction "9_9") (pintype "passive"))
    )
    (net (code "730") (name "Net-(IC122-Pad10)") (class "Default")
      (node (ref "IC122") (pin "10") (pinfunction "10_10") (pintype "passive"))
      (node (ref "IC123") (pin "10") (pinfunction "10_10") (pintype "passive"))
      (node (ref "IC124") (pin "10") (pinfunction "10_10") (pintype "passive"))
      (node (ref "IC125") (pin "10") (pinfunction "10_10") (pintype "passive"))
    )
    (net (code "731") (name "Net-(IC122-Pad11)") (class "Default")
      (node (ref "IC122") (pin "11") (pinfunction "11_11") (pintype "passive"))
      (node (ref "IC123") (pin "11") (pinfunction "11_11") (pintype "passive"))
      (node (ref "IC124") (pin "11") (pinfunction "11_11") (pintype "passive"))
      (node (ref "IC125") (pin "11") (pinfunction "11_11") (pintype "passive"))
    )
    (net (code "732") (name "Net-(IC122-Pad12)") (class "Default")
      (node (ref "IC122") (pin "12") (pinfunction "12_12") (pintype "passive"))
      (node (ref "IC123") (pin "12") (pinfunction "12_12") (pintype "passive"))
      (node (ref "IC124") (pin "12") (pinfunction "12_12") (pintype "passive"))
      (node (ref "IC125") (pin "12") (pinfunction "12_12") (pintype "passive"))
    )
    (net (code "733") (name "Net-(IC122-Pad13)") (class "Default")
      (node (ref "IC122") (pin "13") (pinfunction "13_13") (pintype "passive"))
      (node (ref "IC123") (pin "13") (pinfunction "13_13") (pintype "passive"))
      (node (ref "IC124") (pin "13") (pinfunction "13_13") (pintype "passive"))
      (node (ref "IC125") (pin "13") (pinfunction "13_13") (pintype "passive"))
    )
    (net (code "734") (name "Net-(IC122-Pad14)") (class "Default")
      (node (ref "IC122") (pin "14") (pinfunction "14_14") (pintype "passive"))
      (node (ref "IC123") (pin "14") (pinfunction "14_14") (pintype "passive"))
      (node (ref "IC124") (pin "14") (pinfunction "14_14") (pintype "passive"))
      (node (ref "IC125") (pin "14") (pinfunction "14_14") (pintype "passive"))
    )
    (net (code "735") (name "Net-(IC122-Pad15)") (class "Default")
      (node (ref "IC122") (pin "15") (pinfunction "15_15") (pintype "passive"))
      (node (ref "IC123") (pin "15") (pinfunction "15_15") (pintype "passive"))
      (node (ref "IC124") (pin "15") (pinfunction "15_15") (pintype "passive"))
      (node (ref "IC125") (pin "15") (pinfunction "15_15") (pintype "passive"))
    )
    (net (code "736") (name "Net-(IC122-Pad16)") (class "Default")
      (node (ref "IC122") (pin "16") (pinfunction "16_16") (pintype "passive"))
      (node (ref "IC123") (pin "16") (pinfunction "16_16") (pintype "passive"))
      (node (ref "IC124") (pin "16") (pinfunction "16_16") (pintype "passive"))
      (node (ref "IC125") (pin "16") (pinfunction "16_16") (pintype "passive"))
    )
    (net (code "737") (name "Net-(IC122-Pad17)") (class "Default")
      (node (ref "IC122") (pin "17") (pinfunction "17_17") (pintype "passive"))
      (node (ref "IC123") (pin "17") (pinfunction "17_17") (pintype "passive"))
      (node (ref "IC124") (pin "17") (pinfunction "17_17") (pintype "passive"))
      (node (ref "IC125") (pin "17") (pinfunction "17_17") (pintype "passive"))
    )
    (net (code "738") (name "Net-(IC122-Pad18)") (class "Default")
      (node (ref "IC122") (pin "18") (pinfunction "18_18") (pintype "passive"))
      (node (ref "IC123") (pin "18") (pinfunction "18_18") (pintype "passive"))
      (node (ref "IC124") (pin "18") (pinfunction "18_18") (pintype "passive"))
      (node (ref "IC125") (pin "18") (pinfunction "18_18") (pintype "passive"))
    )
    (net (code "739") (name "Net-(IC122-Pad19)") (class "Default")
      (node (ref "IC122") (pin "19") (pinfunction "19_19") (pintype "passive"))
      (node (ref "IC123") (pin "19") (pinfunction "19_19") (pintype "passive"))
      (node (ref "IC124") (pin "19") (pinfunction "19_19") (pintype "passive"))
      (node (ref "IC125") (pin "19") (pinfunction "19_19") (pintype "passive"))
    )
    (net (code "740") (name "Net-(IC122-Pad20)") (class "Default")
      (node (ref "IC122") (pin "20") (pinfunction "20_20") (pintype "passive"))
      (node (ref "IC123") (pin "20") (pinfunction "20_20") (pintype "passive"))
      (node (ref "IC124") (pin "20") (pinfunction "20_20") (pintype "passive"))
      (node (ref "IC125") (pin "20") (pinfunction "20_20") (pintype "passive"))
    )
    (net (code "741") (name "Net-(IC122-Pad21)") (class "Default")
      (node (ref "IC122") (pin "21") (pinfunction "21_21") (pintype "passive"))
      (node (ref "IC123") (pin "21") (pinfunction "21_21") (pintype "passive"))
      (node (ref "IC124") (pin "21") (pinfunction "21_21") (pintype "passive"))
      (node (ref "IC125") (pin "21") (pinfunction "21_21") (pintype "passive"))
    )
    (net (code "742") (name "Net-(IC122-Pad22)") (class "Default")
      (node (ref "IC122") (pin "22") (pinfunction "22_22") (pintype "passive"))
      (node (ref "IC123") (pin "22") (pinfunction "22_22") (pintype "passive"))
      (node (ref "IC124") (pin "22") (pinfunction "22_22") (pintype "passive"))
      (node (ref "IC125") (pin "22") (pinfunction "22_22") (pintype "passive"))
    )
    (net (code "743") (name "Net-(IC122-Pad23)") (class "Default")
      (node (ref "IC122") (pin "23") (pinfunction "23_23") (pintype "passive"))
      (node (ref "IC123") (pin "23") (pinfunction "23_23") (pintype "passive"))
      (node (ref "IC124") (pin "23") (pinfunction "23_23") (pintype "passive"))
      (node (ref "IC125") (pin "23") (pinfunction "23_23") (pintype "passive"))
    )
    (net (code "744") (name "Net-(IC122-Pad24)") (class "Default")
      (node (ref "IC122") (pin "24") (pinfunction "24_24") (pintype "passive"))
      (node (ref "IC123") (pin "24") (pinfunction "24_24") (pintype "passive"))
      (node (ref "IC124") (pin "24") (pinfunction "24_24") (pintype "passive"))
      (node (ref "IC125") (pin "24") (pinfunction "24_24") (pintype "passive"))
    )
    (net (code "745") (name "Net-(IC126-Pad1)") (class "Default")
      (node (ref "IC126") (pin "1") (pinfunction "1_1") (pintype "passive"))
      (node (ref "IC127") (pin "1") (pinfunction "1_1") (pintype "passive"))
      (node (ref "IC128") (pin "1") (pinfunction "1_1") (pintype "passive"))
      (node (ref "IC129") (pin "1") (pinfunction "1_1") (pintype "passive"))
    )
    (net (code "746") (name "Net-(IC126-Pad2)") (class "Default")
      (node (ref "IC126") (pin "2") (pinfunction "2_2") (pintype "passive"))
      (node (ref "IC127") (pin "2") (pinfunction "2_2") (pintype "passive"))
      (node (ref "IC128") (pin "2") (pinfunction "2_2") (pintype "passive"))
      (node (ref "IC129") (pin "2") (pinfunction "2_2") (pintype "passive"))
    )
    (net (code "747") (name "Net-(IC126-Pad3)") (class "Default")
      (node (ref "IC126") (pin "3") (pinfunction "3_3") (pintype "passive"))
      (node (ref "IC127") (pin "3") (pinfunction "3_3") (pintype "passive"))
      (node (ref "IC128") (pin "3") (pinfunction "3_3") (pintype "passive"))
      (node (ref "IC129") (pin "3") (pinfunction "3_3") (pintype "passive"))
    )
    (net (code "748") (name "Net-(IC126-Pad4)") (class "Default")
      (node (ref "IC126") (pin "4") (pinfunction "4_4") (pintype "passive"))
      (node (ref "IC127") (pin "4") (pinfunction "4_4") (pintype "passive"))
      (node (ref "IC128") (pin "4") (pinfunction "4_4") (pintype "passive"))
      (node (ref "IC129") (pin "4") (pinfunction "4_4") (pintype "passive"))
    )
    (net (code "749") (name "Net-(IC126-Pad5)") (class "Default")
      (node (ref "IC126") (pin "5") (pinfunction "5_5") (pintype "passive"))
      (node (ref "IC127") (pin "5") (pinfunction "5_5") (pintype "passive"))
      (node (ref "IC128") (pin "5") (pinfunction "5_5") (pintype "passive"))
      (node (ref "IC129") (pin "5") (pinfunction "5_5") (pintype "passive"))
    )
    (net (code "750") (name "Net-(IC126-Pad6)") (class "Default")
      (node (ref "IC126") (pin "6") (pinfunction "6_6") (pintype "passive"))
      (node (ref "IC127") (pin "6") (pinfunction "6_6") (pintype "passive"))
      (node (ref "IC128") (pin "6") (pinfunction "6_6") (pintype "passive"))
      (node (ref "IC129") (pin "6") (pinfunction "6_6") (pintype "passive"))
    )
    (net (code "751") (name "Net-(IC126-Pad7)") (class "Default")
      (node (ref "IC126") (pin "7") (pinfunction "7_7") (pintype "passive"))
      (node (ref "IC127") (pin "7") (pinfunction "7_7") (pintype "passive"))
      (node (ref "IC128") (pin "7") (pinfunction "7_7") (pintype "passive"))
      (node (ref "IC129") (pin "7") (pinfunction "7_7") (pintype "passive"))
    )
    (net (code "752") (name "Net-(IC126-Pad8)") (class "Default")
      (node (ref "IC126") (pin "8") (pinfunction "8_8") (pintype "passive"))
      (node (ref "IC127") (pin "8") (pinfunction "8_8") (pintype "passive"))
      (node (ref "IC128") (pin "8") (pinfunction "8_8") (pintype "passive"))
      (node (ref "IC129") (pin "8") (pinfunction "8_8") (pintype "passive"))
    )
    (net (code "753") (name "Net-(IC126-Pad9)") (class "Default")
      (node (ref "IC126") (pin "9") (pinfunction "9_9") (pintype "passive"))
      (node (ref "IC127") (pin "9") (pinfunction "9_9") (pintype "passive"))
      (node (ref "IC128") (pin "9") (pinfunction "9_9") (pintype "passive"))
      (node (ref "IC129") (pin "9") (pinfunction "9_9") (pintype "passive"))
    )
    (net (code "754") (name "Net-(IC126-Pad10)") (class "Default")
      (node (ref "IC126") (pin "10") (pinfunction "10_10") (pintype "passive"))
      (node (ref "IC127") (pin "10") (pinfunction "10_10") (pintype "passive"))
      (node (ref "IC128") (pin "10") (pinfunction "10_10") (pintype "passive"))
      (node (ref "IC129") (pin "10") (pinfunction "10_10") (pintype "passive"))
    )
    (net (code "755") (name "Net-(IC126-Pad11)") (class "Default")
      (node (ref "IC126") (pin "11") (pinfunction "11_11") (pintype "passive"))
      (node (ref "IC127") (pin "11") (pinfunction "11_11") (pintype "passive"))
      (node (ref "IC128") (pin "11") (pinfunction "11_11") (pintype "passive"))
      (node (ref "IC129") (pin "11") (pinfunction "11_11") (pintype "passive"))
    )
    (net (code "756") (name "Net-(IC126-Pad12)") (class "Default")
      (node (ref "IC126") (pin "12") (pinfunction "12_12") (pintype "passive"))
      (node (ref "IC127") (pin "12") (pinfunction "12_12") (pintype "passive"))
      (node (ref "IC128") (pin "12") (pinfunction "12_12") (pintype "passive"))
      (node (ref "IC129") (pin "12") (pinfunction "12_12") (pintype "passive"))
    )
    (net (code "757") (name "Net-(IC126-Pad13)") (class "Default")
      (node (ref "IC126") (pin "13") (pinfunction "13_13") (pintype "passive"))
      (node (ref "IC127") (pin "13") (pinfunction "13_13") (pintype "passive"))
      (node (ref "IC128") (pin "13") (pinfunction "13_13") (pintype "passive"))
      (node (ref "IC129") (pin "13") (pinfunction "13_13") (pintype "passive"))
    )
    (net (code "758") (name "Net-(IC126-Pad14)") (class "Default")
      (node (ref "IC126") (pin "14") (pinfunction "14_14") (pintype "passive"))
      (node (ref "IC127") (pin "14") (pinfunction "14_14") (pintype "passive"))
      (node (ref "IC128") (pin "14") (pinfunction "14_14") (pintype "passive"))
      (node (ref "IC129") (pin "14") (pinfunction "14_14") (pintype "passive"))
    )
    (net (code "759") (name "Net-(IC126-Pad15)") (class "Default")
      (node (ref "IC126") (pin "15") (pinfunction "15_15") (pintype "passive"))
      (node (ref "IC127") (pin "15") (pinfunction "15_15") (pintype "passive"))
      (node (ref "IC128") (pin "15") (pinfunction "15_15") (pintype "passive"))
      (node (ref "IC129") (pin "15") (pinfunction "15_15") (pintype "passive"))
    )
    (net (code "760") (name "Net-(IC126-Pad16)") (class "Default")
      (node (ref "IC126") (pin "16") (pinfunction "16_16") (pintype "passive"))
      (node (ref "IC127") (pin "16") (pinfunction "16_16") (pintype "passive"))
      (node (ref "IC128") (pin "16") (pinfunction "16_16") (pintype "passive"))
      (node (ref "IC129") (pin "16") (pinfunction "16_16") (pintype "passive"))
    )
    (net (code "761") (name "Net-(IC126-Pad17)") (class "Default")
      (node (ref "IC126") (pin "17") (pinfunction "17_17") (pintype "passive"))
      (node (ref "IC127") (pin "17") (pinfunction "17_17") (pintype "passive"))
      (node (ref "IC128") (pin "17") (pinfunction "17_17") (pintype "passive"))
      (node (ref "IC129") (pin "17") (pinfunction "17_17") (pintype "passive"))
    )
    (net (code "762") (name "Net-(IC126-Pad18)") (class "Default")
      (node (ref "IC126") (pin "18") (pinfunction "18_18") (pintype "passive"))
      (node (ref "IC127") (pin "18") (pinfunction "18_18") (pintype "passive"))
      (node (ref "IC128") (pin "18") (pinfunction "18_18") (pintype "passive"))
      (node (ref "IC129") (pin "18") (pinfunction "18_18") (pintype "passive"))
    )
    (net (code "763") (name "Net-(IC126-Pad19)") (class "Default")
      (node (ref "IC126") (pin "19") (pinfunction "19_19") (pintype "passive"))
      (node (ref "IC127") (pin "19") (pinfunction "19_19") (pintype "passive"))
      (node (ref "IC128") (pin "19") (pinfunction "19_19") (pintype "passive"))
      (node (ref "IC129") (pin "19") (pinfunction "19_19") (pintype "passive"))
    )
    (net (code "764") (name "Net-(IC126-Pad20)") (class "Default")
      (node (ref "IC126") (pin "20") (pinfunction "20_20") (pintype "passive"))
      (node (ref "IC127") (pin "20") (pinfunction "20_20") (pintype "passive"))
      (node (ref "IC128") (pin "20") (pinfunction "20_20") (pintype "passive"))
      (node (ref "IC129") (pin "20") (pinfunction "20_20") (pintype "passive"))
    )
    (net (code "765") (name "Net-(IC126-Pad21)") (class "Default")
      (node (ref "IC126") (pin "21") (pinfunction "21_21") (pintype "passive"))
      (node (ref "IC127") (pin "21") (pinfunction "21_21") (pintype "passive"))
      (node (ref "IC128") (pin "21") (pinfunction "21_21") (pintype "passive"))
      (node (ref "IC129") (pin "21") (pinfunction "21_21") (pintype "passive"))
    )
    (net (code "766") (name "Net-(IC126-Pad22)") (class "Default")
      (node (ref "IC126") (pin "22") (pinfunction "22_22") (pintype "passive"))
      (node (ref "IC127") (pin "22") (pinfunction "22_22") (pintype "passive"))
      (node (ref "IC128") (pin "22") (pinfunction "22_22") (pintype "passive"))
      (node (ref "IC129") (pin "22") (pinfunction "22_22") (pintype "passive"))
    )
    (net (code "767") (name "Net-(IC126-Pad23)") (class "Default")
      (node (ref "IC126") (pin "23") (pinfunction "23_23") (pintype "passive"))
      (node (ref "IC127") (pin "23") (pinfunction "23_23") (pintype "passive"))
      (node (ref "IC128") (pin "23") (pinfunction "23_23") (pintype "passive"))
      (node (ref "IC129") (pin "23") (pinfunction "23_23") (pintype "passive"))
    )
    (net (code "768") (name "Net-(IC126-Pad24)") (class "Default")
      (node (ref "IC126") (pin "24") (pinfunction "24_24") (pintype "passive"))
      (node (ref "IC127") (pin "24") (pinfunction "24_24") (pintype "passive"))
      (node (ref "IC128") (pin "24") (pinfunction "24_24") (pintype "passive"))
      (node (ref "IC129") (pin "24") (pinfunction "24_24") (pintype "passive"))
    )
    (net (code "769") (name "Net-(IC130-Pad1)") (class "Default")
      (node (ref "IC130") (pin "1") (pinfunction "1_1") (pintype "passive"))
      (node (ref "IC131") (pin "1") (pinfunction "1_1") (pintype "passive"))
      (node (ref "IC132") (pin "1") (pinfunction "1_1") (pintype "passive"))
      (node (ref "IC133") (pin "1") (pinfunction "1_1") (pintype "passive"))
    )
    (net (code "770") (name "Net-(IC130-Pad2)") (class "Default")
      (node (ref "IC130") (pin "2") (pinfunction "2_2") (pintype "passive"))
      (node (ref "IC131") (pin "2") (pinfunction "2_2") (pintype "passive"))
      (node (ref "IC132") (pin "2") (pinfunction "2_2") (pintype "passive"))
      (node (ref "IC133") (pin "2") (pinfunction "2_2") (pintype "passive"))
    )
    (net (code "771") (name "Net-(IC130-Pad3)") (class "Default")
      (node (ref "IC130") (pin "3") (pinfunction "3_3") (pintype "passive"))
      (node (ref "IC131") (pin "3") (pinfunction "3_3") (pintype "passive"))
      (node (ref "IC132") (pin "3") (pinfunction "3_3") (pintype "passive"))
      (node (ref "IC133") (pin "3") (pinfunction "3_3") (pintype "passive"))
    )
    (net (code "772") (name "Net-(IC130-Pad4)") (class "Default")
      (node (ref "IC130") (pin "4") (pinfunction "4_4") (pintype "passive"))
      (node (ref "IC131") (pin "4") (pinfunction "4_4") (pintype "passive"))
      (node (ref "IC132") (pin "4") (pinfunction "4_4") (pintype "passive"))
      (node (ref "IC133") (pin "4") (pinfunction "4_4") (pintype "passive"))
    )
    (net (code "773") (name "Net-(IC130-Pad5)") (class "Default")
      (node (ref "IC130") (pin "5") (pinfunction "5_5") (pintype "passive"))
      (node (ref "IC131") (pin "5") (pinfunction "5_5") (pintype "passive"))
      (node (ref "IC132") (pin "5") (pinfunction "5_5") (pintype "passive"))
      (node (ref "IC133") (pin "5") (pinfunction "5_5") (pintype "passive"))
    )
    (net (code "774") (name "Net-(IC130-Pad6)") (class "Default")
      (node (ref "IC130") (pin "6") (pinfunction "6_6") (pintype "passive"))
      (node (ref "IC131") (pin "6") (pinfunction "6_6") (pintype "passive"))
      (node (ref "IC132") (pin "6") (pinfunction "6_6") (pintype "passive"))
      (node (ref "IC133") (pin "6") (pinfunction "6_6") (pintype "passive"))
    )
    (net (code "775") (name "Net-(IC130-Pad7)") (class "Default")
      (node (ref "IC130") (pin "7") (pinfunction "7_7") (pintype "passive"))
      (node (ref "IC131") (pin "7") (pinfunction "7_7") (pintype "passive"))
      (node (ref "IC132") (pin "7") (pinfunction "7_7") (pintype "passive"))
      (node (ref "IC133") (pin "7") (pinfunction "7_7") (pintype "passive"))
    )
    (net (code "776") (name "Net-(IC130-Pad8)") (class "Default")
      (node (ref "IC130") (pin "8") (pinfunction "8_8") (pintype "passive"))
      (node (ref "IC131") (pin "8") (pinfunction "8_8") (pintype "passive"))
      (node (ref "IC132") (pin "8") (pinfunction "8_8") (pintype "passive"))
      (node (ref "IC133") (pin "8") (pinfunction "8_8") (pintype "passive"))
    )
    (net (code "777") (name "Net-(IC130-Pad9)") (class "Default")
      (node (ref "IC130") (pin "9") (pinfunction "9_9") (pintype "passive"))
      (node (ref "IC131") (pin "9") (pinfunction "9_9") (pintype "passive"))
      (node (ref "IC132") (pin "9") (pinfunction "9_9") (pintype "passive"))
      (node (ref "IC133") (pin "9") (pinfunction "9_9") (pintype "passive"))
    )
    (net (code "778") (name "Net-(IC130-Pad10)") (class "Default")
      (node (ref "IC130") (pin "10") (pinfunction "10_10") (pintype "passive"))
      (node (ref "IC131") (pin "10") (pinfunction "10_10") (pintype "passive"))
      (node (ref "IC132") (pin "10") (pinfunction "10_10") (pintype "passive"))
      (node (ref "IC133") (pin "10") (pinfunction "10_10") (pintype "passive"))
    )
    (net (code "779") (name "Net-(IC130-Pad11)") (class "Default")
      (node (ref "IC130") (pin "11") (pinfunction "11_11") (pintype "passive"))
      (node (ref "IC131") (pin "11") (pinfunction "11_11") (pintype "passive"))
      (node (ref "IC132") (pin "11") (pinfunction "11_11") (pintype "passive"))
      (node (ref "IC133") (pin "11") (pinfunction "11_11") (pintype "passive"))
    )
    (net (code "780") (name "Net-(IC130-Pad12)") (class "Default")
      (node (ref "IC130") (pin "12") (pinfunction "12_12") (pintype "passive"))
      (node (ref "IC131") (pin "12") (pinfunction "12_12") (pintype "passive"))
      (node (ref "IC132") (pin "12") (pinfunction "12_12") (pintype "passive"))
      (node (ref "IC133") (pin "12") (pinfunction "12_12") (pintype "passive"))
    )
    (net (code "781") (name "Net-(IC130-Pad13)") (class "Default")
      (node (ref "IC130") (pin "13") (pinfunction "13_13") (pintype "passive"))
      (node (ref "IC131") (pin "13") (pinfunction "13_13") (pintype "passive"))
      (node (ref "IC132") (pin "13") (pinfunction "13_13") (pintype "passive"))
      (node (ref "IC133") (pin "13") (pinfunction "13_13") (pintype "passive"))
    )
    (net (code "782") (name "Net-(IC130-Pad14)") (class "Default")
      (node (ref "IC130") (pin "14") (pinfunction "14_14") (pintype "passive"))
      (node (ref "IC131") (pin "14") (pinfunction "14_14") (pintype "passive"))
      (node (ref "IC132") (pin "14") (pinfunction "14_14") (pintype "passive"))
      (node (ref "IC133") (pin "14") (pinfunction "14_14") (pintype "passive"))
    )
    (net (code "783") (name "Net-(IC130-Pad15)") (class "Default")
      (node (ref "IC130") (pin "15") (pinfunction "15_15") (pintype "passive"))
      (node (ref "IC131") (pin "15") (pinfunction "15_15") (pintype "passive"))
      (node (ref "IC132") (pin "15") (pinfunction "15_15") (pintype "passive"))
      (node (ref "IC133") (pin "15") (pinfunction "15_15") (pintype "passive"))
    )
    (net (code "784") (name "Net-(IC130-Pad16)") (class "Default")
      (node (ref "IC130") (pin "16") (pinfunction "16_16") (pintype "passive"))
      (node (ref "IC131") (pin "16") (pinfunction "16_16") (pintype "passive"))
      (node (ref "IC132") (pin "16") (pinfunction "16_16") (pintype "passive"))
      (node (ref "IC133") (pin "16") (pinfunction "16_16") (pintype "passive"))
    )
    (net (code "785") (name "Net-(IC130-Pad17)") (class "Default")
      (node (ref "IC130") (pin "17") (pinfunction "17_17") (pintype "passive"))
      (node (ref "IC131") (pin "17") (pinfunction "17_17") (pintype "passive"))
      (node (ref "IC132") (pin "17") (pinfunction "17_17") (pintype "passive"))
      (node (ref "IC133") (pin "17") (pinfunction "17_17") (pintype "passive"))
    )
    (net (code "786") (name "Net-(IC130-Pad18)") (class "Default")
      (node (ref "IC130") (pin "18") (pinfunction "18_18") (pintype "passive"))
      (node (ref "IC131") (pin "18") (pinfunction "18_18") (pintype "passive"))
      (node (ref "IC132") (pin "18") (pinfunction "18_18") (pintype "passive"))
      (node (ref "IC133") (pin "18") (pinfunction "18_18") (pintype "passive"))
    )
    (net (code "787") (name "Net-(IC130-Pad19)") (class "Default")
      (node (ref "IC130") (pin "19") (pinfunction "19_19") (pintype "passive"))
      (node (ref "IC131") (pin "19") (pinfunction "19_19") (pintype "passive"))
      (node (ref "IC132") (pin "19") (pinfunction "19_19") (pintype "passive"))
      (node (ref "IC133") (pin "19") (pinfunction "19_19") (pintype "passive"))
    )
    (net (code "788") (name "Net-(IC130-Pad20)") (class "Default")
      (node (ref "IC130") (pin "20") (pinfunction "20_20") (pintype "passive"))
      (node (ref "IC131") (pin "20") (pinfunction "20_20") (pintype "passive"))
      (node (ref "IC132") (pin "20") (pinfunction "20_20") (pintype "passive"))
      (node (ref "IC133") (pin "20") (pinfunction "20_20") (pintype "passive"))
    )
    (net (code "789") (name "Net-(IC130-Pad21)") (class "Default")
      (node (ref "IC130") (pin "21") (pinfunction "21_21") (pintype "passive"))
      (node (ref "IC131") (pin "21") (pinfunction "21_21") (pintype "passive"))
      (node (ref "IC132") (pin "21") (pinfunction "21_21") (pintype "passive"))
      (node (ref "IC133") (pin "21") (pinfunction "21_21") (pintype "passive"))
    )
    (net (code "790") (name "Net-(IC130-Pad22)") (class "Default")
      (node (ref "IC130") (pin "22") (pinfunction "22_22") (pintype "passive"))
      (node (ref "IC131") (pin "22") (pinfunction "22_22") (pintype "passive"))
      (node (ref "IC132") (pin "22") (pinfunction "22_22") (pintype "passive"))
      (node (ref "IC133") (pin "22") (pinfunction "22_22") (pintype "passive"))
    )
    (net (code "791") (name "Net-(IC130-Pad23)") (class "Default")
      (node (ref "IC130") (pin "23") (pinfunction "23_23") (pintype "passive"))
      (node (ref "IC131") (pin "23") (pinfunction "23_23") (pintype "passive"))
      (node (ref "IC132") (pin "23") (pinfunction "23_23") (pintype "passive"))
      (node (ref "IC133") (pin "23") (pinfunction "23_23") (pintype "passive"))
    )
    (net (code "792") (name "Net-(IC130-Pad24)") (class "Default")
      (node (ref "IC130") (pin "24") (pinfunction "24_24") (pintype "passive"))
      (node (ref "IC131") (pin "24") (pinfunction "24_24") (pintype "passive"))
      (node (ref "IC132") (pin "24") (pinfunction "24_24") (pintype "passive"))
      (node (ref "IC133") (pin "24") (pinfunction "24_24") (pintype "passive"))
    )
    (net (code "793") (name "Net-(IC134-Pad1)") (class "Default")
      (node (ref "IC134") (pin "1") (pinfunction "1_1") (pintype "passive"))
      (node (ref "IC135") (pin "1") (pinfunction "1_1") (pintype "passive"))
      (node (ref "IC136") (pin "1") (pinfunction "1_1") (pintype "passive"))
      (node (ref "IC137") (pin "1") (pinfunction "1_1") (pintype "passive"))
    )
    (net (code "794") (name "Net-(IC134-Pad2)") (class "Default")
      (node (ref "IC134") (pin "2") (pinfunction "2_2") (pintype "passive"))
      (node (ref "IC135") (pin "2") (pinfunction "2_2") (pintype "passive"))
      (node (ref "IC136") (pin "2") (pinfunction "2_2") (pintype "passive"))
      (node (ref "IC137") (pin "2") (pinfunction "2_2") (pintype "passive"))
    )
    (net (code "795") (name "Net-(IC134-Pad3)") (class "Default")
      (node (ref "IC134") (pin "3") (pinfunction "3_3") (pintype "passive"))
      (node (ref "IC135") (pin "3") (pinfunction "3_3") (pintype "passive"))
      (node (ref "IC136") (pin "3") (pinfunction "3_3") (pintype "passive"))
      (node (ref "IC137") (pin "3") (pinfunction "3_3") (pintype "passive"))
    )
    (net (code "796") (name "Net-(IC134-Pad4)") (class "Default")
      (node (ref "IC134") (pin "4") (pinfunction "4_4") (pintype "passive"))
      (node (ref "IC135") (pin "4") (pinfunction "4_4") (pintype "passive"))
      (node (ref "IC136") (pin "4") (pinfunction "4_4") (pintype "passive"))
      (node (ref "IC137") (pin "4") (pinfunction "4_4") (pintype "passive"))
    )
    (net (code "797") (name "Net-(IC134-Pad5)") (class "Default")
      (node (ref "IC134") (pin "5") (pinfunction "5_5") (pintype "passive"))
      (node (ref "IC135") (pin "5") (pinfunction "5_5") (pintype "passive"))
      (node (ref "IC136") (pin "5") (pinfunction "5_5") (pintype "passive"))
      (node (ref "IC137") (pin "5") (pinfunction "5_5") (pintype "passive"))
    )
    (net (code "798") (name "Net-(IC134-Pad6)") (class "Default")
      (node (ref "IC134") (pin "6") (pinfunction "6_6") (pintype "passive"))
      (node (ref "IC135") (pin "6") (pinfunction "6_6") (pintype "passive"))
      (node (ref "IC136") (pin "6") (pinfunction "6_6") (pintype "passive"))
      (node (ref "IC137") (pin "6") (pinfunction "6_6") (pintype "passive"))
    )
    (net (code "799") (name "Net-(IC134-Pad7)") (class "Default")
      (node (ref "IC134") (pin "7") (pinfunction "7_7") (pintype "passive"))
      (node (ref "IC135") (pin "7") (pinfunction "7_7") (pintype "passive"))
      (node (ref "IC136") (pin "7") (pinfunction "7_7") (pintype "passive"))
      (node (ref "IC137") (pin "7") (pinfunction "7_7") (pintype "passive"))
    )
    (net (code "800") (name "Net-(IC134-Pad8)") (class "Default")
      (node (ref "IC134") (pin "8") (pinfunction "8_8") (pintype "passive"))
      (node (ref "IC135") (pin "8") (pinfunction "8_8") (pintype "passive"))
      (node (ref "IC136") (pin "8") (pinfunction "8_8") (pintype "passive"))
      (node (ref "IC137") (pin "8") (pinfunction "8_8") (pintype "passive"))
    )
    (net (code "801") (name "Net-(IC134-Pad9)") (class "Default")
      (node (ref "IC134") (pin "9") (pinfunction "9_9") (pintype "passive"))
      (node (ref "IC135") (pin "9") (pinfunction "9_9") (pintype "passive"))
      (node (ref "IC136") (pin "9") (pinfunction "9_9") (pintype "passive"))
      (node (ref "IC137") (pin "9") (pinfunction "9_9") (pintype "passive"))
    )
    (net (code "802") (name "Net-(IC134-Pad10)") (class "Default")
      (node (ref "IC134") (pin "10") (pinfunction "10_10") (pintype "passive"))
      (node (ref "IC135") (pin "10") (pinfunction "10_10") (pintype "passive"))
      (node (ref "IC136") (pin "10") (pinfunction "10_10") (pintype "passive"))
      (node (ref "IC137") (pin "10") (pinfunction "10_10") (pintype "passive"))
    )
    (net (code "803") (name "Net-(IC134-Pad11)") (class "Default")
      (node (ref "IC134") (pin "11") (pinfunction "11_11") (pintype "passive"))
      (node (ref "IC135") (pin "11") (pinfunction "11_11") (pintype "passive"))
      (node (ref "IC136") (pin "11") (pinfunction "11_11") (pintype "passive"))
      (node (ref "IC137") (pin "11") (pinfunction "11_11") (pintype "passive"))
    )
    (net (code "804") (name "Net-(IC134-Pad12)") (class "Default")
      (node (ref "IC134") (pin "12") (pinfunction "12_12") (pintype "passive"))
      (node (ref "IC135") (pin "12") (pinfunction "12_12") (pintype "passive"))
      (node (ref "IC136") (pin "12") (pinfunction "12_12") (pintype "passive"))
      (node (ref "IC137") (pin "12") (pinfunction "12_12") (pintype "passive"))
    )
    (net (code "805") (name "Net-(IC134-Pad13)") (class "Default")
      (node (ref "IC134") (pin "13") (pinfunction "13_13") (pintype "passive"))
      (node (ref "IC135") (pin "13") (pinfunction "13_13") (pintype "passive"))
      (node (ref "IC136") (pin "13") (pinfunction "13_13") (pintype "passive"))
      (node (ref "IC137") (pin "13") (pinfunction "13_13") (pintype "passive"))
    )
    (net (code "806") (name "Net-(IC134-Pad14)") (class "Default")
      (node (ref "IC134") (pin "14") (pinfunction "14_14") (pintype "passive"))
      (node (ref "IC135") (pin "14") (pinfunction "14_14") (pintype "passive"))
      (node (ref "IC136") (pin "14") (pinfunction "14_14") (pintype "passive"))
      (node (ref "IC137") (pin "14") (pinfunction "14_14") (pintype "passive"))
    )
    (net (code "807") (name "Net-(IC134-Pad15)") (class "Default")
      (node (ref "IC134") (pin "15") (pinfunction "15_15") (pintype "passive"))
      (node (ref "IC135") (pin "15") (pinfunction "15_15") (pintype "passive"))
      (node (ref "IC136") (pin "15") (pinfunction "15_15") (pintype "passive"))
      (node (ref "IC137") (pin "15") (pinfunction "15_15") (pintype "passive"))
    )
    (net (code "808") (name "Net-(IC134-Pad16)") (class "Default")
      (node (ref "IC134") (pin "16") (pinfunction "16_16") (pintype "passive"))
      (node (ref "IC135") (pin "16") (pinfunction "16_16") (pintype "passive"))
      (node (ref "IC136") (pin "16") (pinfunction "16_16") (pintype "passive"))
      (node (ref "IC137") (pin "16") (pinfunction "16_16") (pintype "passive"))
    )
    (net (code "809") (name "Net-(IC134-Pad17)") (class "Default")
      (node (ref "IC134") (pin "17") (pinfunction "17_17") (pintype "passive"))
      (node (ref "IC135") (pin "17") (pinfunction "17_17") (pintype "passive"))
      (node (ref "IC136") (pin "17") (pinfunction "17_17") (pintype "passive"))
      (node (ref "IC137") (pin "17") (pinfunction "17_17") (pintype "passive"))
    )
    (net (code "810") (name "Net-(IC134-Pad18)") (class "Default")
      (node (ref "IC134") (pin "18") (pinfunction "18_18") (pintype "passive"))
      (node (ref "IC135") (pin "18") (pinfunction "18_18") (pintype "passive"))
      (node (ref "IC136") (pin "18") (pinfunction "18_18") (pintype "passive"))
      (node (ref "IC137") (pin "18") (pinfunction "18_18") (pintype "passive"))
    )
    (net (code "811") (name "Net-(IC134-Pad19)") (class "Default")
      (node (ref "IC134") (pin "19") (pinfunction "19_19") (pintype "passive"))
      (node (ref "IC135") (pin "19") (pinfunction "19_19") (pintype "passive"))
      (node (ref "IC136") (pin "19") (pinfunction "19_19") (pintype "passive"))
      (node (ref "IC137") (pin "19") (pinfunction "19_19") (pintype "passive"))
    )
    (net (code "812") (name "Net-(IC134-Pad20)") (class "Default")
      (node (ref "IC134") (pin "20") (pinfunction "20_20") (pintype "passive"))
      (node (ref "IC135") (pin "20") (pinfunction "20_20") (pintype "passive"))
      (node (ref "IC136") (pin "20") (pinfunction "20_20") (pintype "passive"))
      (node (ref "IC137") (pin "20") (pinfunction "20_20") (pintype "passive"))
    )
    (net (code "813") (name "Net-(IC134-Pad21)") (class "Default")
      (node (ref "IC134") (pin "21") (pinfunction "21_21") (pintype "passive"))
      (node (ref "IC135") (pin "21") (pinfunction "21_21") (pintype "passive"))
      (node (ref "IC136") (pin "21") (pinfunction "21_21") (pintype "passive"))
      (node (ref "IC137") (pin "21") (pinfunction "21_21") (pintype "passive"))
    )
    (net (code "814") (name "Net-(IC134-Pad22)") (class "Default")
      (node (ref "IC134") (pin "22") (pinfunction "22_22") (pintype "passive"))
      (node (ref "IC135") (pin "22") (pinfunction "22_22") (pintype "passive"))
      (node (ref "IC136") (pin "22") (pinfunction "22_22") (pintype "passive"))
      (node (ref "IC137") (pin "22") (pinfunction "22_22") (pintype "passive"))
    )
    (net (code "815") (name "Net-(IC134-Pad23)") (class "Default")
      (node (ref "IC134") (pin "23") (pinfunction "23_23") (pintype "passive"))
      (node (ref "IC135") (pin "23") (pinfunction "23_23") (pintype "passive"))
      (node (ref "IC136") (pin "23") (pinfunction "23_23") (pintype "passive"))
      (node (ref "IC137") (pin "23") (pinfunction "23_23") (pintype "passive"))
    )
    (net (code "816") (name "Net-(IC134-Pad24)") (class "Default")
      (node (ref "IC134") (pin "24") (pinfunction "24_24") (pintype "passive"))
      (node (ref "IC135") (pin "24") (pinfunction "24_24") (pintype "passive"))
      (node (ref "IC136") (pin "24") (pinfunction "24_24") (pintype "passive"))
      (node (ref "IC137") (pin "24") (pinfunction "24_24") (pintype "passive"))
    )
    (net (code "817") (name "Net-(IC138-Pad1)") (class "Default")
      (node (ref "IC138") (pin "1") (pinfunction "1_1") (pintype "passive"))
      (node (ref "IC139") (pin "1") (pinfunction "1_1") (pintype "passive"))
      (node (ref "IC140") (pin "1") (pinfunction "1_1") (pintype "passive"))
      (node (ref "IC141") (pin "1") (pinfunction "1_1") (pintype "passive"))
    )
    (net (code "818") (name "Net-(IC138-Pad2)") (class "Default")
      (node (ref "IC138") (pin "2") (pinfunction "2_2") (pintype "passive"))
      (node (ref "IC139") (pin "2") (pinfunction "2_2") (pintype "passive"))
      (node (ref "IC140") (pin "2") (pinfunction "2_2") (pintype "passive"))
      (node (ref "IC141") (pin "2") (pinfunction "2_2") (pintype "passive"))
    )
    (net (code "819") (name "Net-(IC138-Pad3)") (class "Default")
      (node (ref "IC138") (pin "3") (pinfunction "3_3") (pintype "passive"))
      (node (ref "IC139") (pin "3") (pinfunction "3_3") (pintype "passive"))
      (node (ref "IC140") (pin "3") (pinfunction "3_3") (pintype "passive"))
      (node (ref "IC141") (pin "3") (pinfunction "3_3") (pintype "passive"))
    )
    (net (code "820") (name "Net-(IC138-Pad4)") (class "Default")
      (node (ref "IC138") (pin "4") (pinfunction "4_4") (pintype "passive"))
      (node (ref "IC139") (pin "4") (pinfunction "4_4") (pintype "passive"))
      (node (ref "IC140") (pin "4") (pinfunction "4_4") (pintype "passive"))
      (node (ref "IC141") (pin "4") (pinfunction "4_4") (pintype "passive"))
    )
    (net (code "821") (name "Net-(IC138-Pad5)") (class "Default")
      (node (ref "IC138") (pin "5") (pinfunction "5_5") (pintype "passive"))
      (node (ref "IC139") (pin "5") (pinfunction "5_5") (pintype "passive"))
      (node (ref "IC140") (pin "5") (pinfunction "5_5") (pintype "passive"))
      (node (ref "IC141") (pin "5") (pinfunction "5_5") (pintype "passive"))
    )
    (net (code "822") (name "Net-(IC138-Pad6)") (class "Default")
      (node (ref "IC138") (pin "6") (pinfunction "6_6") (pintype "passive"))
      (node (ref "IC139") (pin "6") (pinfunction "6_6") (pintype "passive"))
      (node (ref "IC140") (pin "6") (pinfunction "6_6") (pintype "passive"))
      (node (ref "IC141") (pin "6") (pinfunction "6_6") (pintype "passive"))
    )
    (net (code "823") (name "Net-(IC138-Pad7)") (class "Default")
      (node (ref "IC138") (pin "7") (pinfunction "7_7") (pintype "passive"))
      (node (ref "IC139") (pin "7") (pinfunction "7_7") (pintype "passive"))
      (node (ref "IC140") (pin "7") (pinfunction "7_7") (pintype "passive"))
      (node (ref "IC141") (pin "7") (pinfunction "7_7") (pintype "passive"))
    )
    (net (code "824") (name "Net-(IC138-Pad8)") (class "Default")
      (node (ref "IC138") (pin "8") (pinfunction "8_8") (pintype "passive"))
      (node (ref "IC139") (pin "8") (pinfunction "8_8") (pintype "passive"))
      (node (ref "IC140") (pin "8") (pinfunction "8_8") (pintype "passive"))
      (node (ref "IC141") (pin "8") (pinfunction "8_8") (pintype "passive"))
    )
    (net (code "825") (name "Net-(IC138-Pad9)") (class "Default")
      (node (ref "IC138") (pin "9") (pinfunction "9_9") (pintype "passive"))
      (node (ref "IC139") (pin "9") (pinfunction "9_9") (pintype "passive"))
      (node (ref "IC140") (pin "9") (pinfunction "9_9") (pintype "passive"))
      (node (ref "IC141") (pin "9") (pinfunction "9_9") (pintype "passive"))
    )
    (net (code "826") (name "Net-(IC138-Pad10)") (class "Default")
      (node (ref "IC138") (pin "10") (pinfunction "10_10") (pintype "passive"))
      (node (ref "IC139") (pin "10") (pinfunction "10_10") (pintype "passive"))
      (node (ref "IC140") (pin "10") (pinfunction "10_10") (pintype "passive"))
      (node (ref "IC141") (pin "10") (pinfunction "10_10") (pintype "passive"))
    )
    (net (code "827") (name "Net-(IC138-Pad11)") (class "Default")
      (node (ref "IC138") (pin "11") (pinfunction "11_11") (pintype "passive"))
      (node (ref "IC139") (pin "11") (pinfunction "11_11") (pintype "passive"))
      (node (ref "IC140") (pin "11") (pinfunction "11_11") (pintype "passive"))
      (node (ref "IC141") (pin "11") (pinfunction "11_11") (pintype "passive"))
    )
    (net (code "828") (name "Net-(IC138-Pad12)") (class "Default")
      (node (ref "IC138") (pin "12") (pinfunction "12_12") (pintype "passive"))
      (node (ref "IC139") (pin "12") (pinfunction "12_12") (pintype "passive"))
      (node (ref "IC140") (pin "12") (pinfunction "12_12") (pintype "passive"))
      (node (ref "IC141") (pin "12") (pinfunction "12_12") (pintype "passive"))
    )
    (net (code "829") (name "Net-(IC138-Pad13)") (class "Default")
      (node (ref "IC138") (pin "13") (pinfunction "13_13") (pintype "passive"))
      (node (ref "IC139") (pin "13") (pinfunction "13_13") (pintype "passive"))
      (node (ref "IC140") (pin "13") (pinfunction "13_13") (pintype "passive"))
      (node (ref "IC141") (pin "13") (pinfunction "13_13") (pintype "passive"))
    )
    (net (code "830") (name "Net-(IC138-Pad14)") (class "Default")
      (node (ref "IC138") (pin "14") (pinfunction "14_14") (pintype "passive"))
      (node (ref "IC139") (pin "14") (pinfunction "14_14") (pintype "passive"))
      (node (ref "IC140") (pin "14") (pinfunction "14_14") (pintype "passive"))
      (node (ref "IC141") (pin "14") (pinfunction "14_14") (pintype "passive"))
    )
    (net (code "831") (name "Net-(IC138-Pad15)") (class "Default")
      (node (ref "IC138") (pin "15") (pinfunction "15_15") (pintype "passive"))
      (node (ref "IC139") (pin "15") (pinfunction "15_15") (pintype "passive"))
      (node (ref "IC140") (pin "15") (pinfunction "15_15") (pintype "passive"))
      (node (ref "IC141") (pin "15") (pinfunction "15_15") (pintype "passive"))
    )
    (net (code "832") (name "Net-(IC138-Pad16)") (class "Default")
      (node (ref "IC138") (pin "16") (pinfunction "16_16") (pintype "passive"))
      (node (ref "IC139") (pin "16") (pinfunction "16_16") (pintype "passive"))
      (node (ref "IC140") (pin "16") (pinfunction "16_16") (pintype "passive"))
      (node (ref "IC141") (pin "16") (pinfunction "16_16") (pintype "passive"))
    )
    (net (code "833") (name "Net-(IC138-Pad17)") (class "Default")
      (node (ref "IC138") (pin "17") (pinfunction "17_17") (pintype "passive"))
      (node (ref "IC139") (pin "17") (pinfunction "17_17") (pintype "passive"))
      (node (ref "IC140") (pin "17") (pinfunction "17_17") (pintype "passive"))
      (node (ref "IC141") (pin "17") (pinfunction "17_17") (pintype "passive"))
    )
    (net (code "834") (name "Net-(IC138-Pad18)") (class "Default")
      (node (ref "IC138") (pin "18") (pinfunction "18_18") (pintype "passive"))
      (node (ref "IC139") (pin "18") (pinfunction "18_18") (pintype "passive"))
      (node (ref "IC140") (pin "18") (pinfunction "18_18") (pintype "passive"))
      (node (ref "IC141") (pin "18") (pinfunction "18_18") (pintype "passive"))
    )
    (net (code "835") (name "Net-(IC138-Pad19)") (class "Default")
      (node (ref "IC138") (pin "19") (pinfunction "19_19") (pintype "passive"))
      (node (ref "IC139") (pin "19") (pinfunction "19_19") (pintype "passive"))
      (node (ref "IC140") (pin "19") (pinfunction "19_19") (pintype "passive"))
      (node (ref "IC141") (pin "19") (pinfunction "19_19") (pintype "passive"))
    )
    (net (code "836") (name "Net-(IC138-Pad20)") (class "Default")
      (node (ref "IC138") (pin "20") (pinfunction "20_20") (pintype "passive"))
      (node (ref "IC139") (pin "20") (pinfunction "20_20") (pintype "passive"))
      (node (ref "IC140") (pin "20") (pinfunction "20_20") (pintype "passive"))
      (node (ref "IC141") (pin "20") (pinfunction "20_20") (pintype "passive"))
    )
    (net (code "837") (name "Net-(IC138-Pad21)") (class "Default")
      (node (ref "IC138") (pin "21") (pinfunction "21_21") (pintype "passive"))
      (node (ref "IC139") (pin "21") (pinfunction "21_21") (pintype "passive"))
      (node (ref "IC140") (pin "21") (pinfunction "21_21") (pintype "passive"))
      (node (ref "IC141") (pin "21") (pinfunction "21_21") (pintype "passive"))
    )
    (net (code "838") (name "Net-(IC138-Pad22)") (class "Default")
      (node (ref "IC138") (pin "22") (pinfunction "22_22") (pintype "passive"))
      (node (ref "IC139") (pin "22") (pinfunction "22_22") (pintype "passive"))
      (node (ref "IC140") (pin "22") (pinfunction "22_22") (pintype "passive"))
      (node (ref "IC141") (pin "22") (pinfunction "22_22") (pintype "passive"))
    )
    (net (code "839") (name "Net-(IC138-Pad23)") (class "Default")
      (node (ref "IC138") (pin "23") (pinfunction "23_23") (pintype "passive"))
      (node (ref "IC139") (pin "23") (pinfunction "23_23") (pintype "passive"))
      (node (ref "IC140") (pin "23") (pinfunction "23_23") (pintype "passive"))
      (node (ref "IC141") (pin "23") (pinfunction "23_23") (pintype "passive"))
    )
    (net (code "840") (name "Net-(IC138-Pad24)") (class "Default")
      (node (ref "IC138") (pin "24") (pinfunction "24_24") (pintype "passive"))
      (node (ref "IC139") (pin "24") (pinfunction "24_24") (pintype "passive"))
      (node (ref "IC140") (pin "24") (pinfunction "24_24") (pintype "passive"))
      (node (ref "IC141") (pin "24") (pinfunction "24_24") (pintype "passive"))
    )
    (net (code "841") (name "Net-(IC142-Pad1)") (class "Default")
      (node (ref "IC142") (pin "1") (pinfunction "1_1") (pintype "passive"))
      (node (ref "IC143") (pin "1") (pinfunction "1_1") (pintype "passive"))
      (node (ref "IC144") (pin "1") (pinfunction "1_1") (pintype "passive"))
      (node (ref "IC145") (pin "1") (pinfunction "1_1") (pintype "passive"))
    )
    (net (code "842") (name "Net-(IC142-Pad2)") (class "Default")
      (node (ref "IC142") (pin "2") (pinfunction "2_2") (pintype "passive"))
      (node (ref "IC143") (pin "2") (pinfunction "2_2") (pintype "passive"))
      (node (ref "IC144") (pin "2") (pinfunction "2_2") (pintype "passive"))
      (node (ref "IC145") (pin "2") (pinfunction "2_2") (pintype "passive"))
    )
    (net (code "843") (name "Net-(IC142-Pad3)") (class "Default")
      (node (ref "IC142") (pin "3") (pinfunction "3_3") (pintype "passive"))
      (node (ref "IC143") (pin "3") (pinfunction "3_3") (pintype "passive"))
      (node (ref "IC144") (pin "3") (pinfunction "3_3") (pintype "passive"))
      (node (ref "IC145") (pin "3") (pinfunction "3_3") (pintype "passive"))
    )
    (net (code "844") (name "Net-(IC142-Pad4)") (class "Default")
      (node (ref "IC142") (pin "4") (pinfunction "4_4") (pintype "passive"))
      (node (ref "IC143") (pin "4") (pinfunction "4_4") (pintype "passive"))
      (node (ref "IC144") (pin "4") (pinfunction "4_4") (pintype "passive"))
      (node (ref "IC145") (pin "4") (pinfunction "4_4") (pintype "passive"))
    )
    (net (code "845") (name "Net-(IC142-Pad5)") (class "Default")
      (node (ref "IC142") (pin "5") (pinfunction "5_5") (pintype "passive"))
      (node (ref "IC143") (pin "5") (pinfunction "5_5") (pintype "passive"))
      (node (ref "IC144") (pin "5") (pinfunction "5_5") (pintype "passive"))
      (node (ref "IC145") (pin "5") (pinfunction "5_5") (pintype "passive"))
    )
    (net (code "846") (name "Net-(IC142-Pad6)") (class "Default")
      (node (ref "IC142") (pin "6") (pinfunction "6_6") (pintype "passive"))
      (node (ref "IC143") (pin "6") (pinfunction "6_6") (pintype "passive"))
      (node (ref "IC144") (pin "6") (pinfunction "6_6") (pintype "passive"))
      (node (ref "IC145") (pin "6") (pinfunction "6_6") (pintype "passive"))
    )
    (net (code "847") (name "Net-(IC142-Pad7)") (class "Default")
      (node (ref "IC142") (pin "7") (pinfunction "7_7") (pintype "passive"))
      (node (ref "IC143") (pin "7") (pinfunction "7_7") (pintype "passive"))
      (node (ref "IC144") (pin "7") (pinfunction "7_7") (pintype "passive"))
      (node (ref "IC145") (pin "7") (pinfunction "7_7") (pintype "passive"))
    )
    (net (code "848") (name "Net-(IC142-Pad8)") (class "Default")
      (node (ref "IC142") (pin "8") (pinfunction "8_8") (pintype "passive"))
      (node (ref "IC143") (pin "8") (pinfunction "8_8") (pintype "passive"))
      (node (ref "IC144") (pin "8") (pinfunction "8_8") (pintype "passive"))
      (node (ref "IC145") (pin "8") (pinfunction "8_8") (pintype "passive"))
    )
    (net (code "849") (name "Net-(IC142-Pad9)") (class "Default")
      (node (ref "IC142") (pin "9") (pinfunction "9_9") (pintype "passive"))
      (node (ref "IC143") (pin "9") (pinfunction "9_9") (pintype "passive"))
      (node (ref "IC144") (pin "9") (pinfunction "9_9") (pintype "passive"))
      (node (ref "IC145") (pin "9") (pinfunction "9_9") (pintype "passive"))
    )
    (net (code "850") (name "Net-(IC142-Pad10)") (class "Default")
      (node (ref "IC142") (pin "10") (pinfunction "10_10") (pintype "passive"))
      (node (ref "IC143") (pin "10") (pinfunction "10_10") (pintype "passive"))
      (node (ref "IC144") (pin "10") (pinfunction "10_10") (pintype "passive"))
      (node (ref "IC145") (pin "10") (pinfunction "10_10") (pintype "passive"))
    )
    (net (code "851") (name "Net-(IC142-Pad11)") (class "Default")
      (node (ref "IC142") (pin "11") (pinfunction "11_11") (pintype "passive"))
      (node (ref "IC143") (pin "11") (pinfunction "11_11") (pintype "passive"))
      (node (ref "IC144") (pin "11") (pinfunction "11_11") (pintype "passive"))
      (node (ref "IC145") (pin "11") (pinfunction "11_11") (pintype "passive"))
    )
    (net (code "852") (name "Net-(IC142-Pad12)") (class "Default")
      (node (ref "IC142") (pin "12") (pinfunction "12_12") (pintype "passive"))
      (node (ref "IC143") (pin "12") (pinfunction "12_12") (pintype "passive"))
      (node (ref "IC144") (pin "12") (pinfunction "12_12") (pintype "passive"))
      (node (ref "IC145") (pin "12") (pinfunction "12_12") (pintype "passive"))
    )
    (net (code "853") (name "Net-(IC142-Pad13)") (class "Default")
      (node (ref "IC142") (pin "13") (pinfunction "13_13") (pintype "passive"))
      (node (ref "IC143") (pin "13") (pinfunction "13_13") (pintype "passive"))
      (node (ref "IC144") (pin "13") (pinfunction "13_13") (pintype "passive"))
      (node (ref "IC145") (pin "13") (pinfunction "13_13") (pintype "passive"))
    )
    (net (code "854") (name "Net-(IC142-Pad14)") (class "Default")
      (node (ref "IC142") (pin "14") (pinfunction "14_14") (pintype "passive"))
      (node (ref "IC143") (pin "14") (pinfunction "14_14") (pintype "passive"))
      (node (ref "IC144") (pin "14") (pinfunction "14_14") (pintype "passive"))
      (node (ref "IC145") (pin "14") (pinfunction "14_14") (pintype "passive"))
    )
    (net (code "855") (name "Net-(IC142-Pad15)") (class "Default")
      (node (ref "IC142") (pin "15") (pinfunction "15_15") (pintype "passive"))
      (node (ref "IC143") (pin "15") (pinfunction "15_15") (pintype "passive"))
      (node (ref "IC144") (pin "15") (pinfunction "15_15") (pintype "passive"))
      (node (ref "IC145") (pin "15") (pinfunction "15_15") (pintype "passive"))
    )
    (net (code "856") (name "Net-(IC142-Pad16)") (class "Default")
      (node (ref "IC142") (pin "16") (pinfunction "16_16") (pintype "passive"))
      (node (ref "IC143") (pin "16") (pinfunction "16_16") (pintype "passive"))
      (node (ref "IC144") (pin "16") (pinfunction "16_16") (pintype "passive"))
      (node (ref "IC145") (pin "16") (pinfunction "16_16") (pintype "passive"))
    )
    (net (code "857") (name "Net-(IC142-Pad17)") (class "Default")
      (node (ref "IC142") (pin "17") (pinfunction "17_17") (pintype "passive"))
      (node (ref "IC143") (pin "17") (pinfunction "17_17") (pintype "passive"))
      (node (ref "IC144") (pin "17") (pinfunction "17_17") (pintype "passive"))
      (node (ref "IC145") (pin "17") (pinfunction "17_17") (pintype "passive"))
    )
    (net (code "858") (name "Net-(IC142-Pad18)") (class "Default")
      (node (ref "IC142") (pin "18") (pinfunction "18_18") (pintype "passive"))
      (node (ref "IC143") (pin "18") (pinfunction "18_18") (pintype "passive"))
      (node (ref "IC144") (pin "18") (pinfunction "18_18") (pintype "passive"))
      (node (ref "IC145") (pin "18") (pinfunction "18_18") (pintype "passive"))
    )
    (net (code "859") (name "Net-(IC142-Pad19)") (class "Default")
      (node (ref "IC142") (pin "19") (pinfunction "19_19") (pintype "passive"))
      (node (ref "IC143") (pin "19") (pinfunction "19_19") (pintype "passive"))
      (node (ref "IC144") (pin "19") (pinfunction "19_19") (pintype "passive"))
      (node (ref "IC145") (pin "19") (pinfunction "19_19") (pintype "passive"))
    )
    (net (code "860") (name "Net-(IC142-Pad20)") (class "Default")
      (node (ref "IC142") (pin "20") (pinfunction "20_20") (pintype "passive"))
      (node (ref "IC143") (pin "20") (pinfunction "20_20") (pintype "passive"))
      (node (ref "IC144") (pin "20") (pinfunction "20_20") (pintype "passive"))
      (node (ref "IC145") (pin "20") (pinfunction "20_20") (pintype "passive"))
    )
    (net (code "861") (name "Net-(IC142-Pad21)") (class "Default")
      (node (ref "IC142") (pin "21") (pinfunction "21_21") (pintype "passive"))
      (node (ref "IC143") (pin "21") (pinfunction "21_21") (pintype "passive"))
      (node (ref "IC144") (pin "21") (pinfunction "21_21") (pintype "passive"))
      (node (ref "IC145") (pin "21") (pinfunction "21_21") (pintype "passive"))
    )
    (net (code "862") (name "Net-(IC142-Pad22)") (class "Default")
      (node (ref "IC142") (pin "22") (pinfunction "22_22") (pintype "passive"))
      (node (ref "IC143") (pin "22") (pinfunction "22_22") (pintype "passive"))
      (node (ref "IC144") (pin "22") (pinfunction "22_22") (pintype "passive"))
      (node (ref "IC145") (pin "22") (pinfunction "22_22") (pintype "passive"))
    )
    (net (code "863") (name "Net-(IC142-Pad23)") (class "Default")
      (node (ref "IC142") (pin "23") (pinfunction "23_23") (pintype "passive"))
      (node (ref "IC143") (pin "23") (pinfunction "23_23") (pintype "passive"))
      (node (ref "IC144") (pin "23") (pinfunction "23_23") (pintype "passive"))
      (node (ref "IC145") (pin "23") (pinfunction "23_23") (pintype "passive"))
    )
    (net (code "864") (name "Net-(IC142-Pad24)") (class "Default")
      (node (ref "IC142") (pin "24") (pinfunction "24_24") (pintype "passive"))
      (node (ref "IC143") (pin "24") (pinfunction "24_24") (pintype "passive"))
      (node (ref "IC144") (pin "24") (pinfunction "24_24") (pintype "passive"))
      (node (ref "IC145") (pin "24") (pinfunction "24_24") (pintype "passive"))
    )
    (net (code "865") (name "Net-(IC146-Pad1)") (class "Default")
      (node (ref "IC146") (pin "1") (pinfunction "1_1") (pintype "passive"))
      (node (ref "IC147") (pin "1") (pinfunction "1_1") (pintype "passive"))
      (node (ref "IC148") (pin "1") (pinfunction "1_1") (pintype "passive"))
      (node (ref "IC149") (pin "1") (pinfunction "1_1") (pintype "passive"))
    )
    (net (code "866") (name "Net-(IC146-Pad2)") (class "Default")
      (node (ref "IC146") (pin "2") (pinfunction "2_2") (pintype "passive"))
      (node (ref "IC147") (pin "2") (pinfunction "2_2") (pintype "passive"))
      (node (ref "IC148") (pin "2") (pinfunction "2_2") (pintype "passive"))
      (node (ref "IC149") (pin "2") (pinfunction "2_2") (pintype "passive"))
    )
    (net (code "867") (name "Net-(IC146-Pad3)") (class "Default")
      (node (ref "IC146") (pin "3") (pinfunction "3_3") (pintype "passive"))
      (node (ref "IC147") (pin "3") (pinfunction "3_3") (pintype "passive"))
      (node (ref "IC148") (pin "3") (pinfunction "3_3") (pintype "passive"))
      (node (ref "IC149") (pin "3") (pinfunction "3_3") (pintype "passive"))
    )
    (net (code "868") (name "Net-(IC146-Pad4)") (class "Default")
      (node (ref "IC146") (pin "4") (pinfunction "4_4") (pintype "passive"))
      (node (ref "IC147") (pin "4") (pinfunction "4_4") (pintype "passive"))
      (node (ref "IC148") (pin "4") (pinfunction "4_4") (pintype "passive"))
      (node (ref "IC149") (pin "4") (pinfunction "4_4") (pintype "passive"))
    )
    (net (code "869") (name "Net-(IC146-Pad5)") (class "Default")
      (node (ref "IC146") (pin "5") (pinfunction "5_5") (pintype "passive"))
      (node (ref "IC147") (pin "5") (pinfunction "5_5") (pintype "passive"))
      (node (ref "IC148") (pin "5") (pinfunction "5_5") (pintype "passive"))
      (node (ref "IC149") (pin "5") (pinfunction "5_5") (pintype "passive"))
    )
    (net (code "870") (name "Net-(IC146-Pad6)") (class "Default")
      (node (ref "IC146") (pin "6") (pinfunction "6_6") (pintype "passive"))
      (node (ref "IC147") (pin "6") (pinfunction "6_6") (pintype "passive"))
      (node (ref "IC148") (pin "6") (pinfunction "6_6") (pintype "passive"))
      (node (ref "IC149") (pin "6") (pinfunction "6_6") (pintype "passive"))
    )
    (net (code "871") (name "Net-(IC146-Pad7)") (class "Default")
      (node (ref "IC146") (pin "7") (pinfunction "7_7") (pintype "passive"))
      (node (ref "IC147") (pin "7") (pinfunction "7_7") (pintype "passive"))
      (node (ref "IC148") (pin "7") (pinfunction "7_7") (pintype "passive"))
      (node (ref "IC149") (pin "7") (pinfunction "7_7") (pintype "passive"))
    )
    (net (code "872") (name "Net-(IC146-Pad8)") (class "Default")
      (node (ref "IC146") (pin "8") (pinfunction "8_8") (pintype "passive"))
      (node (ref "IC147") (pin "8") (pinfunction "8_8") (pintype "passive"))
      (node (ref "IC148") (pin "8") (pinfunction "8_8") (pintype "passive"))
      (node (ref "IC149") (pin "8") (pinfunction "8_8") (pintype "passive"))
    )
    (net (code "873") (name "Net-(IC146-Pad9)") (class "Default")
      (node (ref "IC146") (pin "9") (pinfunction "9_9") (pintype "passive"))
      (node (ref "IC147") (pin "9") (pinfunction "9_9") (pintype "passive"))
      (node (ref "IC148") (pin "9") (pinfunction "9_9") (pintype "passive"))
      (node (ref "IC149") (pin "9") (pinfunction "9_9") (pintype "passive"))
    )
    (net (code "874") (name "Net-(IC146-Pad10)") (class "Default")
      (node (ref "IC146") (pin "10") (pinfunction "10_10") (pintype "passive"))
      (node (ref "IC147") (pin "10") (pinfunction "10_10") (pintype "passive"))
      (node (ref "IC148") (pin "10") (pinfunction "10_10") (pintype "passive"))
      (node (ref "IC149") (pin "10") (pinfunction "10_10") (pintype "passive"))
    )
    (net (code "875") (name "Net-(IC146-Pad11)") (class "Default")
      (node (ref "IC146") (pin "11") (pinfunction "11_11") (pintype "passive"))
      (node (ref "IC147") (pin "11") (pinfunction "11_11") (pintype "passive"))
      (node (ref "IC148") (pin "11") (pinfunction "11_11") (pintype "passive"))
      (node (ref "IC149") (pin "11") (pinfunction "11_11") (pintype "passive"))
    )
    (net (code "876") (name "Net-(IC146-Pad12)") (class "Default")
      (node (ref "IC146") (pin "12") (pinfunction "12_12") (pintype "passive"))
      (node (ref "IC147") (pin "12") (pinfunction "12_12") (pintype "passive"))
      (node (ref "IC148") (pin "12") (pinfunction "12_12") (pintype "passive"))
      (node (ref "IC149") (pin "12") (pinfunction "12_12") (pintype "passive"))
    )
    (net (code "877") (name "Net-(IC146-Pad13)") (class "Default")
      (node (ref "IC146") (pin "13") (pinfunction "13_13") (pintype "passive"))
      (node (ref "IC147") (pin "13") (pinfunction "13_13") (pintype "passive"))
      (node (ref "IC148") (pin "13") (pinfunction "13_13") (pintype "passive"))
      (node (ref "IC149") (pin "13") (pinfunction "13_13") (pintype "passive"))
    )
    (net (code "878") (name "Net-(IC146-Pad14)") (class "Default")
      (node (ref "IC146") (pin "14") (pinfunction "14_14") (pintype "passive"))
      (node (ref "IC147") (pin "14") (pinfunction "14_14") (pintype "passive"))
      (node (ref "IC148") (pin "14") (pinfunction "14_14") (pintype "passive"))
      (node (ref "IC149") (pin "14") (pinfunction "14_14") (pintype "passive"))
    )
    (net (code "879") (name "Net-(IC146-Pad15)") (class "Default")
      (node (ref "IC146") (pin "15") (pinfunction "15_15") (pintype "passive"))
      (node (ref "IC147") (pin "15") (pinfunction "15_15") (pintype "passive"))
      (node (ref "IC148") (pin "15") (pinfunction "15_15") (pintype "passive"))
      (node (ref "IC149") (pin "15") (pinfunction "15_15") (pintype "passive"))
    )
    (net (code "880") (name "Net-(IC146-Pad16)") (class "Default")
      (node (ref "IC146") (pin "16") (pinfunction "16_16") (pintype "passive"))
      (node (ref "IC147") (pin "16") (pinfunction "16_16") (pintype "passive"))
      (node (ref "IC148") (pin "16") (pinfunction "16_16") (pintype "passive"))
      (node (ref "IC149") (pin "16") (pinfunction "16_16") (pintype "passive"))
    )
    (net (code "881") (name "Net-(IC146-Pad17)") (class "Default")
      (node (ref "IC146") (pin "17") (pinfunction "17_17") (pintype "passive"))
      (node (ref "IC147") (pin "17") (pinfunction "17_17") (pintype "passive"))
      (node (ref "IC148") (pin "17") (pinfunction "17_17") (pintype "passive"))
      (node (ref "IC149") (pin "17") (pinfunction "17_17") (pintype "passive"))
    )
    (net (code "882") (name "Net-(IC146-Pad18)") (class "Default")
      (node (ref "IC146") (pin "18") (pinfunction "18_18") (pintype "passive"))
      (node (ref "IC147") (pin "18") (pinfunction "18_18") (pintype "passive"))
      (node (ref "IC148") (pin "18") (pinfunction "18_18") (pintype "passive"))
      (node (ref "IC149") (pin "18") (pinfunction "18_18") (pintype "passive"))
    )
    (net (code "883") (name "Net-(IC146-Pad19)") (class "Default")
      (node (ref "IC146") (pin "19") (pinfunction "19_19") (pintype "passive"))
      (node (ref "IC147") (pin "19") (pinfunction "19_19") (pintype "passive"))
      (node (ref "IC148") (pin "19") (pinfunction "19_19") (pintype "passive"))
      (node (ref "IC149") (pin "19") (pinfunction "19_19") (pintype "passive"))
    )
    (net (code "884") (name "Net-(IC146-Pad20)") (class "Default")
      (node (ref "IC146") (pin "20") (pinfunction "20_20") (pintype "passive"))
      (node (ref "IC147") (pin "20") (pinfunction "20_20") (pintype "passive"))
      (node (ref "IC148") (pin "20") (pinfunction "20_20") (pintype "passive"))
      (node (ref "IC149") (pin "20") (pinfunction "20_20") (pintype "passive"))
    )
    (net (code "885") (name "Net-(IC146-Pad21)") (class "Default")
      (node (ref "IC146") (pin "21") (pinfunction "21_21") (pintype "passive"))
      (node (ref "IC147") (pin "21") (pinfunction "21_21") (pintype "passive"))
      (node (ref "IC148") (pin "21") (pinfunction "21_21") (pintype "passive"))
      (node (ref "IC149") (pin "21") (pinfunction "21_21") (pintype "passive"))
    )
    (net (code "886") (name "Net-(IC146-Pad22)") (class "Default")
      (node (ref "IC146") (pin "22") (pinfunction "22_22") (pintype "passive"))
      (node (ref "IC147") (pin "22") (pinfunction "22_22") (pintype "passive"))
      (node (ref "IC148") (pin "22") (pinfunction "22_22") (pintype "passive"))
      (node (ref "IC149") (pin "22") (pinfunction "22_22") (pintype "passive"))
    )
    (net (code "887") (name "Net-(IC146-Pad23)") (class "Default")
      (node (ref "IC146") (pin "23") (pinfunction "23_23") (pintype "passive"))
      (node (ref "IC147") (pin "23") (pinfunction "23_23") (pintype "passive"))
      (node (ref "IC148") (pin "23") (pinfunction "23_23") (pintype "passive"))
      (node (ref "IC149") (pin "23") (pinfunction "23_23") (pintype "passive"))
    )
    (net (code "888") (name "Net-(IC146-Pad24)") (class "Default")
      (node (ref "IC146") (pin "24") (pinfunction "24_24") (pintype "passive"))
      (node (ref "IC147") (pin "24") (pinfunction "24_24") (pintype "passive"))
      (node (ref "IC148") (pin "24") (pinfunction "24_24") (pintype "passive"))
      (node (ref "IC149") (pin "24") (pinfunction "24_24") (pintype "passive"))
    )
    (net (code "889") (name "Net-(IC150-Pad1)") (class "Default")
      (node (ref "IC150") (pin "1") (pinfunction "1_1") (pintype "passive"))
      (node (ref "IC151") (pin "1") (pinfunction "1_1") (pintype "passive"))
      (node (ref "IC152") (pin "1") (pinfunction "1_1") (pintype "passive"))
      (node (ref "IC153") (pin "1") (pinfunction "1_1") (pintype "passive"))
    )
    (net (code "890") (name "Net-(IC150-Pad2)") (class "Default")
      (node (ref "IC150") (pin "2") (pinfunction "2_2") (pintype "passive"))
      (node (ref "IC151") (pin "2") (pinfunction "2_2") (pintype "passive"))
      (node (ref "IC152") (pin "2") (pinfunction "2_2") (pintype "passive"))
      (node (ref "IC153") (pin "2") (pinfunction "2_2") (pintype "passive"))
    )
    (net (code "891") (name "Net-(IC150-Pad3)") (class "Default")
      (node (ref "IC150") (pin "3") (pinfunction "3_3") (pintype "passive"))
      (node (ref "IC151") (pin "3") (pinfunction "3_3") (pintype "passive"))
      (node (ref "IC152") (pin "3") (pinfunction "3_3") (pintype "passive"))
      (node (ref "IC153") (pin "3") (pinfunction "3_3") (pintype "passive"))
    )
    (net (code "892") (name "Net-(IC150-Pad4)") (class "Default")
      (node (ref "IC150") (pin "4") (pinfunction "4_4") (pintype "passive"))
      (node (ref "IC151") (pin "4") (pinfunction "4_4") (pintype "passive"))
      (node (ref "IC152") (pin "4") (pinfunction "4_4") (pintype "passive"))
      (node (ref "IC153") (pin "4") (pinfunction "4_4") (pintype "passive"))
    )
    (net (code "893") (name "Net-(IC150-Pad5)") (class "Default")
      (node (ref "IC150") (pin "5") (pinfunction "5_5") (pintype "passive"))
      (node (ref "IC151") (pin "5") (pinfunction "5_5") (pintype "passive"))
      (node (ref "IC152") (pin "5") (pinfunction "5_5") (pintype "passive"))
      (node (ref "IC153") (pin "5") (pinfunction "5_5") (pintype "passive"))
    )
    (net (code "894") (name "Net-(IC150-Pad6)") (class "Default")
      (node (ref "IC150") (pin "6") (pinfunction "6_6") (pintype "passive"))
      (node (ref "IC151") (pin "6") (pinfunction "6_6") (pintype "passive"))
      (node (ref "IC152") (pin "6") (pinfunction "6_6") (pintype "passive"))
      (node (ref "IC153") (pin "6") (pinfunction "6_6") (pintype "passive"))
    )
    (net (code "895") (name "Net-(IC150-Pad7)") (class "Default")
      (node (ref "IC150") (pin "7") (pinfunction "7_7") (pintype "passive"))
      (node (ref "IC151") (pin "7") (pinfunction "7_7") (pintype "passive"))
      (node (ref "IC152") (pin "7") (pinfunction "7_7") (pintype "passive"))
      (node (ref "IC153") (pin "7") (pinfunction "7_7") (pintype "passive"))
    )
    (net (code "896") (name "Net-(IC150-Pad8)") (class "Default")
      (node (ref "IC150") (pin "8") (pinfunction "8_8") (pintype "passive"))
      (node (ref "IC151") (pin "8") (pinfunction "8_8") (pintype "passive"))
      (node (ref "IC152") (pin "8") (pinfunction "8_8") (pintype "passive"))
      (node (ref "IC153") (pin "8") (pinfunction "8_8") (pintype "passive"))
    )
    (net (code "897") (name "Net-(IC150-Pad9)") (class "Default")
      (node (ref "IC150") (pin "9") (pinfunction "9_9") (pintype "passive"))
      (node (ref "IC151") (pin "9") (pinfunction "9_9") (pintype "passive"))
      (node (ref "IC152") (pin "9") (pinfunction "9_9") (pintype "passive"))
      (node (ref "IC153") (pin "9") (pinfunction "9_9") (pintype "passive"))
    )
    (net (code "898") (name "Net-(IC150-Pad10)") (class "Default")
      (node (ref "IC150") (pin "10") (pinfunction "10_10") (pintype "passive"))
      (node (ref "IC151") (pin "10") (pinfunction "10_10") (pintype "passive"))
      (node (ref "IC152") (pin "10") (pinfunction "10_10") (pintype "passive"))
      (node (ref "IC153") (pin "10") (pinfunction "10_10") (pintype "passive"))
    )
    (net (code "899") (name "Net-(IC150-Pad11)") (class "Default")
      (node (ref "IC150") (pin "11") (pinfunction "11_11") (pintype "passive"))
      (node (ref "IC151") (pin "11") (pinfunction "11_11") (pintype "passive"))
      (node (ref "IC152") (pin "11") (pinfunction "11_11") (pintype "passive"))
      (node (ref "IC153") (pin "11") (pinfunction "11_11") (pintype "passive"))
    )
    (net (code "900") (name "Net-(IC150-Pad12)") (class "Default")
      (node (ref "IC150") (pin "12") (pinfunction "12_12") (pintype "passive"))
      (node (ref "IC151") (pin "12") (pinfunction "12_12") (pintype "passive"))
      (node (ref "IC152") (pin "12") (pinfunction "12_12") (pintype "passive"))
      (node (ref "IC153") (pin "12") (pinfunction "12_12") (pintype "passive"))
    )
    (net (code "901") (name "Net-(IC150-Pad13)") (class "Default")
      (node (ref "IC150") (pin "13") (pinfunction "13_13") (pintype "passive"))
      (node (ref "IC151") (pin "13") (pinfunction "13_13") (pintype "passive"))
      (node (ref "IC152") (pin "13") (pinfunction "13_13") (pintype "passive"))
      (node (ref "IC153") (pin "13") (pinfunction "13_13") (pintype "passive"))
    )
    (net (code "902") (name "Net-(IC150-Pad14)") (class "Default")
      (node (ref "IC150") (pin "14") (pinfunction "14_14") (pintype "passive"))
      (node (ref "IC151") (pin "14") (pinfunction "14_14") (pintype "passive"))
      (node (ref "IC152") (pin "14") (pinfunction "14_14") (pintype "passive"))
      (node (ref "IC153") (pin "14") (pinfunction "14_14") (pintype "passive"))
    )
    (net (code "903") (name "Net-(IC150-Pad15)") (class "Default")
      (node (ref "IC150") (pin "15") (pinfunction "15_15") (pintype "passive"))
      (node (ref "IC151") (pin "15") (pinfunction "15_15") (pintype "passive"))
      (node (ref "IC152") (pin "15") (pinfunction "15_15") (pintype "passive"))
      (node (ref "IC153") (pin "15") (pinfunction "15_15") (pintype "passive"))
    )
    (net (code "904") (name "Net-(IC150-Pad16)") (class "Default")
      (node (ref "IC150") (pin "16") (pinfunction "16_16") (pintype "passive"))
      (node (ref "IC151") (pin "16") (pinfunction "16_16") (pintype "passive"))
      (node (ref "IC152") (pin "16") (pinfunction "16_16") (pintype "passive"))
      (node (ref "IC153") (pin "16") (pinfunction "16_16") (pintype "passive"))
    )
    (net (code "905") (name "Net-(IC150-Pad17)") (class "Default")
      (node (ref "IC150") (pin "17") (pinfunction "17_17") (pintype "passive"))
      (node (ref "IC151") (pin "17") (pinfunction "17_17") (pintype "passive"))
      (node (ref "IC152") (pin "17") (pinfunction "17_17") (pintype "passive"))
      (node (ref "IC153") (pin "17") (pinfunction "17_17") (pintype "passive"))
    )
    (net (code "906") (name "Net-(IC150-Pad18)") (class "Default")
      (node (ref "IC150") (pin "18") (pinfunction "18_18") (pintype "passive"))
      (node (ref "IC151") (pin "18") (pinfunction "18_18") (pintype "passive"))
      (node (ref "IC152") (pin "18") (pinfunction "18_18") (pintype "passive"))
      (node (ref "IC153") (pin "18") (pinfunction "18_18") (pintype "passive"))
    )
    (net (code "907") (name "Net-(IC150-Pad19)") (class "Default")
      (node (ref "IC150") (pin "19") (pinfunction "19_19") (pintype "passive"))
      (node (ref "IC151") (pin "19") (pinfunction "19_19") (pintype "passive"))
      (node (ref "IC152") (pin "19") (pinfunction "19_19") (pintype "passive"))
      (node (ref "IC153") (pin "19") (pinfunction "19_19") (pintype "passive"))
    )
    (net (code "908") (name "Net-(IC150-Pad20)") (class "Default")
      (node (ref "IC150") (pin "20") (pinfunction "20_20") (pintype "passive"))
      (node (ref "IC151") (pin "20") (pinfunction "20_20") (pintype "passive"))
      (node (ref "IC152") (pin "20") (pinfunction "20_20") (pintype "passive"))
      (node (ref "IC153") (pin "20") (pinfunction "20_20") (pintype "passive"))
    )
    (net (code "909") (name "Net-(IC150-Pad21)") (class "Default")
      (node (ref "IC150") (pin "21") (pinfunction "21_21") (pintype "passive"))
      (node (ref "IC151") (pin "21") (pinfunction "21_21") (pintype "passive"))
      (node (ref "IC152") (pin "21") (pinfunction "21_21") (pintype "passive"))
      (node (ref "IC153") (pin "21") (pinfunction "21_21") (pintype "passive"))
    )
    (net (code "910") (name "Net-(IC150-Pad22)") (class "Default")
      (node (ref "IC150") (pin "22") (pinfunction "22_22") (pintype "passive"))
      (node (ref "IC151") (pin "22") (pinfunction "22_22") (pintype "passive"))
      (node (ref "IC152") (pin "22") (pinfunction "22_22") (pintype "passive"))
      (node (ref "IC153") (pin "22") (pinfunction "22_22") (pintype "passive"))
    )
    (net (code "911") (name "Net-(IC150-Pad23)") (class "Default")
      (node (ref "IC150") (pin "23") (pinfunction "23_23") (pintype "passive"))
      (node (ref "IC151") (pin "23") (pinfunction "23_23") (pintype "passive"))
      (node (ref "IC152") (pin "23") (pinfunction "23_23") (pintype "passive"))
      (node (ref "IC153") (pin "23") (pinfunction "23_23") (pintype "passive"))
    )
    (net (code "912") (name "Net-(IC150-Pad24)") (class "Default")
      (node (ref "IC150") (pin "24") (pinfunction "24_24") (pintype "passive"))
      (node (ref "IC151") (pin "24") (pinfunction "24_24") (pintype "passive"))
      (node (ref "IC152") (pin "24") (pinfunction "24_24") (pintype "passive"))
      (node (ref "IC153") (pin "24") (pinfunction "24_24") (pintype "passive"))
    )
    (net (code "913") (name "Net-(Q1-B)") (class "Default")
      (node (ref "Q1") (pin "2") (pinfunction "B_2") (pintype "passive"))
      (node (ref "R6") (pin "2") (pinfunction "2_2") (pintype "passive"))
    )
    (net (code "914") (name "Net-(U$2A-1)") (class "Default")
      (node (ref "D9") (pin "1") (pinfunction "1_1") (pintype "passive"))
      (node (ref "U$2") (pin "AA1") (pinfunction "1_AA1") (pintype "bidirectional"))
    )
    (net (code "915") (name "Net-(U$2AK-1)") (class "Default")
      (node (ref "D7") (pin "1") (pinfunction "1_1") (pintype "passive"))
      (node (ref "U$2") (pin "BA1") (pinfunction "1_BA1") (pintype "bidirectional"))
    )
    (net (code "916") (name "Net-(U$2AM-1)") (class "Default")
      (node (ref "D7") (pin "2") (pinfunction "2_2") (pintype "passive"))
      (node (ref "U$2") (pin "BB1") (pinfunction "1_BB1") (pintype "bidirectional"))
    )
    (net (code "917") (name "Net-(U$2BN-1)") (class "Default")
      (node (ref "D8") (pin "15") (pinfunction "15_15") (pintype "passive"))
      (node (ref "U$2") (pin "BS2") (pinfunction "1_BS2") (pintype "bidirectional"))
    )
    (net (code "918") (name "Net-(U$2BU-1)") (class "Default")
      (node (ref "D11") (pin "1") (pinfunction "1_1") (pintype "passive"))
      (node (ref "U$2") (pin "CA1") (pinfunction "1_CA1") (pintype "bidirectional"))
    )
    (net (code "919") (name "Net-(U$2BW-1)") (class "Default")
      (node (ref "D11") (pin "2") (pinfunction "2_2") (pintype "passive"))
      (node (ref "U$2") (pin "CB1") (pinfunction "1_CB1") (pintype "bidirectional"))
    )
    (net (code "920") (name "Net-(U$2C-1)") (class "Default")
      (node (ref "D9") (pin "2") (pinfunction "2_2") (pintype "passive"))
      (node (ref "U$2") (pin "AB1") (pinfunction "1_AB1") (pintype "bidirectional"))
    )
    (net (code "921") (name "Net-(U$2DE-1)") (class "Default")
      (node (ref "D13") (pin "1") (pinfunction "1_1") (pintype "passive"))
      (node (ref "U$2") (pin "DA1") (pinfunction "1_DA1") (pintype "bidirectional"))
    )
    (net (code "922") (name "Net-(U$2DG-1)") (class "Default")
      (node (ref "D13") (pin "2") (pinfunction "2_2") (pintype "passive"))
      (node (ref "U$2") (pin "DB1") (pinfunction "1_DB1") (pintype "bidirectional"))
    )
    (net (code "923") (name "POWER_OK") (class "Default")
      (node (ref "D8") (pin "18") (pinfunction "18_18") (pintype "passive"))
      (node (ref "R6") (pin "1") (pinfunction "1_1") (pintype "passive"))
      (node (ref "U$2") (pin "BV2") (pinfunction "1_BV2") (pintype "bidirectional"))
    )
    (net (code "924") (name "PULSE_LA") (class "Default")
      (node (ref "D14") (pin "14") (pinfunction "14_14") (pintype "passive"))
      (node (ref "U$2") (pin "DR2") (pinfunction "1_DR2") (pintype "bidirectional"))
    )
    (net (code "925") (name "READ_OK") (class "Default")
      (node (ref "IC7") (pin "10") (pinfunction "I1_10") (pintype "input"))
      (node (ref "IC9") (pin "6") (pinfunction "~{Q}_6") (pintype "output"))
    )
    (net (code "926") (name "RETURN") (class "Default")
      (node (ref "D10") (pin "14") (pinfunction "14_14") (pintype "passive"))
      (node (ref "U$2") (pin "AR2") (pinfunction "1_AR2") (pintype "bidirectional"))
    )
    (net (code "927") (name "SOURCE") (class "Default")
      (node (ref "D10") (pin "10") (pinfunction "10_10") (pintype "passive"))
      (node (ref "IC8") (pin "3") (pinfunction "I_3") (pintype "input"))
      (node (ref "U$2") (pin "AL2") (pinfunction "1_AL2") (pintype "bidirectional"))
    )
    (net (code "928") (name "SOURCE_H") (class "Default")
      (node (ref "IC7") (pin "5") (pinfunction "I2_5") (pintype "input"))
      (node (ref "IC8") (pin "10") (pinfunction "O_10") (pintype "output"))
      (node (ref "IC9") (pin "11") (pinfunction "CLK_11") (pintype "input"))
    )
    (net (code "929") (name "SOURCE_L") (class "Default")
      (node (ref "IC8") (pin "11") (pinfunction "I_11") (pintype "input"))
      (node (ref "IC8") (pin "4") (pinfunction "O_4") (pintype "output"))
      (node (ref "IC9") (pin "3") (pinfunction "CLK_3") (pintype "input"))
    )
    (net (code "930") (name "STROBE") (class "Default")
      (node (ref "D10") (pin "11") (pinfunction "11_11") (pintype "passive"))
      (node (ref "U$2") (pin "AM2") (pinfunction "1_AM2") (pintype "bidirectional"))
    )
    (net (code "931") (name "SWITCH") (class "Default")
      (node (ref "D14") (pin "18") (pinfunction "18_18") (pintype "passive"))
      (node (ref "U$2") (pin "DV2") (pinfunction "1_DV2") (pintype "bidirectional"))
    )
    (net (code "932") (name "TP1") (class "Default")
      (node (ref "D12") (pin "4") (pinfunction "4_4") (pintype "passive"))
      (node (ref "U$2") (pin "CD2") (pinfunction "1_CD2") (pintype "bidirectional"))
    )
    (net (code "933") (name "TP2") (class "Default")
      (node (ref "D12") (pin "5") (pinfunction "5_5") (pintype "passive"))
      (node (ref "U$2") (pin "CE2") (pinfunction "1_CE2") (pintype "bidirectional"))
    )
    (net (code "934") (name "TP3") (class "Default")
      (node (ref "D12") (pin "7") (pinfunction "7_7") (pintype "passive"))
      (node (ref "U$2") (pin "CH2") (pinfunction "1_CH2") (pintype "bidirectional"))
    )
    (net (code "935") (name "TP4") (class "Default")
      (node (ref "D12") (pin "8") (pinfunction "8_8") (pintype "passive"))
      (node (ref "U$2") (pin "CJ2") (pinfunction "1_CJ2") (pintype "bidirectional"))
    )
    (net (code "936") (name "V+") (class "Default")
      (node (ref "C1") (pin "1") (pinfunction "1_1") (pintype "passive"))
      (node (ref "C3") (pin "1") (pinfunction "1_1") (pintype "passive"))
      (node (ref "D1") (pin "C") (pinfunction "C_C") (pintype "passive"))
      (node (ref "D2") (pin "C") (pinfunction "C_C") (pintype "passive"))
      (node (ref "IC3") (pin "28") (pinfunction "VCC_28") (pintype "power_in"))
      (node (ref "IC4") (pin "28") (pinfunction "VCC_28") (pintype "power_in"))
      (node (ref "R7") (pin "2") (pinfunction "2_2") (pintype "passive"))
    )
    (net (code "937") (name "VCC") (class "Default")
      (node (ref "C10") (pin "+") (pinfunction "+_+") (pintype "passive"))
      (node (ref "C11") (pin "1") (pinfunction "1_1") (pintype "passive"))
      (node (ref "C4") (pin "1") (pinfunction "1_1") (pintype "passive"))
      (node (ref "C5") (pin "1") (pinfunction "1_1") (pintype "passive"))
      (node (ref "C6") (pin "1") (pinfunction "1_1") (pintype "passive"))
      (node (ref "C7") (pin "1") (pinfunction "1_1") (pintype "passive"))
      (node (ref "C8") (pin "1") (pinfunction "1_1") (pintype "passive"))
      (node (ref "C9") (pin "1") (pinfunction "1_1") (pintype "passive"))
      (node (ref "D10") (pin "1") (pinfunction "1_1") (pintype "passive"))
      (node (ref "D12") (pin "1") (pinfunction "1_1") (pintype "passive"))
      (node (ref "D2") (pin "A") (pinfunction "A_A") (pintype "passive"))
      (node (ref "D8") (pin "1") (pinfunction "1_1") (pintype "passive"))
      (node (ref "IC9") (pin "10") (pinfunction "PRE_10") (pintype "input"))
      (node (ref "IC9") (pin "13") (pinfunction "CLR_13") (pintype "input"))
      (node (ref "IC9") (pin "2") (pinfunction "D_2") (pintype "input"))
      (node (ref "IC9") (pin "4") (pinfunction "PRE_4") (pintype "input"))
      (node (ref "R5") (pin "10") (pinfunction "2_10") (pintype "passive"))
      (node (ref "R5") (pin "11") (pinfunction "2_11") (pintype "passive"))
      (node (ref "R5") (pin "12") (pinfunction "2_12") (pintype "passive"))
      (node (ref "R5") (pin "13") (pinfunction "2_13") (pintype "passive"))
      (node (ref "R5") (pin "14") (pinfunction "2_14") (pintype "passive"))
      (node (ref "R5") (pin "15") (pinfunction "2_15") (pintype "passive"))
      (node (ref "R5") (pin "16") (pinfunction "2_16") (pintype "passive"))
      (node (ref "R5") (pin "9") (pinfunction "2_9") (pintype "passive"))
      (node (ref "SV1") (pin "1") (pinfunction "1_1") (pintype "passive"))
      (node (ref "SV1") (pin "10") (pinfunction "10_10") (pintype "passive"))
      (node (ref "SV1") (pin "11") (pinfunction "11_11") (pintype "passive"))
      (node (ref "SV1") (pin "12") (pinfunction "12_12") (pintype "passive"))
      (node (ref "SV1") (pin "2") (pinfunction "2_2") (pintype "passive"))
      (node (ref "SV1") (pin "3") (pinfunction "3_3") (pintype "passive"))
      (node (ref "SV1") (pin "4") (pinfunction "4_4") (pintype "passive"))
      (node (ref "SV1") (pin "5") (pinfunction "5_5") (pintype "passive"))
      (node (ref "SV1") (pin "6") (pinfunction "6_6") (pintype "passive"))
      (node (ref "SV1") (pin "7") (pinfunction "7_7") (pintype "passive"))
      (node (ref "SV1") (pin "8") (pinfunction "8_8") (pintype "passive"))
      (node (ref "SV1") (pin "9") (pinfunction "9_9") (pintype "passive"))
      (node (ref "SV11") (pin "1") (pinfunction "1_1") (pintype "passive"))
      (node (ref "SV11") (pin "10") (pinfunction "10_10") (pintype "passive"))
      (node (ref "SV11") (pin "11") (pinfunction "11_11") (pintype "passive"))
      (node (ref "SV11") (pin "12") (pinfunction "12_12") (pintype "passive"))
      (node (ref "SV11") (pin "2") (pinfunction "2_2") (pintype "passive"))
      (node (ref "SV11") (pin "3") (pinfunction "3_3") (pintype "passive"))
      (node (ref "SV11") (pin "4") (pinfunction "4_4") (pintype "passive"))
      (node (ref "SV11") (pin "5") (pinfunction "5_5") (pintype "passive"))
      (node (ref "SV11") (pin "6") (pinfunction "6_6") (pintype "passive"))
      (node (ref "SV11") (pin "7") (pinfunction "7_7") (pintype "passive"))
      (node (ref "SV11") (pin "8") (pinfunction "8_8") (pintype "passive"))
      (node (ref "SV11") (pin "9") (pinfunction "9_9") (pintype "passive"))
      (node (ref "SV13") (pin "1") (pinfunction "1_1") (pintype "passive"))
      (node (ref "SV13") (pin "10") (pinfunction "10_10") (pintype "passive"))
      (node (ref "SV13") (pin "11") (pinfunction "11_11") (pintype "passive"))
      (node (ref "SV13") (pin "12") (pinfunction "12_12") (pintype "passive"))
      (node (ref "SV13") (pin "2") (pinfunction "2_2") (pintype "passive"))
      (node (ref "SV13") (pin "3") (pinfunction "3_3") (pintype "passive"))
      (node (ref "SV13") (pin "4") (pinfunction "4_4") (pintype "passive"))
      (node (ref "SV13") (pin "5") (pinfunction "5_5") (pintype "passive"))
      (node (ref "SV13") (pin "6") (pinfunction "6_6") (pintype "passive"))
      (node (ref "SV13") (pin "7") (pinfunction "7_7") (pintype "passive"))
      (node (ref "SV13") (pin "8") (pinfunction "8_8") (pintype "passive"))
      (node (ref "SV13") (pin "9") (pinfunction "9_9") (pintype "passive"))
      (node (ref "SV15") (pin "1") (pinfunction "1_1") (pintype "passive"))
      (node (ref "SV15") (pin "10") (pinfunction "10_10") (pintype "passive"))
      (node (ref "SV15") (pin "11") (pinfunction "11_11") (pintype "passive"))
      (node (ref "SV15") (pin "12") (pinfunction "12_12") (pintype "passive"))
      (node (ref "SV15") (pin "2") (pinfunction "2_2") (pintype "passive"))
      (node (ref "SV15") (pin "3") (pinfunction "3_3") (pintype "passive"))
      (node (ref "SV15") (pin "4") (pinfunction "4_4") (pintype "passive"))
      (node (ref "SV15") (pin "5") (pinfunction "5_5") (pintype "passive"))
      (node (ref "SV15") (pin "6") (pinfunction "6_6") (pintype "passive"))
      (node (ref "SV15") (pin "7") (pinfunction "7_7") (pintype "passive"))
      (node (ref "SV15") (pin "8") (pinfunction "8_8") (pintype "passive"))
      (node (ref "SV15") (pin "9") (pinfunction "9_9") (pintype "passive"))
      (node (ref "SV17") (pin "1") (pinfunction "1_1") (pintype "passive"))
      (node (ref "SV17") (pin "10") (pinfunction "10_10") (pintype "passive"))
      (node (ref "SV17") (pin "11") (pinfunction "11_11") (pintype "passive"))
      (node (ref "SV17") (pin "12") (pinfunction "12_12") (pintype "passive"))
      (node (ref "SV17") (pin "2") (pinfunction "2_2") (pintype "passive"))
      (node (ref "SV17") (pin "3") (pinfunction "3_3") (pintype "passive"))
      (node (ref "SV17") (pin "4") (pinfunction "4_4") (pintype "passive"))
      (node (ref "SV17") (pin "5") (pinfunction "5_5") (pintype "passive"))
      (node (ref "SV17") (pin "6") (pinfunction "6_6") (pintype "passive"))
      (node (ref "SV17") (pin "7") (pinfunction "7_7") (pintype "passive"))
      (node (ref "SV17") (pin "8") (pinfunction "8_8") (pintype "passive"))
      (node (ref "SV17") (pin "9") (pinfunction "9_9") (pintype "passive"))
      (node (ref "SV183") (pin "1") (pinfunction "1_1") (pintype "passive"))
      (node (ref "SV183") (pin "10") (pinfunction "10_10") (pintype "passive"))
      (node (ref "SV183") (pin "11") (pinfunction "11_11") (pintype "passive"))
      (node (ref "SV183") (pin "12") (pinfunction "12_12") (pintype "passive"))
      (node (ref "SV183") (pin "2") (pinfunction "2_2") (pintype "passive"))
      (node (ref "SV183") (pin "3") (pinfunction "3_3") (pintype "passive"))
      (node (ref "SV183") (pin "4") (pinfunction "4_4") (pintype "passive"))
      (node (ref "SV183") (pin "5") (pinfunction "5_5") (pintype "passive"))
      (node (ref "SV183") (pin "6") (pinfunction "6_6") (pintype "passive"))
      (node (ref "SV183") (pin "7") (pinfunction "7_7") (pintype "passive"))
      (node (ref "SV183") (pin "8") (pinfunction "8_8") (pintype "passive"))
      (node (ref "SV183") (pin "9") (pinfunction "9_9") (pintype "passive"))
      (node (ref "SV185") (pin "1") (pinfunction "1_1") (pintype "passive"))
      (node (ref "SV185") (pin "10") (pinfunction "10_10") (pintype "passive"))
      (node (ref "SV185") (pin "11") (pinfunction "11_11") (pintype "passive"))
      (node (ref "SV185") (pin "12") (pinfunction "12_12") (pintype "passive"))
      (node (ref "SV185") (pin "2") (pinfunction "2_2") (pintype "passive"))
      (node (ref "SV185") (pin "3") (pinfunction "3_3") (pintype "passive"))
      (node (ref "SV185") (pin "4") (pinfunction "4_4") (pintype "passive"))
      (node (ref "SV185") (pin "5") (pinfunction "5_5") (pintype "passive"))
      (node (ref "SV185") (pin "6") (pinfunction "6_6") (pintype "passive"))
      (node (ref "SV185") (pin "7") (pinfunction "7_7") (pintype "passive"))
      (node (ref "SV185") (pin "8") (pinfunction "8_8") (pintype "passive"))
      (node (ref "SV185") (pin "9") (pinfunction "9_9") (pintype "passive"))
      (node (ref "SV187") (pin "1") (pinfunction "1_1") (pintype "passive"))
      (node (ref "SV187") (pin "10") (pinfunction "10_10") (pintype "passive"))
      (node (ref "SV187") (pin "11") (pinfunction "11_11") (pintype "passive"))
      (node (ref "SV187") (pin "12") (pinfunction "12_12") (pintype "passive"))
      (node (ref "SV187") (pin "2") (pinfunction "2_2") (pintype "passive"))
      (node (ref "SV187") (pin "3") (pinfunction "3_3") (pintype "passive"))
      (node (ref "SV187") (pin "4") (pinfunction "4_4") (pintype "passive"))
      (node (ref "SV187") (pin "5") (pinfunction "5_5") (pintype "passive"))
      (node (ref "SV187") (pin "6") (pinfunction "6_6") (pintype "passive"))
      (node (ref "SV187") (pin "7") (pinfunction "7_7") (pintype "passive"))
      (node (ref "SV187") (pin "8") (pinfunction "8_8") (pintype "passive"))
      (node (ref "SV187") (pin "9") (pinfunction "9_9") (pintype "passive"))
      (node (ref "SV189") (pin "1") (pinfunction "1_1") (pintype "passive"))
      (node (ref "SV189") (pin "10") (pinfunction "10_10") (pintype "passive"))
      (node (ref "SV189") (pin "11") (pinfunction "11_11") (pintype "passive"))
      (node (ref "SV189") (pin "12") (pinfunction "12_12") (pintype "passive"))
      (node (ref "SV189") (pin "2") (pinfunction "2_2") (pintype "passive"))
      (node (ref "SV189") (pin "3") (pinfunction "3_3") (pintype "passive"))
      (node (ref "SV189") (pin "4") (pinfunction "4_4") (pintype "passive"))
      (node (ref "SV189") (pin "5") (pinfunction "5_5") (pintype "passive"))
      (node (ref "SV189") (pin "6") (pinfunction "6_6") (pintype "passive"))
      (node (ref "SV189") (pin "7") (pinfunction "7_7") (pintype "passive"))
      (node (ref "SV189") (pin "8") (pinfunction "8_8") (pintype "passive"))
      (node (ref "SV189") (pin "9") (pinfunction "9_9") (pintype "passive"))
      (node (ref "SV19") (pin "1") (pinfunction "1_1") (pintype "passive"))
      (node (ref "SV19") (pin "10") (pinfunction "10_10") (pintype "passive"))
      (node (ref "SV19") (pin "11") (pinfunction "11_11") (pintype "passive"))
      (node (ref "SV19") (pin "12") (pinfunction "12_12") (pintype "passive"))
      (node (ref "SV19") (pin "2") (pinfunction "2_2") (pintype "passive"))
      (node (ref "SV19") (pin "3") (pinfunction "3_3") (pintype "passive"))
      (node (ref "SV19") (pin "4") (pinfunction "4_4") (pintype "passive"))
      (node (ref "SV19") (pin "5") (pinfunction "5_5") (pintype "passive"))
      (node (ref "SV19") (pin "6") (pinfunction "6_6") (pintype "passive"))
      (node (ref "SV19") (pin "7") (pinfunction "7_7") (pintype "passive"))
      (node (ref "SV19") (pin "8") (pinfunction "8_8") (pintype "passive"))
      (node (ref "SV19") (pin "9") (pinfunction "9_9") (pintype "passive"))
      (node (ref "SV191") (pin "1") (pinfunction "1_1") (pintype "passive"))
      (node (ref "SV191") (pin "10") (pinfunction "10_10") (pintype "passive"))
      (node (ref "SV191") (pin "11") (pinfunction "11_11") (pintype "passive"))
      (node (ref "SV191") (pin "12") (pinfunction "12_12") (pintype "passive"))
      (node (ref "SV191") (pin "2") (pinfunction "2_2") (pintype "passive"))
      (node (ref "SV191") (pin "3") (pinfunction "3_3") (pintype "passive"))
      (node (ref "SV191") (pin "4") (pinfunction "4_4") (pintype "passive"))
      (node (ref "SV191") (pin "5") (pinfunction "5_5") (pintype "passive"))
      (node (ref "SV191") (pin "6") (pinfunction "6_6") (pintype "passive"))
      (node (ref "SV191") (pin "7") (pinfunction "7_7") (pintype "passive"))
      (node (ref "SV191") (pin "8") (pinfunction "8_8") (pintype "passive"))
      (node (ref "SV191") (pin "9") (pinfunction "9_9") (pintype "passive"))
      (node (ref "SV21") (pin "1") (pinfunction "1_1") (pintype "passive"))
      (node (ref "SV21") (pin "10") (pinfunction "10_10") (pintype "passive"))
      (node (ref "SV21") (pin "11") (pinfunction "11_11") (pintype "passive"))
      (node (ref "SV21") (pin "12") (pinfunction "12_12") (pintype "passive"))
      (node (ref "SV21") (pin "2") (pinfunction "2_2") (pintype "passive"))
      (node (ref "SV21") (pin "3") (pinfunction "3_3") (pintype "passive"))
      (node (ref "SV21") (pin "4") (pinfunction "4_4") (pintype "passive"))
      (node (ref "SV21") (pin "5") (pinfunction "5_5") (pintype "passive"))
      (node (ref "SV21") (pin "6") (pinfunction "6_6") (pintype "passive"))
      (node (ref "SV21") (pin "7") (pinfunction "7_7") (pintype "passive"))
      (node (ref "SV21") (pin "8") (pinfunction "8_8") (pintype "passive"))
      (node (ref "SV21") (pin "9") (pinfunction "9_9") (pintype "passive"))
      (node (ref "SV23") (pin "1") (pinfunction "1_1") (pintype "passive"))
      (node (ref "SV23") (pin "10") (pinfunction "10_10") (pintype "passive"))
      (node (ref "SV23") (pin "11") (pinfunction "11_11") (pintype "passive"))
      (node (ref "SV23") (pin "12") (pinfunction "12_12") (pintype "passive"))
      (node (ref "SV23") (pin "2") (pinfunction "2_2") (pintype "passive"))
      (node (ref "SV23") (pin "3") (pinfunction "3_3") (pintype "passive"))
      (node (ref "SV23") (pin "4") (pinfunction "4_4") (pintype "passive"))
      (node (ref "SV23") (pin "5") (pinfunction "5_5") (pintype "passive"))
      (node (ref "SV23") (pin "6") (pinfunction "6_6") (pintype "passive"))
      (node (ref "SV23") (pin "7") (pinfunction "7_7") (pintype "passive"))
      (node (ref "SV23") (pin "8") (pinfunction "8_8") (pintype "passive"))
      (node (ref "SV23") (pin "9") (pinfunction "9_9") (pintype "passive"))
      (node (ref "SV25") (pin "1") (pinfunction "1_1") (pintype "passive"))
      (node (ref "SV25") (pin "10") (pinfunction "10_10") (pintype "passive"))
      (node (ref "SV25") (pin "11") (pinfunction "11_11") (pintype "passive"))
      (node (ref "SV25") (pin "12") (pinfunction "12_12") (pintype "passive"))
      (node (ref "SV25") (pin "2") (pinfunction "2_2") (pintype "passive"))
      (node (ref "SV25") (pin "3") (pinfunction "3_3") (pintype "passive"))
      (node (ref "SV25") (pin "4") (pinfunction "4_4") (pintype "passive"))
      (node (ref "SV25") (pin "5") (pinfunction "5_5") (pintype "passive"))
      (node (ref "SV25") (pin "6") (pinfunction "6_6") (pintype "passive"))
      (node (ref "SV25") (pin "7") (pinfunction "7_7") (pintype "passive"))
      (node (ref "SV25") (pin "8") (pinfunction "8_8") (pintype "passive"))
      (node (ref "SV25") (pin "9") (pinfunction "9_9") (pintype "passive"))
      (node (ref "SV27") (pin "1") (pinfunction "1_1") (pintype "passive"))
      (node (ref "SV27") (pin "10") (pinfunction "10_10") (pintype "passive"))
      (node (ref "SV27") (pin "11") (pinfunction "11_11") (pintype "passive"))
      (node (ref "SV27") (pin "12") (pinfunction "12_12") (pintype "passive"))
      (node (ref "SV27") (pin "2") (pinfunction "2_2") (pintype "passive"))
      (node (ref "SV27") (pin "3") (pinfunction "3_3") (pintype "passive"))
      (node (ref "SV27") (pin "4") (pinfunction "4_4") (pintype "passive"))
      (node (ref "SV27") (pin "5") (pinfunction "5_5") (pintype "passive"))
      (node (ref "SV27") (pin "6") (pinfunction "6_6") (pintype "passive"))
      (node (ref "SV27") (pin "7") (pinfunction "7_7") (pintype "passive"))
      (node (ref "SV27") (pin "8") (pinfunction "8_8") (pintype "passive"))
      (node (ref "SV27") (pin "9") (pinfunction "9_9") (pintype "passive"))
      (node (ref "SV29") (pin "1") (pinfunction "1_1") (pintype "passive"))
      (node (ref "SV29") (pin "10") (pinfunction "10_10") (pintype "passive"))
      (node (ref "SV29") (pin "11") (pinfunction "11_11") (pintype "passive"))
      (node (ref "SV29") (pin "12") (pinfunction "12_12") (pintype "passive"))
      (node (ref "SV29") (pin "2") (pinfunction "2_2") (pintype "passive"))
      (node (ref "SV29") (pin "3") (pinfunction "3_3") (pintype "passive"))
      (node (ref "SV29") (pin "4") (pinfunction "4_4") (pintype "passive"))
      (node (ref "SV29") (pin "5") (pinfunction "5_5") (pintype "passive"))
      (node (ref "SV29") (pin "6") (pinfunction "6_6") (pintype "passive"))
      (node (ref "SV29") (pin "7") (pinfunction "7_7") (pintype "passive"))
      (node (ref "SV29") (pin "8") (pinfunction "8_8") (pintype "passive"))
      (node (ref "SV29") (pin "9") (pinfunction "9_9") (pintype "passive"))
      (node (ref "SV3") (pin "1") (pinfunction "1_1") (pintype "passive"))
      (node (ref "SV3") (pin "10") (pinfunction "10_10") (pintype "passive"))
      (node (ref "SV3") (pin "11") (pinfunction "11_11") (pintype "passive"))
      (node (ref "SV3") (pin "12") (pinfunction "12_12") (pintype "passive"))
      (node (ref "SV3") (pin "2") (pinfunction "2_2") (pintype "passive"))
      (node (ref "SV3") (pin "3") (pinfunction "3_3") (pintype "passive"))
      (node (ref "SV3") (pin "4") (pinfunction "4_4") (pintype "passive"))
      (node (ref "SV3") (pin "5") (pinfunction "5_5") (pintype "passive"))
      (node (ref "SV3") (pin "6") (pinfunction "6_6") (pintype "passive"))
      (node (ref "SV3") (pin "7") (pinfunction "7_7") (pintype "passive"))
      (node (ref "SV3") (pin "8") (pinfunction "8_8") (pintype "passive"))
      (node (ref "SV3") (pin "9") (pinfunction "9_9") (pintype "passive"))
      (node (ref "SV31") (pin "1") (pinfunction "1_1") (pintype "passive"))
      (node (ref "SV31") (pin "10") (pinfunction "10_10") (pintype "passive"))
      (node (ref "SV31") (pin "11") (pinfunction "11_11") (pintype "passive"))
      (node (ref "SV31") (pin "12") (pinfunction "12_12") (pintype "passive"))
      (node (ref "SV31") (pin "2") (pinfunction "2_2") (pintype "passive"))
      (node (ref "SV31") (pin "3") (pinfunction "3_3") (pintype "passive"))
      (node (ref "SV31") (pin "4") (pinfunction "4_4") (pintype "passive"))
      (node (ref "SV31") (pin "5") (pinfunction "5_5") (pintype "passive"))
      (node (ref "SV31") (pin "6") (pinfunction "6_6") (pintype "passive"))
      (node (ref "SV31") (pin "7") (pinfunction "7_7") (pintype "passive"))
      (node (ref "SV31") (pin "8") (pinfunction "8_8") (pintype "passive"))
      (node (ref "SV31") (pin "9") (pinfunction "9_9") (pintype "passive"))
      (node (ref "SV33") (pin "1") (pinfunction "1_1") (pintype "passive"))
      (node (ref "SV33") (pin "10") (pinfunction "10_10") (pintype "passive"))
      (node (ref "SV33") (pin "11") (pinfunction "11_11") (pintype "passive"))
      (node (ref "SV33") (pin "12") (pinfunction "12_12") (pintype "passive"))
      (node (ref "SV33") (pin "2") (pinfunction "2_2") (pintype "passive"))
      (node (ref "SV33") (pin "3") (pinfunction "3_3") (pintype "passive"))
      (node (ref "SV33") (pin "4") (pinfunction "4_4") (pintype "passive"))
      (node (ref "SV33") (pin "5") (pinfunction "5_5") (pintype "passive"))
      (node (ref "SV33") (pin "6") (pinfunction "6_6") (pintype "passive"))
      (node (ref "SV33") (pin "7") (pinfunction "7_7") (pintype "passive"))
      (node (ref "SV33") (pin "8") (pinfunction "8_8") (pintype "passive"))
      (node (ref "SV33") (pin "9") (pinfunction "9_9") (pintype "passive"))
      (node (ref "SV35") (pin "1") (pinfunction "1_1") (pintype "passive"))
      (node (ref "SV35") (pin "10") (pinfunction "10_10") (pintype "passive"))
      (node (ref "SV35") (pin "11") (pinfunction "11_11") (pintype "passive"))
      (node (ref "SV35") (pin "12") (pinfunction "12_12") (pintype "passive"))
      (node (ref "SV35") (pin "2") (pinfunction "2_2") (pintype "passive"))
      (node (ref "SV35") (pin "3") (pinfunction "3_3") (pintype "passive"))
      (node (ref "SV35") (pin "4") (pinfunction "4_4") (pintype "passive"))
      (node (ref "SV35") (pin "5") (pinfunction "5_5") (pintype "passive"))
      (node (ref "SV35") (pin "6") (pinfunction "6_6") (pintype "passive"))
      (node (ref "SV35") (pin "7") (pinfunction "7_7") (pintype "passive"))
      (node (ref "SV35") (pin "8") (pinfunction "8_8") (pintype "passive"))
      (node (ref "SV35") (pin "9") (pinfunction "9_9") (pintype "passive"))
      (node (ref "SV37") (pin "1") (pinfunction "1_1") (pintype "passive"))
      (node (ref "SV37") (pin "10") (pinfunction "10_10") (pintype "passive"))
      (node (ref "SV37") (pin "11") (pinfunction "11_11") (pintype "passive"))
      (node (ref "SV37") (pin "12") (pinfunction "12_12") (pintype "passive"))
      (node (ref "SV37") (pin "2") (pinfunction "2_2") (pintype "passive"))
      (node (ref "SV37") (pin "3") (pinfunction "3_3") (pintype "passive"))
      (node (ref "SV37") (pin "4") (pinfunction "4_4") (pintype "passive"))
      (node (ref "SV37") (pin "5") (pinfunction "5_5") (pintype "passive"))
      (node (ref "SV37") (pin "6") (pinfunction "6_6") (pintype "passive"))
      (node (ref "SV37") (pin "7") (pinfunction "7_7") (pintype "passive"))
      (node (ref "SV37") (pin "8") (pinfunction "8_8") (pintype "passive"))
      (node (ref "SV37") (pin "9") (pinfunction "9_9") (pintype "passive"))
      (node (ref "SV39") (pin "1") (pinfunction "1_1") (pintype "passive"))
      (node (ref "SV39") (pin "10") (pinfunction "10_10") (pintype "passive"))
      (node (ref "SV39") (pin "11") (pinfunction "11_11") (pintype "passive"))
      (node (ref "SV39") (pin "12") (pinfunction "12_12") (pintype "passive"))
      (node (ref "SV39") (pin "2") (pinfunction "2_2") (pintype "passive"))
      (node (ref "SV39") (pin "3") (pinfunction "3_3") (pintype "passive"))
      (node (ref "SV39") (pin "4") (pinfunction "4_4") (pintype "passive"))
      (node (ref "SV39") (pin "5") (pinfunction "5_5") (pintype "passive"))
      (node (ref "SV39") (pin "6") (pinfunction "6_6") (pintype "passive"))
      (node (ref "SV39") (pin "7") (pinfunction "7_7") (pintype "passive"))
      (node (ref "SV39") (pin "8") (pinfunction "8_8") (pintype "passive"))
      (node (ref "SV39") (pin "9") (pinfunction "9_9") (pintype "passive"))
      (node (ref "SV41") (pin "1") (pinfunction "1_1") (pintype "passive"))
      (node (ref "SV41") (pin "10") (pinfunction "10_10") (pintype "passive"))
      (node (ref "SV41") (pin "11") (pinfunction "11_11") (pintype "passive"))
      (node (ref "SV41") (pin "12") (pinfunction "12_12") (pintype "passive"))
      (node (ref "SV41") (pin "2") (pinfunction "2_2") (pintype "passive"))
      (node (ref "SV41") (pin "3") (pinfunction "3_3") (pintype "passive"))
      (node (ref "SV41") (pin "4") (pinfunction "4_4") (pintype "passive"))
      (node (ref "SV41") (pin "5") (pinfunction "5_5") (pintype "passive"))
      (node (ref "SV41") (pin "6") (pinfunction "6_6") (pintype "passive"))
      (node (ref "SV41") (pin "7") (pinfunction "7_7") (pintype "passive"))
      (node (ref "SV41") (pin "8") (pinfunction "8_8") (pintype "passive"))
      (node (ref "SV41") (pin "9") (pinfunction "9_9") (pintype "passive"))
      (node (ref "SV43") (pin "1") (pinfunction "1_1") (pintype "passive"))
      (node (ref "SV43") (pin "10") (pinfunction "10_10") (pintype "passive"))
      (node (ref "SV43") (pin "11") (pinfunction "11_11") (pintype "passive"))
      (node (ref "SV43") (pin "12") (pinfunction "12_12") (pintype "passive"))
      (node (ref "SV43") (pin "2") (pinfunction "2_2") (pintype "passive"))
      (node (ref "SV43") (pin "3") (pinfunction "3_3") (pintype "passive"))
      (node (ref "SV43") (pin "4") (pinfunction "4_4") (pintype "passive"))
      (node (ref "SV43") (pin "5") (pinfunction "5_5") (pintype "passive"))
      (node (ref "SV43") (pin "6") (pinfunction "6_6") (pintype "passive"))
      (node (ref "SV43") (pin "7") (pinfunction "7_7") (pintype "passive"))
      (node (ref "SV43") (pin "8") (pinfunction "8_8") (pintype "passive"))
      (node (ref "SV43") (pin "9") (pinfunction "9_9") (pintype "passive"))
      (node (ref "SV45") (pin "1") (pinfunction "1_1") (pintype "passive"))
      (node (ref "SV45") (pin "10") (pinfunction "10_10") (pintype "passive"))
      (node (ref "SV45") (pin "11") (pinfunction "11_11") (pintype "passive"))
      (node (ref "SV45") (pin "12") (pinfunction "12_12") (pintype "passive"))
      (node (ref "SV45") (pin "2") (pinfunction "2_2") (pintype "passive"))
      (node (ref "SV45") (pin "3") (pinfunction "3_3") (pintype "passive"))
      (node (ref "SV45") (pin "4") (pinfunction "4_4") (pintype "passive"))
      (node (ref "SV45") (pin "5") (pinfunction "5_5") (pintype "passive"))
      (node (ref "SV45") (pin "6") (pinfunction "6_6") (pintype "passive"))
      (node (ref "SV45") (pin "7") (pinfunction "7_7") (pintype "passive"))
      (node (ref "SV45") (pin "8") (pinfunction "8_8") (pintype "passive"))
      (node (ref "SV45") (pin "9") (pinfunction "9_9") (pintype "passive"))
      (node (ref "SV47") (pin "1") (pinfunction "1_1") (pintype "passive"))
      (node (ref "SV47") (pin "10") (pinfunction "10_10") (pintype "passive"))
      (node (ref "SV47") (pin "11") (pinfunction "11_11") (pintype "passive"))
      (node (ref "SV47") (pin "12") (pinfunction "12_12") (pintype "passive"))
      (node (ref "SV47") (pin "2") (pinfunction "2_2") (pintype "passive"))
      (node (ref "SV47") (pin "3") (pinfunction "3_3") (pintype "passive"))
      (node (ref "SV47") (pin "4") (pinfunction "4_4") (pintype "passive"))
      (node (ref "SV47") (pin "5") (pinfunction "5_5") (pintype "passive"))
      (node (ref "SV47") (pin "6") (pinfunction "6_6") (pintype "passive"))
      (node (ref "SV47") (pin "7") (pinfunction "7_7") (pintype "passive"))
      (node (ref "SV47") (pin "8") (pinfunction "8_8") (pintype "passive"))
      (node (ref "SV47") (pin "9") (pinfunction "9_9") (pintype "passive"))
      (node (ref "SV49") (pin "1") (pinfunction "1_1") (pintype "passive"))
      (node (ref "SV49") (pin "10") (pinfunction "10_10") (pintype "passive"))
      (node (ref "SV49") (pin "11") (pinfunction "11_11") (pintype "passive"))
      (node (ref "SV49") (pin "12") (pinfunction "12_12") (pintype "passive"))
      (node (ref "SV49") (pin "2") (pinfunction "2_2") (pintype "passive"))
      (node (ref "SV49") (pin "3") (pinfunction "3_3") (pintype "passive"))
      (node (ref "SV49") (pin "4") (pinfunction "4_4") (pintype "passive"))
      (node (ref "SV49") (pin "5") (pinfunction "5_5") (pintype "passive"))
      (node (ref "SV49") (pin "6") (pinfunction "6_6") (pintype "passive"))
      (node (ref "SV49") (pin "7") (pinfunction "7_7") (pintype "passive"))
      (node (ref "SV49") (pin "8") (pinfunction "8_8") (pintype "passive"))
      (node (ref "SV49") (pin "9") (pinfunction "9_9") (pintype "passive"))
      (node (ref "SV5") (pin "1") (pinfunction "1_1") (pintype "passive"))
      (node (ref "SV5") (pin "10") (pinfunction "10_10") (pintype "passive"))
      (node (ref "SV5") (pin "11") (pinfunction "11_11") (pintype "passive"))
      (node (ref "SV5") (pin "12") (pinfunction "12_12") (pintype "passive"))
      (node (ref "SV5") (pin "2") (pinfunction "2_2") (pintype "passive"))
      (node (ref "SV5") (pin "3") (pinfunction "3_3") (pintype "passive"))
      (node (ref "SV5") (pin "4") (pinfunction "4_4") (pintype "passive"))
      (node (ref "SV5") (pin "5") (pinfunction "5_5") (pintype "passive"))
      (node (ref "SV5") (pin "6") (pinfunction "6_6") (pintype "passive"))
      (node (ref "SV5") (pin "7") (pinfunction "7_7") (pintype "passive"))
      (node (ref "SV5") (pin "8") (pinfunction "8_8") (pintype "passive"))
      (node (ref "SV5") (pin "9") (pinfunction "9_9") (pintype "passive"))
      (node (ref "SV51") (pin "1") (pinfunction "1_1") (pintype "passive"))
      (node (ref "SV51") (pin "10") (pinfunction "10_10") (pintype "passive"))
      (node (ref "SV51") (pin "11") (pinfunction "11_11") (pintype "passive"))
      (node (ref "SV51") (pin "12") (pinfunction "12_12") (pintype "passive"))
      (node (ref "SV51") (pin "2") (pinfunction "2_2") (pintype "passive"))
      (node (ref "SV51") (pin "3") (pinfunction "3_3") (pintype "passive"))
      (node (ref "SV51") (pin "4") (pinfunction "4_4") (pintype "passive"))
      (node (ref "SV51") (pin "5") (pinfunction "5_5") (pintype "passive"))
      (node (ref "SV51") (pin "6") (pinfunction "6_6") (pintype "passive"))
      (node (ref "SV51") (pin "7") (pinfunction "7_7") (pintype "passive"))
      (node (ref "SV51") (pin "8") (pinfunction "8_8") (pintype "passive"))
      (node (ref "SV51") (pin "9") (pinfunction "9_9") (pintype "passive"))
      (node (ref "SV53") (pin "1") (pinfunction "1_1") (pintype "passive"))
      (node (ref "SV53") (pin "10") (pinfunction "10_10") (pintype "passive"))
      (node (ref "SV53") (pin "11") (pinfunction "11_11") (pintype "passive"))
      (node (ref "SV53") (pin "12") (pinfunction "12_12") (pintype "passive"))
      (node (ref "SV53") (pin "2") (pinfunction "2_2") (pintype "passive"))
      (node (ref "SV53") (pin "3") (pinfunction "3_3") (pintype "passive"))
      (node (ref "SV53") (pin "4") (pinfunction "4_4") (pintype "passive"))
      (node (ref "SV53") (pin "5") (pinfunction "5_5") (pintype "passive"))
      (node (ref "SV53") (pin "6") (pinfunction "6_6") (pintype "passive"))
      (node (ref "SV53") (pin "7") (pinfunction "7_7") (pintype "passive"))
      (node (ref "SV53") (pin "8") (pinfunction "8_8") (pintype "passive"))
      (node (ref "SV53") (pin "9") (pinfunction "9_9") (pintype "passive"))
      (node (ref "SV55") (pin "1") (pinfunction "1_1") (pintype "passive"))
      (node (ref "SV55") (pin "10") (pinfunction "10_10") (pintype "passive"))
      (node (ref "SV55") (pin "11") (pinfunction "11_11") (pintype "passive"))
      (node (ref "SV55") (pin "12") (pinfunction "12_12") (pintype "passive"))
      (node (ref "SV55") (pin "2") (pinfunction "2_2") (pintype "passive"))
      (node (ref "SV55") (pin "3") (pinfunction "3_3") (pintype "passive"))
      (node (ref "SV55") (pin "4") (pinfunction "4_4") (pintype "passive"))
      (node (ref "SV55") (pin "5") (pinfunction "5_5") (pintype "passive"))
      (node (ref "SV55") (pin "6") (pinfunction "6_6") (pintype "passive"))
      (node (ref "SV55") (pin "7") (pinfunction "7_7") (pintype "passive"))
      (node (ref "SV55") (pin "8") (pinfunction "8_8") (pintype "passive"))
      (node (ref "SV55") (pin "9") (pinfunction "9_9") (pintype "passive"))
      (node (ref "SV57") (pin "1") (pinfunction "1_1") (pintype "passive"))
      (node (ref "SV57") (pin "10") (pinfunction "10_10") (pintype "passive"))
      (node (ref "SV57") (pin "11") (pinfunction "11_11") (pintype "passive"))
      (node (ref "SV57") (pin "12") (pinfunction "12_12") (pintype "passive"))
      (node (ref "SV57") (pin "2") (pinfunction "2_2") (pintype "passive"))
      (node (ref "SV57") (pin "3") (pinfunction "3_3") (pintype "passive"))
      (node (ref "SV57") (pin "4") (pinfunction "4_4") (pintype "passive"))
      (node (ref "SV57") (pin "5") (pinfunction "5_5") (pintype "passive"))
      (node (ref "SV57") (pin "6") (pinfunction "6_6") (pintype "passive"))
      (node (ref "SV57") (pin "7") (pinfunction "7_7") (pintype "passive"))
      (node (ref "SV57") (pin "8") (pinfunction "8_8") (pintype "passive"))
      (node (ref "SV57") (pin "9") (pinfunction "9_9") (pintype "passive"))
      (node (ref "SV59") (pin "1") (pinfunction "1_1") (pintype "passive"))
      (node (ref "SV59") (pin "10") (pinfunction "10_10") (pintype "passive"))
      (node (ref "SV59") (pin "11") (pinfunction "11_11") (pintype "passive"))
      (node (ref "SV59") (pin "12") (pinfunction "12_12") (pintype "passive"))
      (node (ref "SV59") (pin "2") (pinfunction "2_2") (pintype "passive"))
      (node (ref "SV59") (pin "3") (pinfunction "3_3") (pintype "passive"))
      (node (ref "SV59") (pin "4") (pinfunction "4_4") (pintype "passive"))
      (node (ref "SV59") (pin "5") (pinfunction "5_5") (pintype "passive"))
      (node (ref "SV59") (pin "6") (pinfunction "6_6") (pintype "passive"))
      (node (ref "SV59") (pin "7") (pinfunction "7_7") (pintype "passive"))
      (node (ref "SV59") (pin "8") (pinfunction "8_8") (pintype "passive"))
      (node (ref "SV59") (pin "9") (pinfunction "9_9") (pintype "passive"))
      (node (ref "SV61") (pin "1") (pinfunction "1_1") (pintype "passive"))
      (node (ref "SV61") (pin "10") (pinfunction "10_10") (pintype "passive"))
      (node (ref "SV61") (pin "11") (pinfunction "11_11") (pintype "passive"))
      (node (ref "SV61") (pin "12") (pinfunction "12_12") (pintype "passive"))
      (node (ref "SV61") (pin "2") (pinfunction "2_2") (pintype "passive"))
      (node (ref "SV61") (pin "3") (pinfunction "3_3") (pintype "passive"))
      (node (ref "SV61") (pin "4") (pinfunction "4_4") (pintype "passive"))
      (node (ref "SV61") (pin "5") (pinfunction "5_5") (pintype "passive"))
      (node (ref "SV61") (pin "6") (pinfunction "6_6") (pintype "passive"))
      (node (ref "SV61") (pin "7") (pinfunction "7_7") (pintype "passive"))
      (node (ref "SV61") (pin "8") (pinfunction "8_8") (pintype "passive"))
      (node (ref "SV61") (pin "9") (pinfunction "9_9") (pintype "passive"))
      (node (ref "SV7") (pin "1") (pinfunction "1_1") (pintype "passive"))
      (node (ref "SV7") (pin "10") (pinfunction "10_10") (pintype "passive"))
      (node (ref "SV7") (pin "11") (pinfunction "11_11") (pintype "passive"))
      (node (ref "SV7") (pin "12") (pinfunction "12_12") (pintype "passive"))
      (node (ref "SV7") (pin "2") (pinfunction "2_2") (pintype "passive"))
      (node (ref "SV7") (pin "3") (pinfunction "3_3") (pintype "passive"))
      (node (ref "SV7") (pin "4") (pinfunction "4_4") (pintype "passive"))
      (node (ref "SV7") (pin "5") (pinfunction "5_5") (pintype "passive"))
      (node (ref "SV7") (pin "6") (pinfunction "6_6") (pintype "passive"))
      (node (ref "SV7") (pin "7") (pinfunction "7_7") (pintype "passive"))
      (node (ref "SV7") (pin "8") (pinfunction "8_8") (pintype "passive"))
      (node (ref "SV7") (pin "9") (pinfunction "9_9") (pintype "passive"))
      (node (ref "SV9") (pin "1") (pinfunction "1_1") (pintype "passive"))
      (node (ref "SV9") (pin "10") (pinfunction "10_10") (pintype "passive"))
      (node (ref "SV9") (pin "11") (pinfunction "11_11") (pintype "passive"))
      (node (ref "SV9") (pin "12") (pinfunction "12_12") (pintype "passive"))
      (node (ref "SV9") (pin "2") (pinfunction "2_2") (pintype "passive"))
      (node (ref "SV9") (pin "3") (pinfunction "3_3") (pintype "passive"))
      (node (ref "SV9") (pin "4") (pinfunction "4_4") (pintype "passive"))
      (node (ref "SV9") (pin "5") (pinfunction "5_5") (pintype "passive"))
      (node (ref "SV9") (pin "6") (pinfunction "6_6") (pintype "passive"))
      (node (ref "SV9") (pin "7") (pinfunction "7_7") (pintype "passive"))
      (node (ref "SV9") (pin "8") (pinfunction "8_8") (pintype "passive"))
      (node (ref "SV9") (pin "9") (pinfunction "9_9") (pintype "passive"))
      (node (ref "U$2") (pin "AA2") (pinfunction "1_AA2") (pintype "bidirectional"))
      (node (ref "U$2") (pin "BA2") (pinfunction "1_BA2") (pintype "bidirectional"))
      (node (ref "U$2") (pin "CA2") (pinfunction "1_CA2") (pintype "bidirectional"))
    )
    (net (code "938") (name "WRITE") (class "Default")
      (node (ref "D10") (pin "15") (pinfunction "15_15") (pintype "passive"))
      (node (ref "IC8") (pin "5") (pinfunction "I_5") (pintype "input"))
      (node (ref "U$2") (pin "AS2") (pinfunction "1_AS2") (pintype "bidirectional"))
    )
    (net (code "939") (name "WRITE_H") (class "Default")
      (node (ref "IC7") (pin "4") (pinfunction "I1_4") (pintype "input"))
      (node (ref "IC8") (pin "8") (pinfunction "O_8") (pintype "output"))
      (node (ref "IC9") (pin "12") (pinfunction "D_12") (pintype "input"))
    )
    (net (code "940") (name "WRITE_L") (class "Default")
      (node (ref "IC8") (pin "6") (pinfunction "O_6") (pintype "output"))
      (node (ref "IC8") (pin "9") (pinfunction "I_9") (pintype "input"))
    )
    (net (code "941") (name "unconnected-(IC9A-Q-Pad5)") (class "Default")
      (node (ref "IC9") (pin "5") (pinfunction "Q_5") (pintype "output"))
    )
    (net (code "942") (name "unconnected-(IC9B-~{Q}-Pad8)") (class "Default")
      (node (ref "IC9") (pin "8") (pinfunction "~{Q}_8") (pintype "output"))
    )
    (net (code "943") (name "~{BREAK_CYCLE}") (class "Default")
      (node (ref "D8") (pin "10") (pinfunction "10_10") (pintype "passive"))
      (node (ref "U$2") (pin "BL2") (pinfunction "1_BL2") (pintype "bidirectional"))
    )
    (net (code "944") (name "~{BRK_DATA_CONT}") (class "Default")
      (node (ref "D8") (pin "9") (pinfunction "9_9") (pintype "passive"))
      (node (ref "U$2") (pin "BK2") (pinfunction "1_BK2") (pintype "bidirectional"))
    )
    (net (code "945") (name "~{BRK_IN_PROG}") (class "Default")
      (node (ref "D8") (pin "5") (pinfunction "5_5") (pintype "passive"))
      (node (ref "U$2") (pin "BE2") (pinfunction "1_BE2") (pintype "bidirectional"))
    )
    (net (code "946") (name "~{BUS_STROBE}") (class "Default")
      (node (ref "D11") (pin "9") (pinfunction "9_9") (pintype "passive"))
      (node (ref "U$2") (pin "CK1") (pinfunction "1_CK1") (pintype "bidirectional"))
    )
    (net (code "947") (name "~{C0}") (class "Default")
      (node (ref "D11") (pin "5") (pinfunction "5_5") (pintype "passive"))
      (node (ref "U$2") (pin "CE1") (pinfunction "1_CE1") (pintype "bidirectional"))
    )
    (net (code "948") (name "~{C1}") (class "Default")
      (node (ref "D11") (pin "7") (pinfunction "7_7") (pintype "passive"))
      (node (ref "U$2") (pin "CH1") (pinfunction "1_CH1") (pintype "bidirectional"))
    )
    (net (code "949") (name "~{C2}") (class "Default")
      (node (ref "D11") (pin "8") (pinfunction "8_8") (pintype "passive"))
      (node (ref "U$2") (pin "CJ1") (pinfunction "1_CJ1") (pintype "bidirectional"))
    )
    (net (code "950") (name "~{CE}") (class "Default")
      (node (ref "C2") (pin "1") (pinfunction "1_1") (pintype "passive"))
      (node (ref "IC3") (pin "20") (pinfunction "~{CE}_20") (pintype "input"))
      (node (ref "IC4") (pin "20") (pinfunction "~{CE}_20") (pintype "input"))
      (node (ref "Q1") (pin "1") (pinfunction "C_1") (pintype "passive"))
      (node (ref "R7") (pin "1") (pinfunction "1_1") (pintype "passive"))
    )
    (net (code "951") (name "~{CPMA_DISABLE}") (class "Default")
      (node (ref "D11") (pin "17") (pinfunction "17_17") (pintype "passive"))
      (node (ref "U$2") (pin "CU1") (pinfunction "1_CU1") (pintype "bidirectional"))
    )
    (net (code "952") (name "~{DATA0}") (class "Default")
      (node (ref "D9") (pin "14") (pinfunction "14_14") (pintype "passive"))
      (node (ref "U$2") (pin "AR1") (pinfunction "1_AR1") (pintype "bidirectional"))
    )
    (net (code "953") (name "~{DATA1}") (class "Default")
      (node (ref "D9") (pin "15") (pinfunction "15_15") (pintype "passive"))
      (node (ref "U$2") (pin "AS1") (pinfunction "1_AS1") (pintype "bidirectional"))
    )
    (net (code "954") (name "~{DATA2}") (class "Default")
      (node (ref "D9") (pin "17") (pinfunction "17_17") (pintype "passive"))
      (node (ref "U$2") (pin "AU1") (pinfunction "1_AU1") (pintype "bidirectional"))
    )
    (net (code "955") (name "~{DATA3}") (class "Default")
      (node (ref "D9") (pin "18") (pinfunction "18_18") (pintype "passive"))
      (node (ref "U$2") (pin "AV1") (pinfunction "1_AV1") (pintype "bidirectional"))
    )
    (net (code "956") (name "~{DATA4}") (class "Default")
      (node (ref "D7") (pin "14") (pinfunction "14_14") (pintype "passive"))
      (node (ref "U$2") (pin "BR1") (pinfunction "1_BR1") (pintype "bidirectional"))
    )
    (net (code "957") (name "~{DATA5}") (class "Default")
      (node (ref "D7") (pin "15") (pinfunction "15_15") (pintype "passive"))
      (node (ref "U$2") (pin "BS1") (pinfunction "1_BS1") (pintype "bidirectional"))
    )
    (net (code "958") (name "~{DATA6}") (class "Default")
      (node (ref "D7") (pin "17") (pinfunction "17_17") (pintype "passive"))
      (node (ref "U$2") (pin "BU1") (pinfunction "1_BU1") (pintype "bidirectional"))
    )
    (net (code "959") (name "~{DATA7}") (class "Default")
      (node (ref "D7") (pin "18") (pinfunction "18_18") (pintype "passive"))
      (node (ref "U$2") (pin "BV1") (pinfunction "1_BV1") (pintype "bidirectional"))
    )
    (net (code "960") (name "~{DATA8}") (class "Default")
      (node (ref "D13") (pin "14") (pinfunction "14_14") (pintype "passive"))
      (node (ref "U$2") (pin "DR1") (pinfunction "1_DR1") (pintype "bidirectional"))
    )
    (net (code "961") (name "~{DATA9}") (class "Default")
      (node (ref "D13") (pin "15") (pinfunction "15_15") (pintype "passive"))
      (node (ref "U$2") (pin "DS1") (pinfunction "1_DS1") (pintype "bidirectional"))
    )
    (net (code "962") (name "~{DATA10}") (class "Default")
      (node (ref "D13") (pin "17") (pinfunction "17_17") (pintype "passive"))
      (node (ref "U$2") (pin "DU1") (pinfunction "1_DU1") (pintype "bidirectional"))
    )
    (net (code "963") (name "~{DATA11}") (class "Default")
      (node (ref "D13") (pin "18") (pinfunction "18_18") (pintype "passive"))
      (node (ref "U$2") (pin "DV1") (pinfunction "1_DV1") (pintype "bidirectional"))
    )
    (net (code "964") (name "~{DISABLE}") (class "Default")
      (node (ref "IC7") (pin "11") (pinfunction "I2_11") (pintype "input"))
      (node (ref "IC7") (pin "12") (pinfunction "O_12") (pintype "output"))
    )
    (net (code "965") (name "~{D}") (class "Default")
      (node (ref "D14") (pin "9") (pinfunction "9_9") (pintype "passive"))
      (node (ref "U$2") (pin "DK2") (pinfunction "1_DK2") (pintype "bidirectional"))
    )
    (net (code "966") (name "~{EMA0}") (class "Default")
      (node (ref "D10") (pin "4") (pinfunction "4_4") (pintype "passive"))
      (node (ref "IC3") (pin "8") (pinfunction "A2_8") (pintype "input"))
      (node (ref "IC4") (pin "8") (pinfunction "A2_8") (pintype "input"))
      (node (ref "IC5") (pin "3") (pinfunction "C_3") (pintype "input"))
      (node (ref "U$2") (pin "AD2") (pinfunction "1_AD2") (pintype "bidirectional"))
    )
    (net (code "967") (name "~{EMA1}") (class "Default")
      (node (ref "D10") (pin "5") (pinfunction "5_5") (pintype "passive"))
      (node (ref "IC3") (pin "9") (pinfunction "A1_9") (pintype "input"))
      (node (ref "IC4") (pin "9") (pinfunction "A1_9") (pintype "input"))
      (node (ref "IC5") (pin "2") (pinfunction "B_2") (pintype "input"))
      (node (ref "U$2") (pin "AE2") (pinfunction "1_AE2") (pintype "bidirectional"))
    )
    (net (code "968") (name "~{EMA2}") (class "Default")
      (node (ref "D10") (pin "7") (pinfunction "7_7") (pintype "passive"))
      (node (ref "IC3") (pin "10") (pinfunction "A0_10") (pintype "input"))
      (node (ref "IC4") (pin "10") (pinfunction "A0_10") (pintype "input"))
      (node (ref "IC5") (pin "1") (pinfunction "A_1") (pintype "input"))
      (node (ref "U$2") (pin "AH2") (pinfunction "1_AH2") (pintype "bidirectional"))
    )
    (net (code "969") (name "~{E}") (class "Default")
      (node (ref "D14") (pin "10") (pinfunction "10_10") (pintype "passive"))
      (node (ref "U$2") (pin "DL2") (pinfunction "1_DL2") (pintype "bidirectional"))
    )
    (net (code "970") (name "~{FSET}") (class "Default")
      (node (ref "D14") (pin "13") (pinfunction "13_13") (pintype "passive"))
      (node (ref "U$2") (pin "DP2") (pinfunction "1_DP2") (pintype "bidirectional"))
    )
    (net (code "971") (name "~{F}") (class "Default")
      (node (ref "D14") (pin "8") (pinfunction "8_8") (pintype "passive"))
      (node (ref "U$2") (pin "DJ2") (pinfunction "1_DJ2") (pintype "bidirectional"))
    )
    (net (code "972") (name "~{IND1}") (class "Default")
      (node (ref "D12") (pin "17") (pinfunction "17_17") (pintype "passive"))
      (node (ref "U$2") (pin "CU2") (pinfunction "1_CU2") (pintype "bidirectional"))
    )
    (net (code "973") (name "~{IND2}") (class "Default")
      (node (ref "D12") (pin "18") (pinfunction "18_18") (pintype "passive"))
      (node (ref "U$2") (pin "CV2") (pinfunction "1_CV2") (pintype "bidirectional"))
    )
    (net (code "974") (name "~{INTERNAL_IO}") (class "Default")
      (node (ref "D11") (pin "10") (pinfunction "10_10") (pintype "passive"))
      (node (ref "U$2") (pin "CL1") (pinfunction "1_CL1") (pintype "bidirectional"))
    )
    (net (code "975") (name "~{INT_RQST}") (class "Default")
      (node (ref "D11") (pin "13") (pinfunction "13_13") (pintype "passive"))
      (node (ref "U$2") (pin "CP1") (pinfunction "1_CP1") (pintype "bidirectional"))
    )
    (net (code "976") (name "~{IO_PAUSE}") (class "Default")
      (node (ref "D11") (pin "4") (pinfunction "4_4") (pintype "passive"))
      (node (ref "U$2") (pin "CD1") (pinfunction "1_CD1") (pintype "bidirectional"))
    )
    (net (code "977") (name "~{IR0}") (class "Default")
      (node (ref "D14") (pin "4") (pinfunction "4_4") (pintype "passive"))
      (node (ref "U$2") (pin "DD2") (pinfunction "1_DD2") (pintype "bidirectional"))
    )
    (net (code "978") (name "~{IR1}") (class "Default")
      (node (ref "D14") (pin "5") (pinfunction "5_5") (pintype "passive"))
      (node (ref "U$2") (pin "DE2") (pinfunction "1_DE2") (pintype "bidirectional"))
    )
    (net (code "979") (name "~{IR2}") (class "Default")
      (node (ref "D14") (pin "7") (pinfunction "7_7") (pintype "passive"))
      (node (ref "U$2") (pin "DH2") (pinfunction "1_DH2") (pintype "bidirectional"))
    )
    (net (code "980") (name "~{KEY_CONT}") (class "Default")
      (node (ref "D14") (pin "17") (pinfunction "17_17") (pintype "passive"))
      (node (ref "U$2") (pin "DU2") (pinfunction "1_DU2") (pintype "bidirectional"))
    )
    (net (code "981") (name "~{LA_ENABLE}") (class "Default")
      (node (ref "D8") (pin "11") (pinfunction "11_11") (pintype "passive"))
      (node (ref "U$2") (pin "BM2") (pinfunction "1_BM2") (pintype "bidirectional"))
    )
    (net (code "982") (name "~{LINK_DATA}") (class "Default")
      (node (ref "D12") (pin "14") (pinfunction "14_14") (pintype "passive"))
      (node (ref "U$2") (pin "CR2") (pinfunction "1_CR2") (pintype "bidirectional"))
    )
    (net (code "983") (name "~{LINK_LOAD}") (class "Default")
      (node (ref "D12") (pin "15") (pinfunction "15_15") (pintype "passive"))
      (node (ref "U$2") (pin "CS2") (pinfunction "1_CS2") (pintype "bidirectional"))
    )
    (net (code "984") (name "~{LINK}") (class "Default")
      (node (ref "D10") (pin "18") (pinfunction "18_18") (pintype "passive"))
      (node (ref "U$2") (pin "AV2") (pinfunction "1_AV2") (pintype "bidirectional"))
    )
    (net (code "985") (name "~{LOAD_CONT}") (class "Default")
      (node (ref "D8") (pin "7") (pinfunction "7_7") (pintype "passive"))
      (node (ref "U$2") (pin "BH2") (pinfunction "1_BH2") (pintype "bidirectional"))
    )
    (net (code "986") (name "~{MA00}") (class "Default")
      (node (ref "D9") (pin "4") (pinfunction "4_4") (pintype "passive"))
      (node (ref "IC3") (pin "21") (pinfunction "A10_21") (pintype "input"))
      (node (ref "IC4") (pin "21") (pinfunction "A10_21") (pintype "input"))
      (node (ref "U$2") (pin "AD1") (pinfunction "1_AD1") (pintype "bidirectional"))
    )
    (net (code "987") (name "~{MA01}") (class "Default")
      (node (ref "D9") (pin "5") (pinfunction "5_5") (pintype "passive"))
      (node (ref "IC3") (pin "23") (pinfunction "A11_23") (pintype "input"))
      (node (ref "IC4") (pin "23") (pinfunction "A11_23") (pintype "input"))
      (node (ref "U$2") (pin "AE1") (pinfunction "1_AE1") (pintype "bidirectional"))
    )
    (net (code "988") (name "~{MA02}") (class "Default")
      (node (ref "D9") (pin "7") (pinfunction "7_7") (pintype "passive"))
      (node (ref "IC3") (pin "24") (pinfunction "A9_24") (pintype "input"))
      (node (ref "IC4") (pin "24") (pinfunction "A9_24") (pintype "input"))
      (node (ref "U$2") (pin "AH1") (pinfunction "1_AH1") (pintype "bidirectional"))
    )
    (net (code "989") (name "~{MA03}") (class "Default")
      (node (ref "D9") (pin "8") (pinfunction "8_8") (pintype "passive"))
      (node (ref "IC3") (pin "25") (pinfunction "A8_25") (pintype "input"))
      (node (ref "IC4") (pin "25") (pinfunction "A8_25") (pintype "input"))
      (node (ref "U$2") (pin "AJ1") (pinfunction "1_AJ1") (pintype "bidirectional"))
    )
    (net (code "990") (name "~{MA04}") (class "Default")
      (node (ref "D7") (pin "4") (pinfunction "4_4") (pintype "passive"))
      (node (ref "IC3") (pin "26") (pinfunction "A13_26") (pintype "input"))
      (node (ref "IC4") (pin "26") (pinfunction "A13_26") (pintype "input"))
      (node (ref "U$2") (pin "BD1") (pinfunction "1_BD1") (pintype "bidirectional"))
    )
    (net (code "991") (name "~{MA05}") (class "Default")
      (node (ref "D7") (pin "5") (pinfunction "5_5") (pintype "passive"))
      (node (ref "IC3") (pin "1") (pinfunction "A14_1") (pintype "input"))
      (node (ref "IC4") (pin "1") (pinfunction "A14_1") (pintype "input"))
      (node (ref "U$2") (pin "BE1") (pinfunction "1_BE1") (pintype "bidirectional"))
    )
    (net (code "992") (name "~{MA06}") (class "Default")
      (node (ref "D7") (pin "7") (pinfunction "7_7") (pintype "passive"))
      (node (ref "IC3") (pin "2") (pinfunction "A12_2") (pintype "input"))
      (node (ref "IC4") (pin "2") (pinfunction "A12_2") (pintype "input"))
      (node (ref "U$2") (pin "BH1") (pinfunction "1_BH1") (pintype "bidirectional"))
    )
    (net (code "993") (name "~{MA07}") (class "Default")
      (node (ref "D7") (pin "8") (pinfunction "8_8") (pintype "passive"))
      (node (ref "IC3") (pin "3") (pinfunction "A7_3") (pintype "input"))
      (node (ref "IC4") (pin "3") (pinfunction "A7_3") (pintype "input"))
      (node (ref "U$2") (pin "BJ1") (pinfunction "1_BJ1") (pintype "bidirectional"))
    )
    (net (code "994") (name "~{MA08}") (class "Default")
      (node (ref "D13") (pin "4") (pinfunction "4_4") (pintype "passive"))
      (node (ref "IC3") (pin "4") (pinfunction "A6_4") (pintype "input"))
      (node (ref "IC4") (pin "4") (pinfunction "A6_4") (pintype "input"))
      (node (ref "U$2") (pin "DD1") (pinfunction "1_DD1") (pintype "bidirectional"))
    )
    (net (code "995") (name "~{MA09}") (class "Default")
      (node (ref "D13") (pin "5") (pinfunction "5_5") (pintype "passive"))
      (node (ref "IC3") (pin "5") (pinfunction "A5_5") (pintype "input"))
      (node (ref "IC4") (pin "5") (pinfunction "A5_5") (pintype "input"))
      (node (ref "U$2") (pin "DE1") (pinfunction "1_DE1") (pintype "bidirectional"))
    )
    (net (code "996") (name "~{MA10}") (class "Default")
      (node (ref "D13") (pin "7") (pinfunction "7_7") (pintype "passive"))
      (node (ref "IC3") (pin "6") (pinfunction "A4_6") (pintype "input"))
      (node (ref "IC4") (pin "6") (pinfunction "A4_6") (pintype "input"))
      (node (ref "U$2") (pin "DH1") (pinfunction "1_DH1") (pintype "bidirectional"))
    )
    (net (code "997") (name "~{MA11}") (class "Default")
      (node (ref "D13") (pin "8") (pinfunction "8_8") (pintype "passive"))
      (node (ref "IC3") (pin "7") (pinfunction "A3_7") (pintype "input"))
      (node (ref "IC4") (pin "7") (pinfunction "A3_7") (pintype "input"))
      (node (ref "U$2") (pin "DJ1") (pinfunction "1_DJ1") (pintype "bidirectional"))
    )
    (net (code "998") (name "~{MD00}") (class "Default")
      (node (ref "D9") (pin "9") (pinfunction "9_9") (pintype "passive"))
      (node (ref "IC1") (pin "2") (pinfunction "A1_2") (pintype "bidirectional"))
      (node (ref "U$2") (pin "AK1") (pinfunction "1_AK1") (pintype "bidirectional"))
    )
    (net (code "999") (name "~{MD01}") (class "Default")
      (node (ref "D9") (pin "10") (pinfunction "10_10") (pintype "passive"))
      (node (ref "IC1") (pin "3") (pinfunction "A2_3") (pintype "bidirectional"))
      (node (ref "U$2") (pin "AL1") (pinfunction "1_AL1") (pintype "bidirectional"))
    )
    (net (code "1000") (name "~{MD02}") (class "Default")
      (node (ref "D9") (pin "11") (pinfunction "11_11") (pintype "passive"))
      (node (ref "IC1") (pin "4") (pinfunction "A3_4") (pintype "bidirectional"))
      (node (ref "U$2") (pin "AM1") (pinfunction "1_AM1") (pintype "bidirectional"))
    )
    (net (code "1001") (name "~{MD03}") (class "Default")
      (node (ref "D9") (pin "13") (pinfunction "13_13") (pintype "passive"))
      (node (ref "IC1") (pin "5") (pinfunction "A4_5") (pintype "bidirectional"))
      (node (ref "U$2") (pin "AP1") (pinfunction "1_AP1") (pintype "bidirectional"))
    )
    (net (code "1002") (name "~{MD04}") (class "Default")
      (node (ref "D7") (pin "9") (pinfunction "9_9") (pintype "passive"))
      (node (ref "IC1") (pin "6") (pinfunction "A5_6") (pintype "bidirectional"))
      (node (ref "U$2") (pin "BK1") (pinfunction "1_BK1") (pintype "bidirectional"))
    )
    (net (code "1003") (name "~{MD05}") (class "Default")
      (node (ref "D7") (pin "10") (pinfunction "10_10") (pintype "passive"))
      (node (ref "IC1") (pin "7") (pinfunction "A6_7") (pintype "bidirectional"))
      (node (ref "U$2") (pin "BL1") (pinfunction "1_BL1") (pintype "bidirectional"))
    )
    (net (code "1004") (name "~{MD06}") (class "Default")
      (node (ref "D7") (pin "11") (pinfunction "11_11") (pintype "passive"))
      (node (ref "IC1") (pin "8") (pinfunction "A7_8") (pintype "bidirectional"))
      (node (ref "U$2") (pin "BM1") (pinfunction "1_BM1") (pintype "bidirectional"))
    )
    (net (code "1005") (name "~{MD07}") (class "Default")
      (node (ref "D7") (pin "13") (pinfunction "13_13") (pintype "passive"))
      (node (ref "IC1") (pin "9") (pinfunction "A8_9") (pintype "bidirectional"))
      (node (ref "U$2") (pin "BP1") (pinfunction "1_BP1") (pintype "bidirectional"))
    )
    (net (code "1006") (name "~{MD08}") (class "Default")
      (node (ref "D13") (pin "9") (pinfunction "9_9") (pintype "passive"))
      (node (ref "IC2") (pin "2") (pinfunction "A1_2") (pintype "bidirectional"))
      (node (ref "U$2") (pin "DK1") (pinfunction "1_DK1") (pintype "bidirectional"))
    )
    (net (code "1007") (name "~{MD09}") (class "Default")
      (node (ref "D13") (pin "10") (pinfunction "10_10") (pintype "passive"))
      (node (ref "IC2") (pin "3") (pinfunction "A2_3") (pintype "bidirectional"))
      (node (ref "U$2") (pin "DL1") (pinfunction "1_DL1") (pintype "bidirectional"))
    )
    (net (code "1008") (name "~{MD10}") (class "Default")
      (node (ref "D13") (pin "11") (pinfunction "11_11") (pintype "passive"))
      (node (ref "IC2") (pin "4") (pinfunction "A3_4") (pintype "bidirectional"))
      (node (ref "U$2") (pin "DM1") (pinfunction "1_DM1") (pintype "bidirectional"))
    )
    (net (code "1009") (name "~{MD11}") (class "Default")
      (node (ref "D13") (pin "13") (pinfunction "13_13") (pintype "passive"))
      (node (ref "IC2") (pin "5") (pinfunction "A4_5") (pintype "bidirectional"))
      (node (ref "U$2") (pin "DP1") (pinfunction "1_DP1") (pintype "bidirectional"))
    )
    (net (code "1010") (name "~{MD_DIR}") (class "Default")
      (node (ref "D10") (pin "9") (pinfunction "9_9") (pintype "passive"))
      (node (ref "IC8") (pin "1") (pinfunction "I_1") (pintype "input"))
      (node (ref "U$2") (pin "AK2") (pinfunction "1_AK2") (pintype "bidirectional"))
    )
    (net (code "1011") (name "~{MEM_START}") (class "Default")
      (node (ref "D10") (pin "8") (pinfunction "8_8") (pintype "passive"))
      (node (ref "U$2") (pin "AJ2") (pinfunction "1_AJ2") (pintype "bidirectional"))
    )
    (net (code "1012") (name "~{MS_DISABLE}") (class "Default")
      (node (ref "D11") (pin "18") (pinfunction "18_18") (pintype "passive"))
      (node (ref "U$2") (pin "CV1") (pinfunction "1_CV1") (pintype "bidirectional"))
    )
    (net (code "1013") (name "~{NOT_LAST_TR}") (class "Default")
      (node (ref "D11") (pin "11") (pinfunction "11_11") (pintype "passive"))
      (node (ref "U$2") (pin "CM1") (pinfunction "1_CM1") (pintype "bidirectional"))
    )
    (net (code "1014") (name "~{NTS_STALL}") (class "Default")
      (node (ref "D8") (pin "14") (pinfunction "14_14") (pintype "passive"))
      (node (ref "U$2") (pin "BR2") (pinfunction "1_BR2") (pintype "bidirectional"))
    )
    (net (code "1015") (name "~{OVERFLOW}") (class "Default")
      (node (ref "D8") (pin "8") (pinfunction "8_8") (pintype "passive"))
      (node (ref "U$2") (pin "BJ2") (pinfunction "1_BJ2") (pintype "bidirectional"))
    )
    (net (code "1016") (name "~{READ_EN}") (class "Default")
      (node (ref "IC1") (pin "1") (pinfunction "DIR_1") (pintype "input"))
      (node (ref "IC2") (pin "1") (pinfunction "DIR_1") (pintype "input"))
      (node (ref "IC3") (pin "22") (pinfunction "~{OE}_22") (pintype "input"))
      (node (ref "IC4") (pin "22") (pinfunction "~{OE}_22") (pintype "input"))
      (node (ref "IC7") (pin "8") (pinfunction "O_8") (pintype "output"))
    )
    (net (code "1017") (name "~{ROM_ADDR}") (class "Default")
      (node (ref "D10") (pin "17") (pinfunction "17_17") (pintype "passive"))
      (node (ref "IC5") (pin "6") (pinfunction "G1_6") (pintype "input"))
      (node (ref "U$2") (pin "AU2") (pinfunction "1_AU2") (pintype "bidirectional"))
    )
    (net (code "1018") (name "~{RUN}") (class "Default")
      (node (ref "D8") (pin "17") (pinfunction "17_17") (pintype "passive"))
      (node (ref "U$2") (pin "BU2") (pinfunction "1_BU2") (pintype "bidirectional"))
    )
    (net (code "1019") (name "~{SKIP}") (class "Default")
      (node (ref "D11") (pin "15") (pinfunction "15_15") (pintype "passive"))
      (node (ref "U$2") (pin "CS1") (pinfunction "1_CS1") (pintype "bidirectional"))
    )
    (net (code "1020") (name "~{STOP}") (class "Default")
      (node (ref "D14") (pin "15") (pinfunction "15_15") (pintype "passive"))
      (node (ref "U$2") (pin "DS2") (pinfunction "1_DS2") (pintype "bidirectional"))
    )
    (net (code "1021") (name "~{TS1}") (class "Default")
      (node (ref "D12") (pin "9") (pinfunction "9_9") (pintype "passive"))
      (node (ref "U$2") (pin "CK2") (pinfunction "1_CK2") (pintype "bidirectional"))
    )
    (net (code "1022") (name "~{TS2}") (class "Default")
      (node (ref "D12") (pin "10") (pinfunction "10_10") (pintype "passive"))
      (node (ref "U$2") (pin "CL2") (pinfunction "1_CL2") (pintype "bidirectional"))
    )
    (net (code "1023") (name "~{TS3}") (class "Default")
      (node (ref "D12") (pin "11") (pinfunction "11_11") (pintype "passive"))
      (node (ref "U$2") (pin "CM2") (pinfunction "1_CM2") (pintype "bidirectional"))
    )
    (net (code "1024") (name "~{TS4}") (class "Default")
      (node (ref "D12") (pin "13") (pinfunction "13_13") (pintype "passive"))
      (node (ref "U$2") (pin "CP2") (pinfunction "1_CP2") (pintype "bidirectional"))
    )
    (net (code "1025") (name "~{USER_MODE}") (class "Default")
      (node (ref "D14") (pin "11") (pinfunction "11_11") (pintype "passive"))
      (node (ref "U$2") (pin "DM2") (pinfunction "1_DM2") (pintype "bidirectional"))
    )
    (net (code "1026") (name "~{WRITE_EN}") (class "Default")
      (node (ref "IC3") (pin "27") (pinfunction "~{WE}_27") (pintype "input"))
      (node (ref "IC4") (pin "27") (pinfunction "~{WE}_27") (pintype "input"))
      (node (ref "IC7") (pin "6") (pinfunction "O_6") (pintype "output"))
    )
  )
)
